# BEP33_6panel_90Grad.net
KiCad netlist of a schematic drawn in EAGLE
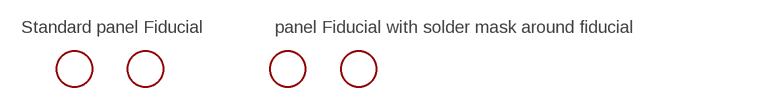
[diagram p0: schematic, sheet 1]
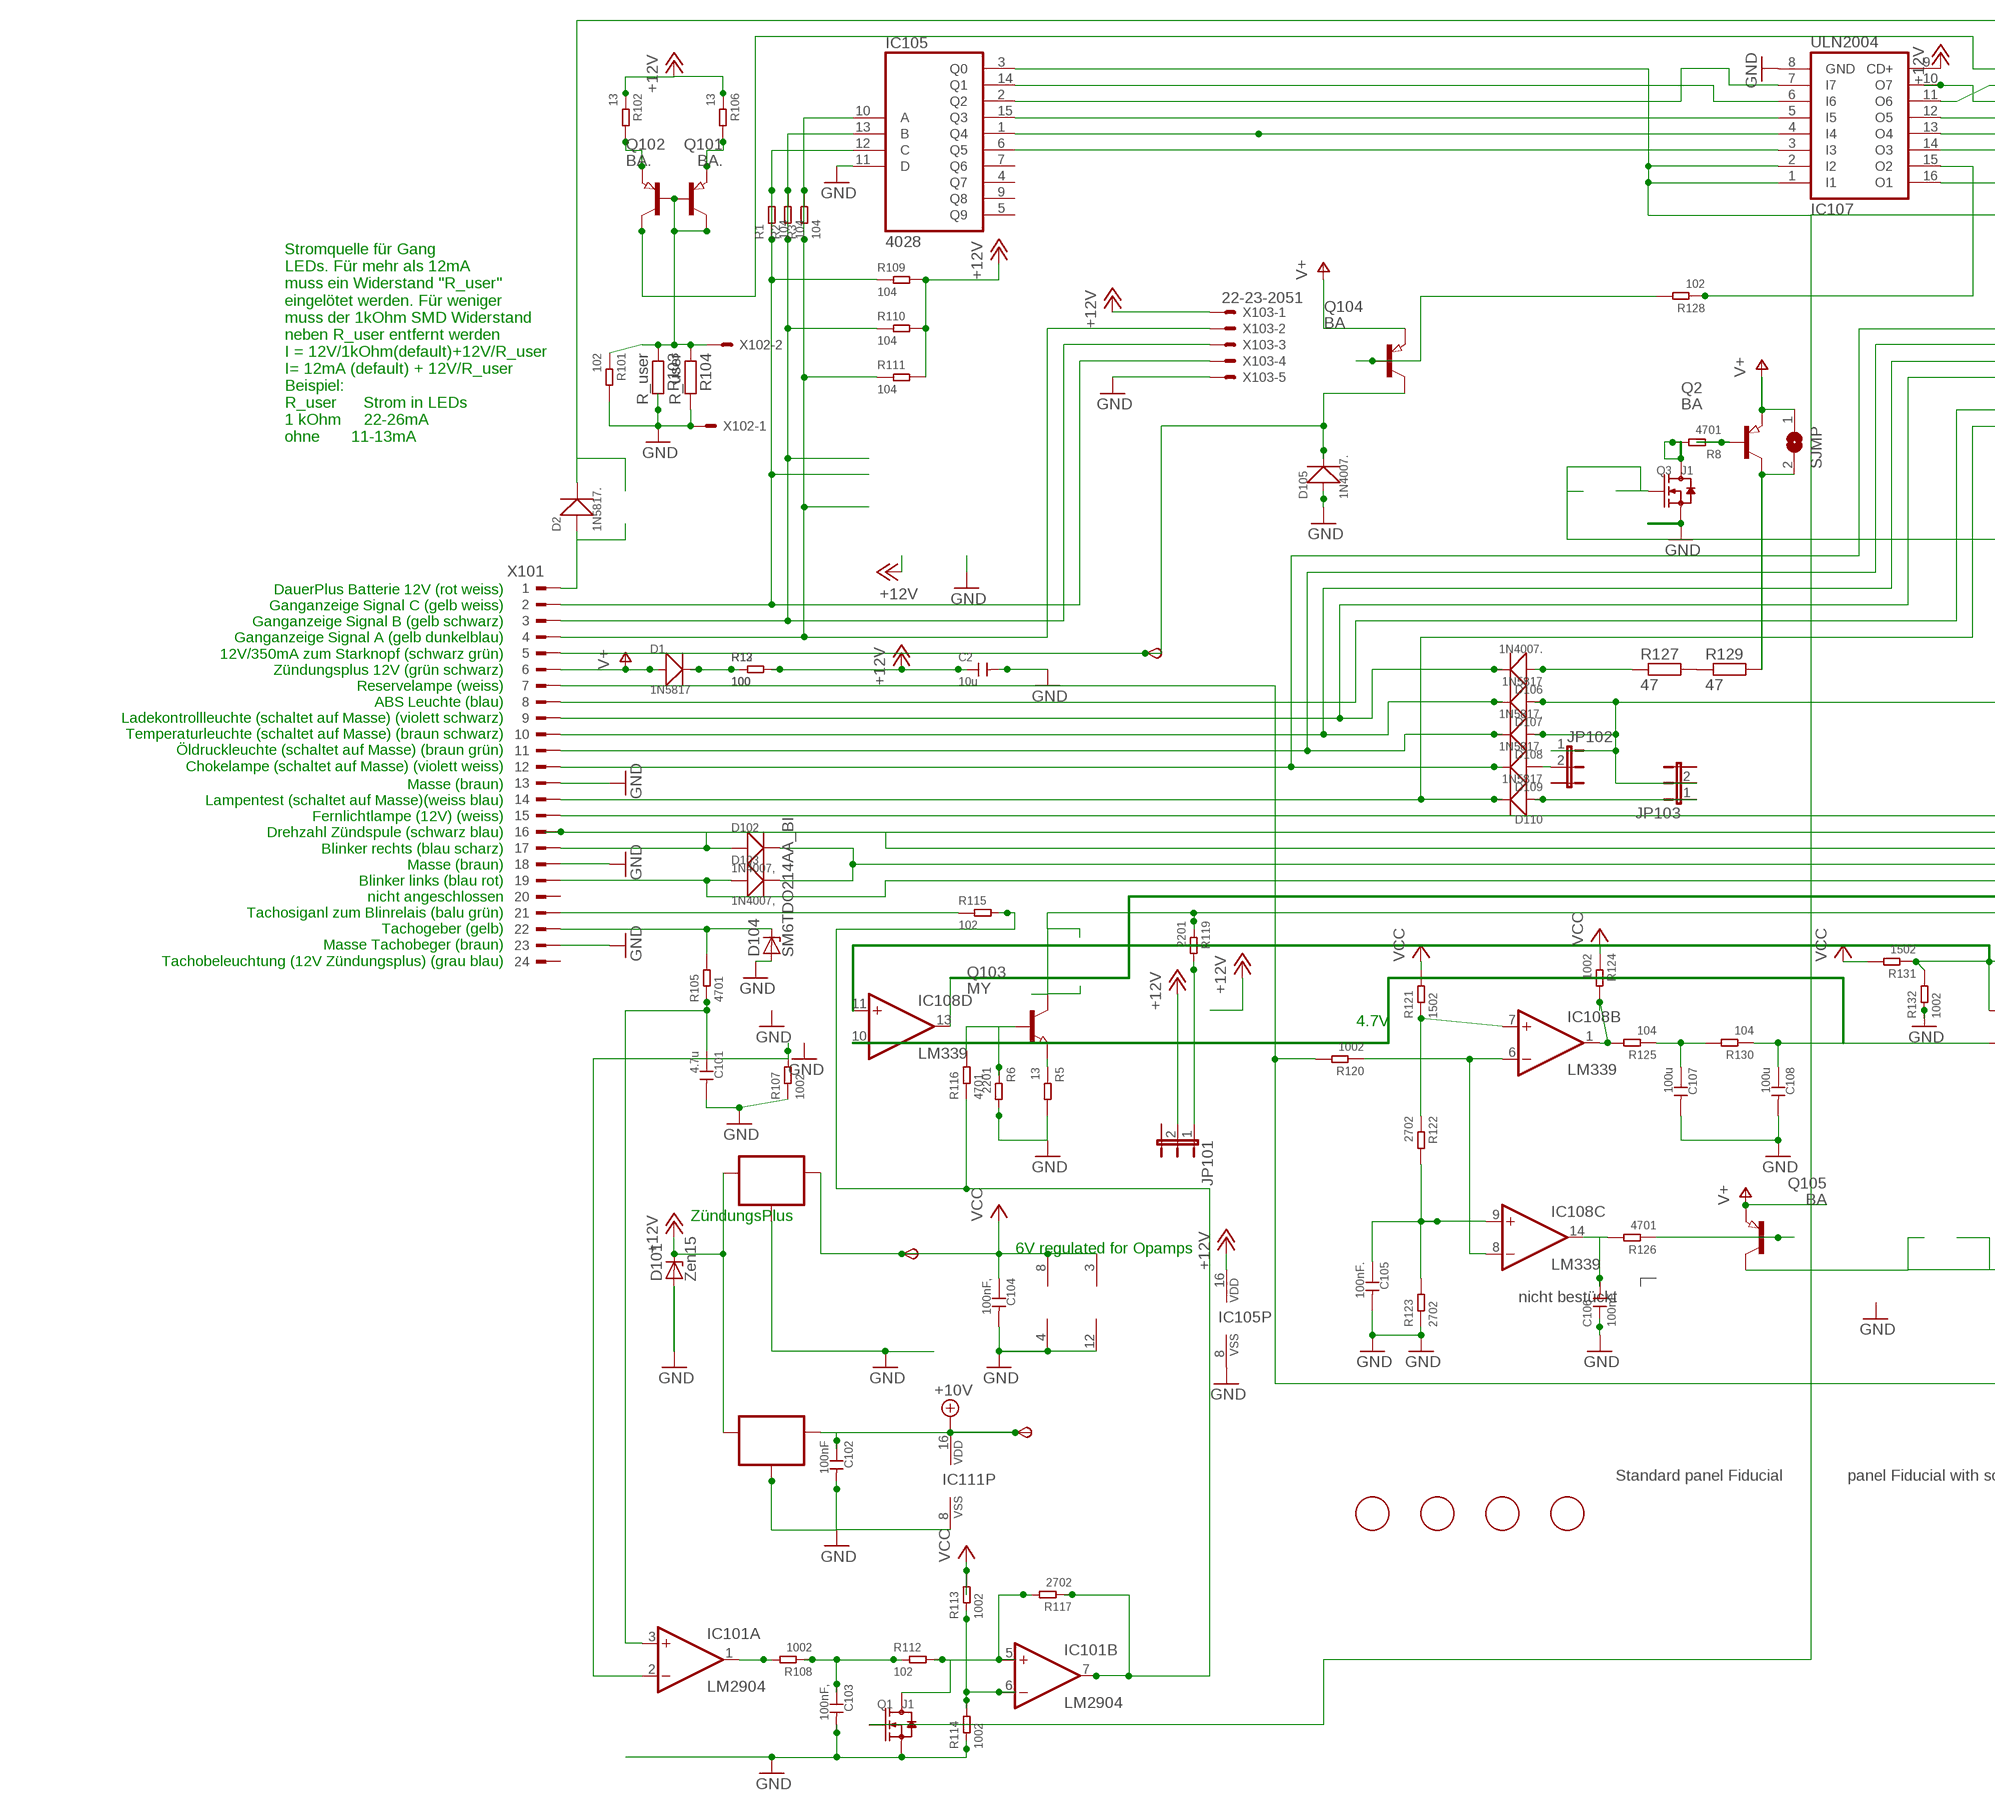
[diagram p1: schematic, sheet 2, part 1 of 2]
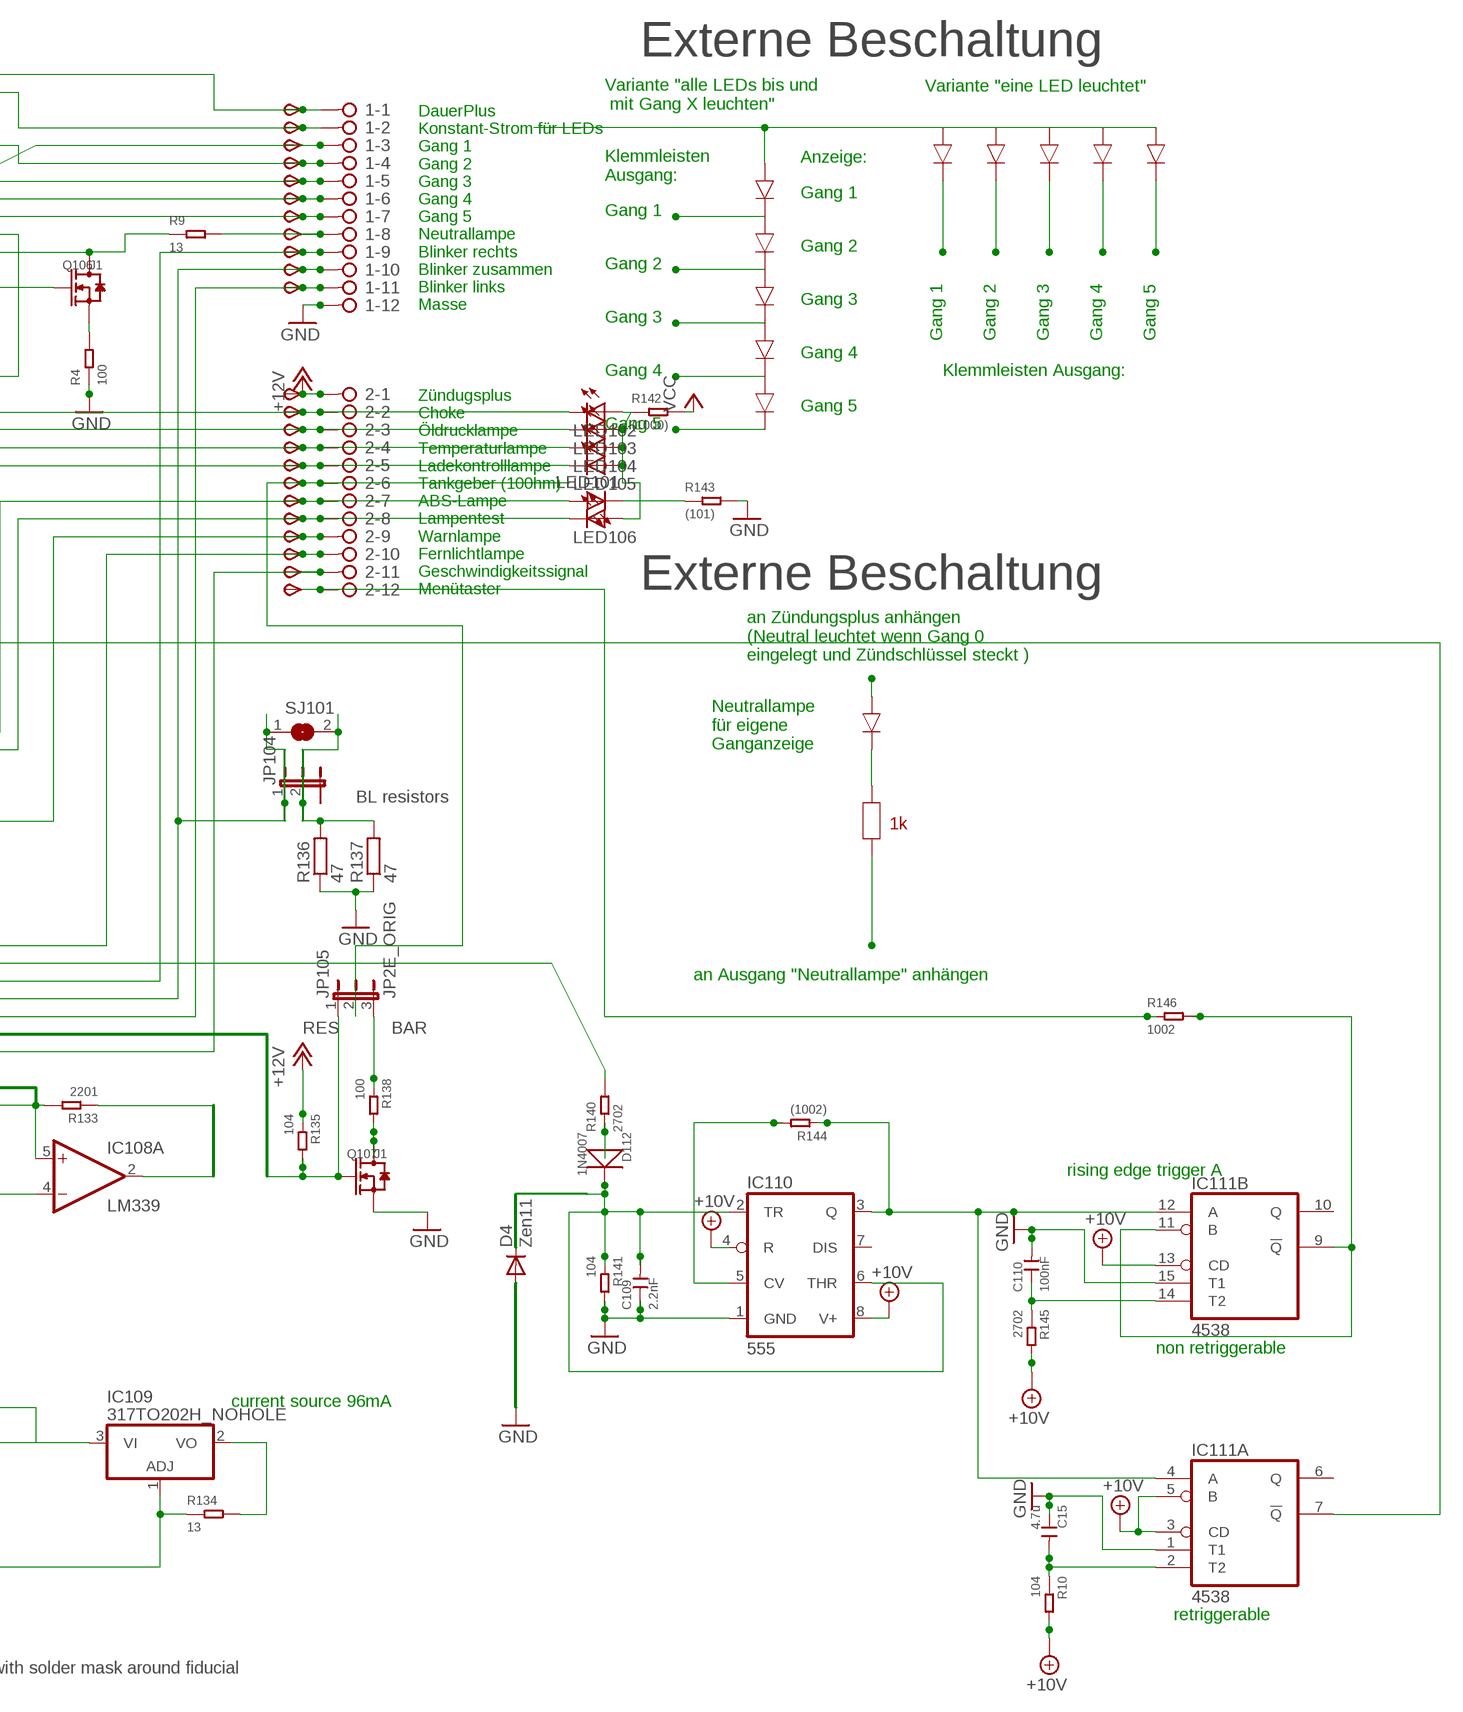
[diagram p2: schematic, sheet 2, part 2 of 2]
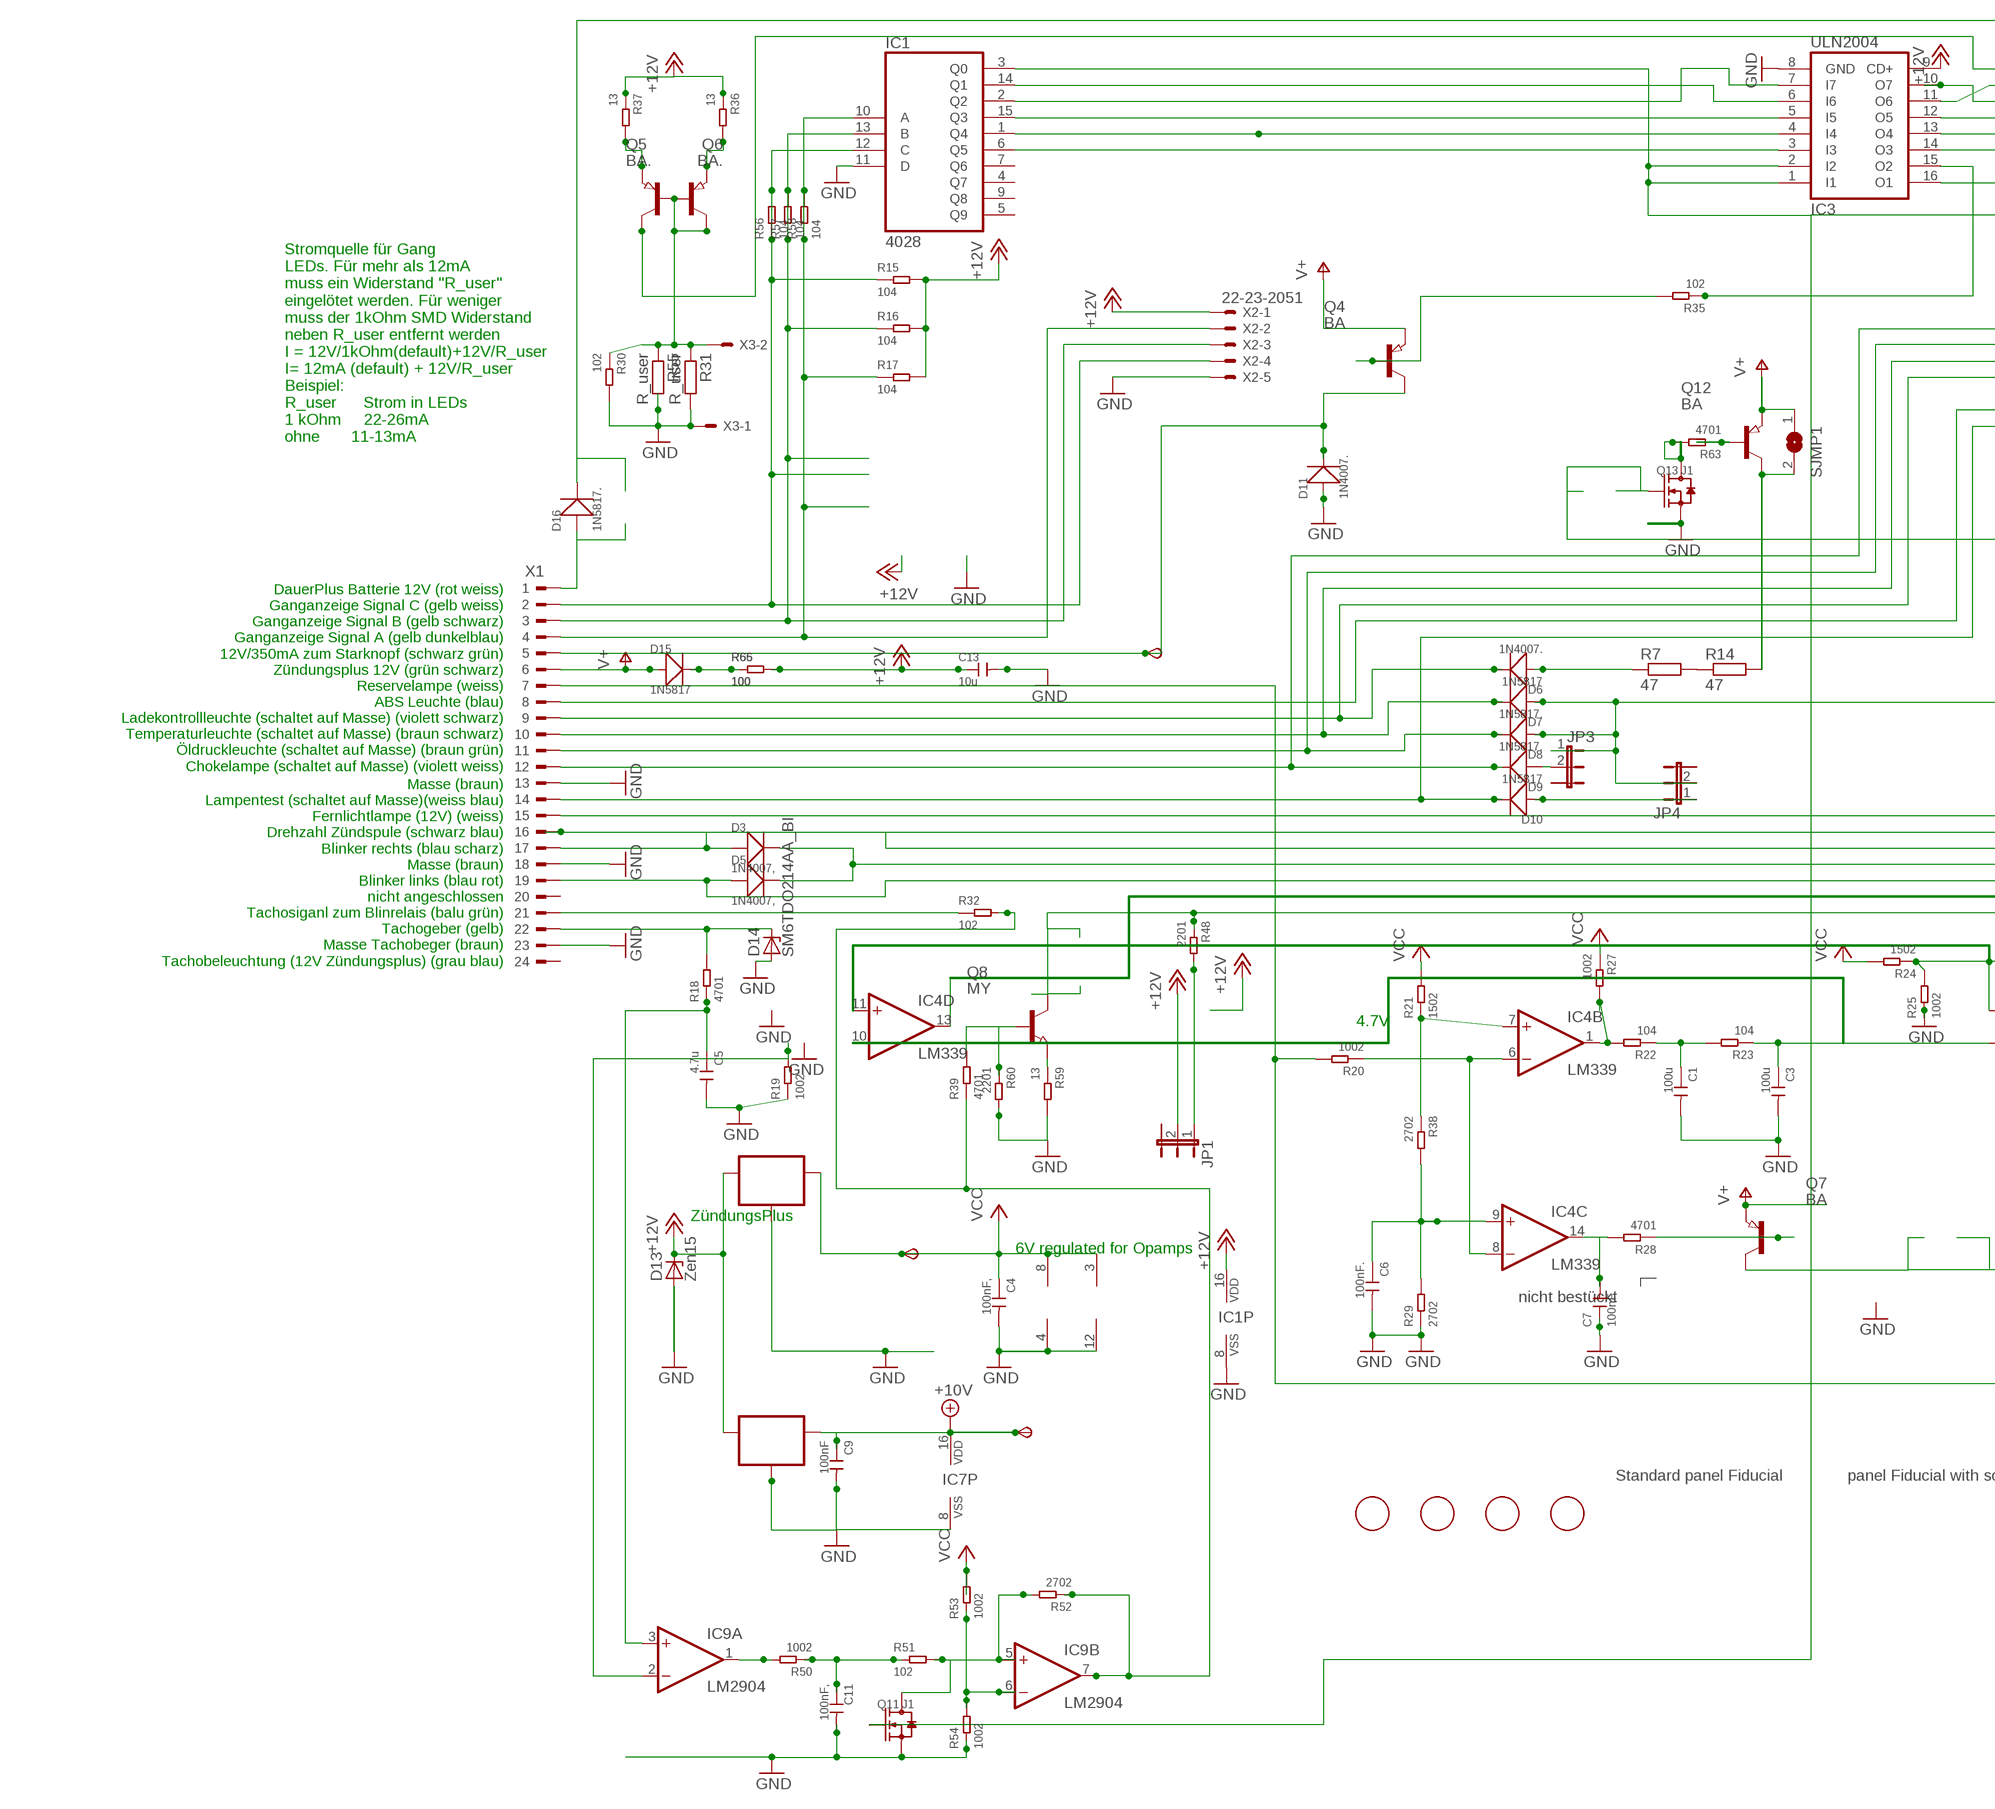
[diagram p3: schematic, sheet 3, part 1 of 2]
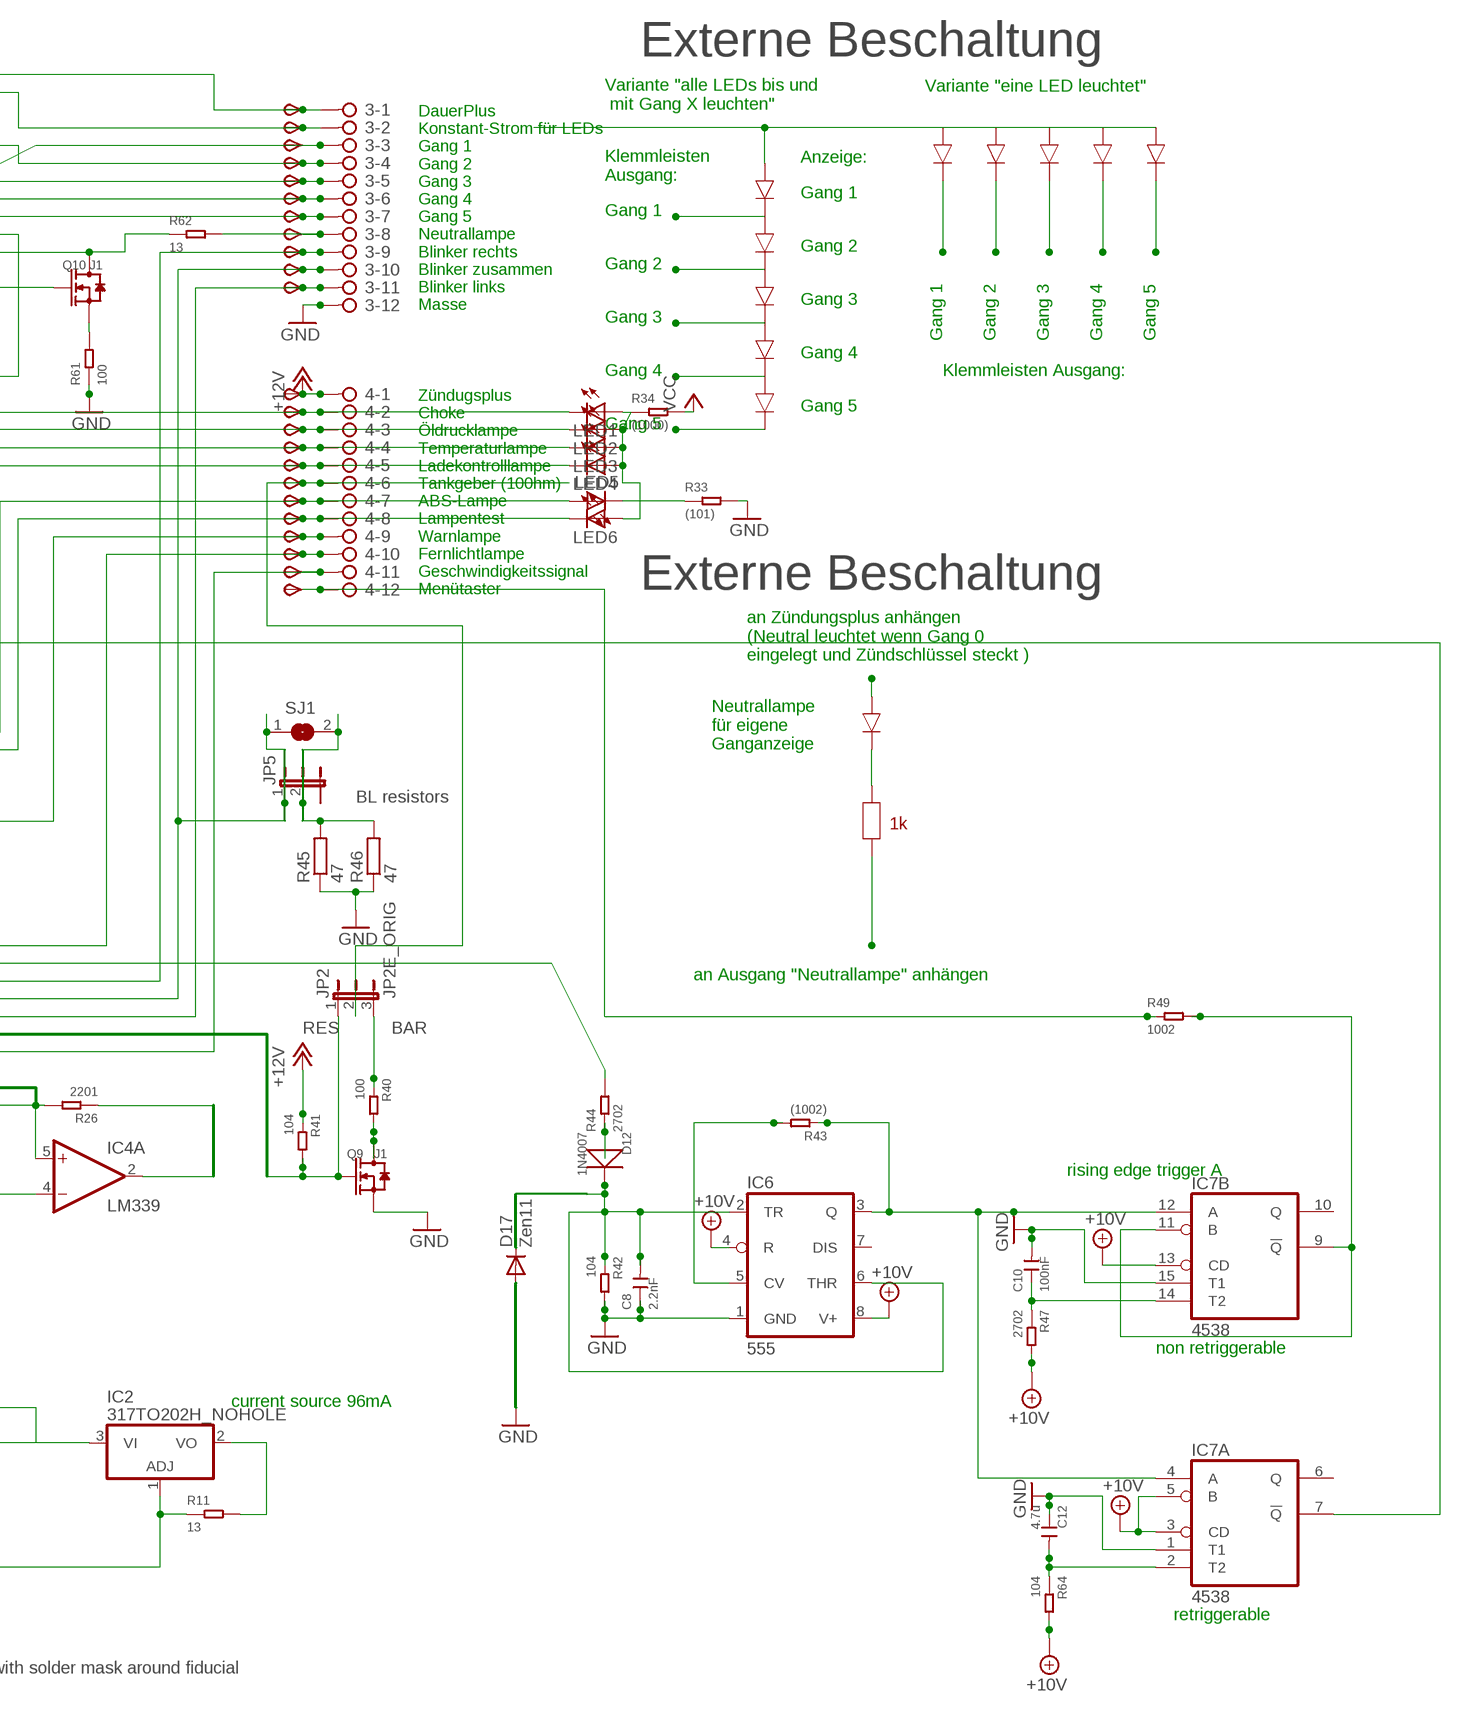
[diagram p4: schematic, sheet 3, part 2 of 2]
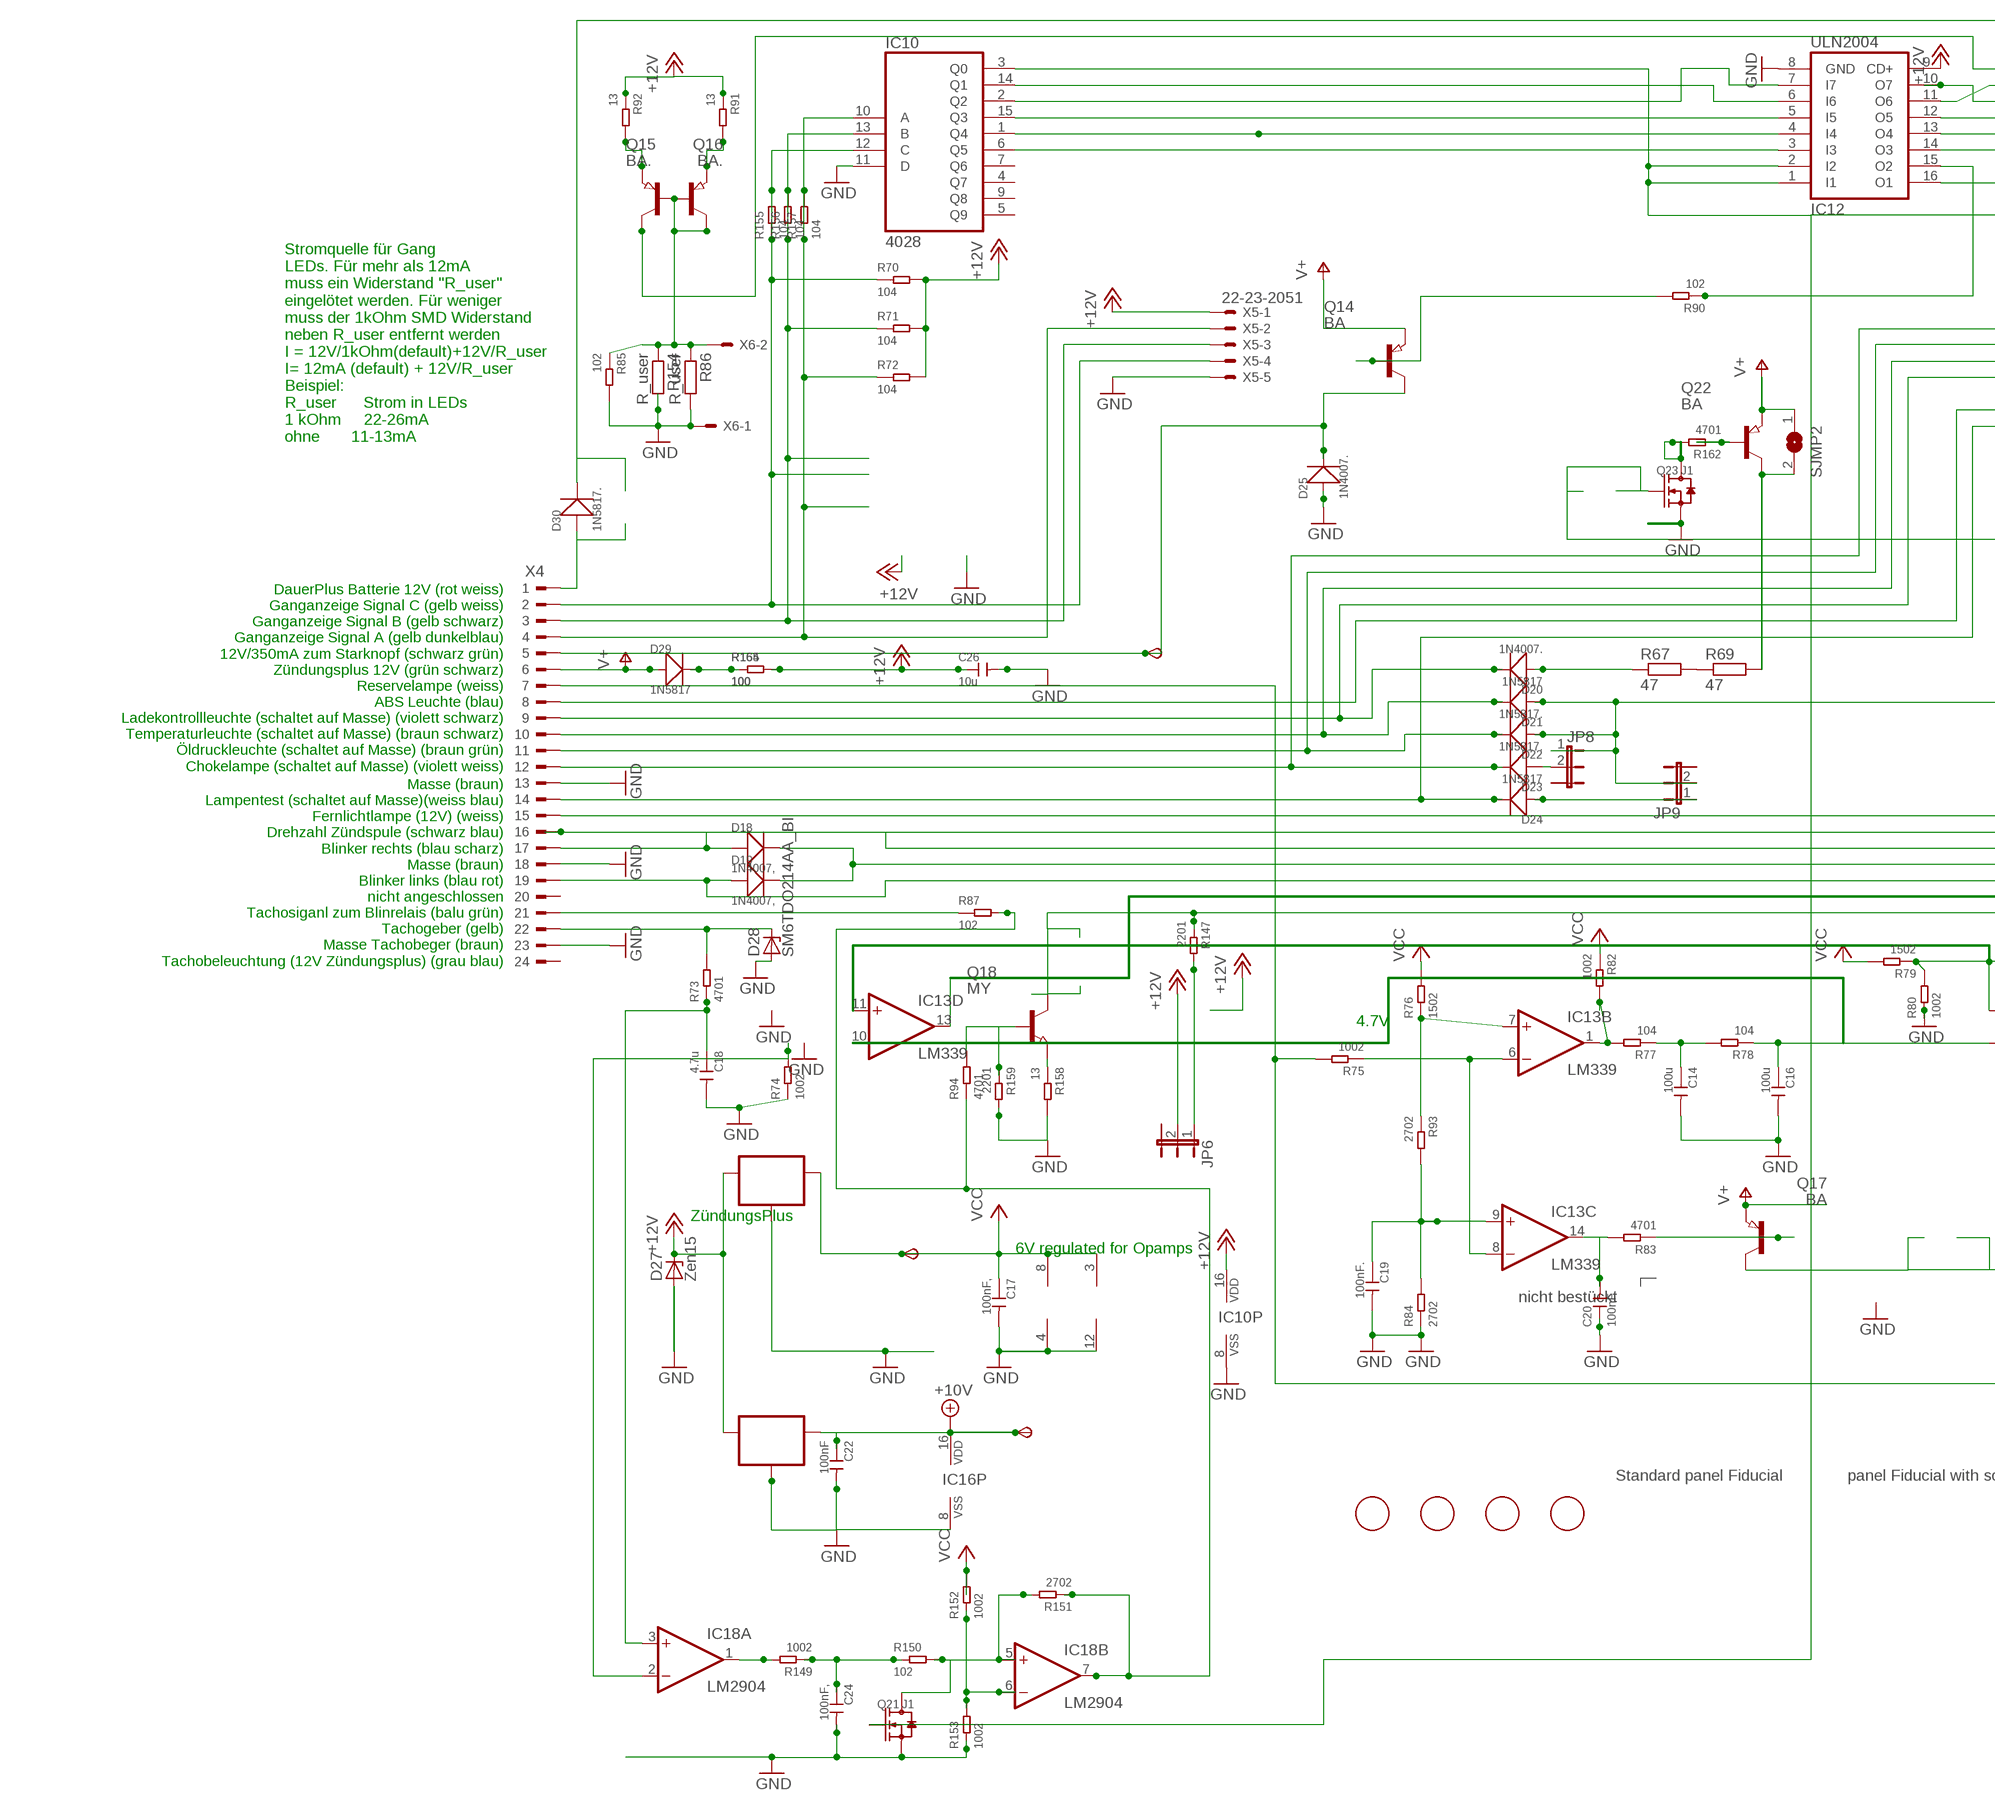
[diagram p5: schematic, sheet 4, part 1 of 2]
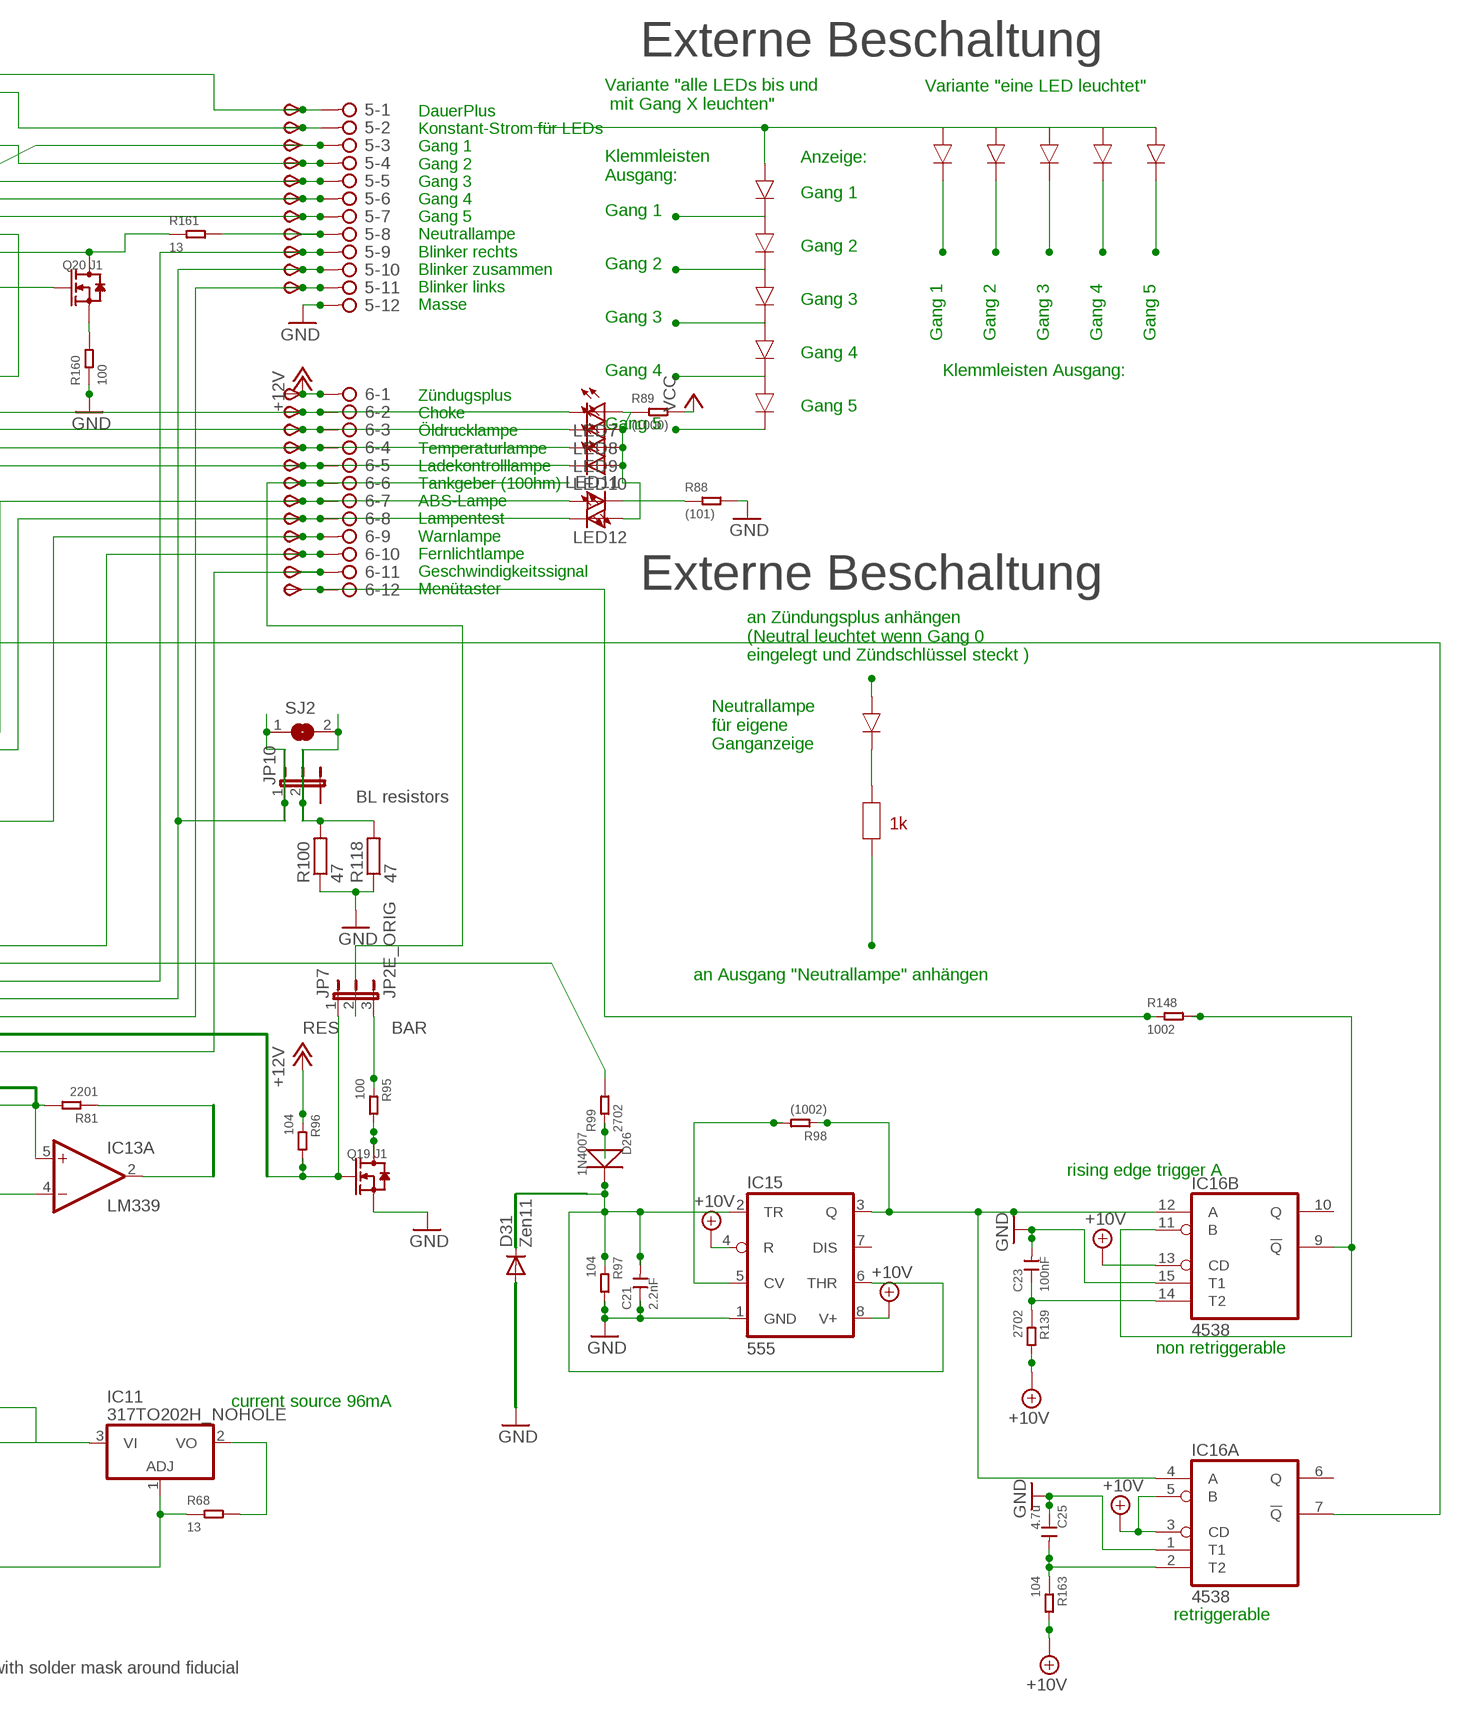
[diagram p6: schematic, sheet 4, part 2 of 2]
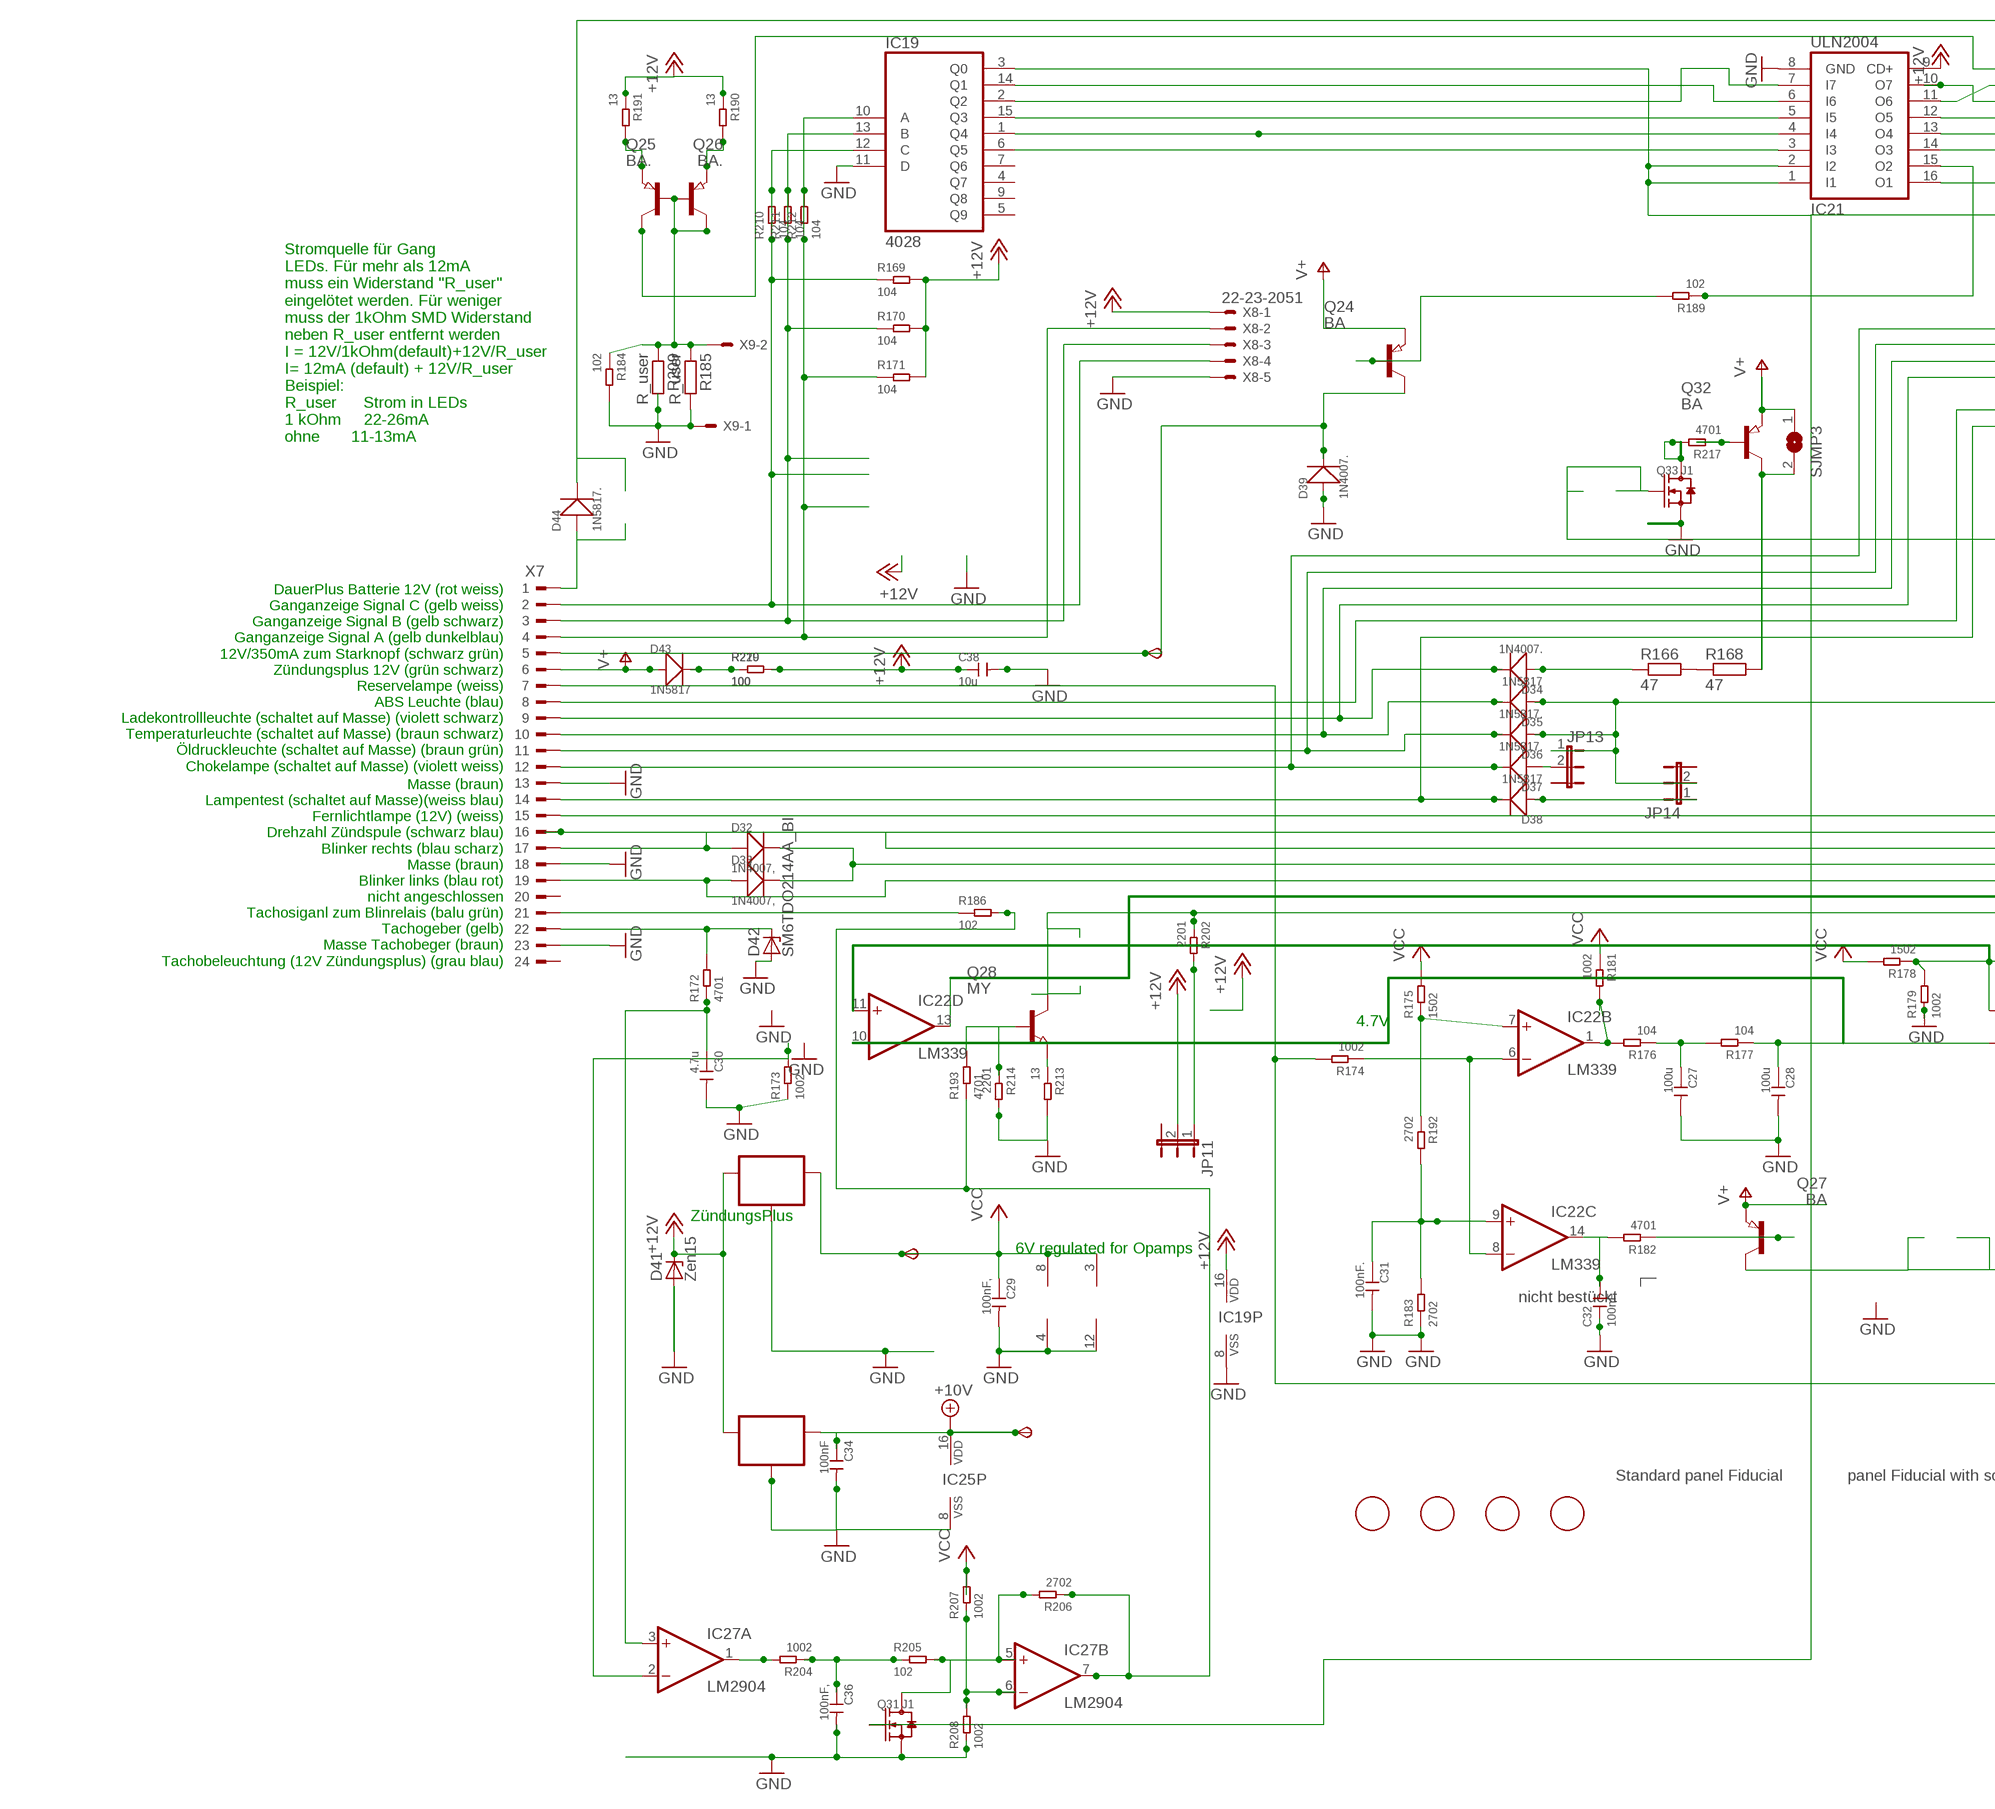
[diagram p7: schematic, sheet 5, part 1 of 2]
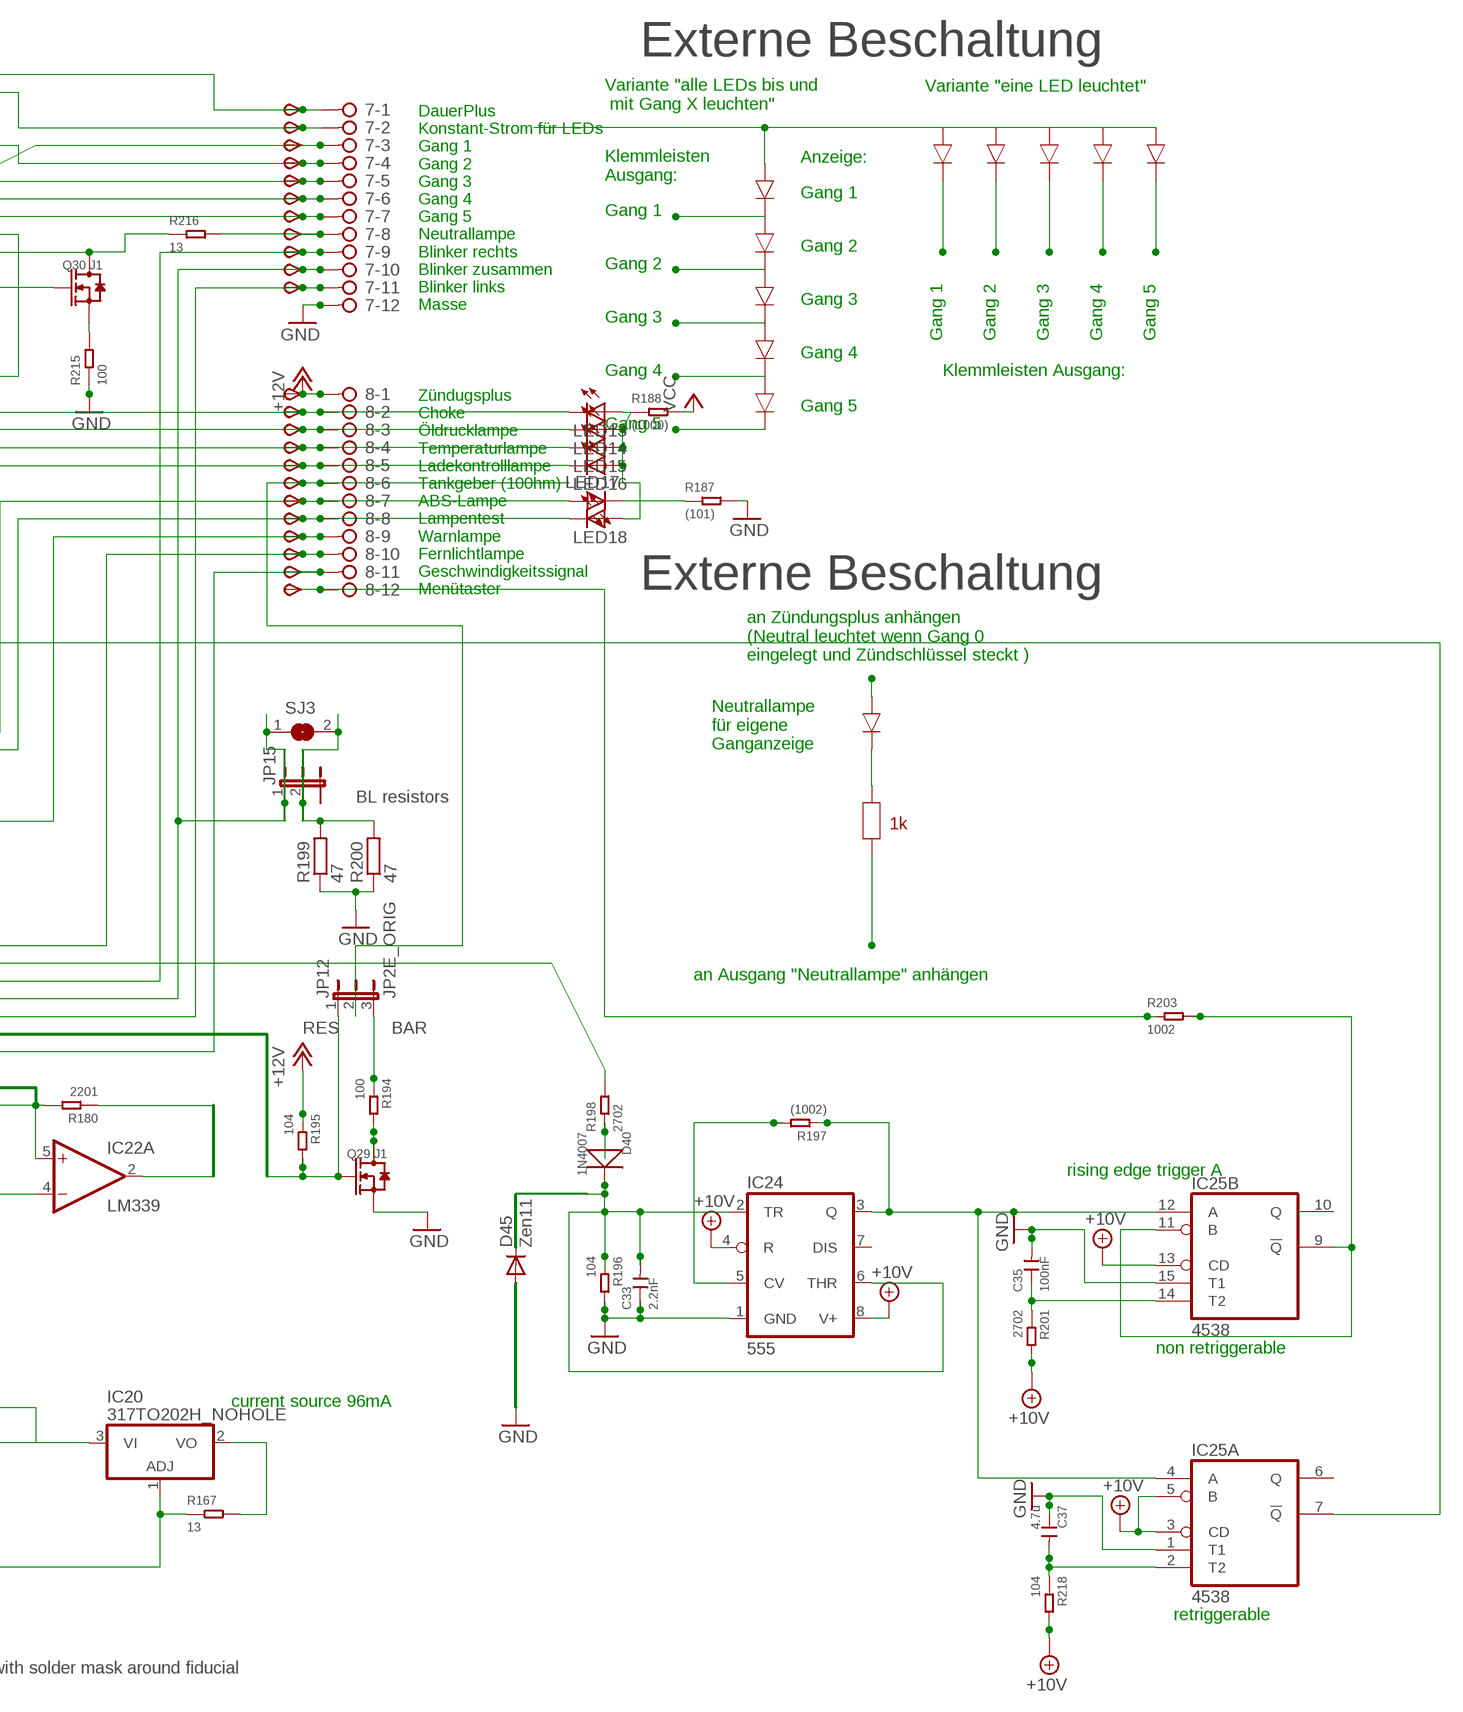
[diagram p8: schematic, sheet 5, part 2 of 2]
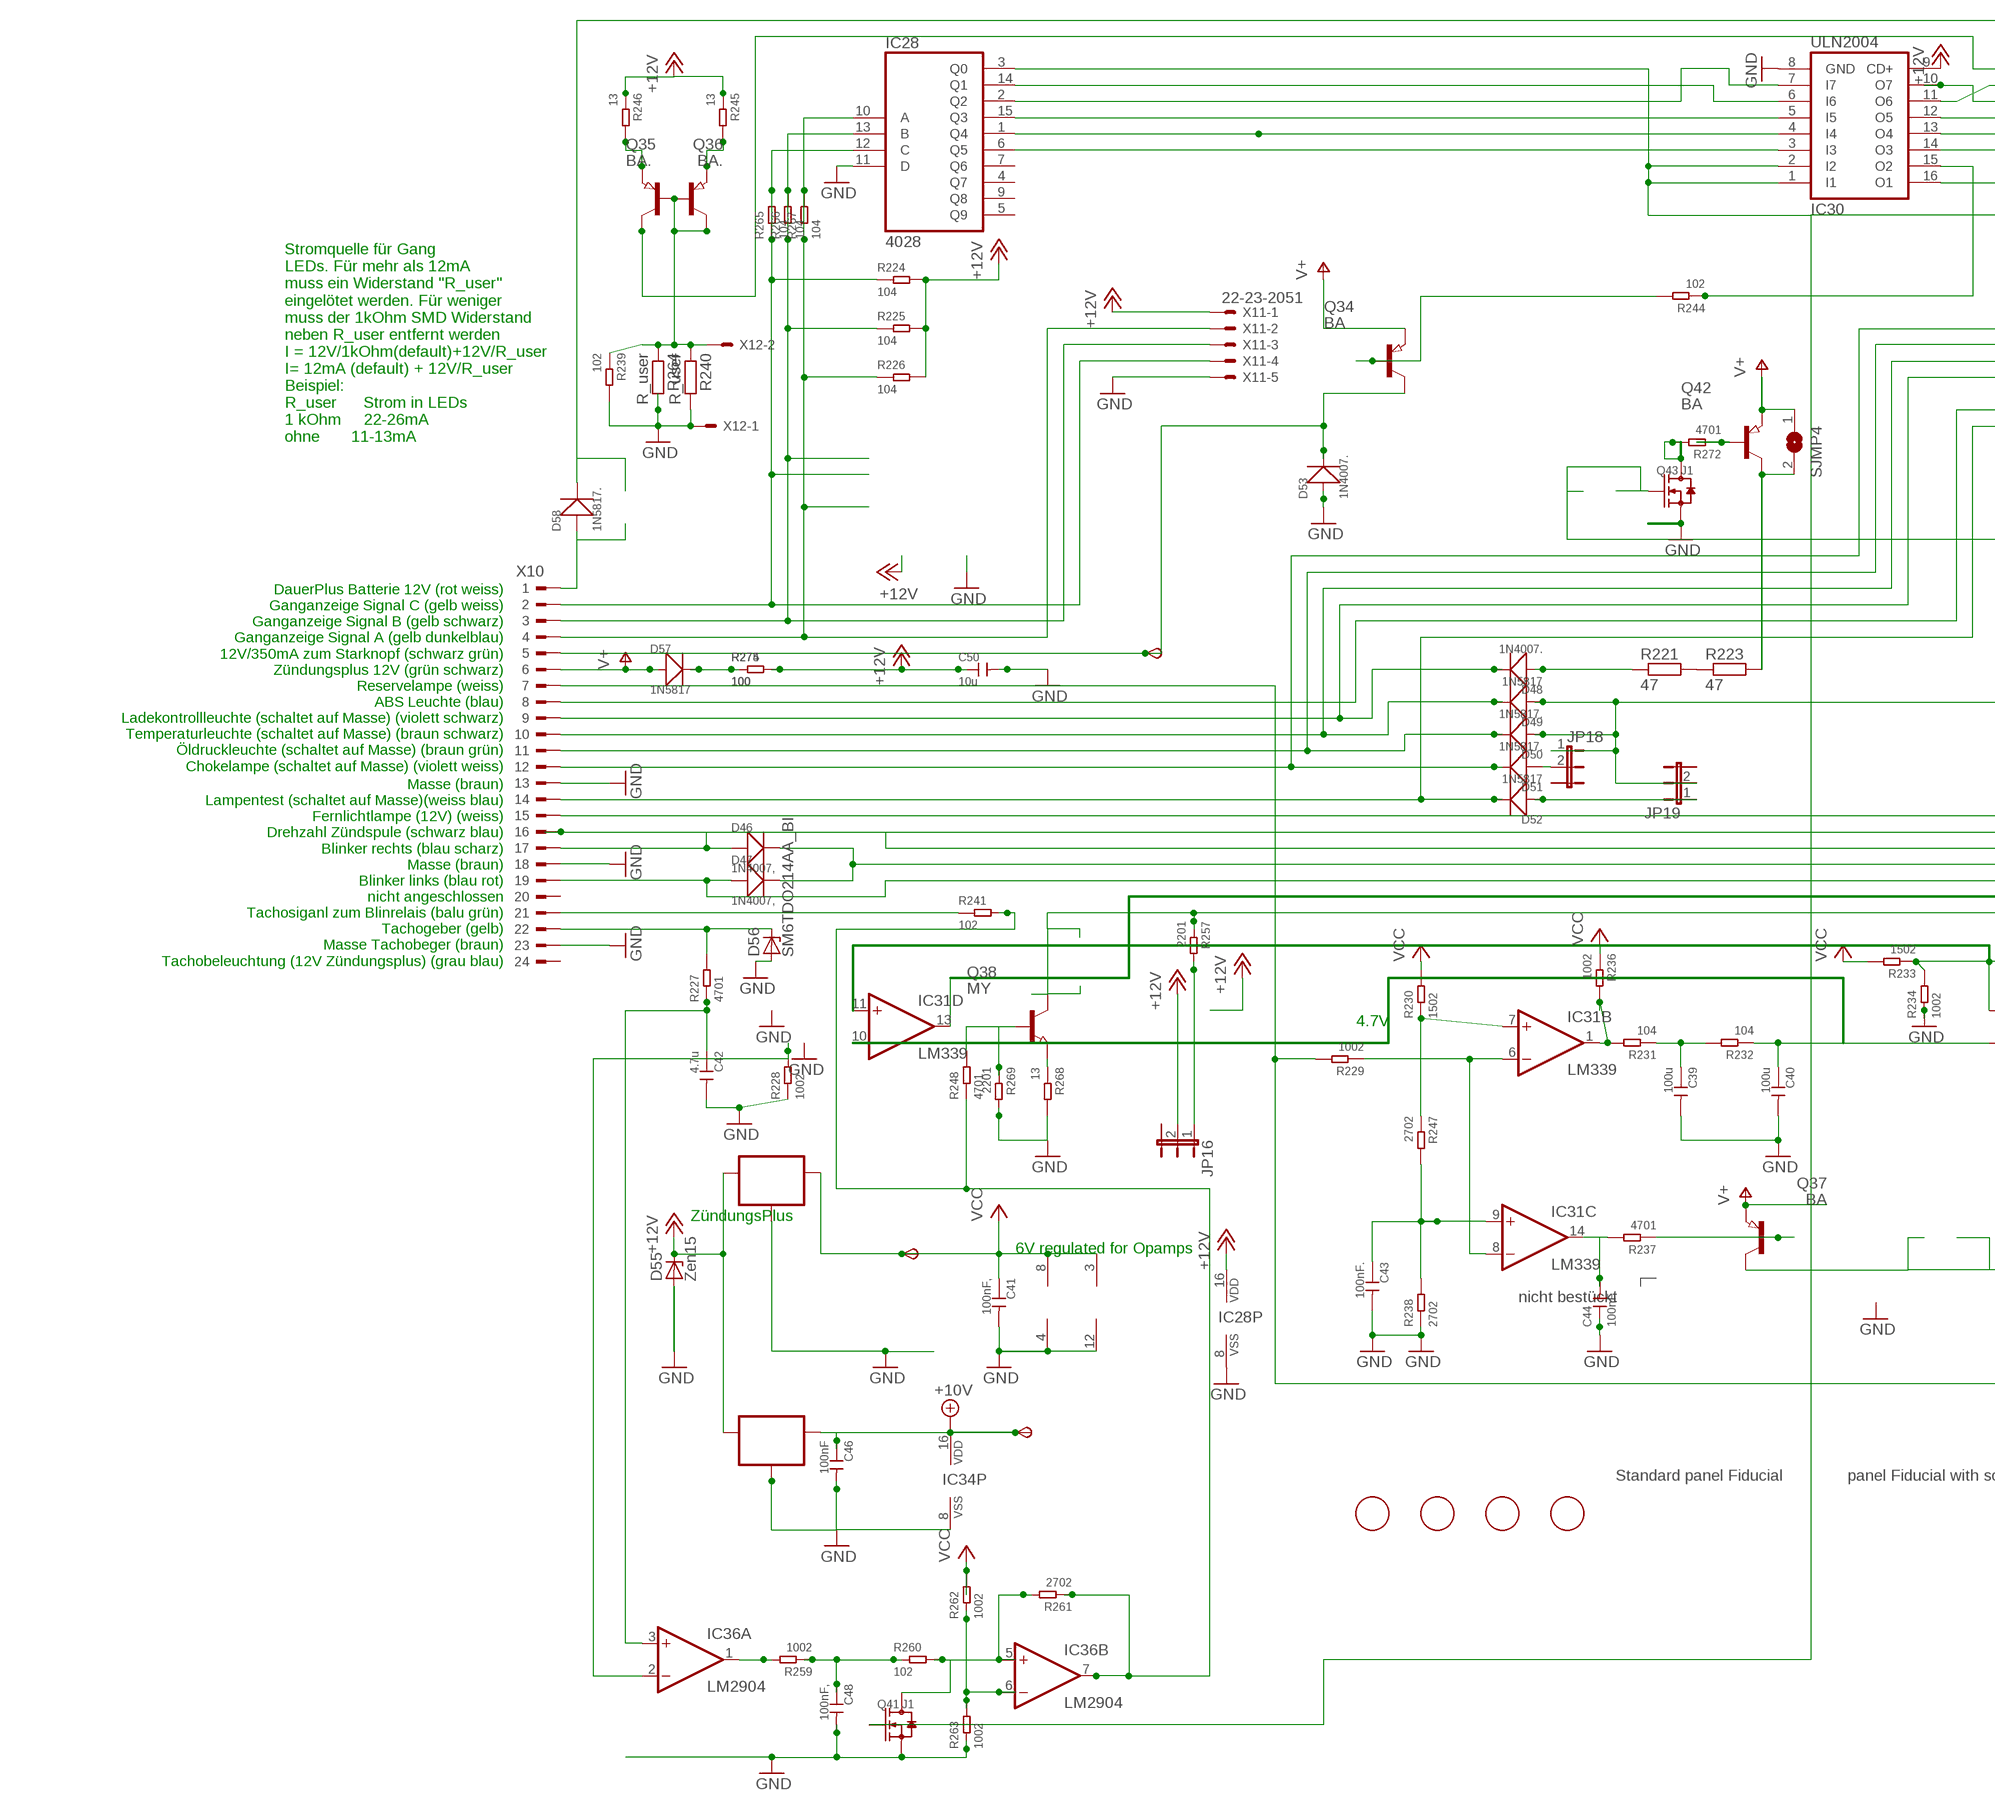
[diagram p9: schematic, sheet 6, part 1 of 2]
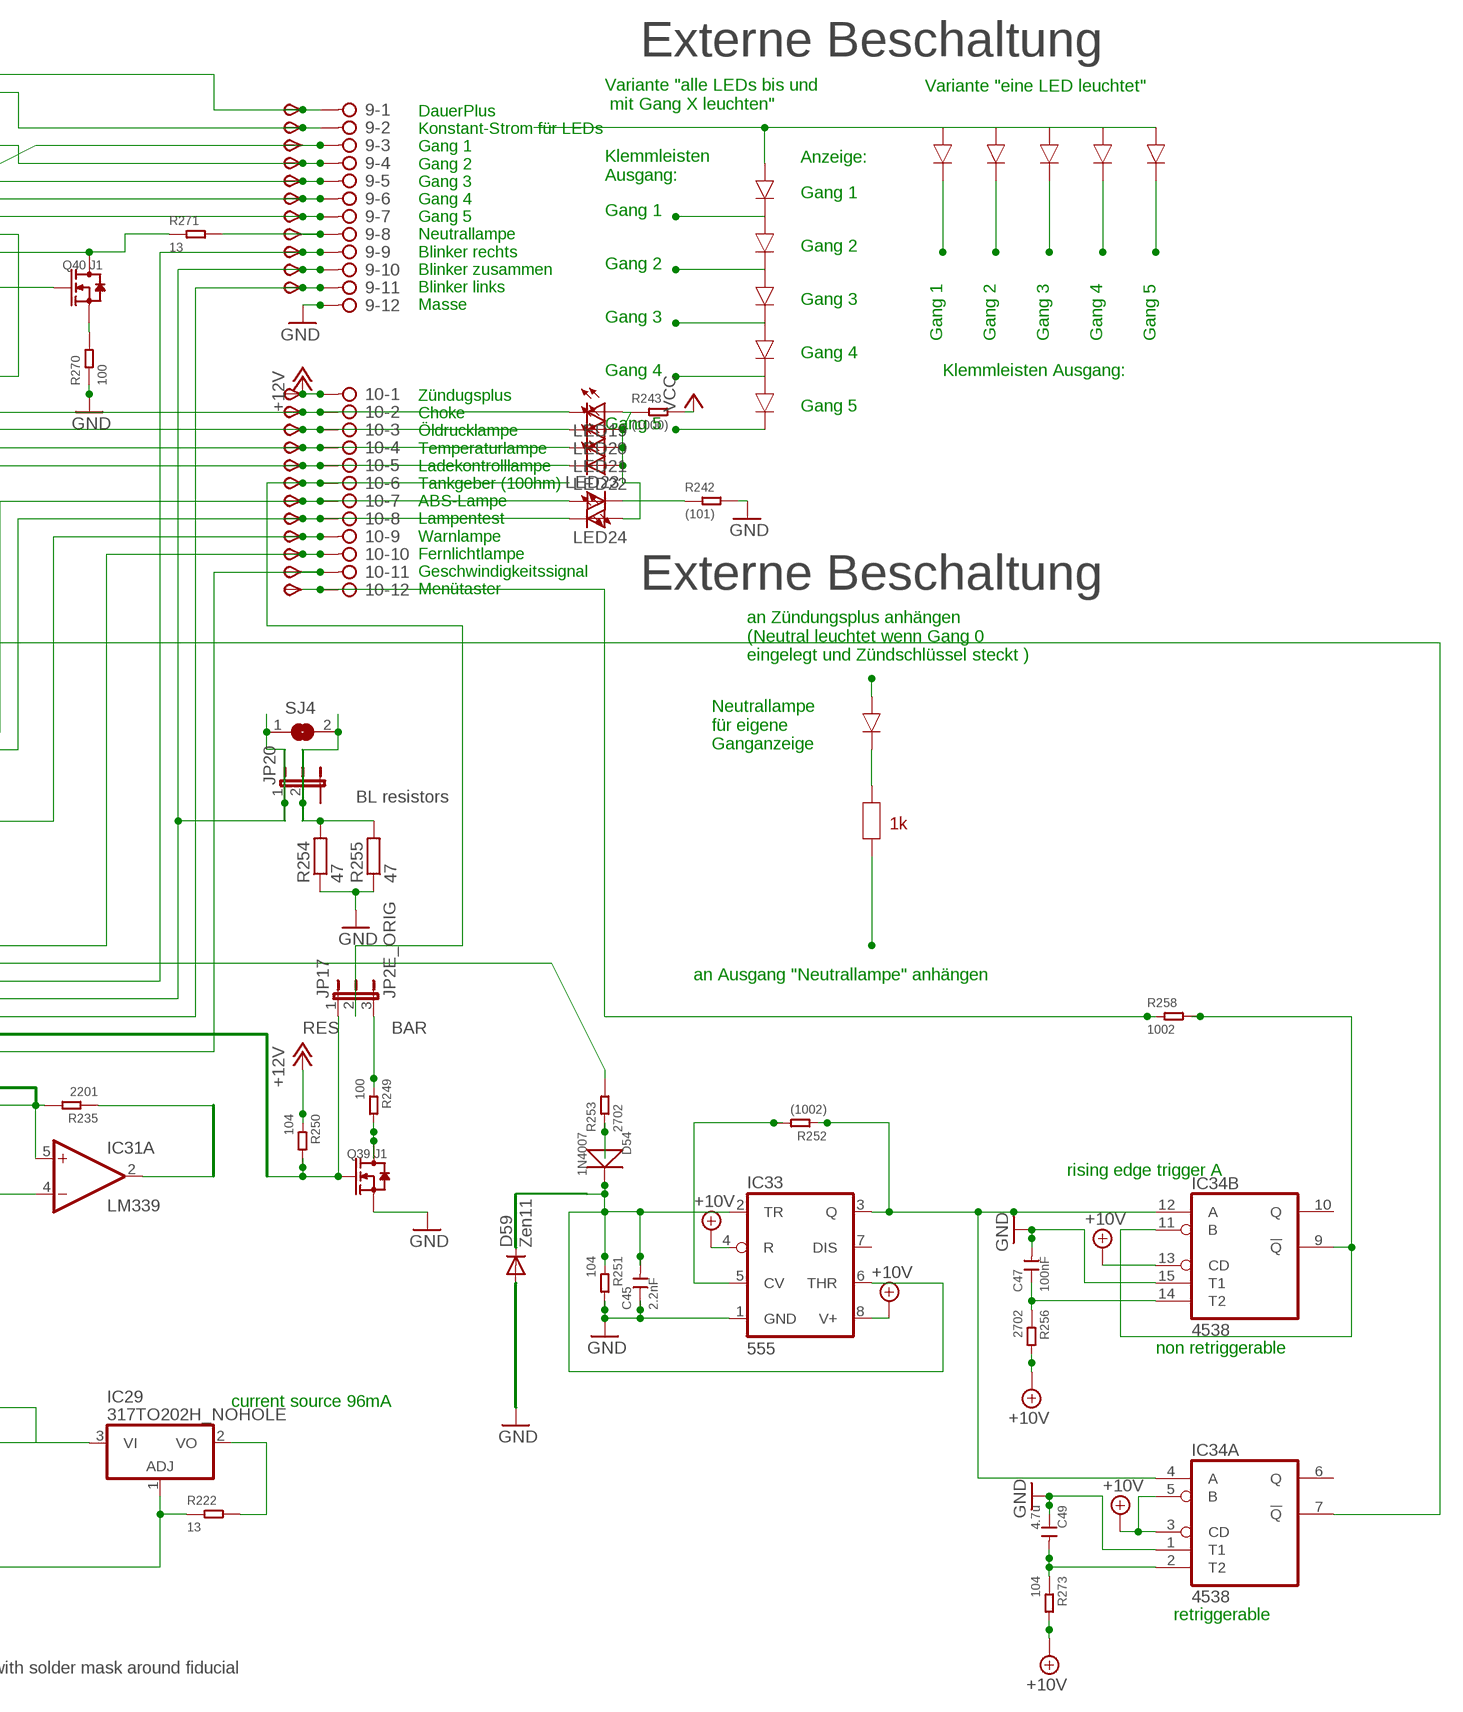
[diagram p10: schematic, sheet 6, part 2 of 2]
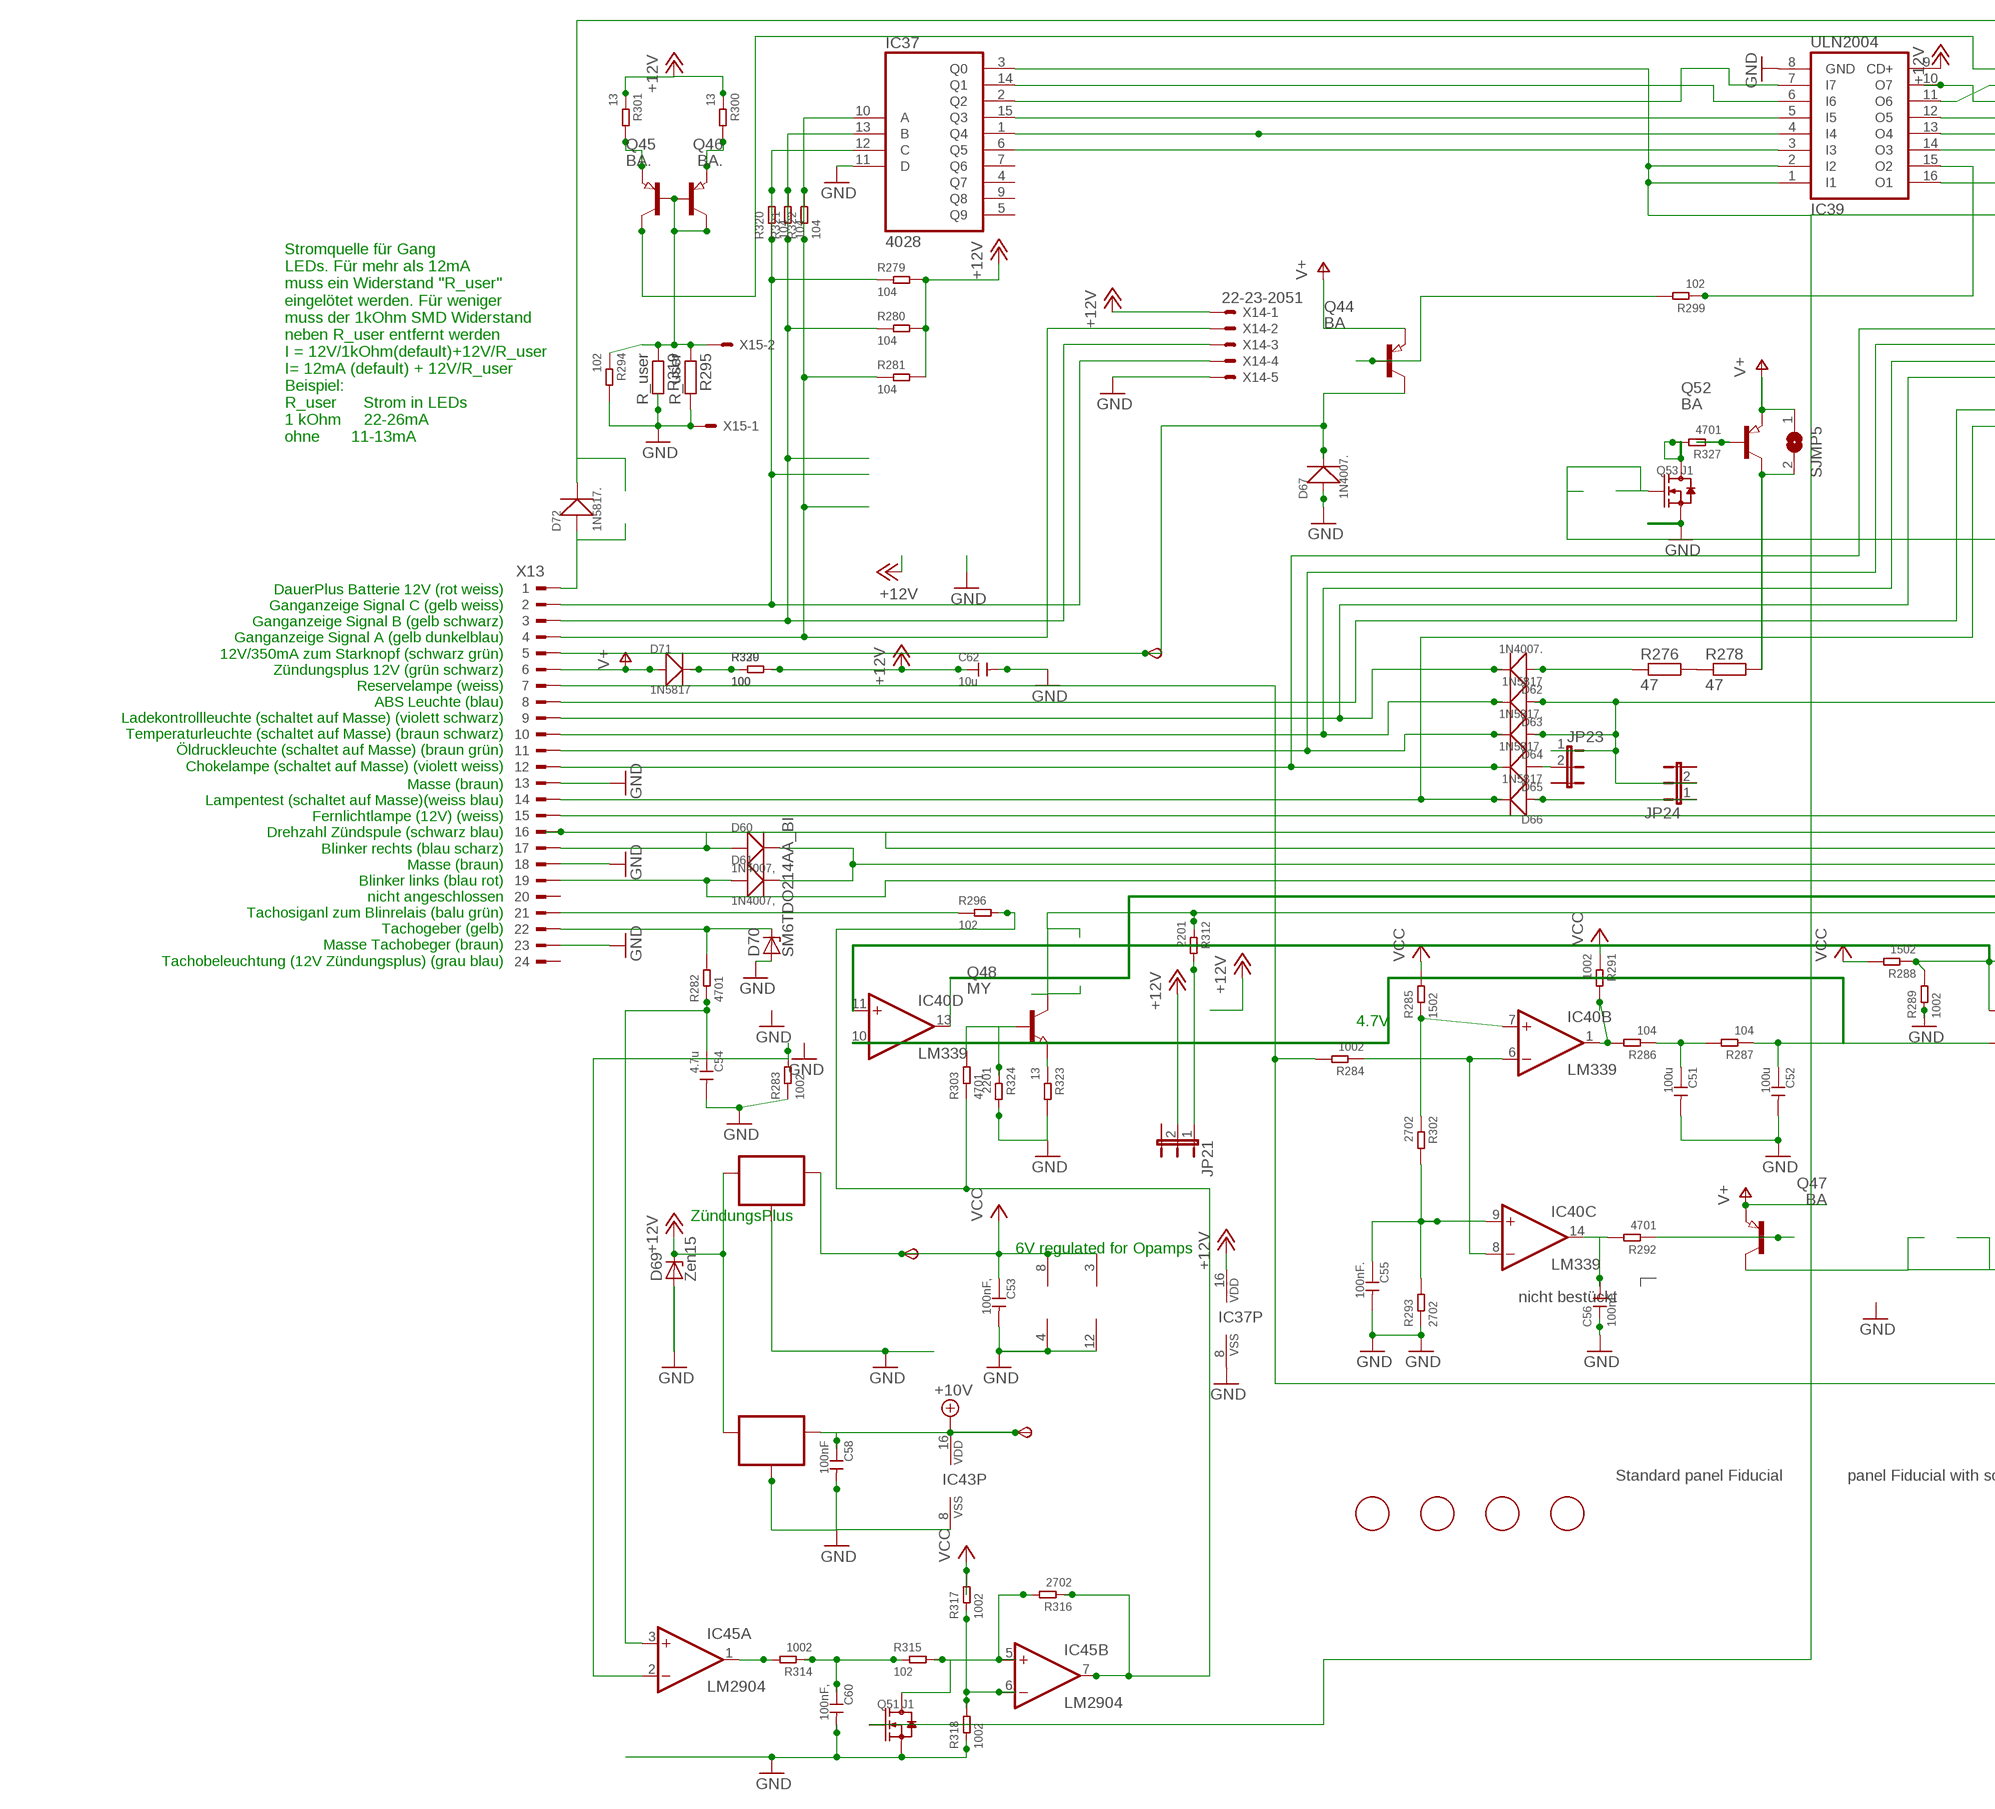
[diagram p11: schematic, sheet 7, part 1 of 2]
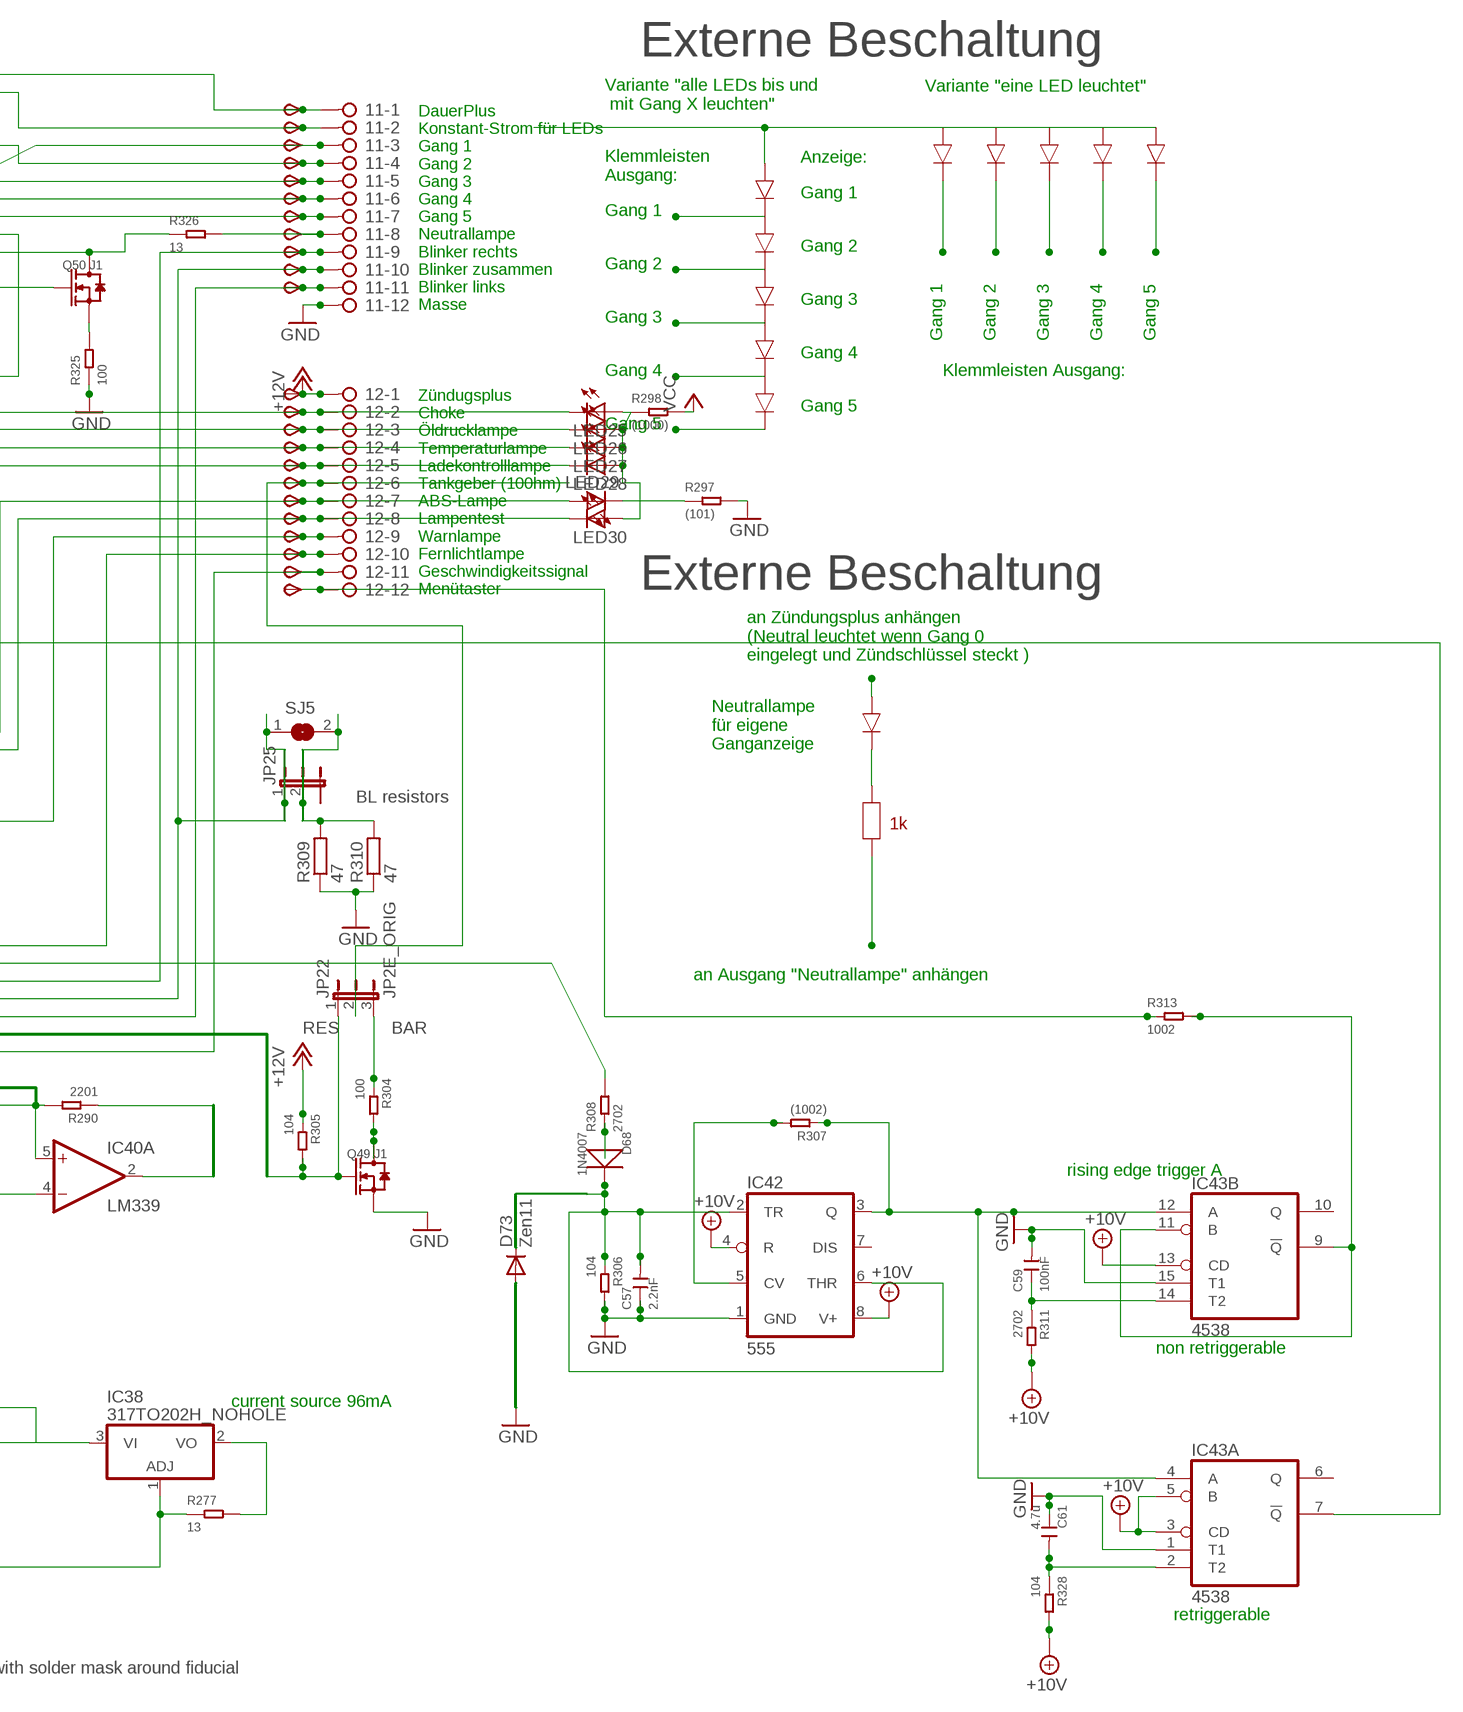
[diagram p12: schematic, sheet 7, part 2 of 2]

(export (version "E")
  (design (tool "Eeschema 10.0.6"))
  (components
    (comp (ref "1")
      (value "2081-1132")
      (footprint "eagle-import:12-PIN")
      (libsource (lib "eagle-import") (part "2081-1132"))
    )
    (comp (ref "2")
      (value "2081-1132")
      (footprint "eagle-import:12-PIN")
      (libsource (lib "eagle-import") (part "2081-1132"))
    )
    (comp (ref "6V")
      (value "TPSB2.0")
      (footprint "eagle-import:B2.0")
      (libsource (lib "eagle-import") (part "TPSB2.0"))
    )
    (comp (ref "10V")
      (value "TPSB2.0")
      (footprint "eagle-import:B2.0")
      (libsource (lib "eagle-import") (part "TPSB2.0"))
    )
    (comp (ref "C2")
      (value "10u")
      (footprint "eagle-import:C1206")
      (fields (field (name "MPN") "GRM31CR60J107ME39L"))
      (libsource (lib "eagle-import") (part "CERAMIC-100UF-6.3V-20%-X5R(1206)"))
    )
    (comp (ref "C15")
      (value "4.7u")
      (footprint "eagle-import:C0805")
      (fields (field (name "MPN") "CC0805KKX5R8BB475"))
      (libsource (lib "eagle-import") (part "CERAMIC-4.7UF-25V-10%-X5R(0805)"))
    )
    (comp (ref "C101")
      (value "4.7u")
      (footprint "eagle-import:C0805")
      (fields (field (name "MPN") "CC0805KKX5R8BB475"))
      (libsource (lib "eagle-import") (part "CERAMIC-4.7UF-25V-10%-X5R(0805)"))
    )
    (comp (ref "C102")
      (value "100nF")
      (footprint "eagle-import:C0805")
      (fields (field (name "MPN") "CC0805KRX7R9BB104"))
      (libsource (lib "eagle-import") (part "CERAMIC-100NF-50V-10%-X7R(0805)"))
    )
    (comp (ref "C103")
      (value "100nF,")
      (footprint "eagle-import:C0805")
      (fields (field (name "MPN") "CC0805KRX7R9BB104"))
      (libsource (lib "eagle-import") (part "CERAMIC-100NF-50V-10%-X7R(0805)"))
    )
    (comp (ref "C104")
      (value "100nF,")
      (footprint "eagle-import:C0805")
      (fields (field (name "MPN") "CC0805KRX7R9BB104"))
      (libsource (lib "eagle-import") (part "CERAMIC-100NF-50V-10%-X7R(0805)"))
    )
    (comp (ref "C105")
      (value "100nF.")
      (footprint "eagle-import:C0805")
      (fields (field (name "MPN") "CC0805KRX7R9BB104"))
      (libsource (lib "eagle-import") (part "CERAMIC-100NF-50V-10%-X7R(0805)"))
    )
    (comp (ref "C106")
      (value "100nF.")
      (footprint "eagle-import:C0805")
      (fields (field (name "MPN") "CC0805KRX7R9BB104"))
      (libsource (lib "eagle-import") (part "CERAMIC-100NF-50V-10%-X7R(0805)"))
    )
    (comp (ref "C107")
      (value "100u")
      (footprint "eagle-import:C1206")
      (fields (field (name "MPN") "GRM31CR60J107ME39L"))
      (libsource (lib "eagle-import") (part "CERAMIC-100UF-6.3V-20%-X5R(1206)"))
    )
    (comp (ref "C108")
      (value "100u")
      (footprint "eagle-import:C1206")
      (fields (field (name "MPN") "GRM31CR60J107ME39L"))
      (libsource (lib "eagle-import") (part "CERAMIC-100UF-6.3V-20%-X5R(1206)"))
    )
    (comp (ref "C109")
      (value "2.2nF")
      (footprint "eagle-import:C0805")
      (fields (field (name "MPN") "CC0805KRX7R9BB104"))
      (libsource (lib "eagle-import") (part "CERAMIC-100NF-50V-10%-X7R(0805)"))
    )
    (comp (ref "C110")
      (value "100nF")
      (footprint "eagle-import:C0805")
      (fields (field (name "MPN") "CC0805KRX7R9BB104"))
      (libsource (lib "eagle-import") (part "CERAMIC-100NF-50V-10%-X7R(0805)"))
    )
    (comp (ref "D1")
      (value "1N5817")
      (footprint "eagle-import:DO-214AC_SLIM")
      (libsource (lib "eagle-import") (part "DIODE-GEN-PURPOSE-1KV-1A(DO-214AC)DO-214AC/1206"))
    )
    (comp (ref "D2")
      (value "1N5817.")
      (footprint "eagle-import:DO-214AC_SLIM")
      (libsource (lib "eagle-import") (part "DIODE-GEN-PURPOSE-1KV-1A(DO-214AC)DO-214AC/1206"))
    )
    (comp (ref "D4")
      (value "Zen11")
      (footprint "eagle-import:SOD-123_MINI-SMA")
      (libsource (lib "eagle-import") (part "CGRM400-G1"))
    )
    (comp (ref "D101")
      (value "Zen15")
      (footprint "eagle-import:DO214AA")
      (libsource (lib "eagle-import") (part "SM6T"))
    )
    (comp (ref "D102")
      (value "1N4007,")
      (footprint "eagle-import:DO-214AC")
      (fields (field (name "MPN") "1N4007"))
      (libsource (lib "eagle-import") (part "DIODE-GEN-PURPOSE-1KV-1A(DO-214AC)"))
    )
    (comp (ref "D103")
      (value "1N4007,")
      (footprint "eagle-import:DO-214AC")
      (fields (field (name "MPN") "1N4007"))
      (libsource (lib "eagle-import") (part "DIODE-GEN-PURPOSE-1KV-1A(DO-214AC)"))
    )
    (comp (ref "D104")
      (value "SM6TDO214AA_BI")
      (footprint "eagle-import:DO214AA_BI")
      (libsource (lib "eagle-import") (part "SM6TDO214AA_BI"))
    )
    (comp (ref "D105")
      (value "1N4007.")
      (footprint "eagle-import:DO-214AC")
      (fields (field (name "MPN") "1N4007"))
      (libsource (lib "eagle-import") (part "DIODE-GEN-PURPOSE-1KV-1A(DO-214AC)"))
    )
    (comp (ref "D106")
      (value "1N4007.")
      (footprint "eagle-import:DO-214AC")
      (fields (field (name "MPN") "1N4007"))
      (libsource (lib "eagle-import") (part "DIODE-GEN-PURPOSE-1KV-1A(DO-214AC)"))
    )
    (comp (ref "D107")
      (value "1N5817")
      (footprint "eagle-import:DO-214AC_SLIM")
      (libsource (lib "eagle-import") (part "DIODE-GEN-PURPOSE-1KV-1A(DO-214AC)DO-214AC/1206"))
    )
    (comp (ref "D108")
      (value "1N5817.")
      (footprint "eagle-import:DO-214AC_SLIM")
      (libsource (lib "eagle-import") (part "DIODE-GEN-PURPOSE-1KV-1A(DO-214AC)DO-214AC/1206"))
    )
    (comp (ref "D109")
      (value "1N5817.")
      (footprint "eagle-import:DO-214AC_SLIM")
      (libsource (lib "eagle-import") (part "DIODE-GEN-PURPOSE-1KV-1A(DO-214AC)DO-214AC/1206"))
    )
    (comp (ref "D110")
      (value "1N5817")
      (footprint "eagle-import:DO-214AC_SLIM")
      (libsource (lib "eagle-import") (part "DIODE-GEN-PURPOSE-1KV-1A(DO-214AC)DO-214AC/1206"))
    )
    (comp (ref "D112")
      (value "1N4007")
      (footprint "eagle-import:DO-214AC")
      (libsource (lib "eagle-import") (part "DIODE-GEN-PURPOSE-1KV-1A(DO-214AC)"))
    )
    (comp (ref "FID101")
      (value "FIDUCIAL")
      (footprint "eagle-import:FIDUCIAL_1MM")
      (libsource (lib "eagle-import") (part "FIDUCIAL"))
    )
    (comp (ref "FID102")
      (value "FIDUCIAL")
      (footprint "eagle-import:FIDUCIAL_1MM")
      (libsource (lib "eagle-import") (part "FIDUCIAL"))
    )
    (comp (ref "FID103")
      (value "FIDUCIAL")
      (footprint "eagle-import:FIDUCIAL_1MM")
      (libsource (lib "eagle-import") (part "FIDUCIAL"))
    )
    (comp (ref "FID104")
      (value "FIDUCIAL")
      (footprint "eagle-import:FIDUCIAL_1MM")
      (libsource (lib "eagle-import") (part "FIDUCIAL"))
    )
    (comp (ref "IC101")
      (value "LM2904")
      (footprint "eagle-import:SO08")
      (libsource (lib "eagle-import") (part "LM358D"))
    )
    (comp (ref "IC102")
      (value "78L06")
      (footprint "eagle-import:SOT89_ROUND")
      (libsource (lib "eagle-import") (part "78LXXSOT89_ROUND"))
    )
    (comp (ref "IC104")
      (value "78L10")
      (footprint "eagle-import:SOT89_ROUND")
      (libsource (lib "eagle-import") (part "78LXXSOT89_ROUND"))
    )
    (comp (ref "IC105")
      (value "4028")
      (footprint "eagle-import:SO16")
      (libsource (lib "eagle-import") (part "4028D"))
    )
    (comp (ref "IC107")
      (value "ULN2004")
      (footprint "eagle-import:SO16")
      (libsource (lib "eagle-import") (part "ULN2004AD"))
    )
    (comp (ref "IC108")
      (value "LM339")
      (footprint "eagle-import:SO14")
      (libsource (lib "eagle-import") (part "LM339D"))
    )
    (comp (ref "IC109")
      (value "317TO202H_NOHOLE")
      (footprint "eagle-import:TO220H_NOHOLE")
      (libsource (lib "eagle-import") (part "317TO202H_NOHOLE"))
    )
    (comp (ref "IC110")
      (value "555")
      (footprint "eagle-import:SO08")
      (libsource (lib "eagle-import") (part "555DNE"))
    )
    (comp (ref "IC111")
      (value "4538")
      (footprint "eagle-import:SO16")
      (libsource (lib "eagle-import") (part "4538D"))
    )
    (comp (ref "JP101")
      (value "JP2EJP2_SMALLPADS")
      (footprint "eagle-import:JP2_SMALLPADS")
      (libsource (lib "eagle-import") (part "JP2EJP2_SMALLPADS"))
    )
    (comp (ref "JP102")
      (value "JP2EJP2_SMALLPADS")
      (footprint "eagle-import:JP2_SMALLPADS")
      (libsource (lib "eagle-import") (part "JP2EJP2_SMALLPADS"))
    )
    (comp (ref "JP103")
      (value "JP2EJP2_SMALLPADS")
      (footprint "eagle-import:JP2_SMALLPADS")
      (libsource (lib "eagle-import") (part "JP2EJP2_SMALLPADS"))
    )
    (comp (ref "JP104")
      (value "JP2EJP2_SMALLPADS")
      (footprint "eagle-import:JP2_SMALLPADS")
      (libsource (lib "eagle-import") (part "JP2EJP2_SMALLPADS"))
    )
    (comp (ref "JP105")
      (value "JP2E_ORIG")
      (footprint "eagle-import:JP2_ORIG_SMALLPADS")
      (libsource (lib "eagle-import") (part "JP2E_ORIG"))
    )
    (comp (ref "LED101")
      (value "LEDLD260")
      (footprint "eagle-import:LD260")
      (libsource (lib "eagle-import") (part "LEDLD260"))
    )
    (comp (ref "LED102")
      (value "LEDLD260")
      (footprint "eagle-import:LD260")
      (libsource (lib "eagle-import") (part "LEDLD260"))
    )
    (comp (ref "LED103")
      (value "LEDLD260")
      (footprint "eagle-import:LD260")
      (libsource (lib "eagle-import") (part "LEDLD260"))
    )
    (comp (ref "LED104")
      (value "LEDLD260")
      (footprint "eagle-import:LD260")
      (libsource (lib "eagle-import") (part "LEDLD260"))
    )
    (comp (ref "LED105")
      (value "LEDLD260")
      (footprint "eagle-import:LD260")
      (libsource (lib "eagle-import") (part "LEDLD260"))
    )
    (comp (ref "LED106")
      (value "LEDLD260")
      (footprint "eagle-import:LD260")
      (libsource (lib "eagle-import") (part "LEDLD260"))
    )
    (comp (ref "Q1")
      (value "J1")
      (footprint "eagle-import:SOT-23")
      (fields (field (name "MPN") "BSS138W-7-F"))
      (libsource (lib "eagle-import") (part "SMD-MOSFET-N-CH-50V-200MA-BSS138W-7-F(SOT-23)"))
    )
    (comp (ref "Q2")
      (value "BA")
      (footprint "eagle-import:SOT89")
      (libsource (lib "eagle-import") (part "PNP-TRANSISTOR_SOT89"))
    )
    (comp (ref "Q3")
      (value "J1")
      (footprint "eagle-import:SOT-23")
      (fields (field (name "MPN") "BSS138W-7-F"))
      (libsource (lib "eagle-import") (part "SMD-MOSFET-N-CH-50V-200MA-BSS138W-7-F(SOT-23)"))
    )
    (comp (ref "Q101")
      (value "BA.")
      (footprint "eagle-import:SOT89")
      (libsource (lib "eagle-import") (part "PNP-TRANSISTOR_SOT89"))
    )
    (comp (ref "Q102")
      (value "BA.")
      (footprint "eagle-import:SOT89")
      (libsource (lib "eagle-import") (part "PNP-TRANSISTOR_SOT89"))
    )
    (comp (ref "Q103")
      (value "MY")
      (footprint "eagle-import:SOT89")
      (libsource (lib "eagle-import") (part "NPN-TRANSISTOR_SOT89"))
    )
    (comp (ref "Q104")
      (value "BA")
      (footprint "eagle-import:SOT89")
      (libsource (lib "eagle-import") (part "PNP-TRANSISTOR_SOT89"))
    )
    (comp (ref "Q105")
      (value "BA")
      (footprint "eagle-import:SOT89")
      (libsource (lib "eagle-import") (part "PNP-TRANSISTOR_SOT89"))
    )
    (comp (ref "Q106")
      (value "J1")
      (footprint "eagle-import:SOT-23")
      (fields (field (name "MPN") "BSS138W-7-F"))
      (libsource (lib "eagle-import") (part "SMD-MOSFET-N-CH-50V-200MA-BSS138W-7-F(SOT-23)"))
    )
    (comp (ref "Q107")
      (value "J1")
      (footprint "eagle-import:SOT-23")
      (fields (field (name "MPN") "BSS138W-7-F"))
      (libsource (lib "eagle-import") (part "SMD-MOSFET-N-CH-50V-200MA-BSS138W-7-F(SOT-23)"))
    )
    (comp (ref "R1")
      (value "104")
      (footprint "eagle-import:R0805")
      (fields (field (name "MPN") "RC0805FR-0710KL"))
      (libsource (lib "eagle-import") (part "SMD-RES-10K-1%-1/8W(0805)"))
    )
    (comp (ref "R2")
      (value "104")
      (footprint "eagle-import:R0805")
      (fields (field (name "MPN") "RC0805FR-0710KL"))
      (libsource (lib "eagle-import") (part "SMD-RES-10K-1%-1/8W(0805)"))
    )
    (comp (ref "R3")
      (value "104")
      (footprint "eagle-import:R0805")
      (fields (field (name "MPN") "RC0805FR-0710KL"))
      (libsource (lib "eagle-import") (part "SMD-RES-10K-1%-1/8W(0805)"))
    )
    (comp (ref "R4")
      (value "100")
      (footprint "eagle-import:R0805")
      (fields (field (name "MPN") "RC0805JR-07220RL"))
      (libsource (lib "eagle-import") (part "SMD-RES-220R-5%-1/8W(0805)"))
    )
    (comp (ref "R5")
      (value "13")
      (footprint "eagle-import:R1206")
      (fields (field (name "MPN") "RC1206JR-0713RL"))
      (libsource (lib "eagle-import") (part "SMD-RES-13R-5%-1/4W(1206)"))
    )
    (comp (ref "R6")
      (value "2201")
      (footprint "eagle-import:R0805")
      (fields (field (name "MPN") "RC0805JR-071KL"))
      (libsource (lib "eagle-import") (part "SMD-RES-1K-5%-1/8W(0805)"))
    )
    (comp (ref "R8")
      (value "4701")
      (footprint "eagle-import:R0805")
      (fields (field (name "MPN") "RC0805JR-074K7L"))
      (libsource (lib "eagle-import") (part "SMD-RES-4.7K-5%-1/8W(0805)"))
    )
    (comp (ref "R9")
      (value "13")
      (footprint "eagle-import:R1206")
      (fields (field (name "MPN") "RC1206JR-0713RL"))
      (libsource (lib "eagle-import") (part "SMD-RES-13R-5%-1/4W(1206)"))
    )
    (comp (ref "R10")
      (value "104")
      (footprint "eagle-import:R0805")
      (fields (field (name "MPN") "RC0805JR-074K7L"))
      (libsource (lib "eagle-import") (part "SMD-RES-4.7K-5%-1/8W(0805)"))
    )
    (comp (ref "R12")
      (value "100")
      (footprint "eagle-import:R0805")
      (fields (field (name "MPN") "RC0805JR-072K2L"))
      (libsource (lib "eagle-import") (part "SMD-RES-2.2K-5%-1/8W(0805)"))
    )
    (comp (ref "R13")
      (value "100")
      (footprint "eagle-import:R0805")
      (fields (field (name "MPN") "RC0805JR-072K2L"))
      (libsource (lib "eagle-import") (part "SMD-RES-2.2K-5%-1/8W(0805)"))
    )
    (comp (ref "R101")
      (value "102")
      (footprint "eagle-import:R0805")
      (fields (field (name "MPN") "RC0805JR-071KL"))
      (libsource (lib "eagle-import") (part "SMD-RES-1K-5%-1/8W(0805)"))
    )
    (comp (ref "R102")
      (value "13")
      (footprint "eagle-import:R1206")
      (fields (field (name "MPN") "RC1206JR-0713RL"))
      (libsource (lib "eagle-import") (part "SMD-RES-13R-5%-1/4W(1206)"))
    )
    (comp (ref "R103")
      (value "R_user")
      (footprint "eagle-import:R0805")
      (libsource (lib "eagle-import") (part "R-EU_R0805"))
    )
    (comp (ref "R104")
      (value "R_user")
      (footprint "eagle-import:R0805")
      (libsource (lib "eagle-import") (part "R-EU_R0805"))
    )
    (comp (ref "R105")
      (value "4701")
      (footprint "eagle-import:R0805")
      (fields (field (name "MPN") "RC0805JR-074K7L"))
      (libsource (lib "eagle-import") (part "SMD-RES-4.7K-5%-1/8W(0805)"))
    )
    (comp (ref "R106")
      (value "13")
      (footprint "eagle-import:R1206")
      (fields (field (name "MPN") "RC1206JR-0713RL"))
      (libsource (lib "eagle-import") (part "SMD-RES-13R-5%-1/4W(1206)"))
    )
    (comp (ref "R107")
      (value "1002")
      (footprint "eagle-import:R0805")
      (fields (field (name "MPN") "RC0805FR-0710KL"))
      (libsource (lib "eagle-import") (part "SMD-RES-10K-1%-1/8W(0805)"))
    )
    (comp (ref "R108")
      (value "1002")
      (footprint "eagle-import:R0805")
      (fields (field (name "MPN") "RC0805FR-0710KL"))
      (libsource (lib "eagle-import") (part "SMD-RES-10K-1%-1/8W(0805)"))
    )
    (comp (ref "R109")
      (value "104")
      (footprint "eagle-import:R0805")
      (fields (field (name "MPN") "RC0805FR-0710KL"))
      (libsource (lib "eagle-import") (part "SMD-RES-10K-1%-1/8W(0805)"))
    )
    (comp (ref "R110")
      (value "104")
      (footprint "eagle-import:R0805")
      (fields (field (name "MPN") "RC0805FR-0710KL"))
      (libsource (lib "eagle-import") (part "SMD-RES-10K-1%-1/8W(0805)"))
    )
    (comp (ref "R111")
      (value "104")
      (footprint "eagle-import:R0805")
      (fields (field (name "MPN") "RC0805FR-0710KL"))
      (libsource (lib "eagle-import") (part "SMD-RES-10K-1%-1/8W(0805)"))
    )
    (comp (ref "R112")
      (value "102")
      (footprint "eagle-import:R0805")
      (fields (field (name "MPN") "RC0805JR-071KL"))
      (libsource (lib "eagle-import") (part "SMD-RES-1K-5%-1/8W(0805)"))
    )
    (comp (ref "R113")
      (value "1002")
      (footprint "eagle-import:R0805")
      (fields (field (name "MPN") "RC0805JR-071KL"))
      (libsource (lib "eagle-import") (part "SMD-RES-1K-5%-1/8W(0805)"))
    )
    (comp (ref "R114")
      (value "1002")
      (footprint "eagle-import:R0805")
      (fields (field (name "MPN") "RC0805JR-071KL"))
      (libsource (lib "eagle-import") (part "SMD-RES-1K-5%-1/8W(0805)"))
    )
    (comp (ref "R115")
      (value "102")
      (footprint "eagle-import:R0805")
      (fields (field (name "MPN") "RC0805JR-07220RL"))
      (libsource (lib "eagle-import") (part "SMD-RES-220R-5%-1/8W(0805)"))
    )
    (comp (ref "R116")
      (value "4701")
      (footprint "eagle-import:R0805")
      (fields (field (name "MPN") "RC0805JR-074K7L"))
      (libsource (lib "eagle-import") (part "SMD-RES-4.7K-5%-1/8W(0805)"))
    )
    (comp (ref "R117")
      (value "2702")
      (footprint "eagle-import:R0805")
      (fields (field (name "MPN") "RC0805JR-074K7L"))
      (libsource (lib "eagle-import") (part "SMD-RES-4.7K-5%-1/8W(0805)"))
    )
    (comp (ref "R119")
      (value "2201")
      (footprint "eagle-import:R0805")
      (fields (field (name "MPN") "RC0805JR-072K2L"))
      (libsource (lib "eagle-import") (part "SMD-RES-2.2K-5%-1/8W(0805)"))
    )
    (comp (ref "R120")
      (value "1002")
      (footprint "eagle-import:R0805")
      (fields (field (name "MPN") "RC0805FR-0710KL"))
      (libsource (lib "eagle-import") (part "SMD-RES-10K-1%-1/8W(0805)"))
    )
    (comp (ref "R121")
      (value "1502")
      (footprint "eagle-import:R0805")
      (fields (field (name "MPN") "RC0805FR-0710KL"))
      (libsource (lib "eagle-import") (part "SMD-RES-10K-1%-1/8W(0805)"))
    )
    (comp (ref "R122")
      (value "2702")
      (footprint "eagle-import:R0805")
      (fields (field (name "MPN") "RC0805JR-074K7L"))
      (libsource (lib "eagle-import") (part "SMD-RES-4.7K-5%-1/8W(0805)"))
    )
    (comp (ref "R123")
      (value "2702")
      (footprint "eagle-import:R0805")
      (fields (field (name "MPN") "RC0805JR-074K7L"))
      (libsource (lib "eagle-import") (part "SMD-RES-4.7K-5%-1/8W(0805)"))
    )
    (comp (ref "R124")
      (value "1002")
      (footprint "eagle-import:R0805")
      (fields (field (name "MPN") "RC0805FR-0710KL"))
      (libsource (lib "eagle-import") (part "SMD-RES-10K-1%-1/8W(0805)"))
    )
    (comp (ref "R125")
      (value "104")
      (footprint "eagle-import:R0805")
      (fields (field (name "MPN") "RC0805FR-0710KL"))
      (libsource (lib "eagle-import") (part "SMD-RES-10K-1%-1/8W(0805)"))
    )
    (comp (ref "R126")
      (value "4701")
      (footprint "eagle-import:R0805")
      (fields (field (name "MPN") "RC0805JR-074K7L"))
      (libsource (lib "eagle-import") (part "SMD-RES-4.7K-5%-1/8W(0805)"))
    )
    (comp (ref "R127")
      (value "47")
      (footprint "eagle-import:V235_17_1MM")
      (libsource (lib "eagle-import") (part "R-EU_V235/17_1MM"))
    )
    (comp (ref "R128")
      (value "102")
      (footprint "eagle-import:R0805")
      (fields (field (name "MPN") "RC0805JR-071KL"))
      (libsource (lib "eagle-import") (part "SMD-RES-1K-5%-1/8W(0805)"))
    )
    (comp (ref "R129")
      (value "47")
      (footprint "eagle-import:V235_17_1MM")
      (libsource (lib "eagle-import") (part "R-EU_V235/17_1MM"))
    )
    (comp (ref "R130")
      (value "104")
      (footprint "eagle-import:R0805")
      (fields (field (name "MPN") "RC0805FR-0710KL"))
      (libsource (lib "eagle-import") (part "SMD-RES-10K-1%-1/8W(0805)"))
    )
    (comp (ref "R131")
      (value "1502")
      (footprint "eagle-import:R0805")
      (fields (field (name "MPN") "RC0805FR-0710KL"))
      (libsource (lib "eagle-import") (part "SMD-RES-10K-1%-1/8W(0805)"))
    )
    (comp (ref "R132")
      (value "1002")
      (footprint "eagle-import:R0805")
      (fields (field (name "MPN") "RC0805FR-0710KL"))
      (libsource (lib "eagle-import") (part "SMD-RES-10K-1%-1/8W(0805)"))
    )
    (comp (ref "R133")
      (value "2201")
      (footprint "eagle-import:R0805")
      (fields (field (name "MPN") "RC0805JR-072K2L"))
      (libsource (lib "eagle-import") (part "SMD-RES-2.2K-5%-1/8W(0805)"))
    )
    (comp (ref "R134")
      (value "13")
      (footprint "eagle-import:R1206")
      (fields (field (name "MPN") "RC1206JR-0713RL"))
      (libsource (lib "eagle-import") (part "SMD-RES-13R-5%-1/4W(1206)"))
    )
    (comp (ref "R135")
      (value "104")
      (footprint "eagle-import:R0805")
      (fields (field (name "MPN") "RC0805FR-0710KL"))
      (libsource (lib "eagle-import") (part "SMD-RES-10K-1%-1/8W(0805)"))
    )
    (comp (ref "R136")
      (value "47")
      (footprint "eagle-import:V235_17_1MM")
      (libsource (lib "eagle-import") (part "R-EU_V235/17_1MM"))
    )
    (comp (ref "R137")
      (value "47")
      (footprint "eagle-import:V235_17_1MM")
      (libsource (lib "eagle-import") (part "R-EU_V235/17_1MM"))
    )
    (comp (ref "R138")
      (value "100")
      (footprint "eagle-import:R0805")
      (fields (field (name "MPN") "RC0805JR-072K2L"))
      (libsource (lib "eagle-import") (part "SMD-RES-2.2K-5%-1/8W(0805)"))
    )
    (comp (ref "R140")
      (value "2702")
      (footprint "eagle-import:R0805")
      (fields (field (name "MPN") "RC0805FR-0710KL"))
      (libsource (lib "eagle-import") (part "SMD-RES-10K-1%-1/8W(0805)"))
    )
    (comp (ref "R141")
      (value "104")
      (footprint "eagle-import:R0805")
      (fields (field (name "MPN") "RC0805FR-0710KL"))
      (libsource (lib "eagle-import") (part "SMD-RES-10K-1%-1/8W(0805)"))
    )
    (comp (ref "R142")
      (value "(1000)")
      (footprint "eagle-import:R0805")
      (fields (field (name "MPN") "RC0805JR-07100RL"))
      (libsource (lib "eagle-import") (part "SMD-RES-100R-5%-1/8W(0805)"))
    )
    (comp (ref "R143")
      (value "(101)")
      (footprint "eagle-import:R0805")
      (fields (field (name "MPN") "RC0805JR-07100RL"))
      (libsource (lib "eagle-import") (part "SMD-RES-100R-5%-1/8W(0805)"))
    )
    (comp (ref "R144")
      (value "(1002)")
      (footprint "eagle-import:R0805")
      (fields (field (name "MPN") "RC0805FR-0710KL"))
      (libsource (lib "eagle-import") (part "SMD-RES-10K-1%-1/8W(0805)"))
    )
    (comp (ref "R145")
      (value "2702")
      (footprint "eagle-import:R0805")
      (fields (field (name "MPN") "RC0805JR-074K7L"))
      (libsource (lib "eagle-import") (part "SMD-RES-4.7K-5%-1/8W(0805)"))
    )
    (comp (ref "R146")
      (value "1002")
      (footprint "eagle-import:R0805")
      (fields (field (name "MPN") "RC0805JR-074K7L"))
      (libsource (lib "eagle-import") (part "SMD-RES-4.7K-5%-1/8W(0805)"))
    )
    (comp (ref "SJ101")
      (value "SJ")
      (footprint "eagle-import:SJ")
      (libsource (lib "eagle-import") (part "solder-jumper_SJ"))
    )
    (comp (ref "SJMP")
      (value "SJ")
      (footprint "eagle-import:SJ")
      (libsource (lib "eagle-import") (part "SJ"))
    )
    (comp (ref "START")
      (value "TPSB2.0")
      (footprint "eagle-import:B2.0")
      (libsource (lib "eagle-import") (part "TPSB2.0"))
    )
    (comp (ref "TP1")
      (value "TPSB2.0")
      (footprint "eagle-import:B2.0")
      (libsource (lib "eagle-import") (part "TPSB2.0"))
    )
    (comp (ref "TP2")
      (value "TPSB2.0")
      (footprint "eagle-import:B2.0")
      (libsource (lib "eagle-import") (part "TPSB2.0"))
    )
    (comp (ref "TP3")
      (value "TPSB2.0")
      (footprint "eagle-import:B2.0")
      (libsource (lib "eagle-import") (part "TPSB2.0"))
    )
    (comp (ref "TP4")
      (value "TPSB2.0")
      (footprint "eagle-import:B2.0")
      (libsource (lib "eagle-import") (part "TPSB2.0"))
    )
    (comp (ref "TP5")
      (value "TPSB2.0")
      (footprint "eagle-import:B2.0")
      (libsource (lib "eagle-import") (part "TPSB2.0"))
    )
    (comp (ref "TP6")
      (value "TPSB2.0")
      (footprint "eagle-import:B2.0")
      (libsource (lib "eagle-import") (part "TPSB2.0"))
    )
    (comp (ref "TP7")
      (value "TPSB2.0")
      (footprint "eagle-import:B2.0")
      (libsource (lib "eagle-import") (part "TPSB2.0"))
    )
    (comp (ref "TP8")
      (value "TPSB2.0")
      (footprint "eagle-import:B2.0")
      (libsource (lib "eagle-import") (part "TPSB2.0"))
    )
    (comp (ref "TP9")
      (value "TPSB2.0")
      (footprint "eagle-import:B2.0")
      (libsource (lib "eagle-import") (part "TPSB2.0"))
    )
    (comp (ref "TP10")
      (value "TPSB2.0")
      (footprint "eagle-import:B2.0")
      (libsource (lib "eagle-import") (part "TPSB2.0"))
    )
    (comp (ref "TP11")
      (value "TPSB2.0")
      (footprint "eagle-import:B2.0")
      (libsource (lib "eagle-import") (part "TPSB2.0"))
    )
    (comp (ref "TP12")
      (value "TPSB2.0")
      (footprint "eagle-import:B2.0")
      (libsource (lib "eagle-import") (part "TPSB2.0"))
    )
    (comp (ref "TP13")
      (value "TPSB2.0")
      (footprint "eagle-import:B2.0")
      (libsource (lib "eagle-import") (part "TPSB2.0"))
    )
    (comp (ref "TP16")
      (value "TPSB2.0")
      (footprint "eagle-import:B2.0")
      (libsource (lib "eagle-import") (part "TPSB2.0"))
    )
    (comp (ref "TP17")
      (value "TPSB2.0")
      (footprint "eagle-import:B2.0")
      (libsource (lib "eagle-import") (part "TPSB2.0"))
    )
    (comp (ref "TP18")
      (value "TPSB2.0")
      (footprint "eagle-import:B2.0")
      (libsource (lib "eagle-import") (part "TPSB2.0"))
    )
    (comp (ref "TP19")
      (value "TPSB2.0")
      (footprint "eagle-import:B2.0")
      (libsource (lib "eagle-import") (part "TPSB2.0"))
    )
    (comp (ref "TP21")
      (value "TPSB2.0")
      (footprint "eagle-import:B2.0")
      (libsource (lib "eagle-import") (part "TPSB2.0"))
    )
    (comp (ref "TP22")
      (value "TPSB2.0")
      (footprint "eagle-import:B2.0")
      (libsource (lib "eagle-import") (part "TPSB2.0"))
    )
    (comp (ref "TP23")
      (value "TPSB2.0")
      (footprint "eagle-import:B2.0")
      (libsource (lib "eagle-import") (part "TPSB2.0"))
    )
    (comp (ref "TP24")
      (value "TPSB1,27")
      (footprint "eagle-import:B1,27")
      (libsource (lib "eagle-import") (part "TPSB1,27"))
    )
    (comp (ref "TP25")
      (value "TPSB2.0")
      (footprint "eagle-import:B2.0")
      (libsource (lib "eagle-import") (part "TPSB2.0"))
    )
    (comp (ref "TP26")
      (value "TPSB2.0")
      (footprint "eagle-import:B2.0")
      (libsource (lib "eagle-import") (part "TPSB2.0"))
    )
    (comp (ref "X101")
      (value "CON_BMWV2")
      (footprint "eagle-import:24-PIN_V2")
      (libsource (lib "eagle-import") (part "CON_BMWV2"))
    )
    (comp (ref "X102")
      (value "22-23-2021")
      (footprint "eagle-import:22-23-2021")
      (fields (field (name "MF") "MOLEX"))
      (libsource (lib "eagle-import") (part "22-23-2021"))
    )
    (comp (ref "X103")
      (value "22-23-2051")
      (footprint "eagle-import:22-23-2051")
      (fields (field (name "MF") "MOLEX"))
      (libsource (lib "eagle-import") (part "22-23-2051"))
    )
    (comp (ref "FID1")
      (value "FIDUCIAL")
      (footprint "eagle-import:FIDUCIAL_1MM")
      (libsource (lib "eagle-import") (part "FIDUCIAL"))
    )
    (comp (ref "FID1B")
      (value "FIDUCIALFIDUCIAL_1MM_WITH_SOLDERMASK")
      (footprint "eagle-import:FIDUCIAL_1MM_WITH_SOLDERMASK")
      (libsource (lib "eagle-import") (part "FIDUCIALFIDUCIAL_1MM_WITH_SOLDERMASK"))
    )
    (comp (ref "FID2")
      (value "FIDUCIAL")
      (footprint "eagle-import:FIDUCIAL_1MM")
      (libsource (lib "eagle-import") (part "FIDUCIAL"))
    )
    (comp (ref "FID2B")
      (value "FIDUCIALFIDUCIAL_1MM_WITH_SOLDERMASK")
      (footprint "eagle-import:FIDUCIAL_1MM_WITH_SOLDERMASK")
      (libsource (lib "eagle-import") (part "FIDUCIALFIDUCIAL_1MM_WITH_SOLDERMASK"))
    )
    (comp (ref "3")
      (value "2081-1132")
      (footprint "eagle-import:12-PIN")
      (libsource (lib "eagle-import") (part "2081-1132"))
    )
    (comp (ref "4")
      (value "2081-1132")
      (footprint "eagle-import:12-PIN")
      (libsource (lib "eagle-import") (part "2081-1132"))
    )
    (comp (ref "6V1")
      (value "TPSB2.0")
      (footprint "eagle-import:B2.0")
      (libsource (lib "eagle-import") (part "TPSB2.0"))
    )
    (comp (ref "10V1")
      (value "TPSB2.0")
      (footprint "eagle-import:B2.0")
      (libsource (lib "eagle-import") (part "TPSB2.0"))
    )
    (comp (ref "C1")
      (value "100u")
      (footprint "eagle-import:C1206")
      (fields (field (name "MPN") "GRM31CR60J107ME39L"))
      (libsource (lib "eagle-import") (part "CERAMIC-100UF-6.3V-20%-X5R(1206)"))
    )
    (comp (ref "C3")
      (value "100u")
      (footprint "eagle-import:C1206")
      (fields (field (name "MPN") "GRM31CR60J107ME39L"))
      (libsource (lib "eagle-import") (part "CERAMIC-100UF-6.3V-20%-X5R(1206)"))
    )
    (comp (ref "C4")
      (value "100nF,")
      (footprint "eagle-import:C0805")
      (fields (field (name "MPN") "CC0805KRX7R9BB104"))
      (libsource (lib "eagle-import") (part "CERAMIC-100NF-50V-10%-X7R(0805)"))
    )
    (comp (ref "C5")
      (value "4.7u")
      (footprint "eagle-import:C0805")
      (fields (field (name "MPN") "CC0805KKX5R8BB475"))
      (libsource (lib "eagle-import") (part "CERAMIC-4.7UF-25V-10%-X5R(0805)"))
    )
    (comp (ref "C6")
      (value "100nF.")
      (footprint "eagle-import:C0805")
      (fields (field (name "MPN") "CC0805KRX7R9BB104"))
      (libsource (lib "eagle-import") (part "CERAMIC-100NF-50V-10%-X7R(0805)"))
    )
    (comp (ref "C7")
      (value "100nF.")
      (footprint "eagle-import:C0805")
      (fields (field (name "MPN") "CC0805KRX7R9BB104"))
      (libsource (lib "eagle-import") (part "CERAMIC-100NF-50V-10%-X7R(0805)"))
    )
    (comp (ref "C8")
      (value "2.2nF")
      (footprint "eagle-import:C0805")
      (fields (field (name "MPN") "CC0805KRX7R9BB104"))
      (libsource (lib "eagle-import") (part "CERAMIC-100NF-50V-10%-X7R(0805)"))
    )
    (comp (ref "C9")
      (value "100nF")
      (footprint "eagle-import:C0805")
      (fields (field (name "MPN") "CC0805KRX7R9BB104"))
      (libsource (lib "eagle-import") (part "CERAMIC-100NF-50V-10%-X7R(0805)"))
    )
    (comp (ref "C10")
      (value "100nF")
      (footprint "eagle-import:C0805")
      (fields (field (name "MPN") "CC0805KRX7R9BB104"))
      (libsource (lib "eagle-import") (part "CERAMIC-100NF-50V-10%-X7R(0805)"))
    )
    (comp (ref "C11")
      (value "100nF,")
      (footprint "eagle-import:C0805")
      (fields (field (name "MPN") "CC0805KRX7R9BB104"))
      (libsource (lib "eagle-import") (part "CERAMIC-100NF-50V-10%-X7R(0805)"))
    )
    (comp (ref "C12")
      (value "4.7u")
      (footprint "eagle-import:C0805")
      (fields (field (name "MPN") "CC0805KKX5R8BB475"))
      (libsource (lib "eagle-import") (part "CERAMIC-4.7UF-25V-10%-X5R(0805)"))
    )
    (comp (ref "C13")
      (value "10u")
      (footprint "eagle-import:C1206")
      (fields (field (name "MPN") "GRM31CR60J107ME39L"))
      (libsource (lib "eagle-import") (part "CERAMIC-100UF-6.3V-20%-X5R(1206)"))
    )
    (comp (ref "D3")
      (value "1N4007,")
      (footprint "eagle-import:DO-214AC")
      (fields (field (name "MPN") "1N4007"))
      (libsource (lib "eagle-import") (part "DIODE-GEN-PURPOSE-1KV-1A(DO-214AC)"))
    )
    (comp (ref "D5")
      (value "1N4007,")
      (footprint "eagle-import:DO-214AC")
      (fields (field (name "MPN") "1N4007"))
      (libsource (lib "eagle-import") (part "DIODE-GEN-PURPOSE-1KV-1A(DO-214AC)"))
    )
    (comp (ref "D6")
      (value "1N4007.")
      (footprint "eagle-import:DO-214AC")
      (fields (field (name "MPN") "1N4007"))
      (libsource (lib "eagle-import") (part "DIODE-GEN-PURPOSE-1KV-1A(DO-214AC)"))
    )
    (comp (ref "D7")
      (value "1N5817")
      (footprint "eagle-import:DO-214AC_SLIM")
      (libsource (lib "eagle-import") (part "DIODE-GEN-PURPOSE-1KV-1A(DO-214AC)DO-214AC/1206"))
    )
    (comp (ref "D8")
      (value "1N5817.")
      (footprint "eagle-import:DO-214AC_SLIM")
      (libsource (lib "eagle-import") (part "DIODE-GEN-PURPOSE-1KV-1A(DO-214AC)DO-214AC/1206"))
    )
    (comp (ref "D9")
      (value "1N5817.")
      (footprint "eagle-import:DO-214AC_SLIM")
      (libsource (lib "eagle-import") (part "DIODE-GEN-PURPOSE-1KV-1A(DO-214AC)DO-214AC/1206"))
    )
    (comp (ref "D10")
      (value "1N5817")
      (footprint "eagle-import:DO-214AC_SLIM")
      (libsource (lib "eagle-import") (part "DIODE-GEN-PURPOSE-1KV-1A(DO-214AC)DO-214AC/1206"))
    )
    (comp (ref "D11")
      (value "1N4007.")
      (footprint "eagle-import:DO-214AC")
      (fields (field (name "MPN") "1N4007"))
      (libsource (lib "eagle-import") (part "DIODE-GEN-PURPOSE-1KV-1A(DO-214AC)"))
    )
    (comp (ref "D12")
      (value "1N4007")
      (footprint "eagle-import:DO-214AC")
      (libsource (lib "eagle-import") (part "DIODE-GEN-PURPOSE-1KV-1A(DO-214AC)"))
    )
    (comp (ref "D13")
      (value "Zen15")
      (footprint "eagle-import:DO214AA")
      (libsource (lib "eagle-import") (part "SM6T"))
    )
    (comp (ref "D14")
      (value "SM6TDO214AA_BI")
      (footprint "eagle-import:DO214AA_BI")
      (libsource (lib "eagle-import") (part "SM6TDO214AA_BI"))
    )
    (comp (ref "D15")
      (value "1N5817")
      (footprint "eagle-import:DO-214AC_SLIM")
      (libsource (lib "eagle-import") (part "DIODE-GEN-PURPOSE-1KV-1A(DO-214AC)DO-214AC/1206"))
    )
    (comp (ref "D16")
      (value "1N5817.")
      (footprint "eagle-import:DO-214AC_SLIM")
      (libsource (lib "eagle-import") (part "DIODE-GEN-PURPOSE-1KV-1A(DO-214AC)DO-214AC/1206"))
    )
    (comp (ref "D17")
      (value "Zen11")
      (footprint "eagle-import:SOD-123_MINI-SMA")
      (libsource (lib "eagle-import") (part "CGRM400-G1"))
    )
    (comp (ref "FID3")
      (value "FIDUCIAL")
      (footprint "eagle-import:FIDUCIAL_1MM")
      (libsource (lib "eagle-import") (part "FIDUCIAL"))
    )
    (comp (ref "FID4")
      (value "FIDUCIAL")
      (footprint "eagle-import:FIDUCIAL_1MM")
      (libsource (lib "eagle-import") (part "FIDUCIAL"))
    )
    (comp (ref "FID5")
      (value "FIDUCIAL")
      (footprint "eagle-import:FIDUCIAL_1MM")
      (libsource (lib "eagle-import") (part "FIDUCIAL"))
    )
    (comp (ref "FID6")
      (value "FIDUCIAL")
      (footprint "eagle-import:FIDUCIAL_1MM")
      (libsource (lib "eagle-import") (part "FIDUCIAL"))
    )
    (comp (ref "IC1")
      (value "4028")
      (footprint "eagle-import:SO16")
      (libsource (lib "eagle-import") (part "4028D"))
    )
    (comp (ref "IC2")
      (value "317TO202H_NOHOLE")
      (footprint "eagle-import:TO220H_NOHOLE")
      (libsource (lib "eagle-import") (part "317TO202H_NOHOLE"))
    )
    (comp (ref "IC3")
      (value "ULN2004")
      (footprint "eagle-import:SO16")
      (libsource (lib "eagle-import") (part "ULN2004AD"))
    )
    (comp (ref "IC4")
      (value "LM339")
      (footprint "eagle-import:SO14")
      (libsource (lib "eagle-import") (part "LM339D"))
    )
    (comp (ref "IC5")
      (value "78L06")
      (footprint "eagle-import:SOT89_ROUND")
      (libsource (lib "eagle-import") (part "78LXXSOT89_ROUND"))
    )
    (comp (ref "IC6")
      (value "555")
      (footprint "eagle-import:SO08")
      (libsource (lib "eagle-import") (part "555DNE"))
    )
    (comp (ref "IC7")
      (value "4538")
      (footprint "eagle-import:SO16")
      (libsource (lib "eagle-import") (part "4538D"))
    )
    (comp (ref "IC8")
      (value "78L10")
      (footprint "eagle-import:SOT89_ROUND")
      (libsource (lib "eagle-import") (part "78LXXSOT89_ROUND"))
    )
    (comp (ref "IC9")
      (value "LM2904")
      (footprint "eagle-import:SO08")
      (libsource (lib "eagle-import") (part "LM358D"))
    )
    (comp (ref "JP1")
      (value "JP2EJP2_SMALLPADS")
      (footprint "eagle-import:JP2_SMALLPADS")
      (libsource (lib "eagle-import") (part "JP2EJP2_SMALLPADS"))
    )
    (comp (ref "JP2")
      (value "JP2E_ORIG")
      (footprint "eagle-import:JP2_ORIG_SMALLPADS")
      (libsource (lib "eagle-import") (part "JP2E_ORIG"))
    )
    (comp (ref "JP3")
      (value "JP2EJP2_SMALLPADS")
      (footprint "eagle-import:JP2_SMALLPADS")
      (libsource (lib "eagle-import") (part "JP2EJP2_SMALLPADS"))
    )
    (comp (ref "JP4")
      (value "JP2EJP2_SMALLPADS")
      (footprint "eagle-import:JP2_SMALLPADS")
      (libsource (lib "eagle-import") (part "JP2EJP2_SMALLPADS"))
    )
    (comp (ref "JP5")
      (value "JP2EJP2_SMALLPADS")
      (footprint "eagle-import:JP2_SMALLPADS")
      (libsource (lib "eagle-import") (part "JP2EJP2_SMALLPADS"))
    )
    (comp (ref "LED1")
      (value "LEDLD260")
      (footprint "eagle-import:LD260")
      (libsource (lib "eagle-import") (part "LEDLD260"))
    )
    (comp (ref "LED2")
      (value "LEDLD260")
      (footprint "eagle-import:LD260")
      (libsource (lib "eagle-import") (part "LEDLD260"))
    )
    (comp (ref "LED3")
      (value "LEDLD260")
      (footprint "eagle-import:LD260")
      (libsource (lib "eagle-import") (part "LEDLD260"))
    )
    (comp (ref "LED4")
      (value "LEDLD260")
      (footprint "eagle-import:LD260")
      (libsource (lib "eagle-import") (part "LEDLD260"))
    )
    (comp (ref "LED5")
      (value "LEDLD260")
      (footprint "eagle-import:LD260")
      (libsource (lib "eagle-import") (part "LEDLD260"))
    )
    (comp (ref "LED6")
      (value "LEDLD260")
      (footprint "eagle-import:LD260")
      (libsource (lib "eagle-import") (part "LEDLD260"))
    )
    (comp (ref "Q4")
      (value "BA")
      (footprint "eagle-import:SOT89")
      (libsource (lib "eagle-import") (part "PNP-TRANSISTOR_SOT89"))
    )
    (comp (ref "Q5")
      (value "BA.")
      (footprint "eagle-import:SOT89")
      (libsource (lib "eagle-import") (part "PNP-TRANSISTOR_SOT89"))
    )
    (comp (ref "Q6")
      (value "BA.")
      (footprint "eagle-import:SOT89")
      (libsource (lib "eagle-import") (part "PNP-TRANSISTOR_SOT89"))
    )
    (comp (ref "Q7")
      (value "BA")
      (footprint "eagle-import:SOT89")
      (libsource (lib "eagle-import") (part "PNP-TRANSISTOR_SOT89"))
    )
    (comp (ref "Q8")
      (value "MY")
      (footprint "eagle-import:SOT89")
      (libsource (lib "eagle-import") (part "NPN-TRANSISTOR_SOT89"))
    )
    (comp (ref "Q9")
      (value "J1")
      (footprint "eagle-import:SOT-23")
      (fields (field (name "MPN") "BSS138W-7-F"))
      (libsource (lib "eagle-import") (part "SMD-MOSFET-N-CH-50V-200MA-BSS138W-7-F(SOT-23)"))
    )
    (comp (ref "Q10")
      (value "J1")
      (footprint "eagle-import:SOT-23")
      (fields (field (name "MPN") "BSS138W-7-F"))
      (libsource (lib "eagle-import") (part "SMD-MOSFET-N-CH-50V-200MA-BSS138W-7-F(SOT-23)"))
    )
    (comp (ref "Q11")
      (value "J1")
      (footprint "eagle-import:SOT-23")
      (fields (field (name "MPN") "BSS138W-7-F"))
      (libsource (lib "eagle-import") (part "SMD-MOSFET-N-CH-50V-200MA-BSS138W-7-F(SOT-23)"))
    )
    (comp (ref "Q12")
      (value "BA")
      (footprint "eagle-import:SOT89")
      (libsource (lib "eagle-import") (part "PNP-TRANSISTOR_SOT89"))
    )
    (comp (ref "Q13")
      (value "J1")
      (footprint "eagle-import:SOT-23")
      (fields (field (name "MPN") "BSS138W-7-F"))
      (libsource (lib "eagle-import") (part "SMD-MOSFET-N-CH-50V-200MA-BSS138W-7-F(SOT-23)"))
    )
    (comp (ref "R7")
      (value "47")
      (footprint "eagle-import:V235_17_1MM")
      (libsource (lib "eagle-import") (part "R-EU_V235/17_1MM"))
    )
    (comp (ref "R11")
      (value "13")
      (footprint "eagle-import:R1206")
      (fields (field (name "MPN") "RC1206JR-0713RL"))
      (libsource (lib "eagle-import") (part "SMD-RES-13R-5%-1/4W(1206)"))
    )
    (comp (ref "R14")
      (value "47")
      (footprint "eagle-import:V235_17_1MM")
      (libsource (lib "eagle-import") (part "R-EU_V235/17_1MM"))
    )
    (comp (ref "R15")
      (value "104")
      (footprint "eagle-import:R0805")
      (fields (field (name "MPN") "RC0805FR-0710KL"))
      (libsource (lib "eagle-import") (part "SMD-RES-10K-1%-1/8W(0805)"))
    )
    (comp (ref "R16")
      (value "104")
      (footprint "eagle-import:R0805")
      (fields (field (name "MPN") "RC0805FR-0710KL"))
      (libsource (lib "eagle-import") (part "SMD-RES-10K-1%-1/8W(0805)"))
    )
    (comp (ref "R17")
      (value "104")
      (footprint "eagle-import:R0805")
      (fields (field (name "MPN") "RC0805FR-0710KL"))
      (libsource (lib "eagle-import") (part "SMD-RES-10K-1%-1/8W(0805)"))
    )
    (comp (ref "R18")
      (value "4701")
      (footprint "eagle-import:R0805")
      (fields (field (name "MPN") "RC0805JR-074K7L"))
      (libsource (lib "eagle-import") (part "SMD-RES-4.7K-5%-1/8W(0805)"))
    )
    (comp (ref "R19")
      (value "1002")
      (footprint "eagle-import:R0805")
      (fields (field (name "MPN") "RC0805FR-0710KL"))
      (libsource (lib "eagle-import") (part "SMD-RES-10K-1%-1/8W(0805)"))
    )
    (comp (ref "R20")
      (value "1002")
      (footprint "eagle-import:R0805")
      (fields (field (name "MPN") "RC0805FR-0710KL"))
      (libsource (lib "eagle-import") (part "SMD-RES-10K-1%-1/8W(0805)"))
    )
    (comp (ref "R21")
      (value "1502")
      (footprint "eagle-import:R0805")
      (fields (field (name "MPN") "RC0805FR-0710KL"))
      (libsource (lib "eagle-import") (part "SMD-RES-10K-1%-1/8W(0805)"))
    )
    (comp (ref "R22")
      (value "104")
      (footprint "eagle-import:R0805")
      (fields (field (name "MPN") "RC0805FR-0710KL"))
      (libsource (lib "eagle-import") (part "SMD-RES-10K-1%-1/8W(0805)"))
    )
    (comp (ref "R23")
      (value "104")
      (footprint "eagle-import:R0805")
      (fields (field (name "MPN") "RC0805FR-0710KL"))
      (libsource (lib "eagle-import") (part "SMD-RES-10K-1%-1/8W(0805)"))
    )
    (comp (ref "R24")
      (value "1502")
      (footprint "eagle-import:R0805")
      (fields (field (name "MPN") "RC0805FR-0710KL"))
      (libsource (lib "eagle-import") (part "SMD-RES-10K-1%-1/8W(0805)"))
    )
    (comp (ref "R25")
      (value "1002")
      (footprint "eagle-import:R0805")
      (fields (field (name "MPN") "RC0805FR-0710KL"))
      (libsource (lib "eagle-import") (part "SMD-RES-10K-1%-1/8W(0805)"))
    )
    (comp (ref "R26")
      (value "2201")
      (footprint "eagle-import:R0805")
      (fields (field (name "MPN") "RC0805JR-072K2L"))
      (libsource (lib "eagle-import") (part "SMD-RES-2.2K-5%-1/8W(0805)"))
    )
    (comp (ref "R27")
      (value "1002")
      (footprint "eagle-import:R0805")
      (fields (field (name "MPN") "RC0805FR-0710KL"))
      (libsource (lib "eagle-import") (part "SMD-RES-10K-1%-1/8W(0805)"))
    )
    (comp (ref "R28")
      (value "4701")
      (footprint "eagle-import:R0805")
      (fields (field (name "MPN") "RC0805JR-074K7L"))
      (libsource (lib "eagle-import") (part "SMD-RES-4.7K-5%-1/8W(0805)"))
    )
    (comp (ref "R29")
      (value "2702")
      (footprint "eagle-import:R0805")
      (fields (field (name "MPN") "RC0805JR-074K7L"))
      (libsource (lib "eagle-import") (part "SMD-RES-4.7K-5%-1/8W(0805)"))
    )
    (comp (ref "R30")
      (value "102")
      (footprint "eagle-import:R0805")
      (fields (field (name "MPN") "RC0805JR-071KL"))
      (libsource (lib "eagle-import") (part "SMD-RES-1K-5%-1/8W(0805)"))
    )
    (comp (ref "R31")
      (value "R_user")
      (footprint "eagle-import:R0805")
      (libsource (lib "eagle-import") (part "R-EU_R0805"))
    )
    (comp (ref "R32")
      (value "102")
      (footprint "eagle-import:R0805")
      (fields (field (name "MPN") "RC0805JR-07220RL"))
      (libsource (lib "eagle-import") (part "SMD-RES-220R-5%-1/8W(0805)"))
    )
    (comp (ref "R33")
      (value "(101)")
      (footprint "eagle-import:R0805")
      (fields (field (name "MPN") "RC0805JR-07100RL"))
      (libsource (lib "eagle-import") (part "SMD-RES-100R-5%-1/8W(0805)"))
    )
    (comp (ref "R34")
      (value "(1000)")
      (footprint "eagle-import:R0805")
      (fields (field (name "MPN") "RC0805JR-07100RL"))
      (libsource (lib "eagle-import") (part "SMD-RES-100R-5%-1/8W(0805)"))
    )
    (comp (ref "R35")
      (value "102")
      (footprint "eagle-import:R0805")
      (fields (field (name "MPN") "RC0805JR-071KL"))
      (libsource (lib "eagle-import") (part "SMD-RES-1K-5%-1/8W(0805)"))
    )
    (comp (ref "R36")
      (value "13")
      (footprint "eagle-import:R1206")
      (fields (field (name "MPN") "RC1206JR-0713RL"))
      (libsource (lib "eagle-import") (part "SMD-RES-13R-5%-1/4W(1206)"))
    )
    (comp (ref "R37")
      (value "13")
      (footprint "eagle-import:R1206")
      (fields (field (name "MPN") "RC1206JR-0713RL"))
      (libsource (lib "eagle-import") (part "SMD-RES-13R-5%-1/4W(1206)"))
    )
    (comp (ref "R38")
      (value "2702")
      (footprint "eagle-import:R0805")
      (fields (field (name "MPN") "RC0805JR-074K7L"))
      (libsource (lib "eagle-import") (part "SMD-RES-4.7K-5%-1/8W(0805)"))
    )
    (comp (ref "R39")
      (value "4701")
      (footprint "eagle-import:R0805")
      (fields (field (name "MPN") "RC0805JR-074K7L"))
      (libsource (lib "eagle-import") (part "SMD-RES-4.7K-5%-1/8W(0805)"))
    )
    (comp (ref "R40")
      (value "100")
      (footprint "eagle-import:R0805")
      (fields (field (name "MPN") "RC0805JR-072K2L"))
      (libsource (lib "eagle-import") (part "SMD-RES-2.2K-5%-1/8W(0805)"))
    )
    (comp (ref "R41")
      (value "104")
      (footprint "eagle-import:R0805")
      (fields (field (name "MPN") "RC0805FR-0710KL"))
      (libsource (lib "eagle-import") (part "SMD-RES-10K-1%-1/8W(0805)"))
    )
    (comp (ref "R42")
      (value "104")
      (footprint "eagle-import:R0805")
      (fields (field (name "MPN") "RC0805FR-0710KL"))
      (libsource (lib "eagle-import") (part "SMD-RES-10K-1%-1/8W(0805)"))
    )
    (comp (ref "R43")
      (value "(1002)")
      (footprint "eagle-import:R0805")
      (fields (field (name "MPN") "RC0805FR-0710KL"))
      (libsource (lib "eagle-import") (part "SMD-RES-10K-1%-1/8W(0805)"))
    )
    (comp (ref "R44")
      (value "2702")
      (footprint "eagle-import:R0805")
      (fields (field (name "MPN") "RC0805FR-0710KL"))
      (libsource (lib "eagle-import") (part "SMD-RES-10K-1%-1/8W(0805)"))
    )
    (comp (ref "R45")
      (value "47")
      (footprint "eagle-import:V235_17_1MM")
      (libsource (lib "eagle-import") (part "R-EU_V235/17_1MM"))
    )
    (comp (ref "R46")
      (value "47")
      (footprint "eagle-import:V235_17_1MM")
      (libsource (lib "eagle-import") (part "R-EU_V235/17_1MM"))
    )
    (comp (ref "R47")
      (value "2702")
      (footprint "eagle-import:R0805")
      (fields (field (name "MPN") "RC0805JR-074K7L"))
      (libsource (lib "eagle-import") (part "SMD-RES-4.7K-5%-1/8W(0805)"))
    )
    (comp (ref "R48")
      (value "2201")
      (footprint "eagle-import:R0805")
      (fields (field (name "MPN") "RC0805JR-072K2L"))
      (libsource (lib "eagle-import") (part "SMD-RES-2.2K-5%-1/8W(0805)"))
    )
    (comp (ref "R49")
      (value "1002")
      (footprint "eagle-import:R0805")
      (fields (field (name "MPN") "RC0805JR-074K7L"))
      (libsource (lib "eagle-import") (part "SMD-RES-4.7K-5%-1/8W(0805)"))
    )
    (comp (ref "R50")
      (value "1002")
      (footprint "eagle-import:R0805")
      (fields (field (name "MPN") "RC0805FR-0710KL"))
      (libsource (lib "eagle-import") (part "SMD-RES-10K-1%-1/8W(0805)"))
    )
    (comp (ref "R51")
      (value "102")
      (footprint "eagle-import:R0805")
      (fields (field (name "MPN") "RC0805JR-071KL"))
      (libsource (lib "eagle-import") (part "SMD-RES-1K-5%-1/8W(0805)"))
    )
    (comp (ref "R52")
      (value "2702")
      (footprint "eagle-import:R0805")
      (fields (field (name "MPN") "RC0805JR-074K7L"))
      (libsource (lib "eagle-import") (part "SMD-RES-4.7K-5%-1/8W(0805)"))
    )
    (comp (ref "R53")
      (value "1002")
      (footprint "eagle-import:R0805")
      (fields (field (name "MPN") "RC0805JR-071KL"))
      (libsource (lib "eagle-import") (part "SMD-RES-1K-5%-1/8W(0805)"))
    )
    (comp (ref "R54")
      (value "1002")
      (footprint "eagle-import:R0805")
      (fields (field (name "MPN") "RC0805JR-071KL"))
      (libsource (lib "eagle-import") (part "SMD-RES-1K-5%-1/8W(0805)"))
    )
    (comp (ref "R55")
      (value "R_user")
      (footprint "eagle-import:R0805")
      (libsource (lib "eagle-import") (part "R-EU_R0805"))
    )
    (comp (ref "R56")
      (value "104")
      (footprint "eagle-import:R0805")
      (fields (field (name "MPN") "RC0805FR-0710KL"))
      (libsource (lib "eagle-import") (part "SMD-RES-10K-1%-1/8W(0805)"))
    )
    (comp (ref "R57")
      (value "104")
      (footprint "eagle-import:R0805")
      (fields (field (name "MPN") "RC0805FR-0710KL"))
      (libsource (lib "eagle-import") (part "SMD-RES-10K-1%-1/8W(0805)"))
    )
    (comp (ref "R58")
      (value "104")
      (footprint "eagle-import:R0805")
      (fields (field (name "MPN") "RC0805FR-0710KL"))
      (libsource (lib "eagle-import") (part "SMD-RES-10K-1%-1/8W(0805)"))
    )
    (comp (ref "R59")
      (value "13")
      (footprint "eagle-import:R1206")
      (fields (field (name "MPN") "RC1206JR-0713RL"))
      (libsource (lib "eagle-import") (part "SMD-RES-13R-5%-1/4W(1206)"))
    )
    (comp (ref "R60")
      (value "2201")
      (footprint "eagle-import:R0805")
      (fields (field (name "MPN") "RC0805JR-071KL"))
      (libsource (lib "eagle-import") (part "SMD-RES-1K-5%-1/8W(0805)"))
    )
    (comp (ref "R61")
      (value "100")
      (footprint "eagle-import:R0805")
      (fields (field (name "MPN") "RC0805JR-07220RL"))
      (libsource (lib "eagle-import") (part "SMD-RES-220R-5%-1/8W(0805)"))
    )
    (comp (ref "R62")
      (value "13")
      (footprint "eagle-import:R1206")
      (fields (field (name "MPN") "RC1206JR-0713RL"))
      (libsource (lib "eagle-import") (part "SMD-RES-13R-5%-1/4W(1206)"))
    )
    (comp (ref "R63")
      (value "4701")
      (footprint "eagle-import:R0805")
      (fields (field (name "MPN") "RC0805JR-074K7L"))
      (libsource (lib "eagle-import") (part "SMD-RES-4.7K-5%-1/8W(0805)"))
    )
    (comp (ref "R64")
      (value "104")
      (footprint "eagle-import:R0805")
      (fields (field (name "MPN") "RC0805JR-074K7L"))
      (libsource (lib "eagle-import") (part "SMD-RES-4.7K-5%-1/8W(0805)"))
    )
    (comp (ref "R65")
      (value "100")
      (footprint "eagle-import:R0805")
      (fields (field (name "MPN") "RC0805JR-072K2L"))
      (libsource (lib "eagle-import") (part "SMD-RES-2.2K-5%-1/8W(0805)"))
    )
    (comp (ref "R66")
      (value "100")
      (footprint "eagle-import:R0805")
      (fields (field (name "MPN") "RC0805JR-072K2L"))
      (libsource (lib "eagle-import") (part "SMD-RES-2.2K-5%-1/8W(0805)"))
    )
    (comp (ref "SJ1")
      (value "SJ")
      (footprint "eagle-import:SJ")
      (libsource (lib "eagle-import") (part "solder-jumper_SJ"))
    )
    (comp (ref "SJMP1")
      (value "SJ")
      (footprint "eagle-import:SJ")
      (libsource (lib "eagle-import") (part "SJ"))
    )
    (comp (ref "START1")
      (value "TPSB2.0")
      (footprint "eagle-import:B2.0")
      (libsource (lib "eagle-import") (part "TPSB2.0"))
    )
    (comp (ref "TP14")
      (value "TPSB2.0")
      (footprint "eagle-import:B2.0")
      (libsource (lib "eagle-import") (part "TPSB2.0"))
    )
    (comp (ref "TP15")
      (value "TPSB2.0")
      (footprint "eagle-import:B2.0")
      (libsource (lib "eagle-import") (part "TPSB2.0"))
    )
    (comp (ref "TP20")
      (value "TPSB2.0")
      (footprint "eagle-import:B2.0")
      (libsource (lib "eagle-import") (part "TPSB2.0"))
    )
    (comp (ref "TP27")
      (value "TPSB2.0")
      (footprint "eagle-import:B2.0")
      (libsource (lib "eagle-import") (part "TPSB2.0"))
    )
    (comp (ref "TP28")
      (value "TPSB2.0")
      (footprint "eagle-import:B2.0")
      (libsource (lib "eagle-import") (part "TPSB2.0"))
    )
    (comp (ref "TP29")
      (value "TPSB2.0")
      (footprint "eagle-import:B2.0")
      (libsource (lib "eagle-import") (part "TPSB2.0"))
    )
    (comp (ref "TP30")
      (value "TPSB2.0")
      (footprint "eagle-import:B2.0")
      (libsource (lib "eagle-import") (part "TPSB2.0"))
    )
    (comp (ref "TP31")
      (value "TPSB2.0")
      (footprint "eagle-import:B2.0")
      (libsource (lib "eagle-import") (part "TPSB2.0"))
    )
    (comp (ref "TP32")
      (value "TPSB2.0")
      (footprint "eagle-import:B2.0")
      (libsource (lib "eagle-import") (part "TPSB2.0"))
    )
    (comp (ref "TP33")
      (value "TPSB2.0")
      (footprint "eagle-import:B2.0")
      (libsource (lib "eagle-import") (part "TPSB2.0"))
    )
    (comp (ref "TP34")
      (value "TPSB2.0")
      (footprint "eagle-import:B2.0")
      (libsource (lib "eagle-import") (part "TPSB2.0"))
    )
    (comp (ref "TP35")
      (value "TPSB2.0")
      (footprint "eagle-import:B2.0")
      (libsource (lib "eagle-import") (part "TPSB2.0"))
    )
    (comp (ref "TP36")
      (value "TPSB2.0")
      (footprint "eagle-import:B2.0")
      (libsource (lib "eagle-import") (part "TPSB2.0"))
    )
    (comp (ref "TP37")
      (value "TPSB2.0")
      (footprint "eagle-import:B2.0")
      (libsource (lib "eagle-import") (part "TPSB2.0"))
    )
    (comp (ref "TP38")
      (value "TPSB2.0")
      (footprint "eagle-import:B2.0")
      (libsource (lib "eagle-import") (part "TPSB2.0"))
    )
    (comp (ref "TP39")
      (value "TPSB2.0")
      (footprint "eagle-import:B2.0")
      (libsource (lib "eagle-import") (part "TPSB2.0"))
    )
    (comp (ref "TP40")
      (value "TPSB2.0")
      (footprint "eagle-import:B2.0")
      (libsource (lib "eagle-import") (part "TPSB2.0"))
    )
    (comp (ref "TP41")
      (value "TPSB2.0")
      (footprint "eagle-import:B2.0")
      (libsource (lib "eagle-import") (part "TPSB2.0"))
    )
    (comp (ref "TP42")
      (value "TPSB1,27")
      (footprint "eagle-import:B1,27")
      (libsource (lib "eagle-import") (part "TPSB1,27"))
    )
    (comp (ref "TP43")
      (value "TPSB2.0")
      (footprint "eagle-import:B2.0")
      (libsource (lib "eagle-import") (part "TPSB2.0"))
    )
    (comp (ref "TP44")
      (value "TPSB2.0")
      (footprint "eagle-import:B2.0")
      (libsource (lib "eagle-import") (part "TPSB2.0"))
    )
    (comp (ref "TP45")
      (value "TPSB2.0")
      (footprint "eagle-import:B2.0")
      (libsource (lib "eagle-import") (part "TPSB2.0"))
    )
    (comp (ref "TP46")
      (value "TPSB2.0")
      (footprint "eagle-import:B2.0")
      (libsource (lib "eagle-import") (part "TPSB2.0"))
    )
    (comp (ref "X1")
      (value "CON_BMWV2")
      (footprint "eagle-import:24-PIN_V2")
      (libsource (lib "eagle-import") (part "CON_BMWV2"))
    )
    (comp (ref "X2")
      (value "22-23-2051")
      (footprint "eagle-import:22-23-2051")
      (fields (field (name "MF") "MOLEX"))
      (libsource (lib "eagle-import") (part "22-23-2051"))
    )
    (comp (ref "X3")
      (value "22-23-2021")
      (footprint "eagle-import:22-23-2021")
      (fields (field (name "MF") "MOLEX"))
      (libsource (lib "eagle-import") (part "22-23-2021"))
    )
    (comp (ref "5")
      (value "2081-1132")
      (footprint "eagle-import:12-PIN")
      (libsource (lib "eagle-import") (part "2081-1132"))
    )
    (comp (ref "6")
      (value "2081-1132")
      (footprint "eagle-import:12-PIN")
      (libsource (lib "eagle-import") (part "2081-1132"))
    )
    (comp (ref "6V2")
      (value "TPSB2.0")
      (footprint "eagle-import:B2.0")
      (libsource (lib "eagle-import") (part "TPSB2.0"))
    )
    (comp (ref "10V2")
      (value "TPSB2.0")
      (footprint "eagle-import:B2.0")
      (libsource (lib "eagle-import") (part "TPSB2.0"))
    )
    (comp (ref "C14")
      (value "100u")
      (footprint "eagle-import:C1206")
      (fields (field (name "MPN") "GRM31CR60J107ME39L"))
      (libsource (lib "eagle-import") (part "CERAMIC-100UF-6.3V-20%-X5R(1206)"))
    )
    (comp (ref "C16")
      (value "100u")
      (footprint "eagle-import:C1206")
      (fields (field (name "MPN") "GRM31CR60J107ME39L"))
      (libsource (lib "eagle-import") (part "CERAMIC-100UF-6.3V-20%-X5R(1206)"))
    )
    (comp (ref "C17")
      (value "100nF,")
      (footprint "eagle-import:C0805")
      (fields (field (name "MPN") "CC0805KRX7R9BB104"))
      (libsource (lib "eagle-import") (part "CERAMIC-100NF-50V-10%-X7R(0805)"))
    )
    (comp (ref "C18")
      (value "4.7u")
      (footprint "eagle-import:C0805")
      (fields (field (name "MPN") "CC0805KKX5R8BB475"))
      (libsource (lib "eagle-import") (part "CERAMIC-4.7UF-25V-10%-X5R(0805)"))
    )
    (comp (ref "C19")
      (value "100nF.")
      (footprint "eagle-import:C0805")
      (fields (field (name "MPN") "CC0805KRX7R9BB104"))
      (libsource (lib "eagle-import") (part "CERAMIC-100NF-50V-10%-X7R(0805)"))
    )
    (comp (ref "C20")
      (value "100nF.")
      (footprint "eagle-import:C0805")
      (fields (field (name "MPN") "CC0805KRX7R9BB104"))
      (libsource (lib "eagle-import") (part "CERAMIC-100NF-50V-10%-X7R(0805)"))
    )
    (comp (ref "C21")
      (value "2.2nF")
      (footprint "eagle-import:C0805")
      (fields (field (name "MPN") "CC0805KRX7R9BB104"))
      (libsource (lib "eagle-import") (part "CERAMIC-100NF-50V-10%-X7R(0805)"))
    )
    (comp (ref "C22")
      (value "100nF")
      (footprint "eagle-import:C0805")
      (fields (field (name "MPN") "CC0805KRX7R9BB104"))
      (libsource (lib "eagle-import") (part "CERAMIC-100NF-50V-10%-X7R(0805)"))
    )
    (comp (ref "C23")
      (value "100nF")
      (footprint "eagle-import:C0805")
      (fields (field (name "MPN") "CC0805KRX7R9BB104"))
      (libsource (lib "eagle-import") (part "CERAMIC-100NF-50V-10%-X7R(0805)"))
    )
    (comp (ref "C24")
      (value "100nF,")
      (footprint "eagle-import:C0805")
      (fields (field (name "MPN") "CC0805KRX7R9BB104"))
      (libsource (lib "eagle-import") (part "CERAMIC-100NF-50V-10%-X7R(0805)"))
    )
    (comp (ref "C25")
      (value "4.7u")
      (footprint "eagle-import:C0805")
      (fields (field (name "MPN") "CC0805KKX5R8BB475"))
      (libsource (lib "eagle-import") (part "CERAMIC-4.7UF-25V-10%-X5R(0805)"))
    )
    (comp (ref "C26")
      (value "10u")
      (footprint "eagle-import:C1206")
      (fields (field (name "MPN") "GRM31CR60J107ME39L"))
      (libsource (lib "eagle-import") (part "CERAMIC-100UF-6.3V-20%-X5R(1206)"))
    )
    (comp (ref "D18")
      (value "1N4007,")
      (footprint "eagle-import:DO-214AC")
      (fields (field (name "MPN") "1N4007"))
      (libsource (lib "eagle-import") (part "DIODE-GEN-PURPOSE-1KV-1A(DO-214AC)"))
    )
    (comp (ref "D19")
      (value "1N4007,")
      (footprint "eagle-import:DO-214AC")
      (fields (field (name "MPN") "1N4007"))
      (libsource (lib "eagle-import") (part "DIODE-GEN-PURPOSE-1KV-1A(DO-214AC)"))
    )
    (comp (ref "D20")
      (value "1N4007.")
      (footprint "eagle-import:DO-214AC")
      (fields (field (name "MPN") "1N4007"))
      (libsource (lib "eagle-import") (part "DIODE-GEN-PURPOSE-1KV-1A(DO-214AC)"))
    )
    (comp (ref "D21")
      (value "1N5817")
      (footprint "eagle-import:DO-214AC_SLIM")
      (libsource (lib "eagle-import") (part "DIODE-GEN-PURPOSE-1KV-1A(DO-214AC)DO-214AC/1206"))
    )
    (comp (ref "D22")
      (value "1N5817.")
      (footprint "eagle-import:DO-214AC_SLIM")
      (libsource (lib "eagle-import") (part "DIODE-GEN-PURPOSE-1KV-1A(DO-214AC)DO-214AC/1206"))
    )
    (comp (ref "D23")
      (value "1N5817.")
      (footprint "eagle-import:DO-214AC_SLIM")
      (libsource (lib "eagle-import") (part "DIODE-GEN-PURPOSE-1KV-1A(DO-214AC)DO-214AC/1206"))
    )
    (comp (ref "D24")
      (value "1N5817")
      (footprint "eagle-import:DO-214AC_SLIM")
      (libsource (lib "eagle-import") (part "DIODE-GEN-PURPOSE-1KV-1A(DO-214AC)DO-214AC/1206"))
    )
    (comp (ref "D25")
      (value "1N4007.")
      (footprint "eagle-import:DO-214AC")
      (fields (field (name "MPN") "1N4007"))
      (libsource (lib "eagle-import") (part "DIODE-GEN-PURPOSE-1KV-1A(DO-214AC)"))
    )
    (comp (ref "D26")
      (value "1N4007")
      (footprint "eagle-import:DO-214AC")
      (libsource (lib "eagle-import") (part "DIODE-GEN-PURPOSE-1KV-1A(DO-214AC)"))
    )
    (comp (ref "D27")
      (value "Zen15")
      (footprint "eagle-import:DO214AA")
      (libsource (lib "eagle-import") (part "SM6T"))
    )
    (comp (ref "D28")
      (value "SM6TDO214AA_BI")
      (footprint "eagle-import:DO214AA_BI")
      (libsource (lib "eagle-import") (part "SM6TDO214AA_BI"))
    )
    (comp (ref "D29")
      (value "1N5817")
      (footprint "eagle-import:DO-214AC_SLIM")
      (libsource (lib "eagle-import") (part "DIODE-GEN-PURPOSE-1KV-1A(DO-214AC)DO-214AC/1206"))
    )
    (comp (ref "D30")
      (value "1N5817.")
      (footprint "eagle-import:DO-214AC_SLIM")
      (libsource (lib "eagle-import") (part "DIODE-GEN-PURPOSE-1KV-1A(DO-214AC)DO-214AC/1206"))
    )
    (comp (ref "D31")
      (value "Zen11")
      (footprint "eagle-import:SOD-123_MINI-SMA")
      (libsource (lib "eagle-import") (part "CGRM400-G1"))
    )
    (comp (ref "FID7")
      (value "FIDUCIAL")
      (footprint "eagle-import:FIDUCIAL_1MM")
      (libsource (lib "eagle-import") (part "FIDUCIAL"))
    )
    (comp (ref "FID8")
      (value "FIDUCIAL")
      (footprint "eagle-import:FIDUCIAL_1MM")
      (libsource (lib "eagle-import") (part "FIDUCIAL"))
    )
    (comp (ref "FID9")
      (value "FIDUCIAL")
      (footprint "eagle-import:FIDUCIAL_1MM")
      (libsource (lib "eagle-import") (part "FIDUCIAL"))
    )
    (comp (ref "FID10")
      (value "FIDUCIAL")
      (footprint "eagle-import:FIDUCIAL_1MM")
      (libsource (lib "eagle-import") (part "FIDUCIAL"))
    )
    (comp (ref "IC10")
      (value "4028")
      (footprint "eagle-import:SO16")
      (libsource (lib "eagle-import") (part "4028D"))
    )
    (comp (ref "IC11")
      (value "317TO202H_NOHOLE")
      (footprint "eagle-import:TO220H_NOHOLE")
      (libsource (lib "eagle-import") (part "317TO202H_NOHOLE"))
    )
    (comp (ref "IC12")
      (value "ULN2004")
      (footprint "eagle-import:SO16")
      (libsource (lib "eagle-import") (part "ULN2004AD"))
    )
    (comp (ref "IC13")
      (value "LM339")
      (footprint "eagle-import:SO14")
      (libsource (lib "eagle-import") (part "LM339D"))
    )
    (comp (ref "IC14")
      (value "78L06")
      (footprint "eagle-import:SOT89_ROUND")
      (libsource (lib "eagle-import") (part "78LXXSOT89_ROUND"))
    )
    (comp (ref "IC15")
      (value "555")
      (footprint "eagle-import:SO08")
      (libsource (lib "eagle-import") (part "555DNE"))
    )
    (comp (ref "IC16")
      (value "4538")
      (footprint "eagle-import:SO16")
      (libsource (lib "eagle-import") (part "4538D"))
    )
    (comp (ref "IC17")
      (value "78L10")
      (footprint "eagle-import:SOT89_ROUND")
      (libsource (lib "eagle-import") (part "78LXXSOT89_ROUND"))
    )
    (comp (ref "IC18")
      (value "LM2904")
      (footprint "eagle-import:SO08")
      (libsource (lib "eagle-import") (part "LM358D"))
    )
    (comp (ref "JP6")
      (value "JP2EJP2_SMALLPADS")
      (footprint "eagle-import:JP2_SMALLPADS")
      (libsource (lib "eagle-import") (part "JP2EJP2_SMALLPADS"))
    )
    (comp (ref "JP7")
      (value "JP2E_ORIG")
      (footprint "eagle-import:JP2_ORIG_SMALLPADS")
      (libsource (lib "eagle-import") (part "JP2E_ORIG"))
    )
    (comp (ref "JP8")
      (value "JP2EJP2_SMALLPADS")
      (footprint "eagle-import:JP2_SMALLPADS")
      (libsource (lib "eagle-import") (part "JP2EJP2_SMALLPADS"))
    )
    (comp (ref "JP9")
      (value "JP2EJP2_SMALLPADS")
      (footprint "eagle-import:JP2_SMALLPADS")
      (libsource (lib "eagle-import") (part "JP2EJP2_SMALLPADS"))
    )
    (comp (ref "JP10")
      (value "JP2EJP2_SMALLPADS")
      (footprint "eagle-import:JP2_SMALLPADS")
      (libsource (lib "eagle-import") (part "JP2EJP2_SMALLPADS"))
    )
    (comp (ref "LED7")
      (value "LEDLD260")
      (footprint "eagle-import:LD260")
      (libsource (lib "eagle-import") (part "LEDLD260"))
    )
    (comp (ref "LED8")
      (value "LEDLD260")
      (footprint "eagle-import:LD260")
      (libsource (lib "eagle-import") (part "LEDLD260"))
    )
    (comp (ref "LED9")
      (value "LEDLD260")
      (footprint "eagle-import:LD260")
      (libsource (lib "eagle-import") (part "LEDLD260"))
    )
    (comp (ref "LED10")
      (value "LEDLD260")
      (footprint "eagle-import:LD260")
      (libsource (lib "eagle-import") (part "LEDLD260"))
    )
    (comp (ref "LED11")
      (value "LEDLD260")
      (footprint "eagle-import:LD260")
      (libsource (lib "eagle-import") (part "LEDLD260"))
    )
    (comp (ref "LED12")
      (value "LEDLD260")
      (footprint "eagle-import:LD260")
      (libsource (lib "eagle-import") (part "LEDLD260"))
    )
    (comp (ref "Q14")
      (value "BA")
      (footprint "eagle-import:SOT89")
      (libsource (lib "eagle-import") (part "PNP-TRANSISTOR_SOT89"))
    )
    (comp (ref "Q15")
      (value "BA.")
      (footprint "eagle-import:SOT89")
      (libsource (lib "eagle-import") (part "PNP-TRANSISTOR_SOT89"))
    )
    (comp (ref "Q16")
      (value "BA.")
      (footprint "eagle-import:SOT89")
      (libsource (lib "eagle-import") (part "PNP-TRANSISTOR_SOT89"))
    )
    (comp (ref "Q17")
      (value "BA")
      (footprint "eagle-import:SOT89")
      (libsource (lib "eagle-import") (part "PNP-TRANSISTOR_SOT89"))
    )
    (comp (ref "Q18")
      (value "MY")
      (footprint "eagle-import:SOT89")
      (libsource (lib "eagle-import") (part "NPN-TRANSISTOR_SOT89"))
    )
    (comp (ref "Q19")
      (value "J1")
      (footprint "eagle-import:SOT-23")
      (fields (field (name "MPN") "BSS138W-7-F"))
      (libsource (lib "eagle-import") (part "SMD-MOSFET-N-CH-50V-200MA-BSS138W-7-F(SOT-23)"))
    )
    (comp (ref "Q20")
      (value "J1")
      (footprint "eagle-import:SOT-23")
      (fields (field (name "MPN") "BSS138W-7-F"))
      (libsource (lib "eagle-import") (part "SMD-MOSFET-N-CH-50V-200MA-BSS138W-7-F(SOT-23)"))
    )
    (comp (ref "Q21")
      (value "J1")
      (footprint "eagle-import:SOT-23")
      (fields (field (name "MPN") "BSS138W-7-F"))
      (libsource (lib "eagle-import") (part "SMD-MOSFET-N-CH-50V-200MA-BSS138W-7-F(SOT-23)"))
    )
    (comp (ref "Q22")
      (value "BA")
      (footprint "eagle-import:SOT89")
      (libsource (lib "eagle-import") (part "PNP-TRANSISTOR_SOT89"))
    )
    (comp (ref "Q23")
      (value "J1")
      (footprint "eagle-import:SOT-23")
      (fields (field (name "MPN") "BSS138W-7-F"))
      (libsource (lib "eagle-import") (part "SMD-MOSFET-N-CH-50V-200MA-BSS138W-7-F(SOT-23)"))
    )
    (comp (ref "R67")
      (value "47")
      (footprint "eagle-import:V235_17_1MM")
      (libsource (lib "eagle-import") (part "R-EU_V235/17_1MM"))
    )
    (comp (ref "R68")
      (value "13")
      (footprint "eagle-import:R1206")
      (fields (field (name "MPN") "RC1206JR-0713RL"))
      (libsource (lib "eagle-import") (part "SMD-RES-13R-5%-1/4W(1206)"))
    )
    (comp (ref "R69")
      (value "47")
      (footprint "eagle-import:V235_17_1MM")
      (libsource (lib "eagle-import") (part "R-EU_V235/17_1MM"))
    )
    (comp (ref "R70")
      (value "104")
      (footprint "eagle-import:R0805")
      (fields (field (name "MPN") "RC0805FR-0710KL"))
      (libsource (lib "eagle-import") (part "SMD-RES-10K-1%-1/8W(0805)"))
    )
    (comp (ref "R71")
      (value "104")
      (footprint "eagle-import:R0805")
      (fields (field (name "MPN") "RC0805FR-0710KL"))
      (libsource (lib "eagle-import") (part "SMD-RES-10K-1%-1/8W(0805)"))
    )
    (comp (ref "R72")
      (value "104")
      (footprint "eagle-import:R0805")
      (fields (field (name "MPN") "RC0805FR-0710KL"))
      (libsource (lib "eagle-import") (part "SMD-RES-10K-1%-1/8W(0805)"))
    )
    (comp (ref "R73")
      (value "4701")
      (footprint "eagle-import:R0805")
      (fields (field (name "MPN") "RC0805JR-074K7L"))
      (libsource (lib "eagle-import") (part "SMD-RES-4.7K-5%-1/8W(0805)"))
    )
    (comp (ref "R74")
      (value "1002")
      (footprint "eagle-import:R0805")
      (fields (field (name "MPN") "RC0805FR-0710KL"))
      (libsource (lib "eagle-import") (part "SMD-RES-10K-1%-1/8W(0805)"))
    )
    (comp (ref "R75")
      (value "1002")
      (footprint "eagle-import:R0805")
      (fields (field (name "MPN") "RC0805FR-0710KL"))
      (libsource (lib "eagle-import") (part "SMD-RES-10K-1%-1/8W(0805)"))
    )
    (comp (ref "R76")
      (value "1502")
      (footprint "eagle-import:R0805")
      (fields (field (name "MPN") "RC0805FR-0710KL"))
      (libsource (lib "eagle-import") (part "SMD-RES-10K-1%-1/8W(0805)"))
    )
    (comp (ref "R77")
      (value "104")
      (footprint "eagle-import:R0805")
      (fields (field (name "MPN") "RC0805FR-0710KL"))
      (libsource (lib "eagle-import") (part "SMD-RES-10K-1%-1/8W(0805)"))
    )
    (comp (ref "R78")
      (value "104")
      (footprint "eagle-import:R0805")
      (fields (field (name "MPN") "RC0805FR-0710KL"))
      (libsource (lib "eagle-import") (part "SMD-RES-10K-1%-1/8W(0805)"))
    )
    (comp (ref "R79")
      (value "1502")
      (footprint "eagle-import:R0805")
      (fields (field (name "MPN") "RC0805FR-0710KL"))
      (libsource (lib "eagle-import") (part "SMD-RES-10K-1%-1/8W(0805)"))
    )
    (comp (ref "R80")
      (value "1002")
      (footprint "eagle-import:R0805")
      (fields (field (name "MPN") "RC0805FR-0710KL"))
      (libsource (lib "eagle-import") (part "SMD-RES-10K-1%-1/8W(0805)"))
    )
    (comp (ref "R81")
      (value "2201")
      (footprint "eagle-import:R0805")
      (fields (field (name "MPN") "RC0805JR-072K2L"))
      (libsource (lib "eagle-import") (part "SMD-RES-2.2K-5%-1/8W(0805)"))
    )
    (comp (ref "R82")
      (value "1002")
      (footprint "eagle-import:R0805")
      (fields (field (name "MPN") "RC0805FR-0710KL"))
      (libsource (lib "eagle-import") (part "SMD-RES-10K-1%-1/8W(0805)"))
    )
    (comp (ref "R83")
      (value "4701")
      (footprint "eagle-import:R0805")
      (fields (field (name "MPN") "RC0805JR-074K7L"))
      (libsource (lib "eagle-import") (part "SMD-RES-4.7K-5%-1/8W(0805)"))
    )
    (comp (ref "R84")
      (value "2702")
      (footprint "eagle-import:R0805")
      (fields (field (name "MPN") "RC0805JR-074K7L"))
      (libsource (lib "eagle-import") (part "SMD-RES-4.7K-5%-1/8W(0805)"))
    )
    (comp (ref "R85")
      (value "102")
      (footprint "eagle-import:R0805")
      (fields (field (name "MPN") "RC0805JR-071KL"))
      (libsource (lib "eagle-import") (part "SMD-RES-1K-5%-1/8W(0805)"))
    )
    (comp (ref "R86")
      (value "R_user")
      (footprint "eagle-import:R0805")
      (libsource (lib "eagle-import") (part "R-EU_R0805"))
    )
    (comp (ref "R87")
      (value "102")
      (footprint "eagle-import:R0805")
      (fields (field (name "MPN") "RC0805JR-07220RL"))
      (libsource (lib "eagle-import") (part "SMD-RES-220R-5%-1/8W(0805)"))
    )
    (comp (ref "R88")
      (value "(101)")
      (footprint "eagle-import:R0805")
      (fields (field (name "MPN") "RC0805JR-07100RL"))
      (libsource (lib "eagle-import") (part "SMD-RES-100R-5%-1/8W(0805)"))
    )
    (comp (ref "R89")
      (value "(1000)")
      (footprint "eagle-import:R0805")
      (fields (field (name "MPN") "RC0805JR-07100RL"))
      (libsource (lib "eagle-import") (part "SMD-RES-100R-5%-1/8W(0805)"))
    )
    (comp (ref "R90")
      (value "102")
      (footprint "eagle-import:R0805")
      (fields (field (name "MPN") "RC0805JR-071KL"))
      (libsource (lib "eagle-import") (part "SMD-RES-1K-5%-1/8W(0805)"))
    )
    (comp (ref "R91")
      (value "13")
      (footprint "eagle-import:R1206")
      (fields (field (name "MPN") "RC1206JR-0713RL"))
      (libsource (lib "eagle-import") (part "SMD-RES-13R-5%-1/4W(1206)"))
    )
    (comp (ref "R92")
      (value "13")
      (footprint "eagle-import:R1206")
      (fields (field (name "MPN") "RC1206JR-0713RL"))
      (libsource (lib "eagle-import") (part "SMD-RES-13R-5%-1/4W(1206)"))
    )
    (comp (ref "R93")
      (value "2702")
      (footprint "eagle-import:R0805")
      (fields (field (name "MPN") "RC0805JR-074K7L"))
      (libsource (lib "eagle-import") (part "SMD-RES-4.7K-5%-1/8W(0805)"))
    )
    (comp (ref "R94")
      (value "4701")
      (footprint "eagle-import:R0805")
      (fields (field (name "MPN") "RC0805JR-074K7L"))
      (libsource (lib "eagle-import") (part "SMD-RES-4.7K-5%-1/8W(0805)"))
    )
    (comp (ref "R95")
      (value "100")
      (footprint "eagle-import:R0805")
      (fields (field (name "MPN") "RC0805JR-072K2L"))
      (libsource (lib "eagle-import") (part "SMD-RES-2.2K-5%-1/8W(0805)"))
    )
    (comp (ref "R96")
      (value "104")
      (footprint "eagle-import:R0805")
      (fields (field (name "MPN") "RC0805FR-0710KL"))
      (libsource (lib "eagle-import") (part "SMD-RES-10K-1%-1/8W(0805)"))
    )
    (comp (ref "R97")
      (value "104")
      (footprint "eagle-import:R0805")
      (fields (field (name "MPN") "RC0805FR-0710KL"))
      (libsource (lib "eagle-import") (part "SMD-RES-10K-1%-1/8W(0805)"))
    )
    (comp (ref "R98")
      (value "(1002)")
      (footprint "eagle-import:R0805")
      (fields (field (name "MPN") "RC0805FR-0710KL"))
      (libsource (lib "eagle-import") (part "SMD-RES-10K-1%-1/8W(0805)"))
    )
    (comp (ref "R99")
      (value "2702")
      (footprint "eagle-import:R0805")
      (fields (field (name "MPN") "RC0805FR-0710KL"))
      (libsource (lib "eagle-import") (part "SMD-RES-10K-1%-1/8W(0805)"))
    )
    (comp (ref "R100")
      (value "47")
      (footprint "eagle-import:V235_17_1MM")
      (libsource (lib "eagle-import") (part "R-EU_V235/17_1MM"))
    )
    (comp (ref "R118")
      (value "47")
      (footprint "eagle-import:V235_17_1MM")
      (libsource (lib "eagle-import") (part "R-EU_V235/17_1MM"))
    )
    (comp (ref "R139")
      (value "2702")
      (footprint "eagle-import:R0805")
      (fields (field (name "MPN") "RC0805JR-074K7L"))
      (libsource (lib "eagle-import") (part "SMD-RES-4.7K-5%-1/8W(0805)"))
    )
    (comp (ref "R147")
      (value "2201")
      (footprint "eagle-import:R0805")
      (fields (field (name "MPN") "RC0805JR-072K2L"))
      (libsource (lib "eagle-import") (part "SMD-RES-2.2K-5%-1/8W(0805)"))
    )
    (comp (ref "R148")
      (value "1002")
      (footprint "eagle-import:R0805")
      (fields (field (name "MPN") "RC0805JR-074K7L"))
      (libsource (lib "eagle-import") (part "SMD-RES-4.7K-5%-1/8W(0805)"))
    )
    (comp (ref "R149")
      (value "1002")
      (footprint "eagle-import:R0805")
      (fields (field (name "MPN") "RC0805FR-0710KL"))
      (libsource (lib "eagle-import") (part "SMD-RES-10K-1%-1/8W(0805)"))
    )
    (comp (ref "R150")
      (value "102")
      (footprint "eagle-import:R0805")
      (fields (field (name "MPN") "RC0805JR-071KL"))
      (libsource (lib "eagle-import") (part "SMD-RES-1K-5%-1/8W(0805)"))
    )
    (comp (ref "R151")
      (value "2702")
      (footprint "eagle-import:R0805")
      (fields (field (name "MPN") "RC0805JR-074K7L"))
      (libsource (lib "eagle-import") (part "SMD-RES-4.7K-5%-1/8W(0805)"))
    )
    (comp (ref "R152")
      (value "1002")
      (footprint "eagle-import:R0805")
      (fields (field (name "MPN") "RC0805JR-071KL"))
      (libsource (lib "eagle-import") (part "SMD-RES-1K-5%-1/8W(0805)"))
    )
    (comp (ref "R153")
      (value "1002")
      (footprint "eagle-import:R0805")
      (fields (field (name "MPN") "RC0805JR-071KL"))
      (libsource (lib "eagle-import") (part "SMD-RES-1K-5%-1/8W(0805)"))
    )
    (comp (ref "R154")
      (value "R_user")
      (footprint "eagle-import:R0805")
      (libsource (lib "eagle-import") (part "R-EU_R0805"))
    )
    (comp (ref "R155")
      (value "104")
      (footprint "eagle-import:R0805")
      (fields (field (name "MPN") "RC0805FR-0710KL"))
      (libsource (lib "eagle-import") (part "SMD-RES-10K-1%-1/8W(0805)"))
    )
    (comp (ref "R156")
      (value "104")
      (footprint "eagle-import:R0805")
      (fields (field (name "MPN") "RC0805FR-0710KL"))
      (libsource (lib "eagle-import") (part "SMD-RES-10K-1%-1/8W(0805)"))
    )
    (comp (ref "R157")
      (value "104")
      (footprint "eagle-import:R0805")
      (fields (field (name "MPN") "RC0805FR-0710KL"))
      (libsource (lib "eagle-import") (part "SMD-RES-10K-1%-1/8W(0805)"))
    )
    (comp (ref "R158")
      (value "13")
      (footprint "eagle-import:R1206")
      (fields (field (name "MPN") "RC1206JR-0713RL"))
      (libsource (lib "eagle-import") (part "SMD-RES-13R-5%-1/4W(1206)"))
    )
    (comp (ref "R159")
      (value "2201")
      (footprint "eagle-import:R0805")
      (fields (field (name "MPN") "RC0805JR-071KL"))
      (libsource (lib "eagle-import") (part "SMD-RES-1K-5%-1/8W(0805)"))
    )
    (comp (ref "R160")
      (value "100")
      (footprint "eagle-import:R0805")
      (fields (field (name "MPN") "RC0805JR-07220RL"))
      (libsource (lib "eagle-import") (part "SMD-RES-220R-5%-1/8W(0805)"))
    )
    (comp (ref "R161")
      (value "13")
      (footprint "eagle-import:R1206")
      (fields (field (name "MPN") "RC1206JR-0713RL"))
      (libsource (lib "eagle-import") (part "SMD-RES-13R-5%-1/4W(1206)"))
    )
    (comp (ref "R162")
      (value "4701")
      (footprint "eagle-import:R0805")
      (fields (field (name "MPN") "RC0805JR-074K7L"))
      (libsource (lib "eagle-import") (part "SMD-RES-4.7K-5%-1/8W(0805)"))
    )
    (comp (ref "R163")
      (value "104")
      (footprint "eagle-import:R0805")
      (fields (field (name "MPN") "RC0805JR-074K7L"))
      (libsource (lib "eagle-import") (part "SMD-RES-4.7K-5%-1/8W(0805)"))
    )
    (comp (ref "R164")
      (value "100")
      (footprint "eagle-import:R0805")
      (fields (field (name "MPN") "RC0805JR-072K2L"))
      (libsource (lib "eagle-import") (part "SMD-RES-2.2K-5%-1/8W(0805)"))
    )
    (comp (ref "R165")
      (value "100")
      (footprint "eagle-import:R0805")
      (fields (field (name "MPN") "RC0805JR-072K2L"))
      (libsource (lib "eagle-import") (part "SMD-RES-2.2K-5%-1/8W(0805)"))
    )
    (comp (ref "SJ2")
      (value "SJ")
      (footprint "eagle-import:SJ")
      (libsource (lib "eagle-import") (part "solder-jumper_SJ"))
    )
    (comp (ref "SJMP2")
      (value "SJ")
      (footprint "eagle-import:SJ")
      (libsource (lib "eagle-import") (part "SJ"))
    )
    (comp (ref "START2")
      (value "TPSB2.0")
      (footprint "eagle-import:B2.0")
      (libsource (lib "eagle-import") (part "TPSB2.0"))
    )
    (comp (ref "TP47")
      (value "TPSB2.0")
      (footprint "eagle-import:B2.0")
      (libsource (lib "eagle-import") (part "TPSB2.0"))
    )
    (comp (ref "TP48")
      (value "TPSB2.0")
      (footprint "eagle-import:B2.0")
      (libsource (lib "eagle-import") (part "TPSB2.0"))
    )
    (comp (ref "TP49")
      (value "TPSB2.0")
      (footprint "eagle-import:B2.0")
      (libsource (lib "eagle-import") (part "TPSB2.0"))
    )
    (comp (ref "TP50")
      (value "TPSB2.0")
      (footprint "eagle-import:B2.0")
      (libsource (lib "eagle-import") (part "TPSB2.0"))
    )
    (comp (ref "TP51")
      (value "TPSB2.0")
      (footprint "eagle-import:B2.0")
      (libsource (lib "eagle-import") (part "TPSB2.0"))
    )
    (comp (ref "TP52")
      (value "TPSB2.0")
      (footprint "eagle-import:B2.0")
      (libsource (lib "eagle-import") (part "TPSB2.0"))
    )
    (comp (ref "TP53")
      (value "TPSB2.0")
      (footprint "eagle-import:B2.0")
      (libsource (lib "eagle-import") (part "TPSB2.0"))
    )
    (comp (ref "TP54")
      (value "TPSB2.0")
      (footprint "eagle-import:B2.0")
      (libsource (lib "eagle-import") (part "TPSB2.0"))
    )
    (comp (ref "TP55")
      (value "TPSB2.0")
      (footprint "eagle-import:B2.0")
      (libsource (lib "eagle-import") (part "TPSB2.0"))
    )
    (comp (ref "TP56")
      (value "TPSB2.0")
      (footprint "eagle-import:B2.0")
      (libsource (lib "eagle-import") (part "TPSB2.0"))
    )
    (comp (ref "TP57")
      (value "TPSB2.0")
      (footprint "eagle-import:B2.0")
      (libsource (lib "eagle-import") (part "TPSB2.0"))
    )
    (comp (ref "TP58")
      (value "TPSB2.0")
      (footprint "eagle-import:B2.0")
      (libsource (lib "eagle-import") (part "TPSB2.0"))
    )
    (comp (ref "TP59")
      (value "TPSB2.0")
      (footprint "eagle-import:B2.0")
      (libsource (lib "eagle-import") (part "TPSB2.0"))
    )
    (comp (ref "TP60")
      (value "TPSB2.0")
      (footprint "eagle-import:B2.0")
      (libsource (lib "eagle-import") (part "TPSB2.0"))
    )
    (comp (ref "TP61")
      (value "TPSB2.0")
      (footprint "eagle-import:B2.0")
      (libsource (lib "eagle-import") (part "TPSB2.0"))
    )
    (comp (ref "TP62")
      (value "TPSB2.0")
      (footprint "eagle-import:B2.0")
      (libsource (lib "eagle-import") (part "TPSB2.0"))
    )
    (comp (ref "TP63")
      (value "TPSB2.0")
      (footprint "eagle-import:B2.0")
      (libsource (lib "eagle-import") (part "TPSB2.0"))
    )
    (comp (ref "TP64")
      (value "TPSB2.0")
      (footprint "eagle-import:B2.0")
      (libsource (lib "eagle-import") (part "TPSB2.0"))
    )
    (comp (ref "TP65")
      (value "TPSB1,27")
      (footprint "eagle-import:B1,27")
      (libsource (lib "eagle-import") (part "TPSB1,27"))
    )
    (comp (ref "TP66")
      (value "TPSB2.0")
      (footprint "eagle-import:B2.0")
      (libsource (lib "eagle-import") (part "TPSB2.0"))
    )
    (comp (ref "TP67")
      (value "TPSB2.0")
      (footprint "eagle-import:B2.0")
      (libsource (lib "eagle-import") (part "TPSB2.0"))
    )
    (comp (ref "TP68")
      (value "TPSB2.0")
      (footprint "eagle-import:B2.0")
      (libsource (lib "eagle-import") (part "TPSB2.0"))
    )
    (comp (ref "TP69")
      (value "TPSB2.0")
      (footprint "eagle-import:B2.0")
      (libsource (lib "eagle-import") (part "TPSB2.0"))
    )
    (comp (ref "X4")
      (value "CON_BMWV2")
      (footprint "eagle-import:24-PIN_V2")
      (libsource (lib "eagle-import") (part "CON_BMWV2"))
    )
    (comp (ref "X5")
      (value "22-23-2051")
      (footprint "eagle-import:22-23-2051")
      (fields (field (name "MF") "MOLEX"))
      (libsource (lib "eagle-import") (part "22-23-2051"))
    )
    (comp (ref "X6")
      (value "22-23-2021")
      (footprint "eagle-import:22-23-2021")
      (fields (field (name "MF") "MOLEX"))
      (libsource (lib "eagle-import") (part "22-23-2021"))
    )
    (comp (ref "6V5")
      (value "TPSB2.0")
      (footprint "eagle-import:B2.0")
      (libsource (lib "eagle-import") (part "TPSB2.0"))
    )
    (comp (ref "10V5")
      (value "TPSB2.0")
      (footprint "eagle-import:B2.0")
      (libsource (lib "eagle-import") (part "TPSB2.0"))
    )
    (comp (ref "11")
      (value "2081-1132")
      (footprint "eagle-import:12-PIN")
      (libsource (lib "eagle-import") (part "2081-1132"))
    )
    (comp (ref "12")
      (value "2081-1132")
      (footprint "eagle-import:12-PIN")
      (libsource (lib "eagle-import") (part "2081-1132"))
    )
    (comp (ref "C51")
      (value "100u")
      (footprint "eagle-import:C1206")
      (fields (field (name "MPN") "GRM31CR60J107ME39L"))
      (libsource (lib "eagle-import") (part "CERAMIC-100UF-6.3V-20%-X5R(1206)"))
    )
    (comp (ref "C52")
      (value "100u")
      (footprint "eagle-import:C1206")
      (fields (field (name "MPN") "GRM31CR60J107ME39L"))
      (libsource (lib "eagle-import") (part "CERAMIC-100UF-6.3V-20%-X5R(1206)"))
    )
    (comp (ref "C53")
      (value "100nF,")
      (footprint "eagle-import:C0805")
      (fields (field (name "MPN") "CC0805KRX7R9BB104"))
      (libsource (lib "eagle-import") (part "CERAMIC-100NF-50V-10%-X7R(0805)"))
    )
    (comp (ref "C54")
      (value "4.7u")
      (footprint "eagle-import:C0805")
      (fields (field (name "MPN") "CC0805KKX5R8BB475"))
      (libsource (lib "eagle-import") (part "CERAMIC-4.7UF-25V-10%-X5R(0805)"))
    )
    (comp (ref "C55")
      (value "100nF.")
      (footprint "eagle-import:C0805")
      (fields (field (name "MPN") "CC0805KRX7R9BB104"))
      (libsource (lib "eagle-import") (part "CERAMIC-100NF-50V-10%-X7R(0805)"))
    )
    (comp (ref "C56")
      (value "100nF.")
      (footprint "eagle-import:C0805")
      (fields (field (name "MPN") "CC0805KRX7R9BB104"))
      (libsource (lib "eagle-import") (part "CERAMIC-100NF-50V-10%-X7R(0805)"))
    )
    (comp (ref "C57")
      (value "2.2nF")
      (footprint "eagle-import:C0805")
      (fields (field (name "MPN") "CC0805KRX7R9BB104"))
      (libsource (lib "eagle-import") (part "CERAMIC-100NF-50V-10%-X7R(0805)"))
    )
    (comp (ref "C58")
      (value "100nF")
      (footprint "eagle-import:C0805")
      (fields (field (name "MPN") "CC0805KRX7R9BB104"))
      (libsource (lib "eagle-import") (part "CERAMIC-100NF-50V-10%-X7R(0805)"))
    )
    (comp (ref "C59")
      (value "100nF")
      (footprint "eagle-import:C0805")
      (fields (field (name "MPN") "CC0805KRX7R9BB104"))
      (libsource (lib "eagle-import") (part "CERAMIC-100NF-50V-10%-X7R(0805)"))
    )
    (comp (ref "C60")
      (value "100nF,")
      (footprint "eagle-import:C0805")
      (fields (field (name "MPN") "CC0805KRX7R9BB104"))
      (libsource (lib "eagle-import") (part "CERAMIC-100NF-50V-10%-X7R(0805)"))
    )
    (comp (ref "C61")
      (value "4.7u")
      (footprint "eagle-import:C0805")
      (fields (field (name "MPN") "CC0805KKX5R8BB475"))
      (libsource (lib "eagle-import") (part "CERAMIC-4.7UF-25V-10%-X5R(0805)"))
    )
    (comp (ref "C62")
      (value "10u")
      (footprint "eagle-import:C1206")
      (fields (field (name "MPN") "GRM31CR60J107ME39L"))
      (libsource (lib "eagle-import") (part "CERAMIC-100UF-6.3V-20%-X5R(1206)"))
    )
    (comp (ref "D60")
      (value "1N4007,")
      (footprint "eagle-import:DO-214AC")
      (fields (field (name "MPN") "1N4007"))
      (libsource (lib "eagle-import") (part "DIODE-GEN-PURPOSE-1KV-1A(DO-214AC)"))
    )
    (comp (ref "D61")
      (value "1N4007,")
      (footprint "eagle-import:DO-214AC")
      (fields (field (name "MPN") "1N4007"))
      (libsource (lib "eagle-import") (part "DIODE-GEN-PURPOSE-1KV-1A(DO-214AC)"))
    )
    (comp (ref "D62")
      (value "1N4007.")
      (footprint "eagle-import:DO-214AC")
      (fields (field (name "MPN") "1N4007"))
      (libsource (lib "eagle-import") (part "DIODE-GEN-PURPOSE-1KV-1A(DO-214AC)"))
    )
    (comp (ref "D63")
      (value "1N5817")
      (footprint "eagle-import:DO-214AC_SLIM")
      (libsource (lib "eagle-import") (part "DIODE-GEN-PURPOSE-1KV-1A(DO-214AC)DO-214AC/1206"))
    )
    (comp (ref "D64")
      (value "1N5817.")
      (footprint "eagle-import:DO-214AC_SLIM")
      (libsource (lib "eagle-import") (part "DIODE-GEN-PURPOSE-1KV-1A(DO-214AC)DO-214AC/1206"))
    )
    (comp (ref "D65")
      (value "1N5817.")
      (footprint "eagle-import:DO-214AC_SLIM")
      (libsource (lib "eagle-import") (part "DIODE-GEN-PURPOSE-1KV-1A(DO-214AC)DO-214AC/1206"))
    )
    (comp (ref "D66")
      (value "1N5817")
      (footprint "eagle-import:DO-214AC_SLIM")
      (libsource (lib "eagle-import") (part "DIODE-GEN-PURPOSE-1KV-1A(DO-214AC)DO-214AC/1206"))
    )
    (comp (ref "D67")
      (value "1N4007.")
      (footprint "eagle-import:DO-214AC")
      (fields (field (name "MPN") "1N4007"))
      (libsource (lib "eagle-import") (part "DIODE-GEN-PURPOSE-1KV-1A(DO-214AC)"))
    )
    (comp (ref "D68")
      (value "1N4007")
      (footprint "eagle-import:DO-214AC")
      (libsource (lib "eagle-import") (part "DIODE-GEN-PURPOSE-1KV-1A(DO-214AC)"))
    )
    (comp (ref "D69")
      (value "Zen15")
      (footprint "eagle-import:DO214AA")
      (libsource (lib "eagle-import") (part "SM6T"))
    )
    (comp (ref "D70")
      (value "SM6TDO214AA_BI")
      (footprint "eagle-import:DO214AA_BI")
      (libsource (lib "eagle-import") (part "SM6TDO214AA_BI"))
    )
    (comp (ref "D71")
      (value "1N5817")
      (footprint "eagle-import:DO-214AC_SLIM")
      (libsource (lib "eagle-import") (part "DIODE-GEN-PURPOSE-1KV-1A(DO-214AC)DO-214AC/1206"))
    )
    (comp (ref "D72")
      (value "1N5817.")
      (footprint "eagle-import:DO-214AC_SLIM")
      (libsource (lib "eagle-import") (part "DIODE-GEN-PURPOSE-1KV-1A(DO-214AC)DO-214AC/1206"))
    )
    (comp (ref "D73")
      (value "Zen11")
      (footprint "eagle-import:SOD-123_MINI-SMA")
      (libsource (lib "eagle-import") (part "CGRM400-G1"))
    )
    (comp (ref "FID19")
      (value "FIDUCIAL")
      (footprint "eagle-import:FIDUCIAL_1MM")
      (libsource (lib "eagle-import") (part "FIDUCIAL"))
    )
    (comp (ref "FID20")
      (value "FIDUCIAL")
      (footprint "eagle-import:FIDUCIAL_1MM")
      (libsource (lib "eagle-import") (part "FIDUCIAL"))
    )
    (comp (ref "FID21")
      (value "FIDUCIAL")
      (footprint "eagle-import:FIDUCIAL_1MM")
      (libsource (lib "eagle-import") (part "FIDUCIAL"))
    )
    (comp (ref "FID22")
      (value "FIDUCIAL")
      (footprint "eagle-import:FIDUCIAL_1MM")
      (libsource (lib "eagle-import") (part "FIDUCIAL"))
    )
    (comp (ref "IC37")
      (value "4028")
      (footprint "eagle-import:SO16")
      (libsource (lib "eagle-import") (part "4028D"))
    )
    (comp (ref "IC38")
      (value "317TO202H_NOHOLE")
      (footprint "eagle-import:TO220H_NOHOLE")
      (libsource (lib "eagle-import") (part "317TO202H_NOHOLE"))
    )
    (comp (ref "IC39")
      (value "ULN2004")
      (footprint "eagle-import:SO16")
      (libsource (lib "eagle-import") (part "ULN2004AD"))
    )
    (comp (ref "IC40")
      (value "LM339")
      (footprint "eagle-import:SO14")
      (libsource (lib "eagle-import") (part "LM339D"))
    )
    (comp (ref "IC41")
      (value "78L06")
      (footprint "eagle-import:SOT89_ROUND")
      (libsource (lib "eagle-import") (part "78LXXSOT89_ROUND"))
    )
    (comp (ref "IC42")
      (value "555")
      (footprint "eagle-import:SO08")
      (libsource (lib "eagle-import") (part "555DNE"))
    )
    (comp (ref "IC43")
      (value "4538")
      (footprint "eagle-import:SO16")
      (libsource (lib "eagle-import") (part "4538D"))
    )
    (comp (ref "IC44")
      (value "78L10")
      (footprint "eagle-import:SOT89_ROUND")
      (libsource (lib "eagle-import") (part "78LXXSOT89_ROUND"))
    )
    (comp (ref "IC45")
      (value "LM2904")
      (footprint "eagle-import:SO08")
      (libsource (lib "eagle-import") (part "LM358D"))
    )
    (comp (ref "JP21")
      (value "JP2EJP2_SMALLPADS")
      (footprint "eagle-import:JP2_SMALLPADS")
      (libsource (lib "eagle-import") (part "JP2EJP2_SMALLPADS"))
    )
    (comp (ref "JP22")
      (value "JP2E_ORIG")
      (footprint "eagle-import:JP2_ORIG_SMALLPADS")
      (libsource (lib "eagle-import") (part "JP2E_ORIG"))
    )
    (comp (ref "JP23")
      (value "JP2EJP2_SMALLPADS")
      (footprint "eagle-import:JP2_SMALLPADS")
      (libsource (lib "eagle-import") (part "JP2EJP2_SMALLPADS"))
    )
    (comp (ref "JP24")
      (value "JP2EJP2_SMALLPADS")
      (footprint "eagle-import:JP2_SMALLPADS")
      (libsource (lib "eagle-import") (part "JP2EJP2_SMALLPADS"))
    )
    (comp (ref "JP25")
      (value "JP2EJP2_SMALLPADS")
      (footprint "eagle-import:JP2_SMALLPADS")
      (libsource (lib "eagle-import") (part "JP2EJP2_SMALLPADS"))
    )
    (comp (ref "LED25")
      (value "LEDLD260")
      (footprint "eagle-import:LD260")
      (libsource (lib "eagle-import") (part "LEDLD260"))
    )
    (comp (ref "LED26")
      (value "LEDLD260")
      (footprint "eagle-import:LD260")
      (libsource (lib "eagle-import") (part "LEDLD260"))
    )
    (comp (ref "LED27")
      (value "LEDLD260")
      (footprint "eagle-import:LD260")
      (libsource (lib "eagle-import") (part "LEDLD260"))
    )
    (comp (ref "LED28")
      (value "LEDLD260")
      (footprint "eagle-import:LD260")
      (libsource (lib "eagle-import") (part "LEDLD260"))
    )
    (comp (ref "LED29")
      (value "LEDLD260")
      (footprint "eagle-import:LD260")
      (libsource (lib "eagle-import") (part "LEDLD260"))
    )
    (comp (ref "LED30")
      (value "LEDLD260")
      (footprint "eagle-import:LD260")
      (libsource (lib "eagle-import") (part "LEDLD260"))
    )
    (comp (ref "Q44")
      (value "BA")
      (footprint "eagle-import:SOT89")
      (libsource (lib "eagle-import") (part "PNP-TRANSISTOR_SOT89"))
    )
    (comp (ref "Q45")
      (value "BA.")
      (footprint "eagle-import:SOT89")
      (libsource (lib "eagle-import") (part "PNP-TRANSISTOR_SOT89"))
    )
    (comp (ref "Q46")
      (value "BA.")
      (footprint "eagle-import:SOT89")
      (libsource (lib "eagle-import") (part "PNP-TRANSISTOR_SOT89"))
    )
    (comp (ref "Q47")
      (value "BA")
      (footprint "eagle-import:SOT89")
      (libsource (lib "eagle-import") (part "PNP-TRANSISTOR_SOT89"))
    )
    (comp (ref "Q48")
      (value "MY")
      (footprint "eagle-import:SOT89")
      (libsource (lib "eagle-import") (part "NPN-TRANSISTOR_SOT89"))
    )
    (comp (ref "Q49")
      (value "J1")
      (footprint "eagle-import:SOT-23")
      (fields (field (name "MPN") "BSS138W-7-F"))
      (libsource (lib "eagle-import") (part "SMD-MOSFET-N-CH-50V-200MA-BSS138W-7-F(SOT-23)"))
    )
    (comp (ref "Q50")
      (value "J1")
      (footprint "eagle-import:SOT-23")
      (fields (field (name "MPN") "BSS138W-7-F"))
      (libsource (lib "eagle-import") (part "SMD-MOSFET-N-CH-50V-200MA-BSS138W-7-F(SOT-23)"))
    )
    (comp (ref "Q51")
      (value "J1")
      (footprint "eagle-import:SOT-23")
      (fields (field (name "MPN") "BSS138W-7-F"))
      (libsource (lib "eagle-import") (part "SMD-MOSFET-N-CH-50V-200MA-BSS138W-7-F(SOT-23)"))
    )
    (comp (ref "Q52")
      (value "BA")
      (footprint "eagle-import:SOT89")
      (libsource (lib "eagle-import") (part "PNP-TRANSISTOR_SOT89"))
    )
    (comp (ref "Q53")
      (value "J1")
      (footprint "eagle-import:SOT-23")
      (fields (field (name "MPN") "BSS138W-7-F"))
      (libsource (lib "eagle-import") (part "SMD-MOSFET-N-CH-50V-200MA-BSS138W-7-F(SOT-23)"))
    )
    (comp (ref "R276")
      (value "47")
      (footprint "eagle-import:V235_17_1MM")
      (libsource (lib "eagle-import") (part "R-EU_V235/17_1MM"))
    )
    (comp (ref "R277")
      (value "13")
      (footprint "eagle-import:R1206")
      (fields (field (name "MPN") "RC1206JR-0713RL"))
      (libsource (lib "eagle-import") (part "SMD-RES-13R-5%-1/4W(1206)"))
    )
    (comp (ref "R278")
      (value "47")
      (footprint "eagle-import:V235_17_1MM")
      (libsource (lib "eagle-import") (part "R-EU_V235/17_1MM"))
    )
    (comp (ref "R279")
      (value "104")
      (footprint "eagle-import:R0805")
      (fields (field (name "MPN") "RC0805FR-0710KL"))
      (libsource (lib "eagle-import") (part "SMD-RES-10K-1%-1/8W(0805)"))
    )
    (comp (ref "R280")
      (value "104")
      (footprint "eagle-import:R0805")
      (fields (field (name "MPN") "RC0805FR-0710KL"))
      (libsource (lib "eagle-import") (part "SMD-RES-10K-1%-1/8W(0805)"))
    )
    (comp (ref "R281")
      (value "104")
      (footprint "eagle-import:R0805")
      (fields (field (name "MPN") "RC0805FR-0710KL"))
      (libsource (lib "eagle-import") (part "SMD-RES-10K-1%-1/8W(0805)"))
    )
    (comp (ref "R282")
      (value "4701")
      (footprint "eagle-import:R0805")
      (fields (field (name "MPN") "RC0805JR-074K7L"))
      (libsource (lib "eagle-import") (part "SMD-RES-4.7K-5%-1/8W(0805)"))
    )
    (comp (ref "R283")
      (value "1002")
      (footprint "eagle-import:R0805")
      (fields (field (name "MPN") "RC0805FR-0710KL"))
      (libsource (lib "eagle-import") (part "SMD-RES-10K-1%-1/8W(0805)"))
    )
    (comp (ref "R284")
      (value "1002")
      (footprint "eagle-import:R0805")
      (fields (field (name "MPN") "RC0805FR-0710KL"))
      (libsource (lib "eagle-import") (part "SMD-RES-10K-1%-1/8W(0805)"))
    )
    (comp (ref "R285")
      (value "1502")
      (footprint "eagle-import:R0805")
      (fields (field (name "MPN") "RC0805FR-0710KL"))
      (libsource (lib "eagle-import") (part "SMD-RES-10K-1%-1/8W(0805)"))
    )
    (comp (ref "R286")
      (value "104")
      (footprint "eagle-import:R0805")
      (fields (field (name "MPN") "RC0805FR-0710KL"))
      (libsource (lib "eagle-import") (part "SMD-RES-10K-1%-1/8W(0805)"))
    )
    (comp (ref "R287")
      (value "104")
      (footprint "eagle-import:R0805")
      (fields (field (name "MPN") "RC0805FR-0710KL"))
      (libsource (lib "eagle-import") (part "SMD-RES-10K-1%-1/8W(0805)"))
    )
    (comp (ref "R288")
      (value "1502")
      (footprint "eagle-import:R0805")
      (fields (field (name "MPN") "RC0805FR-0710KL"))
      (libsource (lib "eagle-import") (part "SMD-RES-10K-1%-1/8W(0805)"))
    )
    (comp (ref "R289")
      (value "1002")
      (footprint "eagle-import:R0805")
      (fields (field (name "MPN") "RC0805FR-0710KL"))
      (libsource (lib "eagle-import") (part "SMD-RES-10K-1%-1/8W(0805)"))
    )
    (comp (ref "R290")
      (value "2201")
      (footprint "eagle-import:R0805")
      (fields (field (name "MPN") "RC0805JR-072K2L"))
      (libsource (lib "eagle-import") (part "SMD-RES-2.2K-5%-1/8W(0805)"))
    )
    (comp (ref "R291")
      (value "1002")
      (footprint "eagle-import:R0805")
      (fields (field (name "MPN") "RC0805FR-0710KL"))
      (libsource (lib "eagle-import") (part "SMD-RES-10K-1%-1/8W(0805)"))
    )
    (comp (ref "R292")
      (value "4701")
      (footprint "eagle-import:R0805")
      (fields (field (name "MPN") "RC0805JR-074K7L"))
      (libsource (lib "eagle-import") (part "SMD-RES-4.7K-5%-1/8W(0805)"))
    )
    (comp (ref "R293")
      (value "2702")
      (footprint "eagle-import:R0805")
      (fields (field (name "MPN") "RC0805JR-074K7L"))
      (libsource (lib "eagle-import") (part "SMD-RES-4.7K-5%-1/8W(0805)"))
    )
    (comp (ref "R294")
      (value "102")
      (footprint "eagle-import:R0805")
      (fields (field (name "MPN") "RC0805JR-071KL"))
      (libsource (lib "eagle-import") (part "SMD-RES-1K-5%-1/8W(0805)"))
    )
    (comp (ref "R295")
      (value "R_user")
      (footprint "eagle-import:R0805")
      (libsource (lib "eagle-import") (part "R-EU_R0805"))
    )
    (comp (ref "R296")
      (value "102")
      (footprint "eagle-import:R0805")
      (fields (field (name "MPN") "RC0805JR-07220RL"))
      (libsource (lib "eagle-import") (part "SMD-RES-220R-5%-1/8W(0805)"))
    )
    (comp (ref "R297")
      (value "(101)")
      (footprint "eagle-import:R0805")
      (fields (field (name "MPN") "RC0805JR-07100RL"))
      (libsource (lib "eagle-import") (part "SMD-RES-100R-5%-1/8W(0805)"))
    )
    (comp (ref "R298")
      (value "(1000)")
      (footprint "eagle-import:R0805")
      (fields (field (name "MPN") "RC0805JR-07100RL"))
      (libsource (lib "eagle-import") (part "SMD-RES-100R-5%-1/8W(0805)"))
    )
    (comp (ref "R299")
      (value "102")
      (footprint "eagle-import:R0805")
      (fields (field (name "MPN") "RC0805JR-071KL"))
      (libsource (lib "eagle-import") (part "SMD-RES-1K-5%-1/8W(0805)"))
    )
    (comp (ref "R300")
      (value "13")
      (footprint "eagle-import:R1206")
      (fields (field (name "MPN") "RC1206JR-0713RL"))
      (libsource (lib "eagle-import") (part "SMD-RES-13R-5%-1/4W(1206)"))
    )
    (comp (ref "R301")
      (value "13")
      (footprint "eagle-import:R1206")
      (fields (field (name "MPN") "RC1206JR-0713RL"))
      (libsource (lib "eagle-import") (part "SMD-RES-13R-5%-1/4W(1206)"))
    )
    (comp (ref "R302")
      (value "2702")
      (footprint "eagle-import:R0805")
      (fields (field (name "MPN") "RC0805JR-074K7L"))
      (libsource (lib "eagle-import") (part "SMD-RES-4.7K-5%-1/8W(0805)"))
    )
    (comp (ref "R303")
      (value "4701")
      (footprint "eagle-import:R0805")
      (fields (field (name "MPN") "RC0805JR-074K7L"))
      (libsource (lib "eagle-import") (part "SMD-RES-4.7K-5%-1/8W(0805)"))
    )
    (comp (ref "R304")
      (value "100")
      (footprint "eagle-import:R0805")
      (fields (field (name "MPN") "RC0805JR-072K2L"))
      (libsource (lib "eagle-import") (part "SMD-RES-2.2K-5%-1/8W(0805)"))
    )
    (comp (ref "R305")
      (value "104")
      (footprint "eagle-import:R0805")
      (fields (field (name "MPN") "RC0805FR-0710KL"))
      (libsource (lib "eagle-import") (part "SMD-RES-10K-1%-1/8W(0805)"))
    )
    (comp (ref "R306")
      (value "104")
      (footprint "eagle-import:R0805")
      (fields (field (name "MPN") "RC0805FR-0710KL"))
      (libsource (lib "eagle-import") (part "SMD-RES-10K-1%-1/8W(0805)"))
    )
    (comp (ref "R307")
      (value "(1002)")
      (footprint "eagle-import:R0805")
      (fields (field (name "MPN") "RC0805FR-0710KL"))
      (libsource (lib "eagle-import") (part "SMD-RES-10K-1%-1/8W(0805)"))
    )
    (comp (ref "R308")
      (value "2702")
      (footprint "eagle-import:R0805")
      (fields (field (name "MPN") "RC0805FR-0710KL"))
      (libsource (lib "eagle-import") (part "SMD-RES-10K-1%-1/8W(0805)"))
    )
    (comp (ref "R309")
      (value "47")
      (footprint "eagle-import:V235_17_1MM")
      (libsource (lib "eagle-import") (part "R-EU_V235/17_1MM"))
    )
    (comp (ref "R310")
      (value "47")
      (footprint "eagle-import:V235_17_1MM")
      (libsource (lib "eagle-import") (part "R-EU_V235/17_1MM"))
    )
    (comp (ref "R311")
      (value "2702")
      (footprint "eagle-import:R0805")
      (fields (field (name "MPN") "RC0805JR-074K7L"))
      (libsource (lib "eagle-import") (part "SMD-RES-4.7K-5%-1/8W(0805)"))
    )
    (comp (ref "R312")
      (value "2201")
      (footprint "eagle-import:R0805")
      (fields (field (name "MPN") "RC0805JR-072K2L"))
      (libsource (lib "eagle-import") (part "SMD-RES-2.2K-5%-1/8W(0805)"))
    )
    (comp (ref "R313")
      (value "1002")
      (footprint "eagle-import:R0805")
      (fields (field (name "MPN") "RC0805JR-074K7L"))
      (libsource (lib "eagle-import") (part "SMD-RES-4.7K-5%-1/8W(0805)"))
    )
    (comp (ref "R314")
      (value "1002")
      (footprint "eagle-import:R0805")
      (fields (field (name "MPN") "RC0805FR-0710KL"))
      (libsource (lib "eagle-import") (part "SMD-RES-10K-1%-1/8W(0805)"))
    )
    (comp (ref "R315")
      (value "102")
      (footprint "eagle-import:R0805")
      (fields (field (name "MPN") "RC0805JR-071KL"))
      (libsource (lib "eagle-import") (part "SMD-RES-1K-5%-1/8W(0805)"))
    )
    (comp (ref "R316")
      (value "2702")
      (footprint "eagle-import:R0805")
      (fields (field (name "MPN") "RC0805JR-074K7L"))
      (libsource (lib "eagle-import") (part "SMD-RES-4.7K-5%-1/8W(0805)"))
    )
    (comp (ref "R317")
      (value "1002")
      (footprint "eagle-import:R0805")
      (fields (field (name "MPN") "RC0805JR-071KL"))
      (libsource (lib "eagle-import") (part "SMD-RES-1K-5%-1/8W(0805)"))
    )
    (comp (ref "R318")
      (value "1002")
      (footprint "eagle-import:R0805")
      (fields (field (name "MPN") "RC0805JR-071KL"))
      (libsource (lib "eagle-import") (part "SMD-RES-1K-5%-1/8W(0805)"))
    )
    (comp (ref "R319")
      (value "R_user")
      (footprint "eagle-import:R0805")
      (libsource (lib "eagle-import") (part "R-EU_R0805"))
    )
    (comp (ref "R320")
      (value "104")
      (footprint "eagle-import:R0805")
      (fields (field (name "MPN") "RC0805FR-0710KL"))
      (libsource (lib "eagle-import") (part "SMD-RES-10K-1%-1/8W(0805)"))
    )
    (comp (ref "R321")
      (value "104")
      (footprint "eagle-import:R0805")
      (fields (field (name "MPN") "RC0805FR-0710KL"))
      (libsource (lib "eagle-import") (part "SMD-RES-10K-1%-1/8W(0805)"))
    )
    (comp (ref "R322")
      (value "104")
      (footprint "eagle-import:R0805")
      (fields (field (name "MPN") "RC0805FR-0710KL"))
      (libsource (lib "eagle-import") (part "SMD-RES-10K-1%-1/8W(0805)"))
    )
    (comp (ref "R323")
      (value "13")
      (footprint "eagle-import:R1206")
      (fields (field (name "MPN") "RC1206JR-0713RL"))
      (libsource (lib "eagle-import") (part "SMD-RES-13R-5%-1/4W(1206)"))
    )
    (comp (ref "R324")
      (value "2201")
      (footprint "eagle-import:R0805")
      (fields (field (name "MPN") "RC0805JR-071KL"))
      (libsource (lib "eagle-import") (part "SMD-RES-1K-5%-1/8W(0805)"))
    )
    (comp (ref "R325")
      (value "100")
      (footprint "eagle-import:R0805")
      (fields (field (name "MPN") "RC0805JR-07220RL"))
      (libsource (lib "eagle-import") (part "SMD-RES-220R-5%-1/8W(0805)"))
    )
    (comp (ref "R326")
      (value "13")
      (footprint "eagle-import:R1206")
      (fields (field (name "MPN") "RC1206JR-0713RL"))
      (libsource (lib "eagle-import") (part "SMD-RES-13R-5%-1/4W(1206)"))
    )
    (comp (ref "R327")
      (value "4701")
      (footprint "eagle-import:R0805")
      (fields (field (name "MPN") "RC0805JR-074K7L"))
      (libsource (lib "eagle-import") (part "SMD-RES-4.7K-5%-1/8W(0805)"))
    )
    (comp (ref "R328")
      (value "104")
      (footprint "eagle-import:R0805")
      (fields (field (name "MPN") "RC0805JR-074K7L"))
      (libsource (lib "eagle-import") (part "SMD-RES-4.7K-5%-1/8W(0805)"))
    )
    (comp (ref "R329")
      (value "100")
      (footprint "eagle-import:R0805")
      (fields (field (name "MPN") "RC0805JR-072K2L"))
      (libsource (lib "eagle-import") (part "SMD-RES-2.2K-5%-1/8W(0805)"))
    )
    (comp (ref "R330")
      (value "100")
      (footprint "eagle-import:R0805")
      (fields (field (name "MPN") "RC0805JR-072K2L"))
      (libsource (lib "eagle-import") (part "SMD-RES-2.2K-5%-1/8W(0805)"))
    )
    (comp (ref "SJ5")
      (value "SJ")
      (footprint "eagle-import:SJ")
      (libsource (lib "eagle-import") (part "solder-jumper_SJ"))
    )
    (comp (ref "SJMP5")
      (value "SJ")
      (footprint "eagle-import:SJ")
      (libsource (lib "eagle-import") (part "SJ"))
    )
    (comp (ref "START5")
      (value "TPSB2.0")
      (footprint "eagle-import:B2.0")
      (libsource (lib "eagle-import") (part "TPSB2.0"))
    )
    (comp (ref "TP116")
      (value "TPSB2.0")
      (footprint "eagle-import:B2.0")
      (libsource (lib "eagle-import") (part "TPSB2.0"))
    )
    (comp (ref "TP117")
      (value "TPSB2.0")
      (footprint "eagle-import:B2.0")
      (libsource (lib "eagle-import") (part "TPSB2.0"))
    )
    (comp (ref "TP118")
      (value "TPSB2.0")
      (footprint "eagle-import:B2.0")
      (libsource (lib "eagle-import") (part "TPSB2.0"))
    )
    (comp (ref "TP119")
      (value "TPSB2.0")
      (footprint "eagle-import:B2.0")
      (libsource (lib "eagle-import") (part "TPSB2.0"))
    )
    (comp (ref "TP120")
      (value "TPSB2.0")
      (footprint "eagle-import:B2.0")
      (libsource (lib "eagle-import") (part "TPSB2.0"))
    )
    (comp (ref "TP121")
      (value "TPSB2.0")
      (footprint "eagle-import:B2.0")
      (libsource (lib "eagle-import") (part "TPSB2.0"))
    )
    (comp (ref "TP122")
      (value "TPSB2.0")
      (footprint "eagle-import:B2.0")
      (libsource (lib "eagle-import") (part "TPSB2.0"))
    )
    (comp (ref "TP123")
      (value "TPSB2.0")
      (footprint "eagle-import:B2.0")
      (libsource (lib "eagle-import") (part "TPSB2.0"))
    )
    (comp (ref "TP124")
      (value "TPSB2.0")
      (footprint "eagle-import:B2.0")
      (libsource (lib "eagle-import") (part "TPSB2.0"))
    )
    (comp (ref "TP125")
      (value "TPSB2.0")
      (footprint "eagle-import:B2.0")
      (libsource (lib "eagle-import") (part "TPSB2.0"))
    )
    (comp (ref "TP126")
      (value "TPSB2.0")
      (footprint "eagle-import:B2.0")
      (libsource (lib "eagle-import") (part "TPSB2.0"))
    )
    (comp (ref "TP127")
      (value "TPSB2.0")
      (footprint "eagle-import:B2.0")
      (libsource (lib "eagle-import") (part "TPSB2.0"))
    )
    (comp (ref "TP128")
      (value "TPSB2.0")
      (footprint "eagle-import:B2.0")
      (libsource (lib "eagle-import") (part "TPSB2.0"))
    )
    (comp (ref "TP129")
      (value "TPSB2.0")
      (footprint "eagle-import:B2.0")
      (libsource (lib "eagle-import") (part "TPSB2.0"))
    )
    (comp (ref "TP130")
      (value "TPSB2.0")
      (footprint "eagle-import:B2.0")
      (libsource (lib "eagle-import") (part "TPSB2.0"))
    )
    (comp (ref "TP131")
      (value "TPSB2.0")
      (footprint "eagle-import:B2.0")
      (libsource (lib "eagle-import") (part "TPSB2.0"))
    )
    (comp (ref "TP132")
      (value "TPSB2.0")
      (footprint "eagle-import:B2.0")
      (libsource (lib "eagle-import") (part "TPSB2.0"))
    )
    (comp (ref "TP133")
      (value "TPSB2.0")
      (footprint "eagle-import:B2.0")
      (libsource (lib "eagle-import") (part "TPSB2.0"))
    )
    (comp (ref "TP134")
      (value "TPSB1,27")
      (footprint "eagle-import:B1,27")
      (libsource (lib "eagle-import") (part "TPSB1,27"))
    )
    (comp (ref "TP135")
      (value "TPSB2.0")
      (footprint "eagle-import:B2.0")
      (libsource (lib "eagle-import") (part "TPSB2.0"))
    )
    (comp (ref "TP136")
      (value "TPSB2.0")
      (footprint "eagle-import:B2.0")
      (libsource (lib "eagle-import") (part "TPSB2.0"))
    )
    (comp (ref "TP137")
      (value "TPSB2.0")
      (footprint "eagle-import:B2.0")
      (libsource (lib "eagle-import") (part "TPSB2.0"))
    )
    (comp (ref "TP138")
      (value "TPSB2.0")
      (footprint "eagle-import:B2.0")
      (libsource (lib "eagle-import") (part "TPSB2.0"))
    )
    (comp (ref "X13")
      (value "CON_BMWV2")
      (footprint "eagle-import:24-PIN_V2")
      (libsource (lib "eagle-import") (part "CON_BMWV2"))
    )
    (comp (ref "X14")
      (value "22-23-2051")
      (footprint "eagle-import:22-23-2051")
      (fields (field (name "MF") "MOLEX"))
      (libsource (lib "eagle-import") (part "22-23-2051"))
    )
    (comp (ref "X15")
      (value "22-23-2021")
      (footprint "eagle-import:22-23-2021")
      (fields (field (name "MF") "MOLEX"))
      (libsource (lib "eagle-import") (part "22-23-2021"))
    )
    (comp (ref "6V3")
      (value "TPSB2.0")
      (footprint "eagle-import:B2.0")
      (libsource (lib "eagle-import") (part "TPSB2.0"))
    )
    (comp (ref "7")
      (value "2081-1132")
      (footprint "eagle-import:12-PIN")
      (libsource (lib "eagle-import") (part "2081-1132"))
    )
    (comp (ref "8")
      (value "2081-1132")
      (footprint "eagle-import:12-PIN")
      (libsource (lib "eagle-import") (part "2081-1132"))
    )
    (comp (ref "10V3")
      (value "TPSB2.0")
      (footprint "eagle-import:B2.0")
      (libsource (lib "eagle-import") (part "TPSB2.0"))
    )
    (comp (ref "C27")
      (value "100u")
      (footprint "eagle-import:C1206")
      (fields (field (name "MPN") "GRM31CR60J107ME39L"))
      (libsource (lib "eagle-import") (part "CERAMIC-100UF-6.3V-20%-X5R(1206)"))
    )
    (comp (ref "C28")
      (value "100u")
      (footprint "eagle-import:C1206")
      (fields (field (name "MPN") "GRM31CR60J107ME39L"))
      (libsource (lib "eagle-import") (part "CERAMIC-100UF-6.3V-20%-X5R(1206)"))
    )
    (comp (ref "C29")
      (value "100nF,")
      (footprint "eagle-import:C0805")
      (fields (field (name "MPN") "CC0805KRX7R9BB104"))
      (libsource (lib "eagle-import") (part "CERAMIC-100NF-50V-10%-X7R(0805)"))
    )
    (comp (ref "C30")
      (value "4.7u")
      (footprint "eagle-import:C0805")
      (fields (field (name "MPN") "CC0805KKX5R8BB475"))
      (libsource (lib "eagle-import") (part "CERAMIC-4.7UF-25V-10%-X5R(0805)"))
    )
    (comp (ref "C31")
      (value "100nF.")
      (footprint "eagle-import:C0805")
      (fields (field (name "MPN") "CC0805KRX7R9BB104"))
      (libsource (lib "eagle-import") (part "CERAMIC-100NF-50V-10%-X7R(0805)"))
    )
    (comp (ref "C32")
      (value "100nF.")
      (footprint "eagle-import:C0805")
      (fields (field (name "MPN") "CC0805KRX7R9BB104"))
      (libsource (lib "eagle-import") (part "CERAMIC-100NF-50V-10%-X7R(0805)"))
    )
    (comp (ref "C33")
      (value "2.2nF")
      (footprint "eagle-import:C0805")
      (fields (field (name "MPN") "CC0805KRX7R9BB104"))
      (libsource (lib "eagle-import") (part "CERAMIC-100NF-50V-10%-X7R(0805)"))
    )
    (comp (ref "C34")
      (value "100nF")
      (footprint "eagle-import:C0805")
      (fields (field (name "MPN") "CC0805KRX7R9BB104"))
      (libsource (lib "eagle-import") (part "CERAMIC-100NF-50V-10%-X7R(0805)"))
    )
    (comp (ref "C35")
      (value "100nF")
      (footprint "eagle-import:C0805")
      (fields (field (name "MPN") "CC0805KRX7R9BB104"))
      (libsource (lib "eagle-import") (part "CERAMIC-100NF-50V-10%-X7R(0805)"))
    )
    (comp (ref "C36")
      (value "100nF,")
      (footprint "eagle-import:C0805")
      (fields (field (name "MPN") "CC0805KRX7R9BB104"))
      (libsource (lib "eagle-import") (part "CERAMIC-100NF-50V-10%-X7R(0805)"))
    )
    (comp (ref "C37")
      (value "4.7u")
      (footprint "eagle-import:C0805")
      (fields (field (name "MPN") "CC0805KKX5R8BB475"))
      (libsource (lib "eagle-import") (part "CERAMIC-4.7UF-25V-10%-X5R(0805)"))
    )
    (comp (ref "C38")
      (value "10u")
      (footprint "eagle-import:C1206")
      (fields (field (name "MPN") "GRM31CR60J107ME39L"))
      (libsource (lib "eagle-import") (part "CERAMIC-100UF-6.3V-20%-X5R(1206)"))
    )
    (comp (ref "D32")
      (value "1N4007,")
      (footprint "eagle-import:DO-214AC")
      (fields (field (name "MPN") "1N4007"))
      (libsource (lib "eagle-import") (part "DIODE-GEN-PURPOSE-1KV-1A(DO-214AC)"))
    )
    (comp (ref "D33")
      (value "1N4007,")
      (footprint "eagle-import:DO-214AC")
      (fields (field (name "MPN") "1N4007"))
      (libsource (lib "eagle-import") (part "DIODE-GEN-PURPOSE-1KV-1A(DO-214AC)"))
    )
    (comp (ref "D34")
      (value "1N4007.")
      (footprint "eagle-import:DO-214AC")
      (fields (field (name "MPN") "1N4007"))
      (libsource (lib "eagle-import") (part "DIODE-GEN-PURPOSE-1KV-1A(DO-214AC)"))
    )
    (comp (ref "D35")
      (value "1N5817")
      (footprint "eagle-import:DO-214AC_SLIM")
      (libsource (lib "eagle-import") (part "DIODE-GEN-PURPOSE-1KV-1A(DO-214AC)DO-214AC/1206"))
    )
    (comp (ref "D36")
      (value "1N5817.")
      (footprint "eagle-import:DO-214AC_SLIM")
      (libsource (lib "eagle-import") (part "DIODE-GEN-PURPOSE-1KV-1A(DO-214AC)DO-214AC/1206"))
    )
    (comp (ref "D37")
      (value "1N5817.")
      (footprint "eagle-import:DO-214AC_SLIM")
      (libsource (lib "eagle-import") (part "DIODE-GEN-PURPOSE-1KV-1A(DO-214AC)DO-214AC/1206"))
    )
    (comp (ref "D38")
      (value "1N5817")
      (footprint "eagle-import:DO-214AC_SLIM")
      (libsource (lib "eagle-import") (part "DIODE-GEN-PURPOSE-1KV-1A(DO-214AC)DO-214AC/1206"))
    )
    (comp (ref "D39")
      (value "1N4007.")
      (footprint "eagle-import:DO-214AC")
      (fields (field (name "MPN") "1N4007"))
      (libsource (lib "eagle-import") (part "DIODE-GEN-PURPOSE-1KV-1A(DO-214AC)"))
    )
    (comp (ref "D40")
      (value "1N4007")
      (footprint "eagle-import:DO-214AC")
      (libsource (lib "eagle-import") (part "DIODE-GEN-PURPOSE-1KV-1A(DO-214AC)"))
    )
    (comp (ref "D41")
      (value "Zen15")
      (footprint "eagle-import:DO214AA")
      (libsource (lib "eagle-import") (part "SM6T"))
    )
    (comp (ref "D42")
      (value "SM6TDO214AA_BI")
      (footprint "eagle-import:DO214AA_BI")
      (libsource (lib "eagle-import") (part "SM6TDO214AA_BI"))
    )
    (comp (ref "D43")
      (value "1N5817")
      (footprint "eagle-import:DO-214AC_SLIM")
      (libsource (lib "eagle-import") (part "DIODE-GEN-PURPOSE-1KV-1A(DO-214AC)DO-214AC/1206"))
    )
    (comp (ref "D44")
      (value "1N5817.")
      (footprint "eagle-import:DO-214AC_SLIM")
      (libsource (lib "eagle-import") (part "DIODE-GEN-PURPOSE-1KV-1A(DO-214AC)DO-214AC/1206"))
    )
    (comp (ref "D45")
      (value "Zen11")
      (footprint "eagle-import:SOD-123_MINI-SMA")
      (libsource (lib "eagle-import") (part "CGRM400-G1"))
    )
    (comp (ref "FID11")
      (value "FIDUCIAL")
      (footprint "eagle-import:FIDUCIAL_1MM")
      (libsource (lib "eagle-import") (part "FIDUCIAL"))
    )
    (comp (ref "FID12")
      (value "FIDUCIAL")
      (footprint "eagle-import:FIDUCIAL_1MM")
      (libsource (lib "eagle-import") (part "FIDUCIAL"))
    )
    (comp (ref "FID13")
      (value "FIDUCIAL")
      (footprint "eagle-import:FIDUCIAL_1MM")
      (libsource (lib "eagle-import") (part "FIDUCIAL"))
    )
    (comp (ref "FID14")
      (value "FIDUCIAL")
      (footprint "eagle-import:FIDUCIAL_1MM")
      (libsource (lib "eagle-import") (part "FIDUCIAL"))
    )
    (comp (ref "IC19")
      (value "4028")
      (footprint "eagle-import:SO16")
      (libsource (lib "eagle-import") (part "4028D"))
    )
    (comp (ref "IC20")
      (value "317TO202H_NOHOLE")
      (footprint "eagle-import:TO220H_NOHOLE")
      (libsource (lib "eagle-import") (part "317TO202H_NOHOLE"))
    )
    (comp (ref "IC21")
      (value "ULN2004")
      (footprint "eagle-import:SO16")
      (libsource (lib "eagle-import") (part "ULN2004AD"))
    )
    (comp (ref "IC22")
      (value "LM339")
      (footprint "eagle-import:SO14")
      (libsource (lib "eagle-import") (part "LM339D"))
    )
    (comp (ref "IC23")
      (value "78L06")
      (footprint "eagle-import:SOT89_ROUND")
      (libsource (lib "eagle-import") (part "78LXXSOT89_ROUND"))
    )
    (comp (ref "IC24")
      (value "555")
      (footprint "eagle-import:SO08")
      (libsource (lib "eagle-import") (part "555DNE"))
    )
    (comp (ref "IC25")
      (value "4538")
      (footprint "eagle-import:SO16")
      (libsource (lib "eagle-import") (part "4538D"))
    )
    (comp (ref "IC26")
      (value "78L10")
      (footprint "eagle-import:SOT89_ROUND")
      (libsource (lib "eagle-import") (part "78LXXSOT89_ROUND"))
    )
    (comp (ref "IC27")
      (value "LM2904")
      (footprint "eagle-import:SO08")
      (libsource (lib "eagle-import") (part "LM358D"))
    )
    (comp (ref "JP11")
      (value "JP2EJP2_SMALLPADS")
      (footprint "eagle-import:JP2_SMALLPADS")
      (libsource (lib "eagle-import") (part "JP2EJP2_SMALLPADS"))
    )
    (comp (ref "JP12")
      (value "JP2E_ORIG")
      (footprint "eagle-import:JP2_ORIG_SMALLPADS")
      (libsource (lib "eagle-import") (part "JP2E_ORIG"))
    )
    (comp (ref "JP13")
      (value "JP2EJP2_SMALLPADS")
      (footprint "eagle-import:JP2_SMALLPADS")
      (libsource (lib "eagle-import") (part "JP2EJP2_SMALLPADS"))
    )
    (comp (ref "JP14")
      (value "JP2EJP2_SMALLPADS")
      (footprint "eagle-import:JP2_SMALLPADS")
      (libsource (lib "eagle-import") (part "JP2EJP2_SMALLPADS"))
    )
    (comp (ref "JP15")
      (value "JP2EJP2_SMALLPADS")
      (footprint "eagle-import:JP2_SMALLPADS")
      (libsource (lib "eagle-import") (part "JP2EJP2_SMALLPADS"))
    )
    (comp (ref "LED13")
      (value "LEDLD260")
      (footprint "eagle-import:LD260")
      (libsource (lib "eagle-import") (part "LEDLD260"))
    )
    (comp (ref "LED14")
      (value "LEDLD260")
      (footprint "eagle-import:LD260")
      (libsource (lib "eagle-import") (part "LEDLD260"))
    )
    (comp (ref "LED15")
      (value "LEDLD260")
      (footprint "eagle-import:LD260")
      (libsource (lib "eagle-import") (part "LEDLD260"))
    )
    (comp (ref "LED16")
      (value "LEDLD260")
      (footprint "eagle-import:LD260")
      (libsource (lib "eagle-import") (part "LEDLD260"))
    )
    (comp (ref "LED17")
      (value "LEDLD260")
      (footprint "eagle-import:LD260")
      (libsource (lib "eagle-import") (part "LEDLD260"))
    )
    (comp (ref "LED18")
      (value "LEDLD260")
      (footprint "eagle-import:LD260")
      (libsource (lib "eagle-import") (part "LEDLD260"))
    )
    (comp (ref "Q24")
      (value "BA")
      (footprint "eagle-import:SOT89")
      (libsource (lib "eagle-import") (part "PNP-TRANSISTOR_SOT89"))
    )
    (comp (ref "Q25")
      (value "BA.")
      (footprint "eagle-import:SOT89")
      (libsource (lib "eagle-import") (part "PNP-TRANSISTOR_SOT89"))
    )
    (comp (ref "Q26")
      (value "BA.")
      (footprint "eagle-import:SOT89")
      (libsource (lib "eagle-import") (part "PNP-TRANSISTOR_SOT89"))
    )
    (comp (ref "Q27")
      (value "BA")
      (footprint "eagle-import:SOT89")
      (libsource (lib "eagle-import") (part "PNP-TRANSISTOR_SOT89"))
    )
    (comp (ref "Q28")
      (value "MY")
      (footprint "eagle-import:SOT89")
      (libsource (lib "eagle-import") (part "NPN-TRANSISTOR_SOT89"))
    )
    (comp (ref "Q29")
      (value "J1")
      (footprint "eagle-import:SOT-23")
      (fields (field (name "MPN") "BSS138W-7-F"))
      (libsource (lib "eagle-import") (part "SMD-MOSFET-N-CH-50V-200MA-BSS138W-7-F(SOT-23)"))
    )
    (comp (ref "Q30")
      (value "J1")
      (footprint "eagle-import:SOT-23")
      (fields (field (name "MPN") "BSS138W-7-F"))
      (libsource (lib "eagle-import") (part "SMD-MOSFET-N-CH-50V-200MA-BSS138W-7-F(SOT-23)"))
    )
    (comp (ref "Q31")
      (value "J1")
      (footprint "eagle-import:SOT-23")
      (fields (field (name "MPN") "BSS138W-7-F"))
      (libsource (lib "eagle-import") (part "SMD-MOSFET-N-CH-50V-200MA-BSS138W-7-F(SOT-23)"))
    )
    (comp (ref "Q32")
      (value "BA")
      (footprint "eagle-import:SOT89")
      (libsource (lib "eagle-import") (part "PNP-TRANSISTOR_SOT89"))
    )
    (comp (ref "Q33")
      (value "J1")
      (footprint "eagle-import:SOT-23")
      (fields (field (name "MPN") "BSS138W-7-F"))
      (libsource (lib "eagle-import") (part "SMD-MOSFET-N-CH-50V-200MA-BSS138W-7-F(SOT-23)"))
    )
    (comp (ref "R166")
      (value "47")
      (footprint "eagle-import:V235_17_1MM")
      (libsource (lib "eagle-import") (part "R-EU_V235/17_1MM"))
    )
    (comp (ref "R167")
      (value "13")
      (footprint "eagle-import:R1206")
      (fields (field (name "MPN") "RC1206JR-0713RL"))
      (libsource (lib "eagle-import") (part "SMD-RES-13R-5%-1/4W(1206)"))
    )
    (comp (ref "R168")
      (value "47")
      (footprint "eagle-import:V235_17_1MM")
      (libsource (lib "eagle-import") (part "R-EU_V235/17_1MM"))
    )
    (comp (ref "R169")
      (value "104")
      (footprint "eagle-import:R0805")
      (fields (field (name "MPN") "RC0805FR-0710KL"))
      (libsource (lib "eagle-import") (part "SMD-RES-10K-1%-1/8W(0805)"))
    )
    (comp (ref "R170")
      (value "104")
      (footprint "eagle-import:R0805")
      (fields (field (name "MPN") "RC0805FR-0710KL"))
      (libsource (lib "eagle-import") (part "SMD-RES-10K-1%-1/8W(0805)"))
    )
    (comp (ref "R171")
      (value "104")
      (footprint "eagle-import:R0805")
      (fields (field (name "MPN") "RC0805FR-0710KL"))
      (libsource (lib "eagle-import") (part "SMD-RES-10K-1%-1/8W(0805)"))
    )
    (comp (ref "R172")
      (value "4701")
      (footprint "eagle-import:R0805")
      (fields (field (name "MPN") "RC0805JR-074K7L"))
      (libsource (lib "eagle-import") (part "SMD-RES-4.7K-5%-1/8W(0805)"))
    )
    (comp (ref "R173")
      (value "1002")
      (footprint "eagle-import:R0805")
      (fields (field (name "MPN") "RC0805FR-0710KL"))
      (libsource (lib "eagle-import") (part "SMD-RES-10K-1%-1/8W(0805)"))
    )
    (comp (ref "R174")
      (value "1002")
      (footprint "eagle-import:R0805")
      (fields (field (name "MPN") "RC0805FR-0710KL"))
      (libsource (lib "eagle-import") (part "SMD-RES-10K-1%-1/8W(0805)"))
    )
    (comp (ref "R175")
      (value "1502")
      (footprint "eagle-import:R0805")
      (fields (field (name "MPN") "RC0805FR-0710KL"))
      (libsource (lib "eagle-import") (part "SMD-RES-10K-1%-1/8W(0805)"))
    )
    (comp (ref "R176")
      (value "104")
      (footprint "eagle-import:R0805")
      (fields (field (name "MPN") "RC0805FR-0710KL"))
      (libsource (lib "eagle-import") (part "SMD-RES-10K-1%-1/8W(0805)"))
    )
    (comp (ref "R177")
      (value "104")
      (footprint "eagle-import:R0805")
      (fields (field (name "MPN") "RC0805FR-0710KL"))
      (libsource (lib "eagle-import") (part "SMD-RES-10K-1%-1/8W(0805)"))
    )
    (comp (ref "R178")
      (value "1502")
      (footprint "eagle-import:R0805")
      (fields (field (name "MPN") "RC0805FR-0710KL"))
      (libsource (lib "eagle-import") (part "SMD-RES-10K-1%-1/8W(0805)"))
    )
    (comp (ref "R179")
      (value "1002")
      (footprint "eagle-import:R0805")
      (fields (field (name "MPN") "RC0805FR-0710KL"))
      (libsource (lib "eagle-import") (part "SMD-RES-10K-1%-1/8W(0805)"))
    )
    (comp (ref "R180")
      (value "2201")
      (footprint "eagle-import:R0805")
      (fields (field (name "MPN") "RC0805JR-072K2L"))
      (libsource (lib "eagle-import") (part "SMD-RES-2.2K-5%-1/8W(0805)"))
    )
    (comp (ref "R181")
      (value "1002")
      (footprint "eagle-import:R0805")
      (fields (field (name "MPN") "RC0805FR-0710KL"))
      (libsource (lib "eagle-import") (part "SMD-RES-10K-1%-1/8W(0805)"))
    )
    (comp (ref "R182")
      (value "4701")
      (footprint "eagle-import:R0805")
      (fields (field (name "MPN") "RC0805JR-074K7L"))
      (libsource (lib "eagle-import") (part "SMD-RES-4.7K-5%-1/8W(0805)"))
    )
    (comp (ref "R183")
      (value "2702")
      (footprint "eagle-import:R0805")
      (fields (field (name "MPN") "RC0805JR-074K7L"))
      (libsource (lib "eagle-import") (part "SMD-RES-4.7K-5%-1/8W(0805)"))
    )
    (comp (ref "R184")
      (value "102")
      (footprint "eagle-import:R0805")
      (fields (field (name "MPN") "RC0805JR-071KL"))
      (libsource (lib "eagle-import") (part "SMD-RES-1K-5%-1/8W(0805)"))
    )
    (comp (ref "R185")
      (value "R_user")
      (footprint "eagle-import:R0805")
      (libsource (lib "eagle-import") (part "R-EU_R0805"))
    )
    (comp (ref "R186")
      (value "102")
      (footprint "eagle-import:R0805")
      (fields (field (name "MPN") "RC0805JR-07220RL"))
      (libsource (lib "eagle-import") (part "SMD-RES-220R-5%-1/8W(0805)"))
    )
    (comp (ref "R187")
      (value "(101)")
      (footprint "eagle-import:R0805")
      (fields (field (name "MPN") "RC0805JR-07100RL"))
      (libsource (lib "eagle-import") (part "SMD-RES-100R-5%-1/8W(0805)"))
    )
    (comp (ref "R188")
      (value "(1000)")
      (footprint "eagle-import:R0805")
      (fields (field (name "MPN") "RC0805JR-07100RL"))
      (libsource (lib "eagle-import") (part "SMD-RES-100R-5%-1/8W(0805)"))
    )
    (comp (ref "R189")
      (value "102")
      (footprint "eagle-import:R0805")
      (fields (field (name "MPN") "RC0805JR-071KL"))
      (libsource (lib "eagle-import") (part "SMD-RES-1K-5%-1/8W(0805)"))
    )
    (comp (ref "R190")
      (value "13")
      (footprint "eagle-import:R1206")
      (fields (field (name "MPN") "RC1206JR-0713RL"))
      (libsource (lib "eagle-import") (part "SMD-RES-13R-5%-1/4W(1206)"))
    )
    (comp (ref "R191")
      (value "13")
      (footprint "eagle-import:R1206")
      (fields (field (name "MPN") "RC1206JR-0713RL"))
      (libsource (lib "eagle-import") (part "SMD-RES-13R-5%-1/4W(1206)"))
    )
    (comp (ref "R192")
      (value "2702")
      (footprint "eagle-import:R0805")
      (fields (field (name "MPN") "RC0805JR-074K7L"))
      (libsource (lib "eagle-import") (part "SMD-RES-4.7K-5%-1/8W(0805)"))
    )
    (comp (ref "R193")
      (value "4701")
      (footprint "eagle-import:R0805")
      (fields (field (name "MPN") "RC0805JR-074K7L"))
      (libsource (lib "eagle-import") (part "SMD-RES-4.7K-5%-1/8W(0805)"))
    )
    (comp (ref "R194")
      (value "100")
      (footprint "eagle-import:R0805")
      (fields (field (name "MPN") "RC0805JR-072K2L"))
      (libsource (lib "eagle-import") (part "SMD-RES-2.2K-5%-1/8W(0805)"))
    )
    (comp (ref "R195")
      (value "104")
      (footprint "eagle-import:R0805")
      (fields (field (name "MPN") "RC0805FR-0710KL"))
      (libsource (lib "eagle-import") (part "SMD-RES-10K-1%-1/8W(0805)"))
    )
    (comp (ref "R196")
      (value "104")
      (footprint "eagle-import:R0805")
      (fields (field (name "MPN") "RC0805FR-0710KL"))
      (libsource (lib "eagle-import") (part "SMD-RES-10K-1%-1/8W(0805)"))
    )
    (comp (ref "R197")
      (value "(1002)")
      (footprint "eagle-import:R0805")
      (fields (field (name "MPN") "RC0805FR-0710KL"))
      (libsource (lib "eagle-import") (part "SMD-RES-10K-1%-1/8W(0805)"))
    )
    (comp (ref "R198")
      (value "2702")
      (footprint "eagle-import:R0805")
      (fields (field (name "MPN") "RC0805FR-0710KL"))
      (libsource (lib "eagle-import") (part "SMD-RES-10K-1%-1/8W(0805)"))
    )
    (comp (ref "R199")
      (value "47")
      (footprint "eagle-import:V235_17_1MM")
      (libsource (lib "eagle-import") (part "R-EU_V235/17_1MM"))
    )
    (comp (ref "R200")
      (value "47")
      (footprint "eagle-import:V235_17_1MM")
      (libsource (lib "eagle-import") (part "R-EU_V235/17_1MM"))
    )
    (comp (ref "R201")
      (value "2702")
      (footprint "eagle-import:R0805")
      (fields (field (name "MPN") "RC0805JR-074K7L"))
      (libsource (lib "eagle-import") (part "SMD-RES-4.7K-5%-1/8W(0805)"))
    )
    (comp (ref "R202")
      (value "2201")
      (footprint "eagle-import:R0805")
      (fields (field (name "MPN") "RC0805JR-072K2L"))
      (libsource (lib "eagle-import") (part "SMD-RES-2.2K-5%-1/8W(0805)"))
    )
    (comp (ref "R203")
      (value "1002")
      (footprint "eagle-import:R0805")
      (fields (field (name "MPN") "RC0805JR-074K7L"))
      (libsource (lib "eagle-import") (part "SMD-RES-4.7K-5%-1/8W(0805)"))
    )
    (comp (ref "R204")
      (value "1002")
      (footprint "eagle-import:R0805")
      (fields (field (name "MPN") "RC0805FR-0710KL"))
      (libsource (lib "eagle-import") (part "SMD-RES-10K-1%-1/8W(0805)"))
    )
    (comp (ref "R205")
      (value "102")
      (footprint "eagle-import:R0805")
      (fields (field (name "MPN") "RC0805JR-071KL"))
      (libsource (lib "eagle-import") (part "SMD-RES-1K-5%-1/8W(0805)"))
    )
    (comp (ref "R206")
      (value "2702")
      (footprint "eagle-import:R0805")
      (fields (field (name "MPN") "RC0805JR-074K7L"))
      (libsource (lib "eagle-import") (part "SMD-RES-4.7K-5%-1/8W(0805)"))
    )
    (comp (ref "R207")
      (value "1002")
      (footprint "eagle-import:R0805")
      (fields (field (name "MPN") "RC0805JR-071KL"))
      (libsource (lib "eagle-import") (part "SMD-RES-1K-5%-1/8W(0805)"))
    )
    (comp (ref "R208")
      (value "1002")
      (footprint "eagle-import:R0805")
      (fields (field (name "MPN") "RC0805JR-071KL"))
      (libsource (lib "eagle-import") (part "SMD-RES-1K-5%-1/8W(0805)"))
    )
    (comp (ref "R209")
      (value "R_user")
      (footprint "eagle-import:R0805")
      (libsource (lib "eagle-import") (part "R-EU_R0805"))
    )
    (comp (ref "R210")
      (value "104")
      (footprint "eagle-import:R0805")
      (fields (field (name "MPN") "RC0805FR-0710KL"))
      (libsource (lib "eagle-import") (part "SMD-RES-10K-1%-1/8W(0805)"))
    )
    (comp (ref "R211")
      (value "104")
      (footprint "eagle-import:R0805")
      (fields (field (name "MPN") "RC0805FR-0710KL"))
      (libsource (lib "eagle-import") (part "SMD-RES-10K-1%-1/8W(0805)"))
    )
    (comp (ref "R212")
      (value "104")
      (footprint "eagle-import:R0805")
      (fields (field (name "MPN") "RC0805FR-0710KL"))
      (libsource (lib "eagle-import") (part "SMD-RES-10K-1%-1/8W(0805)"))
    )
    (comp (ref "R213")
      (value "13")
      (footprint "eagle-import:R1206")
      (fields (field (name "MPN") "RC1206JR-0713RL"))
      (libsource (lib "eagle-import") (part "SMD-RES-13R-5%-1/4W(1206)"))
    )
    (comp (ref "R214")
      (value "2201")
      (footprint "eagle-import:R0805")
      (fields (field (name "MPN") "RC0805JR-071KL"))
      (libsource (lib "eagle-import") (part "SMD-RES-1K-5%-1/8W(0805)"))
    )
    (comp (ref "R215")
      (value "100")
      (footprint "eagle-import:R0805")
      (fields (field (name "MPN") "RC0805JR-07220RL"))
      (libsource (lib "eagle-import") (part "SMD-RES-220R-5%-1/8W(0805)"))
    )
    (comp (ref "R216")
      (value "13")
      (footprint "eagle-import:R1206")
      (fields (field (name "MPN") "RC1206JR-0713RL"))
      (libsource (lib "eagle-import") (part "SMD-RES-13R-5%-1/4W(1206)"))
    )
    (comp (ref "R217")
      (value "4701")
      (footprint "eagle-import:R0805")
      (fields (field (name "MPN") "RC0805JR-074K7L"))
      (libsource (lib "eagle-import") (part "SMD-RES-4.7K-5%-1/8W(0805)"))
    )
    (comp (ref "R218")
      (value "104")
      (footprint "eagle-import:R0805")
      (fields (field (name "MPN") "RC0805JR-074K7L"))
      (libsource (lib "eagle-import") (part "SMD-RES-4.7K-5%-1/8W(0805)"))
    )
    (comp (ref "R219")
      (value "100")
      (footprint "eagle-import:R0805")
      (fields (field (name "MPN") "RC0805JR-072K2L"))
      (libsource (lib "eagle-import") (part "SMD-RES-2.2K-5%-1/8W(0805)"))
    )
    (comp (ref "R220")
      (value "100")
      (footprint "eagle-import:R0805")
      (fields (field (name "MPN") "RC0805JR-072K2L"))
      (libsource (lib "eagle-import") (part "SMD-RES-2.2K-5%-1/8W(0805)"))
    )
    (comp (ref "SJ3")
      (value "SJ")
      (footprint "eagle-import:SJ")
      (libsource (lib "eagle-import") (part "solder-jumper_SJ"))
    )
    (comp (ref "SJMP3")
      (value "SJ")
      (footprint "eagle-import:SJ")
      (libsource (lib "eagle-import") (part "SJ"))
    )
    (comp (ref "START3")
      (value "TPSB2.0")
      (footprint "eagle-import:B2.0")
      (libsource (lib "eagle-import") (part "TPSB2.0"))
    )
    (comp (ref "TP70")
      (value "TPSB2.0")
      (footprint "eagle-import:B2.0")
      (libsource (lib "eagle-import") (part "TPSB2.0"))
    )
    (comp (ref "TP71")
      (value "TPSB2.0")
      (footprint "eagle-import:B2.0")
      (libsource (lib "eagle-import") (part "TPSB2.0"))
    )
    (comp (ref "TP72")
      (value "TPSB2.0")
      (footprint "eagle-import:B2.0")
      (libsource (lib "eagle-import") (part "TPSB2.0"))
    )
    (comp (ref "TP73")
      (value "TPSB2.0")
      (footprint "eagle-import:B2.0")
      (libsource (lib "eagle-import") (part "TPSB2.0"))
    )
    (comp (ref "TP74")
      (value "TPSB2.0")
      (footprint "eagle-import:B2.0")
      (libsource (lib "eagle-import") (part "TPSB2.0"))
    )
    (comp (ref "TP75")
      (value "TPSB2.0")
      (footprint "eagle-import:B2.0")
      (libsource (lib "eagle-import") (part "TPSB2.0"))
    )
    (comp (ref "TP76")
      (value "TPSB2.0")
      (footprint "eagle-import:B2.0")
      (libsource (lib "eagle-import") (part "TPSB2.0"))
    )
    (comp (ref "TP77")
      (value "TPSB2.0")
      (footprint "eagle-import:B2.0")
      (libsource (lib "eagle-import") (part "TPSB2.0"))
    )
    (comp (ref "TP78")
      (value "TPSB2.0")
      (footprint "eagle-import:B2.0")
      (libsource (lib "eagle-import") (part "TPSB2.0"))
    )
    (comp (ref "TP79")
      (value "TPSB2.0")
      (footprint "eagle-import:B2.0")
      (libsource (lib "eagle-import") (part "TPSB2.0"))
    )
    (comp (ref "TP80")
      (value "TPSB2.0")
      (footprint "eagle-import:B2.0")
      (libsource (lib "eagle-import") (part "TPSB2.0"))
    )
    (comp (ref "TP81")
      (value "TPSB2.0")
      (footprint "eagle-import:B2.0")
      (libsource (lib "eagle-import") (part "TPSB2.0"))
    )
    (comp (ref "TP82")
      (value "TPSB2.0")
      (footprint "eagle-import:B2.0")
      (libsource (lib "eagle-import") (part "TPSB2.0"))
    )
    (comp (ref "TP83")
      (value "TPSB2.0")
      (footprint "eagle-import:B2.0")
      (libsource (lib "eagle-import") (part "TPSB2.0"))
    )
    (comp (ref "TP84")
      (value "TPSB2.0")
      (footprint "eagle-import:B2.0")
      (libsource (lib "eagle-import") (part "TPSB2.0"))
    )
    (comp (ref "TP85")
      (value "TPSB2.0")
      (footprint "eagle-import:B2.0")
      (libsource (lib "eagle-import") (part "TPSB2.0"))
    )
    (comp (ref "TP86")
      (value "TPSB2.0")
      (footprint "eagle-import:B2.0")
      (libsource (lib "eagle-import") (part "TPSB2.0"))
    )
    (comp (ref "TP87")
      (value "TPSB2.0")
      (footprint "eagle-import:B2.0")
      (libsource (lib "eagle-import") (part "TPSB2.0"))
    )
    (comp (ref "TP88")
      (value "TPSB1,27")
      (footprint "eagle-import:B1,27")
      (libsource (lib "eagle-import") (part "TPSB1,27"))
    )
    (comp (ref "TP89")
      (value "TPSB2.0")
      (footprint "eagle-import:B2.0")
      (libsource (lib "eagle-import") (part "TPSB2.0"))
    )
    (comp (ref "TP90")
      (value "TPSB2.0")
      (footprint "eagle-import:B2.0")
      (libsource (lib "eagle-import") (part "TPSB2.0"))
    )
    (comp (ref "TP91")
      (value "TPSB2.0")
      (footprint "eagle-import:B2.0")
      (libsource (lib "eagle-import") (part "TPSB2.0"))
    )
    (comp (ref "TP92")
      (value "TPSB2.0")
      (footprint "eagle-import:B2.0")
      (libsource (lib "eagle-import") (part "TPSB2.0"))
    )
    (comp (ref "X7")
      (value "CON_BMWV2")
      (footprint "eagle-import:24-PIN_V2")
      (libsource (lib "eagle-import") (part "CON_BMWV2"))
    )
    (comp (ref "X8")
      (value "22-23-2051")
      (footprint "eagle-import:22-23-2051")
      (fields (field (name "MF") "MOLEX"))
      (libsource (lib "eagle-import") (part "22-23-2051"))
    )
    (comp (ref "X9")
      (value "22-23-2021")
      (footprint "eagle-import:22-23-2021")
      (fields (field (name "MF") "MOLEX"))
      (libsource (lib "eagle-import") (part "22-23-2021"))
    )
    (comp (ref "6V4")
      (value "TPSB2.0")
      (footprint "eagle-import:B2.0")
      (libsource (lib "eagle-import") (part "TPSB2.0"))
    )
    (comp (ref "9")
      (value "2081-1132")
      (footprint "eagle-import:12-PIN")
      (libsource (lib "eagle-import") (part "2081-1132"))
    )
    (comp (ref "10")
      (value "2081-1132")
      (footprint "eagle-import:12-PIN")
      (libsource (lib "eagle-import") (part "2081-1132"))
    )
    (comp (ref "10V4")
      (value "TPSB2.0")
      (footprint "eagle-import:B2.0")
      (libsource (lib "eagle-import") (part "TPSB2.0"))
    )
    (comp (ref "C39")
      (value "100u")
      (footprint "eagle-import:C1206")
      (fields (field (name "MPN") "GRM31CR60J107ME39L"))
      (libsource (lib "eagle-import") (part "CERAMIC-100UF-6.3V-20%-X5R(1206)"))
    )
    (comp (ref "C40")
      (value "100u")
      (footprint "eagle-import:C1206")
      (fields (field (name "MPN") "GRM31CR60J107ME39L"))
      (libsource (lib "eagle-import") (part "CERAMIC-100UF-6.3V-20%-X5R(1206)"))
    )
    (comp (ref "C41")
      (value "100nF,")
      (footprint "eagle-import:C0805")
      (fields (field (name "MPN") "CC0805KRX7R9BB104"))
      (libsource (lib "eagle-import") (part "CERAMIC-100NF-50V-10%-X7R(0805)"))
    )
    (comp (ref "C42")
      (value "4.7u")
      (footprint "eagle-import:C0805")
      (fields (field (name "MPN") "CC0805KKX5R8BB475"))
      (libsource (lib "eagle-import") (part "CERAMIC-4.7UF-25V-10%-X5R(0805)"))
    )
    (comp (ref "C43")
      (value "100nF.")
      (footprint "eagle-import:C0805")
      (fields (field (name "MPN") "CC0805KRX7R9BB104"))
      (libsource (lib "eagle-import") (part "CERAMIC-100NF-50V-10%-X7R(0805)"))
    )
    (comp (ref "C44")
      (value "100nF.")
      (footprint "eagle-import:C0805")
      (fields (field (name "MPN") "CC0805KRX7R9BB104"))
      (libsource (lib "eagle-import") (part "CERAMIC-100NF-50V-10%-X7R(0805)"))
    )
    (comp (ref "C45")
      (value "2.2nF")
      (footprint "eagle-import:C0805")
      (fields (field (name "MPN") "CC0805KRX7R9BB104"))
      (libsource (lib "eagle-import") (part "CERAMIC-100NF-50V-10%-X7R(0805)"))
    )
    (comp (ref "C46")
      (value "100nF")
      (footprint "eagle-import:C0805")
      (fields (field (name "MPN") "CC0805KRX7R9BB104"))
      (libsource (lib "eagle-import") (part "CERAMIC-100NF-50V-10%-X7R(0805)"))
    )
    (comp (ref "C47")
      (value "100nF")
      (footprint "eagle-import:C0805")
      (fields (field (name "MPN") "CC0805KRX7R9BB104"))
      (libsource (lib "eagle-import") (part "CERAMIC-100NF-50V-10%-X7R(0805)"))
    )
    (comp (ref "C48")
      (value "100nF,")
      (footprint "eagle-import:C0805")
      (fields (field (name "MPN") "CC0805KRX7R9BB104"))
      (libsource (lib "eagle-import") (part "CERAMIC-100NF-50V-10%-X7R(0805)"))
    )
    (comp (ref "C49")
      (value "4.7u")
      (footprint "eagle-import:C0805")
      (fields (field (name "MPN") "CC0805KKX5R8BB475"))
      (libsource (lib "eagle-import") (part "CERAMIC-4.7UF-25V-10%-X5R(0805)"))
    )
    (comp (ref "C50")
      (value "10u")
      (footprint "eagle-import:C1206")
      (fields (field (name "MPN") "GRM31CR60J107ME39L"))
      (libsource (lib "eagle-import") (part "CERAMIC-100UF-6.3V-20%-X5R(1206)"))
    )
    (comp (ref "D46")
      (value "1N4007,")
      (footprint "eagle-import:DO-214AC")
      (fields (field (name "MPN") "1N4007"))
      (libsource (lib "eagle-import") (part "DIODE-GEN-PURPOSE-1KV-1A(DO-214AC)"))
    )
    (comp (ref "D47")
      (value "1N4007,")
      (footprint "eagle-import:DO-214AC")
      (fields (field (name "MPN") "1N4007"))
      (libsource (lib "eagle-import") (part "DIODE-GEN-PURPOSE-1KV-1A(DO-214AC)"))
    )
    (comp (ref "D48")
      (value "1N4007.")
      (footprint "eagle-import:DO-214AC")
      (fields (field (name "MPN") "1N4007"))
      (libsource (lib "eagle-import") (part "DIODE-GEN-PURPOSE-1KV-1A(DO-214AC)"))
    )
    (comp (ref "D49")
      (value "1N5817")
      (footprint "eagle-import:DO-214AC_SLIM")
      (libsource (lib "eagle-import") (part "DIODE-GEN-PURPOSE-1KV-1A(DO-214AC)DO-214AC/1206"))
    )
    (comp (ref "D50")
      (value "1N5817.")
      (footprint "eagle-import:DO-214AC_SLIM")
      (libsource (lib "eagle-import") (part "DIODE-GEN-PURPOSE-1KV-1A(DO-214AC)DO-214AC/1206"))
    )
    (comp (ref "D51")
      (value "1N5817.")
      (footprint "eagle-import:DO-214AC_SLIM")
      (libsource (lib "eagle-import") (part "DIODE-GEN-PURPOSE-1KV-1A(DO-214AC)DO-214AC/1206"))
    )
    (comp (ref "D52")
      (value "1N5817")
      (footprint "eagle-import:DO-214AC_SLIM")
      (libsource (lib "eagle-import") (part "DIODE-GEN-PURPOSE-1KV-1A(DO-214AC)DO-214AC/1206"))
    )
    (comp (ref "D53")
      (value "1N4007.")
      (footprint "eagle-import:DO-214AC")
      (fields (field (name "MPN") "1N4007"))
      (libsource (lib "eagle-import") (part "DIODE-GEN-PURPOSE-1KV-1A(DO-214AC)"))
    )
    (comp (ref "D54")
      (value "1N4007")
      (footprint "eagle-import:DO-214AC")
      (libsource (lib "eagle-import") (part "DIODE-GEN-PURPOSE-1KV-1A(DO-214AC)"))
    )
    (comp (ref "D55")
      (value "Zen15")
      (footprint "eagle-import:DO214AA")
      (libsource (lib "eagle-import") (part "SM6T"))
    )
    (comp (ref "D56")
      (value "SM6TDO214AA_BI")
      (footprint "eagle-import:DO214AA_BI")
      (libsource (lib "eagle-import") (part "SM6TDO214AA_BI"))
    )
    (comp (ref "D57")
      (value "1N5817")
      (footprint "eagle-import:DO-214AC_SLIM")
      (libsource (lib "eagle-import") (part "DIODE-GEN-PURPOSE-1KV-1A(DO-214AC)DO-214AC/1206"))
    )
    (comp (ref "D58")
      (value "1N5817.")
      (footprint "eagle-import:DO-214AC_SLIM")
      (libsource (lib "eagle-import") (part "DIODE-GEN-PURPOSE-1KV-1A(DO-214AC)DO-214AC/1206"))
    )
    (comp (ref "D59")
      (value "Zen11")
      (footprint "eagle-import:SOD-123_MINI-SMA")
      (libsource (lib "eagle-import") (part "CGRM400-G1"))
    )
    (comp (ref "FID15")
      (value "FIDUCIAL")
      (footprint "eagle-import:FIDUCIAL_1MM")
      (libsource (lib "eagle-import") (part "FIDUCIAL"))
    )
    (comp (ref "FID16")
      (value "FIDUCIAL")
      (footprint "eagle-import:FIDUCIAL_1MM")
      (libsource (lib "eagle-import") (part "FIDUCIAL"))
    )
    (comp (ref "FID17")
      (value "FIDUCIAL")
      (footprint "eagle-import:FIDUCIAL_1MM")
      (libsource (lib "eagle-import") (part "FIDUCIAL"))
    )
    (comp (ref "FID18")
      (value "FIDUCIAL")
      (footprint "eagle-import:FIDUCIAL_1MM")
      (libsource (lib "eagle-import") (part "FIDUCIAL"))
    )
    (comp (ref "IC28")
      (value "4028")
      (footprint "eagle-import:SO16")
      (libsource (lib "eagle-import") (part "4028D"))
    )
    (comp (ref "IC29")
      (value "317TO202H_NOHOLE")
      (footprint "eagle-import:TO220H_NOHOLE")
      (libsource (lib "eagle-import") (part "317TO202H_NOHOLE"))
    )
    (comp (ref "IC30")
      (value "ULN2004")
      (footprint "eagle-import:SO16")
      (libsource (lib "eagle-import") (part "ULN2004AD"))
    )
    (comp (ref "IC31")
      (value "LM339")
      (footprint "eagle-import:SO14")
      (libsource (lib "eagle-import") (part "LM339D"))
    )
    (comp (ref "IC32")
      (value "78L06")
      (footprint "eagle-import:SOT89_ROUND")
      (libsource (lib "eagle-import") (part "78LXXSOT89_ROUND"))
    )
    (comp (ref "IC33")
      (value "555")
      (footprint "eagle-import:SO08")
      (libsource (lib "eagle-import") (part "555DNE"))
    )
    (comp (ref "IC34")
      (value "4538")
      (footprint "eagle-import:SO16")
      (libsource (lib "eagle-import") (part "4538D"))
    )
    (comp (ref "IC35")
      (value "78L10")
      (footprint "eagle-import:SOT89_ROUND")
      (libsource (lib "eagle-import") (part "78LXXSOT89_ROUND"))
    )
    (comp (ref "IC36")
      (value "LM2904")
      (footprint "eagle-import:SO08")
      (libsource (lib "eagle-import") (part "LM358D"))
    )
    (comp (ref "JP16")
      (value "JP2EJP2_SMALLPADS")
      (footprint "eagle-import:JP2_SMALLPADS")
      (libsource (lib "eagle-import") (part "JP2EJP2_SMALLPADS"))
    )
    (comp (ref "JP17")
      (value "JP2E_ORIG")
      (footprint "eagle-import:JP2_ORIG_SMALLPADS")
      (libsource (lib "eagle-import") (part "JP2E_ORIG"))
    )
    (comp (ref "JP18")
      (value "JP2EJP2_SMALLPADS")
      (footprint "eagle-import:JP2_SMALLPADS")
      (libsource (lib "eagle-import") (part "JP2EJP2_SMALLPADS"))
    )
    (comp (ref "JP19")
      (value "JP2EJP2_SMALLPADS")
      (footprint "eagle-import:JP2_SMALLPADS")
      (libsource (lib "eagle-import") (part "JP2EJP2_SMALLPADS"))
    )
    (comp (ref "JP20")
      (value "JP2EJP2_SMALLPADS")
      (footprint "eagle-import:JP2_SMALLPADS")
      (libsource (lib "eagle-import") (part "JP2EJP2_SMALLPADS"))
    )
    (comp (ref "LED19")
      (value "LEDLD260")
      (footprint "eagle-import:LD260")
      (libsource (lib "eagle-import") (part "LEDLD260"))
    )
    (comp (ref "LED20")
      (value "LEDLD260")
      (footprint "eagle-import:LD260")
      (libsource (lib "eagle-import") (part "LEDLD260"))
    )
    (comp (ref "LED21")
      (value "LEDLD260")
      (footprint "eagle-import:LD260")
      (libsource (lib "eagle-import") (part "LEDLD260"))
    )
    (comp (ref "LED22")
      (value "LEDLD260")
      (footprint "eagle-import:LD260")
      (libsource (lib "eagle-import") (part "LEDLD260"))
    )
    (comp (ref "LED23")
      (value "LEDLD260")
      (footprint "eagle-import:LD260")
      (libsource (lib "eagle-import") (part "LEDLD260"))
    )
    (comp (ref "LED24")
      (value "LEDLD260")
      (footprint "eagle-import:LD260")
      (libsource (lib "eagle-import") (part "LEDLD260"))
    )
    (comp (ref "Q34")
      (value "BA")
      (footprint "eagle-import:SOT89")
      (libsource (lib "eagle-import") (part "PNP-TRANSISTOR_SOT89"))
    )
    (comp (ref "Q35")
      (value "BA.")
      (footprint "eagle-import:SOT89")
      (libsource (lib "eagle-import") (part "PNP-TRANSISTOR_SOT89"))
    )
    (comp (ref "Q36")
      (value "BA.")
      (footprint "eagle-import:SOT89")
      (libsource (lib "eagle-import") (part "PNP-TRANSISTOR_SOT89"))
    )
    (comp (ref "Q37")
      (value "BA")
      (footprint "eagle-import:SOT89")
      (libsource (lib "eagle-import") (part "PNP-TRANSISTOR_SOT89"))
    )
    (comp (ref "Q38")
      (value "MY")
      (footprint "eagle-import:SOT89")
      (libsource (lib "eagle-import") (part "NPN-TRANSISTOR_SOT89"))
    )
    (comp (ref "Q39")
      (value "J1")
      (footprint "eagle-import:SOT-23")
      (fields (field (name "MPN") "BSS138W-7-F"))
      (libsource (lib "eagle-import") (part "SMD-MOSFET-N-CH-50V-200MA-BSS138W-7-F(SOT-23)"))
    )
    (comp (ref "Q40")
      (value "J1")
      (footprint "eagle-import:SOT-23")
      (fields (field (name "MPN") "BSS138W-7-F"))
      (libsource (lib "eagle-import") (part "SMD-MOSFET-N-CH-50V-200MA-BSS138W-7-F(SOT-23)"))
    )
    (comp (ref "Q41")
      (value "J1")
      (footprint "eagle-import:SOT-23")
      (fields (field (name "MPN") "BSS138W-7-F"))
      (libsource (lib "eagle-import") (part "SMD-MOSFET-N-CH-50V-200MA-BSS138W-7-F(SOT-23)"))
    )
    (comp (ref "Q42")
      (value "BA")
      (footprint "eagle-import:SOT89")
      (libsource (lib "eagle-import") (part "PNP-TRANSISTOR_SOT89"))
    )
    (comp (ref "Q43")
      (value "J1")
      (footprint "eagle-import:SOT-23")
      (fields (field (name "MPN") "BSS138W-7-F"))
      (libsource (lib "eagle-import") (part "SMD-MOSFET-N-CH-50V-200MA-BSS138W-7-F(SOT-23)"))
    )
    (comp (ref "R221")
      (value "47")
      (footprint "eagle-import:V235_17_1MM")
      (libsource (lib "eagle-import") (part "R-EU_V235/17_1MM"))
    )
    (comp (ref "R222")
      (value "13")
      (footprint "eagle-import:R1206")
      (fields (field (name "MPN") "RC1206JR-0713RL"))
      (libsource (lib "eagle-import") (part "SMD-RES-13R-5%-1/4W(1206)"))
    )
    (comp (ref "R223")
      (value "47")
      (footprint "eagle-import:V235_17_1MM")
      (libsource (lib "eagle-import") (part "R-EU_V235/17_1MM"))
    )
    (comp (ref "R224")
      (value "104")
      (footprint "eagle-import:R0805")
      (fields (field (name "MPN") "RC0805FR-0710KL"))
      (libsource (lib "eagle-import") (part "SMD-RES-10K-1%-1/8W(0805)"))
    )
    (comp (ref "R225")
      (value "104")
      (footprint "eagle-import:R0805")
      (fields (field (name "MPN") "RC0805FR-0710KL"))
      (libsource (lib "eagle-import") (part "SMD-RES-10K-1%-1/8W(0805)"))
    )
    (comp (ref "R226")
      (value "104")
      (footprint "eagle-import:R0805")
      (fields (field (name "MPN") "RC0805FR-0710KL"))
      (libsource (lib "eagle-import") (part "SMD-RES-10K-1%-1/8W(0805)"))
    )
    (comp (ref "R227")
      (value "4701")
      (footprint "eagle-import:R0805")
      (fields (field (name "MPN") "RC0805JR-074K7L"))
      (libsource (lib "eagle-import") (part "SMD-RES-4.7K-5%-1/8W(0805)"))
    )
    (comp (ref "R228")
      (value "1002")
      (footprint "eagle-import:R0805")
      (fields (field (name "MPN") "RC0805FR-0710KL"))
      (libsource (lib "eagle-import") (part "SMD-RES-10K-1%-1/8W(0805)"))
    )
    (comp (ref "R229")
      (value "1002")
      (footprint "eagle-import:R0805")
      (fields (field (name "MPN") "RC0805FR-0710KL"))
      (libsource (lib "eagle-import") (part "SMD-RES-10K-1%-1/8W(0805)"))
    )
    (comp (ref "R230")
      (value "1502")
      (footprint "eagle-import:R0805")
      (fields (field (name "MPN") "RC0805FR-0710KL"))
      (libsource (lib "eagle-import") (part "SMD-RES-10K-1%-1/8W(0805)"))
    )
    (comp (ref "R231")
      (value "104")
      (footprint "eagle-import:R0805")
      (fields (field (name "MPN") "RC0805FR-0710KL"))
      (libsource (lib "eagle-import") (part "SMD-RES-10K-1%-1/8W(0805)"))
    )
    (comp (ref "R232")
      (value "104")
      (footprint "eagle-import:R0805")
      (fields (field (name "MPN") "RC0805FR-0710KL"))
      (libsource (lib "eagle-import") (part "SMD-RES-10K-1%-1/8W(0805)"))
    )
    (comp (ref "R233")
      (value "1502")
      (footprint "eagle-import:R0805")
      (fields (field (name "MPN") "RC0805FR-0710KL"))
      (libsource (lib "eagle-import") (part "SMD-RES-10K-1%-1/8W(0805)"))
    )
    (comp (ref "R234")
      (value "1002")
      (footprint "eagle-import:R0805")
      (fields (field (name "MPN") "RC0805FR-0710KL"))
      (libsource (lib "eagle-import") (part "SMD-RES-10K-1%-1/8W(0805)"))
    )
    (comp (ref "R235")
      (value "2201")
      (footprint "eagle-import:R0805")
      (fields (field (name "MPN") "RC0805JR-072K2L"))
      (libsource (lib "eagle-import") (part "SMD-RES-2.2K-5%-1/8W(0805)"))
    )
    (comp (ref "R236")
      (value "1002")
      (footprint "eagle-import:R0805")
      (fields (field (name "MPN") "RC0805FR-0710KL"))
      (libsource (lib "eagle-import") (part "SMD-RES-10K-1%-1/8W(0805)"))
    )
    (comp (ref "R237")
      (value "4701")
      (footprint "eagle-import:R0805")
      (fields (field (name "MPN") "RC0805JR-074K7L"))
      (libsource (lib "eagle-import") (part "SMD-RES-4.7K-5%-1/8W(0805)"))
    )
    (comp (ref "R238")
      (value "2702")
      (footprint "eagle-import:R0805")
      (fields (field (name "MPN") "RC0805JR-074K7L"))
      (libsource (lib "eagle-import") (part "SMD-RES-4.7K-5%-1/8W(0805)"))
    )
    (comp (ref "R239")
      (value "102")
      (footprint "eagle-import:R0805")
      (fields (field (name "MPN") "RC0805JR-071KL"))
      (libsource (lib "eagle-import") (part "SMD-RES-1K-5%-1/8W(0805)"))
    )
    (comp (ref "R240")
      (value "R_user")
      (footprint "eagle-import:R0805")
      (libsource (lib "eagle-import") (part "R-EU_R0805"))
    )
    (comp (ref "R241")
      (value "102")
      (footprint "eagle-import:R0805")
      (fields (field (name "MPN") "RC0805JR-07220RL"))
      (libsource (lib "eagle-import") (part "SMD-RES-220R-5%-1/8W(0805)"))
    )
    (comp (ref "R242")
      (value "(101)")
      (footprint "eagle-import:R0805")
      (fields (field (name "MPN") "RC0805JR-07100RL"))
      (libsource (lib "eagle-import") (part "SMD-RES-100R-5%-1/8W(0805)"))
    )
    (comp (ref "R243")
      (value "(1000)")
      (footprint "eagle-import:R0805")
      (fields (field (name "MPN") "RC0805JR-07100RL"))
      (libsource (lib "eagle-import") (part "SMD-RES-100R-5%-1/8W(0805)"))
    )
    (comp (ref "R244")
      (value "102")
      (footprint "eagle-import:R0805")
      (fields (field (name "MPN") "RC0805JR-071KL"))
      (libsource (lib "eagle-import") (part "SMD-RES-1K-5%-1/8W(0805)"))
    )
    (comp (ref "R245")
      (value "13")
      (footprint "eagle-import:R1206")
      (fields (field (name "MPN") "RC1206JR-0713RL"))
      (libsource (lib "eagle-import") (part "SMD-RES-13R-5%-1/4W(1206)"))
    )
    (comp (ref "R246")
      (value "13")
      (footprint "eagle-import:R1206")
      (fields (field (name "MPN") "RC1206JR-0713RL"))
      (libsource (lib "eagle-import") (part "SMD-RES-13R-5%-1/4W(1206)"))
    )
    (comp (ref "R247")
      (value "2702")
      (footprint "eagle-import:R0805")
      (fields (field (name "MPN") "RC0805JR-074K7L"))
      (libsource (lib "eagle-import") (part "SMD-RES-4.7K-5%-1/8W(0805)"))
    )
    (comp (ref "R248")
      (value "4701")
      (footprint "eagle-import:R0805")
      (fields (field (name "MPN") "RC0805JR-074K7L"))
      (libsource (lib "eagle-import") (part "SMD-RES-4.7K-5%-1/8W(0805)"))
    )
    (comp (ref "R249")
      (value "100")
      (footprint "eagle-import:R0805")
      (fields (field (name "MPN") "RC0805JR-072K2L"))
      (libsource (lib "eagle-import") (part "SMD-RES-2.2K-5%-1/8W(0805)"))
    )
    (comp (ref "R250")
      (value "104")
      (footprint "eagle-import:R0805")
      (fields (field (name "MPN") "RC0805FR-0710KL"))
      (libsource (lib "eagle-import") (part "SMD-RES-10K-1%-1/8W(0805)"))
    )
    (comp (ref "R251")
      (value "104")
      (footprint "eagle-import:R0805")
      (fields (field (name "MPN") "RC0805FR-0710KL"))
      (libsource (lib "eagle-import") (part "SMD-RES-10K-1%-1/8W(0805)"))
    )
    (comp (ref "R252")
      (value "(1002)")
      (footprint "eagle-import:R0805")
      (fields (field (name "MPN") "RC0805FR-0710KL"))
      (libsource (lib "eagle-import") (part "SMD-RES-10K-1%-1/8W(0805)"))
    )
    (comp (ref "R253")
      (value "2702")
      (footprint "eagle-import:R0805")
      (fields (field (name "MPN") "RC0805FR-0710KL"))
      (libsource (lib "eagle-import") (part "SMD-RES-10K-1%-1/8W(0805)"))
    )
    (comp (ref "R254")
      (value "47")
      (footprint "eagle-import:V235_17_1MM")
      (libsource (lib "eagle-import") (part "R-EU_V235/17_1MM"))
    )
    (comp (ref "R255")
      (value "47")
      (footprint "eagle-import:V235_17_1MM")
      (libsource (lib "eagle-import") (part "R-EU_V235/17_1MM"))
    )
    (comp (ref "R256")
      (value "2702")
      (footprint "eagle-import:R0805")
      (fields (field (name "MPN") "RC0805JR-074K7L"))
      (libsource (lib "eagle-import") (part "SMD-RES-4.7K-5%-1/8W(0805)"))
    )
    (comp (ref "R257")
      (value "2201")
      (footprint "eagle-import:R0805")
      (fields (field (name "MPN") "RC0805JR-072K2L"))
      (libsource (lib "eagle-import") (part "SMD-RES-2.2K-5%-1/8W(0805)"))
    )
    (comp (ref "R258")
      (value "1002")
      (footprint "eagle-import:R0805")
      (fields (field (name "MPN") "RC0805JR-074K7L"))
      (libsource (lib "eagle-import") (part "SMD-RES-4.7K-5%-1/8W(0805)"))
    )
    (comp (ref "R259")
      (value "1002")
      (footprint "eagle-import:R0805")
      (fields (field (name "MPN") "RC0805FR-0710KL"))
      (libsource (lib "eagle-import") (part "SMD-RES-10K-1%-1/8W(0805)"))
    )
    (comp (ref "R260")
      (value "102")
      (footprint "eagle-import:R0805")
      (fields (field (name "MPN") "RC0805JR-071KL"))
      (libsource (lib "eagle-import") (part "SMD-RES-1K-5%-1/8W(0805)"))
    )
    (comp (ref "R261")
      (value "2702")
      (footprint "eagle-import:R0805")
      (fields (field (name "MPN") "RC0805JR-074K7L"))
      (libsource (lib "eagle-import") (part "SMD-RES-4.7K-5%-1/8W(0805)"))
    )
    (comp (ref "R262")
      (value "1002")
      (footprint "eagle-import:R0805")
      (fields (field (name "MPN") "RC0805JR-071KL"))
      (libsource (lib "eagle-import") (part "SMD-RES-1K-5%-1/8W(0805)"))
    )
    (comp (ref "R263")
      (value "1002")
      (footprint "eagle-import:R0805")
      (fields (field (name "MPN") "RC0805JR-071KL"))
      (libsource (lib "eagle-import") (part "SMD-RES-1K-5%-1/8W(0805)"))
    )
    (comp (ref "R264")
      (value "R_user")
      (footprint "eagle-import:R0805")
      (libsource (lib "eagle-import") (part "R-EU_R0805"))
    )
    (comp (ref "R265")
      (value "104")
      (footprint "eagle-import:R0805")
      (fields (field (name "MPN") "RC0805FR-0710KL"))
      (libsource (lib "eagle-import") (part "SMD-RES-10K-1%-1/8W(0805)"))
    )
    (comp (ref "R266")
      (value "104")
      (footprint "eagle-import:R0805")
      (fields (field (name "MPN") "RC0805FR-0710KL"))
      (libsource (lib "eagle-import") (part "SMD-RES-10K-1%-1/8W(0805)"))
    )
    (comp (ref "R267")
      (value "104")
      (footprint "eagle-import:R0805")
      (fields (field (name "MPN") "RC0805FR-0710KL"))
      (libsource (lib "eagle-import") (part "SMD-RES-10K-1%-1/8W(0805)"))
    )
    (comp (ref "R268")
      (value "13")
      (footprint "eagle-import:R1206")
      (fields (field (name "MPN") "RC1206JR-0713RL"))
      (libsource (lib "eagle-import") (part "SMD-RES-13R-5%-1/4W(1206)"))
    )
    (comp (ref "R269")
      (value "2201")
      (footprint "eagle-import:R0805")
      (fields (field (name "MPN") "RC0805JR-071KL"))
      (libsource (lib "eagle-import") (part "SMD-RES-1K-5%-1/8W(0805)"))
    )
    (comp (ref "R270")
      (value "100")
      (footprint "eagle-import:R0805")
      (fields (field (name "MPN") "RC0805JR-07220RL"))
      (libsource (lib "eagle-import") (part "SMD-RES-220R-5%-1/8W(0805)"))
    )
    (comp (ref "R271")
      (value "13")
      (footprint "eagle-import:R1206")
      (fields (field (name "MPN") "RC1206JR-0713RL"))
      (libsource (lib "eagle-import") (part "SMD-RES-13R-5%-1/4W(1206)"))
    )
    (comp (ref "R272")
      (value "4701")
      (footprint "eagle-import:R0805")
      (fields (field (name "MPN") "RC0805JR-074K7L"))
      (libsource (lib "eagle-import") (part "SMD-RES-4.7K-5%-1/8W(0805)"))
    )
    (comp (ref "R273")
      (value "104")
      (footprint "eagle-import:R0805")
      (fields (field (name "MPN") "RC0805JR-074K7L"))
      (libsource (lib "eagle-import") (part "SMD-RES-4.7K-5%-1/8W(0805)"))
    )
    (comp (ref "R274")
      (value "100")
      (footprint "eagle-import:R0805")
      (fields (field (name "MPN") "RC0805JR-072K2L"))
      (libsource (lib "eagle-import") (part "SMD-RES-2.2K-5%-1/8W(0805)"))
    )
    (comp (ref "R275")
      (value "100")
      (footprint "eagle-import:R0805")
      (fields (field (name "MPN") "RC0805JR-072K2L"))
      (libsource (lib "eagle-import") (part "SMD-RES-2.2K-5%-1/8W(0805)"))
    )
    (comp (ref "SJ4")
      (value "SJ")
      (footprint "eagle-import:SJ")
      (libsource (lib "eagle-import") (part "solder-jumper_SJ"))
    )
    (comp (ref "SJMP4")
      (value "SJ")
      (footprint "eagle-import:SJ")
      (libsource (lib "eagle-import") (part "SJ"))
    )
    (comp (ref "START4")
      (value "TPSB2.0")
      (footprint "eagle-import:B2.0")
      (libsource (lib "eagle-import") (part "TPSB2.0"))
    )
    (comp (ref "TP93")
      (value "TPSB2.0")
      (footprint "eagle-import:B2.0")
      (libsource (lib "eagle-import") (part "TPSB2.0"))
    )
    (comp (ref "TP94")
      (value "TPSB2.0")
      (footprint "eagle-import:B2.0")
      (libsource (lib "eagle-import") (part "TPSB2.0"))
    )
    (comp (ref "TP95")
      (value "TPSB2.0")
      (footprint "eagle-import:B2.0")
      (libsource (lib "eagle-import") (part "TPSB2.0"))
    )
    (comp (ref "TP96")
      (value "TPSB2.0")
      (footprint "eagle-import:B2.0")
      (libsource (lib "eagle-import") (part "TPSB2.0"))
    )
    (comp (ref "TP97")
      (value "TPSB2.0")
      (footprint "eagle-import:B2.0")
      (libsource (lib "eagle-import") (part "TPSB2.0"))
    )
    (comp (ref "TP98")
      (value "TPSB2.0")
      (footprint "eagle-import:B2.0")
      (libsource (lib "eagle-import") (part "TPSB2.0"))
    )
    (comp (ref "TP99")
      (value "TPSB2.0")
      (footprint "eagle-import:B2.0")
      (libsource (lib "eagle-import") (part "TPSB2.0"))
    )
    (comp (ref "TP100")
      (value "TPSB2.0")
      (footprint "eagle-import:B2.0")
      (libsource (lib "eagle-import") (part "TPSB2.0"))
    )
    (comp (ref "TP101")
      (value "TPSB2.0")
      (footprint "eagle-import:B2.0")
      (libsource (lib "eagle-import") (part "TPSB2.0"))
    )
    (comp (ref "TP102")
      (value "TPSB2.0")
      (footprint "eagle-import:B2.0")
      (libsource (lib "eagle-import") (part "TPSB2.0"))
    )
    (comp (ref "TP103")
      (value "TPSB2.0")
      (footprint "eagle-import:B2.0")
      (libsource (lib "eagle-import") (part "TPSB2.0"))
    )
    (comp (ref "TP104")
      (value "TPSB2.0")
      (footprint "eagle-import:B2.0")
      (libsource (lib "eagle-import") (part "TPSB2.0"))
    )
    (comp (ref "TP105")
      (value "TPSB2.0")
      (footprint "eagle-import:B2.0")
      (libsource (lib "eagle-import") (part "TPSB2.0"))
    )
    (comp (ref "TP106")
      (value "TPSB2.0")
      (footprint "eagle-import:B2.0")
      (libsource (lib "eagle-import") (part "TPSB2.0"))
    )
    (comp (ref "TP107")
      (value "TPSB2.0")
      (footprint "eagle-import:B2.0")
      (libsource (lib "eagle-import") (part "TPSB2.0"))
    )
    (comp (ref "TP108")
      (value "TPSB2.0")
      (footprint "eagle-import:B2.0")
      (libsource (lib "eagle-import") (part "TPSB2.0"))
    )
    (comp (ref "TP109")
      (value "TPSB2.0")
      (footprint "eagle-import:B2.0")
      (libsource (lib "eagle-import") (part "TPSB2.0"))
    )
    (comp (ref "TP110")
      (value "TPSB2.0")
      (footprint "eagle-import:B2.0")
      (libsource (lib "eagle-import") (part "TPSB2.0"))
    )
    (comp (ref "TP111")
      (value "TPSB1,27")
      (footprint "eagle-import:B1,27")
      (libsource (lib "eagle-import") (part "TPSB1,27"))
    )
    (comp (ref "TP112")
      (value "TPSB2.0")
      (footprint "eagle-import:B2.0")
      (libsource (lib "eagle-import") (part "TPSB2.0"))
    )
    (comp (ref "TP113")
      (value "TPSB2.0")
      (footprint "eagle-import:B2.0")
      (libsource (lib "eagle-import") (part "TPSB2.0"))
    )
    (comp (ref "TP114")
      (value "TPSB2.0")
      (footprint "eagle-import:B2.0")
      (libsource (lib "eagle-import") (part "TPSB2.0"))
    )
    (comp (ref "TP115")
      (value "TPSB2.0")
      (footprint "eagle-import:B2.0")
      (libsource (lib "eagle-import") (part "TPSB2.0"))
    )
    (comp (ref "X10")
      (value "CON_BMWV2")
      (footprint "eagle-import:24-PIN_V2")
      (libsource (lib "eagle-import") (part "CON_BMWV2"))
    )
    (comp (ref "X11")
      (value "22-23-2051")
      (footprint "eagle-import:22-23-2051")
      (fields (field (name "MF") "MOLEX"))
      (libsource (lib "eagle-import") (part "22-23-2051"))
    )
    (comp (ref "X12")
      (value "22-23-2021")
      (footprint "eagle-import:22-23-2021")
      (fields (field (name "MF") "MOLEX"))
      (libsource (lib "eagle-import") (part "22-23-2021"))
    )
  )
  (nets
    (net (code "1") (name "+10V") (class "Default")
      (node (ref "10V") (pin "TP") (pinfunction "PP_TP") (pintype "input"))
      (node (ref "10V1") (pin "TP") (pinfunction "PP_TP") (pintype "input"))
      (node (ref "10V2") (pin "TP") (pinfunction "PP_TP") (pintype "input"))
      (node (ref "10V3") (pin "TP") (pinfunction "PP_TP") (pintype "input"))
      (node (ref "10V4") (pin "TP") (pinfunction "PP_TP") (pintype "input"))
      (node (ref "10V5") (pin "TP") (pinfunction "PP_TP") (pintype "input"))
      (node (ref "C102") (pin "1") (pinfunction "1_1") (pintype "passive"))
      (node (ref "C22") (pin "1") (pinfunction "1_1") (pintype "passive"))
      (node (ref "C34") (pin "1") (pinfunction "1_1") (pintype "passive"))
      (node (ref "C46") (pin "1") (pinfunction "1_1") (pintype "passive"))
      (node (ref "C58") (pin "1") (pinfunction "1_1") (pintype "passive"))
      (node (ref "C9") (pin "1") (pinfunction "1_1") (pintype "passive"))
      (node (ref "IC104") (pin "1") (pinfunction "OUT_1") (pintype "passive"))
      (node (ref "IC110") (pin "4") (pinfunction "R_4") (pintype "input"))
      (node (ref "IC110") (pin "8") (pinfunction "V+_8") (pintype "power_in"))
      (node (ref "IC111") (pin "13") (pinfunction "CD_13") (pintype "input"))
      (node (ref "IC111") (pin "16") (pinfunction "VDD_16") (pintype "power_in"))
      (node (ref "IC111") (pin "3") (pinfunction "CD_3") (pintype "input"))
      (node (ref "IC111") (pin "5") (pinfunction "B_5") (pintype "input"))
      (node (ref "IC15") (pin "4") (pinfunction "R_4") (pintype "input"))
      (node (ref "IC15") (pin "8") (pinfunction "V+_8") (pintype "power_in"))
      (node (ref "IC16") (pin "13") (pinfunction "CD_13") (pintype "input"))
      (node (ref "IC16") (pin "16") (pinfunction "VDD_16") (pintype "power_in"))
      (node (ref "IC16") (pin "3") (pinfunction "CD_3") (pintype "input"))
      (node (ref "IC16") (pin "5") (pinfunction "B_5") (pintype "input"))
      (node (ref "IC17") (pin "1") (pinfunction "OUT_1") (pintype "passive"))
      (node (ref "IC24") (pin "4") (pinfunction "R_4") (pintype "input"))
      (node (ref "IC24") (pin "8") (pinfunction "V+_8") (pintype "power_in"))
      (node (ref "IC25") (pin "13") (pinfunction "CD_13") (pintype "input"))
      (node (ref "IC25") (pin "16") (pinfunction "VDD_16") (pintype "power_in"))
      (node (ref "IC25") (pin "3") (pinfunction "CD_3") (pintype "input"))
      (node (ref "IC25") (pin "5") (pinfunction "B_5") (pintype "input"))
      (node (ref "IC26") (pin "1") (pinfunction "OUT_1") (pintype "passive"))
      (node (ref "IC33") (pin "4") (pinfunction "R_4") (pintype "input"))
      (node (ref "IC33") (pin "8") (pinfunction "V+_8") (pintype "power_in"))
      (node (ref "IC34") (pin "13") (pinfunction "CD_13") (pintype "input"))
      (node (ref "IC34") (pin "16") (pinfunction "VDD_16") (pintype "power_in"))
      (node (ref "IC34") (pin "3") (pinfunction "CD_3") (pintype "input"))
      (node (ref "IC34") (pin "5") (pinfunction "B_5") (pintype "input"))
      (node (ref "IC35") (pin "1") (pinfunction "OUT_1") (pintype "passive"))
      (node (ref "IC42") (pin "4") (pinfunction "R_4") (pintype "input"))
      (node (ref "IC42") (pin "8") (pinfunction "V+_8") (pintype "power_in"))
      (node (ref "IC43") (pin "13") (pinfunction "CD_13") (pintype "input"))
      (node (ref "IC43") (pin "16") (pinfunction "VDD_16") (pintype "power_in"))
      (node (ref "IC43") (pin "3") (pinfunction "CD_3") (pintype "input"))
      (node (ref "IC43") (pin "5") (pinfunction "B_5") (pintype "input"))
      (node (ref "IC44") (pin "1") (pinfunction "OUT_1") (pintype "passive"))
      (node (ref "IC6") (pin "4") (pinfunction "R_4") (pintype "input"))
      (node (ref "IC6") (pin "8") (pinfunction "V+_8") (pintype "power_in"))
      (node (ref "IC7") (pin "13") (pinfunction "CD_13") (pintype "input"))
      (node (ref "IC7") (pin "16") (pinfunction "VDD_16") (pintype "power_in"))
      (node (ref "IC7") (pin "3") (pinfunction "CD_3") (pintype "input"))
      (node (ref "IC7") (pin "5") (pinfunction "B_5") (pintype "input"))
      (node (ref "IC8") (pin "1") (pinfunction "OUT_1") (pintype "passive"))
      (node (ref "R10") (pin "2") (pinfunction "2_2") (pintype "passive"))
      (node (ref "R139") (pin "2") (pinfunction "2_2") (pintype "passive"))
      (node (ref "R145") (pin "2") (pinfunction "2_2") (pintype "passive"))
      (node (ref "R163") (pin "2") (pinfunction "2_2") (pintype "passive"))
      (node (ref "R201") (pin "2") (pinfunction "2_2") (pintype "passive"))
      (node (ref "R218") (pin "2") (pinfunction "2_2") (pintype "passive"))
      (node (ref "R256") (pin "2") (pinfunction "2_2") (pintype "passive"))
      (node (ref "R273") (pin "2") (pinfunction "2_2") (pintype "passive"))
      (node (ref "R311") (pin "2") (pinfunction "2_2") (pintype "passive"))
      (node (ref "R328") (pin "2") (pinfunction "2_2") (pintype "passive"))
      (node (ref "R47") (pin "2") (pinfunction "2_2") (pintype "passive"))
      (node (ref "R64") (pin "2") (pinfunction "2_2") (pintype "passive"))
    )
    (net (code "2") (name "+12V") (class "Default")
      (node (ref "10") (pin "1") (pinfunction "KL_1") (pintype "passive"))
      (node (ref "12") (pin "1") (pinfunction "KL_1") (pintype "passive"))
      (node (ref "2") (pin "1") (pinfunction "KL_1") (pintype "passive"))
      (node (ref "4") (pin "1") (pinfunction "KL_1") (pintype "passive"))
      (node (ref "6") (pin "1") (pinfunction "KL_1") (pintype "passive"))
      (node (ref "8") (pin "1") (pinfunction "KL_1") (pintype "passive"))
      (node (ref "C13") (pin "1") (pinfunction "1_1") (pintype "passive"))
      (node (ref "C2") (pin "1") (pinfunction "1_1") (pintype "passive"))
      (node (ref "C26") (pin "1") (pinfunction "1_1") (pintype "passive"))
      (node (ref "C38") (pin "1") (pinfunction "1_1") (pintype "passive"))
      (node (ref "C50") (pin "1") (pinfunction "1_1") (pintype "passive"))
      (node (ref "C62") (pin "1") (pinfunction "1_1") (pintype "passive"))
      (node (ref "D101") (pin "C") (pinfunction "C_C") (pintype "passive"))
      (node (ref "D13") (pin "C") (pinfunction "C_C") (pintype "passive"))
      (node (ref "D27") (pin "C") (pinfunction "C_C") (pintype "passive"))
      (node (ref "D41") (pin "C") (pinfunction "C_C") (pintype "passive"))
      (node (ref "D55") (pin "C") (pinfunction "C_C") (pintype "passive"))
      (node (ref "D69") (pin "C") (pinfunction "C_C") (pintype "passive"))
      (node (ref "IC1") (pin "16") (pinfunction "VDD_16") (pintype "power_in"))
      (node (ref "IC10") (pin "16") (pinfunction "VDD_16") (pintype "power_in"))
      (node (ref "IC102") (pin "3") (pinfunction "IN_3") (pintype "input"))
      (node (ref "IC104") (pin "3") (pinfunction "IN_3") (pintype "input"))
      (node (ref "IC105") (pin "16") (pinfunction "VDD_16") (pintype "power_in"))
      (node (ref "IC107") (pin "9") (pinfunction "CD+_9") (pintype "passive"))
      (node (ref "IC12") (pin "9") (pinfunction "CD+_9") (pintype "passive"))
      (node (ref "IC14") (pin "3") (pinfunction "IN_3") (pintype "input"))
      (node (ref "IC17") (pin "3") (pinfunction "IN_3") (pintype "input"))
      (node (ref "IC19") (pin "16") (pinfunction "VDD_16") (pintype "power_in"))
      (node (ref "IC21") (pin "9") (pinfunction "CD+_9") (pintype "passive"))
      (node (ref "IC23") (pin "3") (pinfunction "IN_3") (pintype "input"))
      (node (ref "IC26") (pin "3") (pinfunction "IN_3") (pintype "input"))
      (node (ref "IC28") (pin "16") (pinfunction "VDD_16") (pintype "power_in"))
      (node (ref "IC3") (pin "9") (pinfunction "CD+_9") (pintype "passive"))
      (node (ref "IC30") (pin "9") (pinfunction "CD+_9") (pintype "passive"))
      (node (ref "IC32") (pin "3") (pinfunction "IN_3") (pintype "input"))
      (node (ref "IC35") (pin "3") (pinfunction "IN_3") (pintype "input"))
      (node (ref "IC37") (pin "16") (pinfunction "VDD_16") (pintype "power_in"))
      (node (ref "IC39") (pin "9") (pinfunction "CD+_9") (pintype "passive"))
      (node (ref "IC41") (pin "3") (pinfunction "IN_3") (pintype "input"))
      (node (ref "IC44") (pin "3") (pinfunction "IN_3") (pintype "input"))
      (node (ref "IC5") (pin "3") (pinfunction "IN_3") (pintype "input"))
      (node (ref "IC8") (pin "3") (pinfunction "IN_3") (pintype "input"))
      (node (ref "JP1") (pin "2") (pinfunction "2_2") (pintype "passive"))
      (node (ref "JP101") (pin "2") (pinfunction "2_2") (pintype "passive"))
      (node (ref "JP11") (pin "2") (pinfunction "2_2") (pintype "passive"))
      (node (ref "JP16") (pin "2") (pinfunction "2_2") (pintype "passive"))
      (node (ref "JP21") (pin "2") (pinfunction "2_2") (pintype "passive"))
      (node (ref "JP6") (pin "2") (pinfunction "2_2") (pintype "passive"))
      (node (ref "R102") (pin "1") (pinfunction "1_1") (pintype "passive"))
      (node (ref "R106") (pin "1") (pinfunction "1_1") (pintype "passive"))
      (node (ref "R109") (pin "2") (pinfunction "2_2") (pintype "passive"))
      (node (ref "R110") (pin "2") (pinfunction "2_2") (pintype "passive"))
      (node (ref "R111") (pin "2") (pinfunction "2_2") (pintype "passive"))
      (node (ref "R12") (pin "2") (pinfunction "2_2") (pintype "passive"))
      (node (ref "R13") (pin "2") (pinfunction "2_2") (pintype "passive"))
      (node (ref "R135") (pin "1") (pinfunction "1_1") (pintype "passive"))
      (node (ref "R15") (pin "2") (pinfunction "2_2") (pintype "passive"))
      (node (ref "R16") (pin "2") (pinfunction "2_2") (pintype "passive"))
      (node (ref "R164") (pin "2") (pinfunction "2_2") (pintype "passive"))
      (node (ref "R165") (pin "2") (pinfunction "2_2") (pintype "passive"))
      (node (ref "R169") (pin "2") (pinfunction "2_2") (pintype "passive"))
      (node (ref "R17") (pin "2") (pinfunction "2_2") (pintype "passive"))
      (node (ref "R170") (pin "2") (pinfunction "2_2") (pintype "passive"))
      (node (ref "R171") (pin "2") (pinfunction "2_2") (pintype "passive"))
      (node (ref "R190") (pin "1") (pinfunction "1_1") (pintype "passive"))
      (node (ref "R191") (pin "1") (pinfunction "1_1") (pintype "passive"))
      (node (ref "R195") (pin "1") (pinfunction "1_1") (pintype "passive"))
      (node (ref "R219") (pin "2") (pinfunction "2_2") (pintype "passive"))
      (node (ref "R220") (pin "2") (pinfunction "2_2") (pintype "passive"))
      (node (ref "R224") (pin "2") (pinfunction "2_2") (pintype "passive"))
      (node (ref "R225") (pin "2") (pinfunction "2_2") (pintype "passive"))
      (node (ref "R226") (pin "2") (pinfunction "2_2") (pintype "passive"))
      (node (ref "R245") (pin "1") (pinfunction "1_1") (pintype "passive"))
      (node (ref "R246") (pin "1") (pinfunction "1_1") (pintype "passive"))
      (node (ref "R250") (pin "1") (pinfunction "1_1") (pintype "passive"))
      (node (ref "R274") (pin "2") (pinfunction "2_2") (pintype "passive"))
      (node (ref "R275") (pin "2") (pinfunction "2_2") (pintype "passive"))
      (node (ref "R279") (pin "2") (pinfunction "2_2") (pintype "passive"))
      (node (ref "R280") (pin "2") (pinfunction "2_2") (pintype "passive"))
      (node (ref "R281") (pin "2") (pinfunction "2_2") (pintype "passive"))
      (node (ref "R300") (pin "1") (pinfunction "1_1") (pintype "passive"))
      (node (ref "R301") (pin "1") (pinfunction "1_1") (pintype "passive"))
      (node (ref "R305") (pin "1") (pinfunction "1_1") (pintype "passive"))
      (node (ref "R329") (pin "2") (pinfunction "2_2") (pintype "passive"))
      (node (ref "R330") (pin "2") (pinfunction "2_2") (pintype "passive"))
      (node (ref "R36") (pin "1") (pinfunction "1_1") (pintype "passive"))
      (node (ref "R37") (pin "1") (pinfunction "1_1") (pintype "passive"))
      (node (ref "R41") (pin "1") (pinfunction "1_1") (pintype "passive"))
      (node (ref "R65") (pin "2") (pinfunction "2_2") (pintype "passive"))
      (node (ref "R66") (pin "2") (pinfunction "2_2") (pintype "passive"))
      (node (ref "R70") (pin "2") (pinfunction "2_2") (pintype "passive"))
      (node (ref "R71") (pin "2") (pinfunction "2_2") (pintype "passive"))
      (node (ref "R72") (pin "2") (pinfunction "2_2") (pintype "passive"))
      (node (ref "R91") (pin "1") (pinfunction "1_1") (pintype "passive"))
      (node (ref "R92") (pin "1") (pinfunction "1_1") (pintype "passive"))
      (node (ref "R96") (pin "1") (pinfunction "1_1") (pintype "passive"))
      (node (ref "TP114") (pin "TP") (pinfunction "PP_TP") (pintype "input"))
      (node (ref "TP12") (pin "TP") (pinfunction "PP_TP") (pintype "input"))
      (node (ref "TP137") (pin "TP") (pinfunction "PP_TP") (pintype "input"))
      (node (ref "TP45") (pin "TP") (pinfunction "PP_TP") (pintype "input"))
      (node (ref "TP68") (pin "TP") (pinfunction "PP_TP") (pintype "input"))
      (node (ref "TP91") (pin "TP") (pinfunction "PP_TP") (pintype "input"))
      (node (ref "X103") (pin "1") (pinfunction "S_1") (pintype "passive"))
      (node (ref "X11") (pin "1") (pinfunction "S_1") (pintype "passive"))
      (node (ref "X14") (pin "1") (pinfunction "S_1") (pintype "passive"))
      (node (ref "X2") (pin "1") (pinfunction "S_1") (pintype "passive"))
      (node (ref "X5") (pin "1") (pinfunction "S_1") (pintype "passive"))
      (node (ref "X8") (pin "1") (pinfunction "S_1") (pintype "passive"))
    )
    (net (code "3") (name "GND") (class "Default")
      (node (ref "1") (pin "12") (pinfunction "KL_12") (pintype "passive"))
      (node (ref "11") (pin "12") (pinfunction "KL_12") (pintype "passive"))
      (node (ref "3") (pin "12") (pinfunction "KL_12") (pintype "passive"))
      (node (ref "5") (pin "12") (pinfunction "KL_12") (pintype "passive"))
      (node (ref "7") (pin "12") (pinfunction "KL_12") (pintype "passive"))
      (node (ref "9") (pin "12") (pinfunction "KL_12") (pintype "passive"))
      (node (ref "C1") (pin "2") (pinfunction "2_2") (pintype "passive"))
      (node (ref "C10") (pin "2") (pinfunction "2_2") (pintype "passive"))
      (node (ref "C101") (pin "2") (pinfunction "2_2") (pintype "passive"))
      (node (ref "C102") (pin "2") (pinfunction "2_2") (pintype "passive"))
      (node (ref "C103") (pin "2") (pinfunction "2_2") (pintype "passive"))
      (node (ref "C104") (pin "2") (pinfunction "2_2") (pintype "passive"))
      (node (ref "C105") (pin "2") (pinfunction "2_2") (pintype "passive"))
      (node (ref "C106") (pin "1") (pinfunction "1_1") (pintype "passive"))
      (node (ref "C107") (pin "2") (pinfunction "2_2") (pintype "passive"))
      (node (ref "C108") (pin "2") (pinfunction "2_2") (pintype "passive"))
      (node (ref "C109") (pin "1") (pinfunction "1_1") (pintype "passive"))
      (node (ref "C11") (pin "2") (pinfunction "2_2") (pintype "passive"))
      (node (ref "C110") (pin "2") (pinfunction "2_2") (pintype "passive"))
      (node (ref "C12") (pin "1") (pinfunction "1_1") (pintype "passive"))
      (node (ref "C13") (pin "2") (pinfunction "2_2") (pintype "passive"))
      (node (ref "C14") (pin "2") (pinfunction "2_2") (pintype "passive"))
      (node (ref "C15") (pin "1") (pinfunction "1_1") (pintype "passive"))
      (node (ref "C16") (pin "2") (pinfunction "2_2") (pintype "passive"))
      (node (ref "C17") (pin "2") (pinfunction "2_2") (pintype "passive"))
      (node (ref "C18") (pin "2") (pinfunction "2_2") (pintype "passive"))
      (node (ref "C19") (pin "2") (pinfunction "2_2") (pintype "passive"))
      (node (ref "C2") (pin "2") (pinfunction "2_2") (pintype "passive"))
      (node (ref "C20") (pin "1") (pinfunction "1_1") (pintype "passive"))
      (node (ref "C21") (pin "1") (pinfunction "1_1") (pintype "passive"))
      (node (ref "C22") (pin "2") (pinfunction "2_2") (pintype "passive"))
      (node (ref "C23") (pin "2") (pinfunction "2_2") (pintype "passive"))
      (node (ref "C24") (pin "2") (pinfunction "2_2") (pintype "passive"))
      (node (ref "C25") (pin "1") (pinfunction "1_1") (pintype "passive"))
      (node (ref "C26") (pin "2") (pinfunction "2_2") (pintype "passive"))
      (node (ref "C27") (pin "2") (pinfunction "2_2") (pintype "passive"))
      (node (ref "C28") (pin "2") (pinfunction "2_2") (pintype "passive"))
      (node (ref "C29") (pin "2") (pinfunction "2_2") (pintype "passive"))
      (node (ref "C3") (pin "2") (pinfunction "2_2") (pintype "passive"))
      (node (ref "C30") (pin "2") (pinfunction "2_2") (pintype "passive"))
      (node (ref "C31") (pin "2") (pinfunction "2_2") (pintype "passive"))
      (node (ref "C32") (pin "1") (pinfunction "1_1") (pintype "passive"))
      (node (ref "C33") (pin "1") (pinfunction "1_1") (pintype "passive"))
      (node (ref "C34") (pin "2") (pinfunction "2_2") (pintype "passive"))
      (node (ref "C35") (pin "2") (pinfunction "2_2") (pintype "passive"))
      (node (ref "C36") (pin "2") (pinfunction "2_2") (pintype "passive"))
      (node (ref "C37") (pin "1") (pinfunction "1_1") (pintype "passive"))
      (node (ref "C38") (pin "2") (pinfunction "2_2") (pintype "passive"))
      (node (ref "C39") (pin "2") (pinfunction "2_2") (pintype "passive"))
      (node (ref "C4") (pin "2") (pinfunction "2_2") (pintype "passive"))
      (node (ref "C40") (pin "2") (pinfunction "2_2") (pintype "passive"))
      (node (ref "C41") (pin "2") (pinfunction "2_2") (pintype "passive"))
      (node (ref "C42") (pin "2") (pinfunction "2_2") (pintype "passive"))
      (node (ref "C43") (pin "2") (pinfunction "2_2") (pintype "passive"))
      (node (ref "C44") (pin "1") (pinfunction "1_1") (pintype "passive"))
      (node (ref "C45") (pin "1") (pinfunction "1_1") (pintype "passive"))
      (node (ref "C46") (pin "2") (pinfunction "2_2") (pintype "passive"))
      (node (ref "C47") (pin "2") (pinfunction "2_2") (pintype "passive"))
      (node (ref "C48") (pin "2") (pinfunction "2_2") (pintype "passive"))
      (node (ref "C49") (pin "1") (pinfunction "1_1") (pintype "passive"))
      (node (ref "C5") (pin "2") (pinfunction "2_2") (pintype "passive"))
      (node (ref "C50") (pin "2") (pinfunction "2_2") (pintype "passive"))
      (node (ref "C51") (pin "2") (pinfunction "2_2") (pintype "passive"))
      (node (ref "C52") (pin "2") (pinfunction "2_2") (pintype "passive"))
      (node (ref "C53") (pin "2") (pinfunction "2_2") (pintype "passive"))
      (node (ref "C54") (pin "2") (pinfunction "2_2") (pintype "passive"))
      (node (ref "C55") (pin "2") (pinfunction "2_2") (pintype "passive"))
      (node (ref "C56") (pin "1") (pinfunction "1_1") (pintype "passive"))
      (node (ref "C57") (pin "1") (pinfunction "1_1") (pintype "passive"))
      (node (ref "C58") (pin "2") (pinfunction "2_2") (pintype "passive"))
      (node (ref "C59") (pin "2") (pinfunction "2_2") (pintype "passive"))
      (node (ref "C6") (pin "2") (pinfunction "2_2") (pintype "passive"))
      (node (ref "C60") (pin "2") (pinfunction "2_2") (pintype "passive"))
      (node (ref "C61") (pin "1") (pinfunction "1_1") (pintype "passive"))
      (node (ref "C62") (pin "2") (pinfunction "2_2") (pintype "passive"))
      (node (ref "C7") (pin "1") (pinfunction "1_1") (pintype "passive"))
      (node (ref "C8") (pin "1") (pinfunction "1_1") (pintype "passive"))
      (node (ref "C9") (pin "2") (pinfunction "2_2") (pintype "passive"))
      (node (ref "D101") (pin "A") (pinfunction "A_A") (pintype "passive"))
      (node (ref "D104") (pin "A") (pinfunction "A_A") (pintype "passive"))
      (node (ref "D105") (pin "1") (pinfunction "+_1") (pintype "passive"))
      (node (ref "D11") (pin "1") (pinfunction "+_1") (pintype "passive"))
      (node (ref "D13") (pin "A") (pinfunction "A_A") (pintype "passive"))
      (node (ref "D14") (pin "A") (pinfunction "A_A") (pintype "passive"))
      (node (ref "D17") (pin "A") (pinfunction "A_A") (pintype "passive"))
      (node (ref "D25") (pin "1") (pinfunction "+_1") (pintype "passive"))
      (node (ref "D27") (pin "A") (pinfunction "A_A") (pintype "passive"))
      (node (ref "D28") (pin "A") (pinfunction "A_A") (pintype "passive"))
      (node (ref "D31") (pin "A") (pinfunction "A_A") (pintype "passive"))
      (node (ref "D39") (pin "1") (pinfunction "+_1") (pintype "passive"))
      (node (ref "D4") (pin "A") (pinfunction "A_A") (pintype "passive"))
      (node (ref "D41") (pin "A") (pinfunction "A_A") (pintype "passive"))
      (node (ref "D42") (pin "A") (pinfunction "A_A") (pintype "passive"))
      (node (ref "D45") (pin "A") (pinfunction "A_A") (pintype "passive"))
      (node (ref "D53") (pin "1") (pinfunction "+_1") (pintype "passive"))
      (node (ref "D55") (pin "A") (pinfunction "A_A") (pintype "passive"))
      (node (ref "D56") (pin "A") (pinfunction "A_A") (pintype "passive"))
      (node (ref "D59") (pin "A") (pinfunction "A_A") (pintype "passive"))
      (node (ref "D67") (pin "1") (pinfunction "+_1") (pintype "passive"))
      (node (ref "D69") (pin "A") (pinfunction "A_A") (pintype "passive"))
      (node (ref "D70") (pin "A") (pinfunction "A_A") (pintype "passive"))
      (node (ref "D73") (pin "A") (pinfunction "A_A") (pintype "passive"))
      (node (ref "IC1") (pin "11") (pinfunction "D_11") (pintype "input"))
      (node (ref "IC1") (pin "8") (pinfunction "VSS_8") (pintype "power_in"))
      (node (ref "IC10") (pin "11") (pinfunction "D_11") (pintype "input"))
      (node (ref "IC10") (pin "8") (pinfunction "VSS_8") (pintype "power_in"))
      (node (ref "IC101") (pin "4") (pinfunction "V-_4") (pintype "power_in"))
      (node (ref "IC102") (pin "2") (pinfunction "GND_2") (pintype "input"))
      (node (ref "IC102") (pin "2@1") (pinfunction "GND_2@1") (pintype "input"))
      (node (ref "IC104") (pin "2") (pinfunction "GND_2") (pintype "input"))
      (node (ref "IC104") (pin "2@1") (pinfunction "GND_2@1") (pintype "input"))
      (node (ref "IC105") (pin "11") (pinfunction "D_11") (pintype "input"))
      (node (ref "IC105") (pin "8") (pinfunction "VSS_8") (pintype "power_in"))
      (node (ref "IC107") (pin "8") (pinfunction "GND_8") (pintype "power_in"))
      (node (ref "IC108") (pin "12") (pinfunction "GND_12") (pintype "power_in"))
      (node (ref "IC110") (pin "1") (pinfunction "GND_1") (pintype "power_in"))
      (node (ref "IC111") (pin "1") (pinfunction "T1_1") (pintype "input"))
      (node (ref "IC111") (pin "15") (pinfunction "T1_15") (pintype "input"))
      (node (ref "IC111") (pin "8") (pinfunction "VSS_8") (pintype "power_in"))
      (node (ref "IC12") (pin "8") (pinfunction "GND_8") (pintype "power_in"))
      (node (ref "IC13") (pin "12") (pinfunction "GND_12") (pintype "power_in"))
      (node (ref "IC14") (pin "2") (pinfunction "GND_2") (pintype "input"))
      (node (ref "IC14") (pin "2@1") (pinfunction "GND_2@1") (pintype "input"))
      (node (ref "IC15") (pin "1") (pinfunction "GND_1") (pintype "power_in"))
      (node (ref "IC16") (pin "1") (pinfunction "T1_1") (pintype "input"))
      (node (ref "IC16") (pin "15") (pinfunction "T1_15") (pintype "input"))
      (node (ref "IC16") (pin "8") (pinfunction "VSS_8") (pintype "power_in"))
      (node (ref "IC17") (pin "2") (pinfunction "GND_2") (pintype "input"))
      (node (ref "IC17") (pin "2@1") (pinfunction "GND_2@1") (pintype "input"))
      (node (ref "IC18") (pin "4") (pinfunction "V-_4") (pintype "power_in"))
      (node (ref "IC19") (pin "11") (pinfunction "D_11") (pintype "input"))
      (node (ref "IC19") (pin "8") (pinfunction "VSS_8") (pintype "power_in"))
      (node (ref "IC21") (pin "8") (pinfunction "GND_8") (pintype "power_in"))
      (node (ref "IC22") (pin "12") (pinfunction "GND_12") (pintype "power_in"))
      (node (ref "IC23") (pin "2") (pinfunction "GND_2") (pintype "input"))
      (node (ref "IC23") (pin "2@1") (pinfunction "GND_2@1") (pintype "input"))
      (node (ref "IC24") (pin "1") (pinfunction "GND_1") (pintype "power_in"))
      (node (ref "IC25") (pin "1") (pinfunction "T1_1") (pintype "input"))
      (node (ref "IC25") (pin "15") (pinfunction "T1_15") (pintype "input"))
      (node (ref "IC25") (pin "8") (pinfunction "VSS_8") (pintype "power_in"))
      (node (ref "IC26") (pin "2") (pinfunction "GND_2") (pintype "input"))
      (node (ref "IC26") (pin "2@1") (pinfunction "GND_2@1") (pintype "input"))
      (node (ref "IC27") (pin "4") (pinfunction "V-_4") (pintype "power_in"))
      (node (ref "IC28") (pin "11") (pinfunction "D_11") (pintype "input"))
      (node (ref "IC28") (pin "8") (pinfunction "VSS_8") (pintype "power_in"))
      (node (ref "IC3") (pin "8") (pinfunction "GND_8") (pintype "power_in"))
      (node (ref "IC30") (pin "8") (pinfunction "GND_8") (pintype "power_in"))
      (node (ref "IC31") (pin "12") (pinfunction "GND_12") (pintype "power_in"))
      (node (ref "IC32") (pin "2") (pinfunction "GND_2") (pintype "input"))
      (node (ref "IC32") (pin "2@1") (pinfunction "GND_2@1") (pintype "input"))
      (node (ref "IC33") (pin "1") (pinfunction "GND_1") (pintype "power_in"))
      (node (ref "IC34") (pin "1") (pinfunction "T1_1") (pintype "input"))
      (node (ref "IC34") (pin "15") (pinfunction "T1_15") (pintype "input"))
      (node (ref "IC34") (pin "8") (pinfunction "VSS_8") (pintype "power_in"))
      (node (ref "IC35") (pin "2") (pinfunction "GND_2") (pintype "input"))
      (node (ref "IC35") (pin "2@1") (pinfunction "GND_2@1") (pintype "input"))
      (node (ref "IC36") (pin "4") (pinfunction "V-_4") (pintype "power_in"))
      (node (ref "IC37") (pin "11") (pinfunction "D_11") (pintype "input"))
      (node (ref "IC37") (pin "8") (pinfunction "VSS_8") (pintype "power_in"))
      (node (ref "IC39") (pin "8") (pinfunction "GND_8") (pintype "power_in"))
      (node (ref "IC4") (pin "12") (pinfunction "GND_12") (pintype "power_in"))
      (node (ref "IC40") (pin "12") (pinfunction "GND_12") (pintype "power_in"))
      (node (ref "IC41") (pin "2") (pinfunction "GND_2") (pintype "input"))
      (node (ref "IC41") (pin "2@1") (pinfunction "GND_2@1") (pintype "input"))
      (node (ref "IC42") (pin "1") (pinfunction "GND_1") (pintype "power_in"))
      (node (ref "IC43") (pin "1") (pinfunction "T1_1") (pintype "input"))
      (node (ref "IC43") (pin "15") (pinfunction "T1_15") (pintype "input"))
      (node (ref "IC43") (pin "8") (pinfunction "VSS_8") (pintype "power_in"))
      (node (ref "IC44") (pin "2") (pinfunction "GND_2") (pintype "input"))
      (node (ref "IC44") (pin "2@1") (pinfunction "GND_2@1") (pintype "input"))
      (node (ref "IC45") (pin "4") (pinfunction "V-_4") (pintype "power_in"))
      (node (ref "IC5") (pin "2") (pinfunction "GND_2") (pintype "input"))
      (node (ref "IC5") (pin "2@1") (pinfunction "GND_2@1") (pintype "input"))
      (node (ref "IC6") (pin "1") (pinfunction "GND_1") (pintype "power_in"))
      (node (ref "IC7") (pin "1") (pinfunction "T1_1") (pintype "input"))
      (node (ref "IC7") (pin "15") (pinfunction "T1_15") (pintype "input"))
      (node (ref "IC7") (pin "8") (pinfunction "VSS_8") (pintype "power_in"))
      (node (ref "IC8") (pin "2") (pinfunction "GND_2") (pintype "input"))
      (node (ref "IC8") (pin "2@1") (pinfunction "GND_2@1") (pintype "input"))
      (node (ref "IC9") (pin "4") (pinfunction "V-_4") (pintype "power_in"))
      (node (ref "Q1") (pin "2") (pinfunction "S_2") (pintype "passive"))
      (node (ref "Q107") (pin "2") (pinfunction "S_2") (pintype "passive"))
      (node (ref "Q11") (pin "2") (pinfunction "S_2") (pintype "passive"))
      (node (ref "Q13") (pin "2") (pinfunction "S_2") (pintype "passive"))
      (node (ref "Q19") (pin "2") (pinfunction "S_2") (pintype "passive"))
      (node (ref "Q21") (pin "2") (pinfunction "S_2") (pintype "passive"))
      (node (ref "Q23") (pin "2") (pinfunction "S_2") (pintype "passive"))
      (node (ref "Q29") (pin "2") (pinfunction "S_2") (pintype "passive"))
      (node (ref "Q3") (pin "2") (pinfunction "S_2") (pintype "passive"))
      (node (ref "Q31") (pin "2") (pinfunction "S_2") (pintype "passive"))
      (node (ref "Q33") (pin "2") (pinfunction "S_2") (pintype "passive"))
      (node (ref "Q39") (pin "2") (pinfunction "S_2") (pintype "passive"))
      (node (ref "Q41") (pin "2") (pinfunction "S_2") (pintype "passive"))
      (node (ref "Q43") (pin "2") (pinfunction "S_2") (pintype "passive"))
      (node (ref "Q49") (pin "2") (pinfunction "S_2") (pintype "passive"))
      (node (ref "Q51") (pin "2") (pinfunction "S_2") (pintype "passive"))
      (node (ref "Q53") (pin "2") (pinfunction "S_2") (pintype "passive"))
      (node (ref "Q9") (pin "2") (pinfunction "S_2") (pintype "passive"))
      (node (ref "R100") (pin "1") (pinfunction "1_1") (pintype "passive"))
      (node (ref "R101") (pin "2") (pinfunction "2_2") (pintype "passive"))
      (node (ref "R103") (pin "2") (pinfunction "2_2") (pintype "passive"))
      (node (ref "R104") (pin "2") (pinfunction "2_2") (pintype "passive"))
      (node (ref "R107") (pin "1") (pinfunction "1_1") (pintype "passive"))
      (node (ref "R114") (pin "1") (pinfunction "1_1") (pintype "passive"))
      (node (ref "R118") (pin "1") (pinfunction "1_1") (pintype "passive"))
      (node (ref "R123") (pin "1") (pinfunction "1_1") (pintype "passive"))
      (node (ref "R132") (pin "1") (pinfunction "1_1") (pintype "passive"))
      (node (ref "R136") (pin "1") (pinfunction "1_1") (pintype "passive"))
      (node (ref "R137") (pin "1") (pinfunction "1_1") (pintype "passive"))
      (node (ref "R141") (pin "2") (pinfunction "2_2") (pintype "passive"))
      (node (ref "R143") (pin "2") (pinfunction "2_2") (pintype "passive"))
      (node (ref "R153") (pin "1") (pinfunction "1_1") (pintype "passive"))
      (node (ref "R154") (pin "2") (pinfunction "2_2") (pintype "passive"))
      (node (ref "R158") (pin "2") (pinfunction "2_2") (pintype "passive"))
      (node (ref "R159") (pin "2") (pinfunction "2_2") (pintype "passive"))
      (node (ref "R160") (pin "1") (pinfunction "1_1") (pintype "passive"))
      (node (ref "R173") (pin "1") (pinfunction "1_1") (pintype "passive"))
      (node (ref "R179") (pin "1") (pinfunction "1_1") (pintype "passive"))
      (node (ref "R183") (pin "1") (pinfunction "1_1") (pintype "passive"))
      (node (ref "R184") (pin "2") (pinfunction "2_2") (pintype "passive"))
      (node (ref "R185") (pin "2") (pinfunction "2_2") (pintype "passive"))
      (node (ref "R187") (pin "2") (pinfunction "2_2") (pintype "passive"))
      (node (ref "R19") (pin "1") (pinfunction "1_1") (pintype "passive"))
      (node (ref "R196") (pin "2") (pinfunction "2_2") (pintype "passive"))
      (node (ref "R199") (pin "1") (pinfunction "1_1") (pintype "passive"))
      (node (ref "R200") (pin "1") (pinfunction "1_1") (pintype "passive"))
      (node (ref "R208") (pin "1") (pinfunction "1_1") (pintype "passive"))
      (node (ref "R209") (pin "2") (pinfunction "2_2") (pintype "passive"))
      (node (ref "R213") (pin "2") (pinfunction "2_2") (pintype "passive"))
      (node (ref "R214") (pin "2") (pinfunction "2_2") (pintype "passive"))
      (node (ref "R215") (pin "1") (pinfunction "1_1") (pintype "passive"))
      (node (ref "R228") (pin "1") (pinfunction "1_1") (pintype "passive"))
      (node (ref "R234") (pin "1") (pinfunction "1_1") (pintype "passive"))
      (node (ref "R238") (pin "1") (pinfunction "1_1") (pintype "passive"))
      (node (ref "R239") (pin "2") (pinfunction "2_2") (pintype "passive"))
      (node (ref "R240") (pin "2") (pinfunction "2_2") (pintype "passive"))
      (node (ref "R242") (pin "2") (pinfunction "2_2") (pintype "passive"))
      (node (ref "R25") (pin "1") (pinfunction "1_1") (pintype "passive"))
      (node (ref "R251") (pin "2") (pinfunction "2_2") (pintype "passive"))
      (node (ref "R254") (pin "1") (pinfunction "1_1") (pintype "passive"))
      (node (ref "R255") (pin "1") (pinfunction "1_1") (pintype "passive"))
      (node (ref "R263") (pin "1") (pinfunction "1_1") (pintype "passive"))
      (node (ref "R264") (pin "2") (pinfunction "2_2") (pintype "passive"))
      (node (ref "R268") (pin "2") (pinfunction "2_2") (pintype "passive"))
      (node (ref "R269") (pin "2") (pinfunction "2_2") (pintype "passive"))
      (node (ref "R270") (pin "1") (pinfunction "1_1") (pintype "passive"))
      (node (ref "R283") (pin "1") (pinfunction "1_1") (pintype "passive"))
      (node (ref "R289") (pin "1") (pinfunction "1_1") (pintype "passive"))
      (node (ref "R29") (pin "1") (pinfunction "1_1") (pintype "passive"))
      (node (ref "R293") (pin "1") (pinfunction "1_1") (pintype "passive"))
      (node (ref "R294") (pin "2") (pinfunction "2_2") (pintype "passive"))
      (node (ref "R295") (pin "2") (pinfunction "2_2") (pintype "passive"))
      (node (ref "R297") (pin "2") (pinfunction "2_2") (pintype "passive"))
      (node (ref "R30") (pin "2") (pinfunction "2_2") (pintype "passive"))
      (node (ref "R306") (pin "2") (pinfunction "2_2") (pintype "passive"))
      (node (ref "R309") (pin "1") (pinfunction "1_1") (pintype "passive"))
      (node (ref "R31") (pin "2") (pinfunction "2_2") (pintype "passive"))
      (node (ref "R310") (pin "1") (pinfunction "1_1") (pintype "passive"))
      (node (ref "R318") (pin "1") (pinfunction "1_1") (pintype "passive"))
      (node (ref "R319") (pin "2") (pinfunction "2_2") (pintype "passive"))
      (node (ref "R323") (pin "2") (pinfunction "2_2") (pintype "passive"))
      (node (ref "R324") (pin "2") (pinfunction "2_2") (pintype "passive"))
      (node (ref "R325") (pin "1") (pinfunction "1_1") (pintype "passive"))
      (node (ref "R33") (pin "2") (pinfunction "2_2") (pintype "passive"))
      (node (ref "R4") (pin "1") (pinfunction "1_1") (pintype "passive"))
      (node (ref "R42") (pin "2") (pinfunction "2_2") (pintype "passive"))
      (node (ref "R45") (pin "1") (pinfunction "1_1") (pintype "passive"))
      (node (ref "R46") (pin "1") (pinfunction "1_1") (pintype "passive"))
      (node (ref "R5") (pin "2") (pinfunction "2_2") (pintype "passive"))
      (node (ref "R54") (pin "1") (pinfunction "1_1") (pintype "passive"))
      (node (ref "R55") (pin "2") (pinfunction "2_2") (pintype "passive"))
      (node (ref "R59") (pin "2") (pinfunction "2_2") (pintype "passive"))
      (node (ref "R6") (pin "2") (pinfunction "2_2") (pintype "passive"))
      (node (ref "R60") (pin "2") (pinfunction "2_2") (pintype "passive"))
      (node (ref "R61") (pin "1") (pinfunction "1_1") (pintype "passive"))
      (node (ref "R74") (pin "1") (pinfunction "1_1") (pintype "passive"))
      (node (ref "R80") (pin "1") (pinfunction "1_1") (pintype "passive"))
      (node (ref "R84") (pin "1") (pinfunction "1_1") (pintype "passive"))
      (node (ref "R85") (pin "2") (pinfunction "2_2") (pintype "passive"))
      (node (ref "R86") (pin "2") (pinfunction "2_2") (pintype "passive"))
      (node (ref "R88") (pin "2") (pinfunction "2_2") (pintype "passive"))
      (node (ref "R97") (pin "2") (pinfunction "2_2") (pintype "passive"))
      (node (ref "X1") (pin "13") (pinfunction "13_13") (pintype "passive"))
      (node (ref "X1") (pin "18") (pinfunction "18_18") (pintype "passive"))
      (node (ref "X1") (pin "23") (pinfunction "23_23") (pintype "passive"))
      (node (ref "X10") (pin "13") (pinfunction "13_13") (pintype "passive"))
      (node (ref "X10") (pin "18") (pinfunction "18_18") (pintype "passive"))
      (node (ref "X10") (pin "23") (pinfunction "23_23") (pintype "passive"))
      (node (ref "X101") (pin "13") (pinfunction "13_13") (pintype "passive"))
      (node (ref "X101") (pin "18") (pinfunction "18_18") (pintype "passive"))
      (node (ref "X101") (pin "23") (pinfunction "23_23") (pintype "passive"))
      (node (ref "X102") (pin "1") (pinfunction "S_1") (pintype "passive"))
      (node (ref "X103") (pin "5") (pinfunction "S_5") (pintype "passive"))
      (node (ref "X11") (pin "5") (pinfunction "S_5") (pintype "passive"))
      (node (ref "X12") (pin "1") (pinfunction "S_1") (pintype "passive"))
      (node (ref "X13") (pin "13") (pinfunction "13_13") (pintype "passive"))
      (node (ref "X13") (pin "18") (pinfunction "18_18") (pintype "passive"))
      (node (ref "X13") (pin "23") (pinfunction "23_23") (pintype "passive"))
      (node (ref "X14") (pin "5") (pinfunction "S_5") (pintype "passive"))
      (node (ref "X15") (pin "1") (pinfunction "S_1") (pintype "passive"))
      (node (ref "X2") (pin "5") (pinfunction "S_5") (pintype "passive"))
      (node (ref "X3") (pin "1") (pinfunction "S_1") (pintype "passive"))
      (node (ref "X4") (pin "13") (pinfunction "13_13") (pintype "passive"))
      (node (ref "X4") (pin "18") (pinfunction "18_18") (pintype "passive"))
      (node (ref "X4") (pin "23") (pinfunction "23_23") (pintype "passive"))
      (node (ref "X5") (pin "5") (pinfunction "S_5") (pintype "passive"))
      (node (ref "X6") (pin "1") (pinfunction "S_1") (pintype "passive"))
      (node (ref "X7") (pin "13") (pinfunction "13_13") (pintype "passive"))
      (node (ref "X7") (pin "18") (pinfunction "18_18") (pintype "passive"))
      (node (ref "X7") (pin "23") (pinfunction "23_23") (pintype "passive"))
      (node (ref "X8") (pin "5") (pinfunction "S_5") (pintype "passive"))
      (node (ref "X9") (pin "1") (pinfunction "S_1") (pintype "passive"))
    )
    (net (code "4") (name "Net-(1A-KL)") (class "Default")
      (node (ref "1") (pin "1") (pinfunction "KL_1") (pintype "passive"))
      (node (ref "D2") (pin "2") (pinfunction "-_2") (pintype "passive"))
      (node (ref "TP1") (pin "TP") (pinfunction "PP_TP") (pintype "input"))
    )
    (net (code "5") (name "Net-(1B-KL)") (class "Default")
      (node (ref "1") (pin "10") (pinfunction "KL_10") (pintype "passive"))
      (node (ref "D102") (pin "2") (pinfunction "-_2") (pintype "passive"))
      (node (ref "D103") (pin "2") (pinfunction "-_2") (pintype "passive"))
      (node (ref "JP104") (pin "1") (pinfunction "1_1") (pintype "passive"))
      (node (ref "SJ101") (pin "1") (pinfunction "1_1") (pintype "passive"))
      (node (ref "TP10") (pin "TP") (pinfunction "PP_TP") (pintype "input"))
    )
    (net (code "6") (name "Net-(1C-KL)") (class "Default")
      (node (ref "1") (pin "11") (pinfunction "KL_11") (pintype "passive"))
      (node (ref "D103") (pin "1") (pinfunction "+_1") (pintype "passive"))
      (node (ref "TP11") (pin "TP") (pinfunction "PP_TP") (pintype "input"))
      (node (ref "X101") (pin "19") (pinfunction "19_19") (pintype "passive"))
    )
    (net (code "7") (name "Net-(1E-KL)") (class "Default")
      (node (ref "1") (pin "2") (pinfunction "KL_2") (pintype "passive"))
      (node (ref "Q101") (pin "2") (pinfunction "C_2") (pintype "passive"))
      (node (ref "TP2") (pin "TP") (pinfunction "PP_TP") (pintype "input"))
    )
    (net (code "8") (name "Net-(1F-KL)") (class "Default")
      (node (ref "1") (pin "3") (pinfunction "KL_3") (pintype "passive"))
      (node (ref "IC107") (pin "11") (pinfunction "O6_11") (pintype "open_collector"))
      (node (ref "TP3") (pin "TP") (pinfunction "PP_TP") (pintype "input"))
    )
    (net (code "9") (name "Net-(1G-KL)") (class "Default")
      (node (ref "1") (pin "4") (pinfunction "KL_4") (pintype "passive"))
      (node (ref "IC107") (pin "10") (pinfunction "O7_10") (pintype "open_collector"))
      (node (ref "TP4") (pin "TP") (pinfunction "PP_TP") (pintype "input"))
    )
    (net (code "10") (name "Net-(1H-KL)") (class "Default")
      (node (ref "1") (pin "5") (pinfunction "KL_5") (pintype "passive"))
      (node (ref "IC107") (pin "12") (pinfunction "O5_12") (pintype "open_collector"))
      (node (ref "TP5") (pin "TP") (pinfunction "PP_TP") (pintype "input"))
    )
    (net (code "11") (name "Net-(1I-KL)") (class "Default")
      (node (ref "1") (pin "6") (pinfunction "KL_6") (pintype "passive"))
      (node (ref "IC107") (pin "13") (pinfunction "O4_13") (pintype "open_collector"))
      (node (ref "TP6") (pin "TP") (pinfunction "PP_TP") (pintype "input"))
    )
    (net (code "12") (name "Net-(1J-KL)") (class "Default")
      (node (ref "1") (pin "7") (pinfunction "KL_7") (pintype "passive"))
      (node (ref "IC107") (pin "14") (pinfunction "O3_14") (pintype "open_collector"))
      (node (ref "TP7") (pin "TP") (pinfunction "PP_TP") (pintype "input"))
    )
    (net (code "13") (name "Net-(1K-KL)") (class "Default")
      (node (ref "1") (pin "8") (pinfunction "KL_8") (pintype "passive"))
      (node (ref "R9") (pin "2") (pinfunction "2_2") (pintype "passive"))
      (node (ref "TP8") (pin "TP") (pinfunction "PP_TP") (pintype "input"))
    )
    (net (code "14") (name "Net-(1L-KL)") (class "Default")
      (node (ref "1") (pin "9") (pinfunction "KL_9") (pintype "passive"))
      (node (ref "D102") (pin "1") (pinfunction "+_1") (pintype "passive"))
      (node (ref "TP9") (pin "TP") (pinfunction "PP_TP") (pintype "input"))
      (node (ref "X101") (pin "17") (pinfunction "17_17") (pintype "passive"))
    )
    (net (code "15") (name "Net-(2B-KL)") (class "Default")
      (node (ref "2") (pin "10") (pinfunction "KL_10") (pintype "passive"))
      (node (ref "TP25") (pin "TP") (pinfunction "PP_TP") (pintype "input"))
      (node (ref "X101") (pin "15") (pinfunction "15_15") (pintype "passive"))
    )
    (net (code "16") (name "Net-(2C-KL)") (class "Default")
      (node (ref "2") (pin "11") (pinfunction "KL_11") (pintype "passive"))
      (node (ref "Q103") (pin "2") (pinfunction "C_2") (pintype "passive"))
      (node (ref "R119") (pin "1") (pinfunction "1_1") (pintype "passive"))
      (node (ref "TP26") (pin "TP") (pinfunction "PP_TP") (pintype "input"))
    )
    (net (code "17") (name "Net-(2D-KL)") (class "Default")
      (node (ref "2") (pin "12") (pinfunction "KL_12") (pintype "passive"))
      (node (ref "R146") (pin "1") (pinfunction "1_1") (pintype "passive"))
      (node (ref "TP13") (pin "TP") (pinfunction "PP_TP") (pintype "input"))
    )
    (net (code "18") (name "Net-(2E-KL)") (class "Default")
      (node (ref "2") (pin "2") (pinfunction "KL_2") (pintype "passive"))
      (node (ref "D109") (pin "2") (pinfunction "-_2") (pintype "passive"))
      (node (ref "LED102") (pin "K") (pinfunction "C_K") (pintype "passive"))
      (node (ref "TP16") (pin "TP") (pinfunction "PP_TP") (pintype "input"))
      (node (ref "X101") (pin "12") (pinfunction "12_12") (pintype "passive"))
    )
    (net (code "19") (name "Net-(2F-KL)") (class "Default")
      (node (ref "2") (pin "3") (pinfunction "KL_3") (pintype "passive"))
      (node (ref "D108") (pin "2") (pinfunction "-_2") (pintype "passive"))
      (node (ref "LED103") (pin "K") (pinfunction "C_K") (pintype "passive"))
      (node (ref "TP17") (pin "TP") (pinfunction "PP_TP") (pintype "input"))
      (node (ref "X101") (pin "11") (pinfunction "11_11") (pintype "passive"))
    )
    (net (code "20") (name "Net-(2G-KL)") (class "Default")
      (node (ref "2") (pin "4") (pinfunction "KL_4") (pintype "passive"))
      (node (ref "D107") (pin "2") (pinfunction "-_2") (pintype "passive"))
      (node (ref "LED104") (pin "K") (pinfunction "C_K") (pintype "passive"))
      (node (ref "TP18") (pin "TP") (pinfunction "PP_TP") (pintype "input"))
      (node (ref "X101") (pin "10") (pinfunction "10_10") (pintype "passive"))
    )
    (net (code "21") (name "Net-(2H-KL)") (class "Default")
      (node (ref "2") (pin "5") (pinfunction "KL_5") (pintype "passive"))
      (node (ref "D106") (pin "2") (pinfunction "-_2") (pintype "passive"))
      (node (ref "LED105") (pin "K") (pinfunction "C_K") (pintype "passive"))
      (node (ref "TP19") (pin "TP") (pinfunction "PP_TP") (pintype "input"))
      (node (ref "X101") (pin "9") (pinfunction "9_9") (pintype "passive"))
    )
    (net (code "22") (name "Net-(2I-KL)") (class "Default")
      (node (ref "2") (pin "6") (pinfunction "KL_6") (pintype "passive"))
      (node (ref "JP105") (pin "2") (pinfunction "2_2") (pintype "passive"))
      (node (ref "TP21") (pin "TP") (pinfunction "PP_TP") (pintype "input"))
    )
    (net (code "23") (name "Net-(2J-KL)") (class "Default")
      (node (ref "2") (pin "7") (pinfunction "KL_7") (pintype "passive"))
      (node (ref "LED101") (pin "A") (pinfunction "A_A") (pintype "passive"))
      (node (ref "TP22") (pin "TP") (pinfunction "PP_TP") (pintype "input"))
      (node (ref "X101") (pin "8") (pinfunction "8_8") (pintype "passive"))
    )
    (net (code "24") (name "Net-(2K-KL)") (class "Default")
      (node (ref "2") (pin "8") (pinfunction "KL_8") (pintype "passive"))
      (node (ref "D110") (pin "2") (pinfunction "-_2") (pintype "passive"))
      (node (ref "LED106") (pin "K") (pinfunction "C_K") (pintype "passive"))
      (node (ref "TP23") (pin "TP") (pinfunction "PP_TP") (pintype "input"))
      (node (ref "X101") (pin "14") (pinfunction "14_14") (pintype "passive"))
    )
    (net (code "25") (name "Net-(2L-KL)") (class "Default")
      (node (ref "2") (pin "9") (pinfunction "KL_9") (pintype "passive"))
      (node (ref "D107") (pin "1") (pinfunction "+_1") (pintype "passive"))
      (node (ref "D108") (pin "1") (pinfunction "+_1") (pintype "passive"))
      (node (ref "JP102") (pin "1") (pinfunction "1_1") (pintype "passive"))
      (node (ref "JP103") (pin "2") (pinfunction "2_2") (pintype "passive"))
      (node (ref "TP24") (pin "TP") (pinfunction "PP_TP") (pintype "input"))
    )
    (net (code "26") (name "Net-(3A-KL)") (class "Default")
      (node (ref "3") (pin "1") (pinfunction "KL_1") (pintype "passive"))
      (node (ref "D16") (pin "2") (pinfunction "-_2") (pintype "passive"))
      (node (ref "TP14") (pin "TP") (pinfunction "PP_TP") (pintype "input"))
    )
    (net (code "27") (name "Net-(3B-KL)") (class "Default")
      (node (ref "3") (pin "10") (pinfunction "KL_10") (pintype "passive"))
      (node (ref "D3") (pin "2") (pinfunction "-_2") (pintype "passive"))
      (node (ref "D5") (pin "2") (pinfunction "-_2") (pintype "passive"))
      (node (ref "JP5") (pin "1") (pinfunction "1_1") (pintype "passive"))
      (node (ref "SJ1") (pin "1") (pinfunction "1_1") (pintype "passive"))
      (node (ref "TP33") (pin "TP") (pinfunction "PP_TP") (pintype "input"))
    )
    (net (code "28") (name "Net-(3C-KL)") (class "Default")
      (node (ref "3") (pin "11") (pinfunction "KL_11") (pintype "passive"))
      (node (ref "D5") (pin "1") (pinfunction "+_1") (pintype "passive"))
      (node (ref "TP34") (pin "TP") (pinfunction "PP_TP") (pintype "input"))
      (node (ref "X1") (pin "19") (pinfunction "19_19") (pintype "passive"))
    )
    (net (code "29") (name "Net-(3E-KL)") (class "Default")
      (node (ref "3") (pin "2") (pinfunction "KL_2") (pintype "passive"))
      (node (ref "Q6") (pin "2") (pinfunction "C_2") (pintype "passive"))
      (node (ref "TP15") (pin "TP") (pinfunction "PP_TP") (pintype "input"))
    )
    (net (code "30") (name "Net-(3F-KL)") (class "Default")
      (node (ref "3") (pin "3") (pinfunction "KL_3") (pintype "passive"))
      (node (ref "IC3") (pin "11") (pinfunction "O6_11") (pintype "open_collector"))
      (node (ref "TP20") (pin "TP") (pinfunction "PP_TP") (pintype "input"))
    )
    (net (code "31") (name "Net-(3G-KL)") (class "Default")
      (node (ref "3") (pin "4") (pinfunction "KL_4") (pintype "passive"))
      (node (ref "IC3") (pin "10") (pinfunction "O7_10") (pintype "open_collector"))
      (node (ref "TP27") (pin "TP") (pinfunction "PP_TP") (pintype "input"))
    )
    (net (code "32") (name "Net-(3H-KL)") (class "Default")
      (node (ref "3") (pin "5") (pinfunction "KL_5") (pintype "passive"))
      (node (ref "IC3") (pin "12") (pinfunction "O5_12") (pintype "open_collector"))
      (node (ref "TP28") (pin "TP") (pinfunction "PP_TP") (pintype "input"))
    )
    (net (code "33") (name "Net-(3I-KL)") (class "Default")
      (node (ref "3") (pin "6") (pinfunction "KL_6") (pintype "passive"))
      (node (ref "IC3") (pin "13") (pinfunction "O4_13") (pintype "open_collector"))
      (node (ref "TP29") (pin "TP") (pinfunction "PP_TP") (pintype "input"))
    )
    (net (code "34") (name "Net-(3J-KL)") (class "Default")
      (node (ref "3") (pin "7") (pinfunction "KL_7") (pintype "passive"))
      (node (ref "IC3") (pin "14") (pinfunction "O3_14") (pintype "open_collector"))
      (node (ref "TP30") (pin "TP") (pinfunction "PP_TP") (pintype "input"))
    )
    (net (code "35") (name "Net-(3K-KL)") (class "Default")
      (node (ref "3") (pin "8") (pinfunction "KL_8") (pintype "passive"))
      (node (ref "R62") (pin "2") (pinfunction "2_2") (pintype "passive"))
      (node (ref "TP31") (pin "TP") (pinfunction "PP_TP") (pintype "input"))
    )
    (net (code "36") (name "Net-(3L-KL)") (class "Default")
      (node (ref "3") (pin "9") (pinfunction "KL_9") (pintype "passive"))
      (node (ref "D3") (pin "1") (pinfunction "+_1") (pintype "passive"))
      (node (ref "TP32") (pin "TP") (pinfunction "PP_TP") (pintype "input"))
      (node (ref "X1") (pin "17") (pinfunction "17_17") (pintype "passive"))
    )
    (net (code "37") (name "Net-(4B-KL)") (class "Default")
      (node (ref "4") (pin "10") (pinfunction "KL_10") (pintype "passive"))
      (node (ref "TP43") (pin "TP") (pinfunction "PP_TP") (pintype "input"))
      (node (ref "X1") (pin "15") (pinfunction "15_15") (pintype "passive"))
    )
    (net (code "38") (name "Net-(4C-KL)") (class "Default")
      (node (ref "4") (pin "11") (pinfunction "KL_11") (pintype "passive"))
      (node (ref "Q8") (pin "2") (pinfunction "C_2") (pintype "passive"))
      (node (ref "R48") (pin "1") (pinfunction "1_1") (pintype "passive"))
      (node (ref "TP44") (pin "TP") (pinfunction "PP_TP") (pintype "input"))
    )
    (net (code "39") (name "Net-(4D-KL)") (class "Default")
      (node (ref "4") (pin "12") (pinfunction "KL_12") (pintype "passive"))
      (node (ref "R49") (pin "1") (pinfunction "1_1") (pintype "passive"))
      (node (ref "TP46") (pin "TP") (pinfunction "PP_TP") (pintype "input"))
    )
    (net (code "40") (name "Net-(4E-KL)") (class "Default")
      (node (ref "4") (pin "2") (pinfunction "KL_2") (pintype "passive"))
      (node (ref "D9") (pin "2") (pinfunction "-_2") (pintype "passive"))
      (node (ref "LED1") (pin "K") (pinfunction "C_K") (pintype "passive"))
      (node (ref "TP35") (pin "TP") (pinfunction "PP_TP") (pintype "input"))
      (node (ref "X1") (pin "12") (pinfunction "12_12") (pintype "passive"))
    )
    (net (code "41") (name "Net-(4F-KL)") (class "Default")
      (node (ref "4") (pin "3") (pinfunction "KL_3") (pintype "passive"))
      (node (ref "D8") (pin "2") (pinfunction "-_2") (pintype "passive"))
      (node (ref "LED2") (pin "K") (pinfunction "C_K") (pintype "passive"))
      (node (ref "TP36") (pin "TP") (pinfunction "PP_TP") (pintype "input"))
      (node (ref "X1") (pin "11") (pinfunction "11_11") (pintype "passive"))
    )
    (net (code "42") (name "Net-(4G-KL)") (class "Default")
      (node (ref "4") (pin "4") (pinfunction "KL_4") (pintype "passive"))
      (node (ref "D7") (pin "2") (pinfunction "-_2") (pintype "passive"))
      (node (ref "LED3") (pin "K") (pinfunction "C_K") (pintype "passive"))
      (node (ref "TP37") (pin "TP") (pinfunction "PP_TP") (pintype "input"))
      (node (ref "X1") (pin "10") (pinfunction "10_10") (pintype "passive"))
    )
    (net (code "43") (name "Net-(4H-KL)") (class "Default")
      (node (ref "4") (pin "5") (pinfunction "KL_5") (pintype "passive"))
      (node (ref "D6") (pin "2") (pinfunction "-_2") (pintype "passive"))
      (node (ref "LED4") (pin "K") (pinfunction "C_K") (pintype "passive"))
      (node (ref "TP38") (pin "TP") (pinfunction "PP_TP") (pintype "input"))
      (node (ref "X1") (pin "9") (pinfunction "9_9") (pintype "passive"))
    )
    (net (code "44") (name "Net-(4I-KL)") (class "Default")
      (node (ref "4") (pin "6") (pinfunction "KL_6") (pintype "passive"))
      (node (ref "JP2") (pin "2") (pinfunction "2_2") (pintype "passive"))
      (node (ref "TP39") (pin "TP") (pinfunction "PP_TP") (pintype "input"))
    )
    (net (code "45") (name "Net-(4J-KL)") (class "Default")
      (node (ref "4") (pin "7") (pinfunction "KL_7") (pintype "passive"))
      (node (ref "LED5") (pin "A") (pinfunction "A_A") (pintype "passive"))
      (node (ref "TP40") (pin "TP") (pinfunction "PP_TP") (pintype "input"))
      (node (ref "X1") (pin "8") (pinfunction "8_8") (pintype "passive"))
    )
    (net (code "46") (name "Net-(4K-KL)") (class "Default")
      (node (ref "4") (pin "8") (pinfunction "KL_8") (pintype "passive"))
      (node (ref "D10") (pin "2") (pinfunction "-_2") (pintype "passive"))
      (node (ref "LED6") (pin "K") (pinfunction "C_K") (pintype "passive"))
      (node (ref "TP41") (pin "TP") (pinfunction "PP_TP") (pintype "input"))
      (node (ref "X1") (pin "14") (pinfunction "14_14") (pintype "passive"))
    )
    (net (code "47") (name "Net-(4L-KL)") (class "Default")
      (node (ref "4") (pin "9") (pinfunction "KL_9") (pintype "passive"))
      (node (ref "D7") (pin "1") (pinfunction "+_1") (pintype "passive"))
      (node (ref "D8") (pin "1") (pinfunction "+_1") (pintype "passive"))
      (node (ref "JP3") (pin "1") (pinfunction "1_1") (pintype "passive"))
      (node (ref "JP4") (pin "2") (pinfunction "2_2") (pintype "passive"))
      (node (ref "TP42") (pin "TP") (pinfunction "PP_TP") (pintype "input"))
    )
    (net (code "48") (name "Net-(5A-KL)") (class "Default")
      (node (ref "5") (pin "1") (pinfunction "KL_1") (pintype "passive"))
      (node (ref "D30") (pin "2") (pinfunction "-_2") (pintype "passive"))
      (node (ref "TP47") (pin "TP") (pinfunction "PP_TP") (pintype "input"))
    )
    (net (code "49") (name "Net-(5B-KL)") (class "Default")
      (node (ref "5") (pin "10") (pinfunction "KL_10") (pintype "passive"))
      (node (ref "D18") (pin "2") (pinfunction "-_2") (pintype "passive"))
      (node (ref "D19") (pin "2") (pinfunction "-_2") (pintype "passive"))
      (node (ref "JP10") (pin "1") (pinfunction "1_1") (pintype "passive"))
      (node (ref "SJ2") (pin "1") (pinfunction "1_1") (pintype "passive"))
      (node (ref "TP56") (pin "TP") (pinfunction "PP_TP") (pintype "input"))
    )
    (net (code "50") (name "Net-(5C-KL)") (class "Default")
      (node (ref "5") (pin "11") (pinfunction "KL_11") (pintype "passive"))
      (node (ref "D19") (pin "1") (pinfunction "+_1") (pintype "passive"))
      (node (ref "TP57") (pin "TP") (pinfunction "PP_TP") (pintype "input"))
      (node (ref "X4") (pin "19") (pinfunction "19_19") (pintype "passive"))
    )
    (net (code "51") (name "Net-(5E-KL)") (class "Default")
      (node (ref "5") (pin "2") (pinfunction "KL_2") (pintype "passive"))
      (node (ref "Q16") (pin "2") (pinfunction "C_2") (pintype "passive"))
      (node (ref "TP48") (pin "TP") (pinfunction "PP_TP") (pintype "input"))
    )
    (net (code "52") (name "Net-(5F-KL)") (class "Default")
      (node (ref "5") (pin "3") (pinfunction "KL_3") (pintype "passive"))
      (node (ref "IC12") (pin "11") (pinfunction "O6_11") (pintype "open_collector"))
      (node (ref "TP49") (pin "TP") (pinfunction "PP_TP") (pintype "input"))
    )
    (net (code "53") (name "Net-(5G-KL)") (class "Default")
      (node (ref "5") (pin "4") (pinfunction "KL_4") (pintype "passive"))
      (node (ref "IC12") (pin "10") (pinfunction "O7_10") (pintype "open_collector"))
      (node (ref "TP50") (pin "TP") (pinfunction "PP_TP") (pintype "input"))
    )
    (net (code "54") (name "Net-(5H-KL)") (class "Default")
      (node (ref "5") (pin "5") (pinfunction "KL_5") (pintype "passive"))
      (node (ref "IC12") (pin "12") (pinfunction "O5_12") (pintype "open_collector"))
      (node (ref "TP51") (pin "TP") (pinfunction "PP_TP") (pintype "input"))
    )
    (net (code "55") (name "Net-(5I-KL)") (class "Default")
      (node (ref "5") (pin "6") (pinfunction "KL_6") (pintype "passive"))
      (node (ref "IC12") (pin "13") (pinfunction "O4_13") (pintype "open_collector"))
      (node (ref "TP52") (pin "TP") (pinfunction "PP_TP") (pintype "input"))
    )
    (net (code "56") (name "Net-(5J-KL)") (class "Default")
      (node (ref "5") (pin "7") (pinfunction "KL_7") (pintype "passive"))
      (node (ref "IC12") (pin "14") (pinfunction "O3_14") (pintype "open_collector"))
      (node (ref "TP53") (pin "TP") (pinfunction "PP_TP") (pintype "input"))
    )
    (net (code "57") (name "Net-(5K-KL)") (class "Default")
      (node (ref "5") (pin "8") (pinfunction "KL_8") (pintype "passive"))
      (node (ref "R161") (pin "2") (pinfunction "2_2") (pintype "passive"))
      (node (ref "TP54") (pin "TP") (pinfunction "PP_TP") (pintype "input"))
    )
    (net (code "58") (name "Net-(5L-KL)") (class "Default")
      (node (ref "5") (pin "9") (pinfunction "KL_9") (pintype "passive"))
      (node (ref "D18") (pin "1") (pinfunction "+_1") (pintype "passive"))
      (node (ref "TP55") (pin "TP") (pinfunction "PP_TP") (pintype "input"))
      (node (ref "X4") (pin "17") (pinfunction "17_17") (pintype "passive"))
    )
    (net (code "59") (name "Net-(6B-KL)") (class "Default")
      (node (ref "6") (pin "10") (pinfunction "KL_10") (pintype "passive"))
      (node (ref "TP66") (pin "TP") (pinfunction "PP_TP") (pintype "input"))
      (node (ref "X4") (pin "15") (pinfunction "15_15") (pintype "passive"))
    )
    (net (code "60") (name "Net-(6C-KL)") (class "Default")
      (node (ref "6") (pin "11") (pinfunction "KL_11") (pintype "passive"))
      (node (ref "Q18") (pin "2") (pinfunction "C_2") (pintype "passive"))
      (node (ref "R147") (pin "1") (pinfunction "1_1") (pintype "passive"))
      (node (ref "TP67") (pin "TP") (pinfunction "PP_TP") (pintype "input"))
    )
    (net (code "61") (name "Net-(6D-KL)") (class "Default")
      (node (ref "6") (pin "12") (pinfunction "KL_12") (pintype "passive"))
      (node (ref "R148") (pin "1") (pinfunction "1_1") (pintype "passive"))
      (node (ref "TP69") (pin "TP") (pinfunction "PP_TP") (pintype "input"))
    )
    (net (code "62") (name "Net-(6E-KL)") (class "Default")
      (node (ref "6") (pin "2") (pinfunction "KL_2") (pintype "passive"))
      (node (ref "D23") (pin "2") (pinfunction "-_2") (pintype "passive"))
      (node (ref "LED7") (pin "K") (pinfunction "C_K") (pintype "passive"))
      (node (ref "TP58") (pin "TP") (pinfunction "PP_TP") (pintype "input"))
      (node (ref "X4") (pin "12") (pinfunction "12_12") (pintype "passive"))
    )
    (net (code "63") (name "Net-(6F-KL)") (class "Default")
      (node (ref "6") (pin "3") (pinfunction "KL_3") (pintype "passive"))
      (node (ref "D22") (pin "2") (pinfunction "-_2") (pintype "passive"))
      (node (ref "LED8") (pin "K") (pinfunction "C_K") (pintype "passive"))
      (node (ref "TP59") (pin "TP") (pinfunction "PP_TP") (pintype "input"))
      (node (ref "X4") (pin "11") (pinfunction "11_11") (pintype "passive"))
    )
    (net (code "64") (name "Net-(6G-KL)") (class "Default")
      (node (ref "6") (pin "4") (pinfunction "KL_4") (pintype "passive"))
      (node (ref "D21") (pin "2") (pinfunction "-_2") (pintype "passive"))
      (node (ref "LED9") (pin "K") (pinfunction "C_K") (pintype "passive"))
      (node (ref "TP60") (pin "TP") (pinfunction "PP_TP") (pintype "input"))
      (node (ref "X4") (pin "10") (pinfunction "10_10") (pintype "passive"))
    )
    (net (code "65") (name "Net-(6H-KL)") (class "Default")
      (node (ref "6") (pin "5") (pinfunction "KL_5") (pintype "passive"))
      (node (ref "D20") (pin "2") (pinfunction "-_2") (pintype "passive"))
      (node (ref "LED10") (pin "K") (pinfunction "C_K") (pintype "passive"))
      (node (ref "TP61") (pin "TP") (pinfunction "PP_TP") (pintype "input"))
      (node (ref "X4") (pin "9") (pinfunction "9_9") (pintype "passive"))
    )
    (net (code "66") (name "Net-(6I-KL)") (class "Default")
      (node (ref "6") (pin "6") (pinfunction "KL_6") (pintype "passive"))
      (node (ref "JP7") (pin "2") (pinfunction "2_2") (pintype "passive"))
      (node (ref "TP62") (pin "TP") (pinfunction "PP_TP") (pintype "input"))
    )
    (net (code "67") (name "Net-(6J-KL)") (class "Default")
      (node (ref "6") (pin "7") (pinfunction "KL_7") (pintype "passive"))
      (node (ref "LED11") (pin "A") (pinfunction "A_A") (pintype "passive"))
      (node (ref "TP63") (pin "TP") (pinfunction "PP_TP") (pintype "input"))
      (node (ref "X4") (pin "8") (pinfunction "8_8") (pintype "passive"))
    )
    (net (code "68") (name "Net-(6K-KL)") (class "Default")
      (node (ref "6") (pin "8") (pinfunction "KL_8") (pintype "passive"))
      (node (ref "D24") (pin "2") (pinfunction "-_2") (pintype "passive"))
      (node (ref "LED12") (pin "K") (pinfunction "C_K") (pintype "passive"))
      (node (ref "TP64") (pin "TP") (pinfunction "PP_TP") (pintype "input"))
      (node (ref "X4") (pin "14") (pinfunction "14_14") (pintype "passive"))
    )
    (net (code "69") (name "Net-(6L-KL)") (class "Default")
      (node (ref "6") (pin "9") (pinfunction "KL_9") (pintype "passive"))
      (node (ref "D21") (pin "1") (pinfunction "+_1") (pintype "passive"))
      (node (ref "D22") (pin "1") (pinfunction "+_1") (pintype "passive"))
      (node (ref "JP8") (pin "1") (pinfunction "1_1") (pintype "passive"))
      (node (ref "JP9") (pin "2") (pinfunction "2_2") (pintype "passive"))
      (node (ref "TP65") (pin "TP") (pinfunction "PP_TP") (pintype "input"))
    )
    (net (code "70") (name "Net-(7A-KL)") (class "Default")
      (node (ref "7") (pin "1") (pinfunction "KL_1") (pintype "passive"))
      (node (ref "D44") (pin "2") (pinfunction "-_2") (pintype "passive"))
      (node (ref "TP70") (pin "TP") (pinfunction "PP_TP") (pintype "input"))
    )
    (net (code "71") (name "Net-(7B-KL)") (class "Default")
      (node (ref "7") (pin "10") (pinfunction "KL_10") (pintype "passive"))
      (node (ref "D32") (pin "2") (pinfunction "-_2") (pintype "passive"))
      (node (ref "D33") (pin "2") (pinfunction "-_2") (pintype "passive"))
      (node (ref "JP15") (pin "1") (pinfunction "1_1") (pintype "passive"))
      (node (ref "SJ3") (pin "1") (pinfunction "1_1") (pintype "passive"))
      (node (ref "TP79") (pin "TP") (pinfunction "PP_TP") (pintype "input"))
    )
    (net (code "72") (name "Net-(7C-KL)") (class "Default")
      (node (ref "7") (pin "11") (pinfunction "KL_11") (pintype "passive"))
      (node (ref "D33") (pin "1") (pinfunction "+_1") (pintype "passive"))
      (node (ref "TP80") (pin "TP") (pinfunction "PP_TP") (pintype "input"))
      (node (ref "X7") (pin "19") (pinfunction "19_19") (pintype "passive"))
    )
    (net (code "73") (name "Net-(7E-KL)") (class "Default")
      (node (ref "7") (pin "2") (pinfunction "KL_2") (pintype "passive"))
      (node (ref "Q26") (pin "2") (pinfunction "C_2") (pintype "passive"))
      (node (ref "TP71") (pin "TP") (pinfunction "PP_TP") (pintype "input"))
    )
    (net (code "74") (name "Net-(7F-KL)") (class "Default")
      (node (ref "7") (pin "3") (pinfunction "KL_3") (pintype "passive"))
      (node (ref "IC21") (pin "11") (pinfunction "O6_11") (pintype "open_collector"))
      (node (ref "TP72") (pin "TP") (pinfunction "PP_TP") (pintype "input"))
    )
    (net (code "75") (name "Net-(7G-KL)") (class "Default")
      (node (ref "7") (pin "4") (pinfunction "KL_4") (pintype "passive"))
      (node (ref "IC21") (pin "10") (pinfunction "O7_10") (pintype "open_collector"))
      (node (ref "TP73") (pin "TP") (pinfunction "PP_TP") (pintype "input"))
    )
    (net (code "76") (name "Net-(7H-KL)") (class "Default")
      (node (ref "7") (pin "5") (pinfunction "KL_5") (pintype "passive"))
      (node (ref "IC21") (pin "12") (pinfunction "O5_12") (pintype "open_collector"))
      (node (ref "TP74") (pin "TP") (pinfunction "PP_TP") (pintype "input"))
    )
    (net (code "77") (name "Net-(7I-KL)") (class "Default")
      (node (ref "7") (pin "6") (pinfunction "KL_6") (pintype "passive"))
      (node (ref "IC21") (pin "13") (pinfunction "O4_13") (pintype "open_collector"))
      (node (ref "TP75") (pin "TP") (pinfunction "PP_TP") (pintype "input"))
    )
    (net (code "78") (name "Net-(7J-KL)") (class "Default")
      (node (ref "7") (pin "7") (pinfunction "KL_7") (pintype "passive"))
      (node (ref "IC21") (pin "14") (pinfunction "O3_14") (pintype "open_collector"))
      (node (ref "TP76") (pin "TP") (pinfunction "PP_TP") (pintype "input"))
    )
    (net (code "79") (name "Net-(7K-KL)") (class "Default")
      (node (ref "7") (pin "8") (pinfunction "KL_8") (pintype "passive"))
      (node (ref "R216") (pin "2") (pinfunction "2_2") (pintype "passive"))
      (node (ref "TP77") (pin "TP") (pinfunction "PP_TP") (pintype "input"))
    )
    (net (code "80") (name "Net-(7L-KL)") (class "Default")
      (node (ref "7") (pin "9") (pinfunction "KL_9") (pintype "passive"))
      (node (ref "D32") (pin "1") (pinfunction "+_1") (pintype "passive"))
      (node (ref "TP78") (pin "TP") (pinfunction "PP_TP") (pintype "input"))
      (node (ref "X7") (pin "17") (pinfunction "17_17") (pintype "passive"))
    )
    (net (code "81") (name "Net-(8B-KL)") (class "Default")
      (node (ref "8") (pin "10") (pinfunction "KL_10") (pintype "passive"))
      (node (ref "TP89") (pin "TP") (pinfunction "PP_TP") (pintype "input"))
      (node (ref "X7") (pin "15") (pinfunction "15_15") (pintype "passive"))
    )
    (net (code "82") (name "Net-(8C-KL)") (class "Default")
      (node (ref "8") (pin "11") (pinfunction "KL_11") (pintype "passive"))
      (node (ref "Q28") (pin "2") (pinfunction "C_2") (pintype "passive"))
      (node (ref "R202") (pin "1") (pinfunction "1_1") (pintype "passive"))
      (node (ref "TP90") (pin "TP") (pinfunction "PP_TP") (pintype "input"))
    )
    (net (code "83") (name "Net-(8D-KL)") (class "Default")
      (node (ref "8") (pin "12") (pinfunction "KL_12") (pintype "passive"))
      (node (ref "R203") (pin "1") (pinfunction "1_1") (pintype "passive"))
      (node (ref "TP92") (pin "TP") (pinfunction "PP_TP") (pintype "input"))
    )
    (net (code "84") (name "Net-(8E-KL)") (class "Default")
      (node (ref "8") (pin "2") (pinfunction "KL_2") (pintype "passive"))
      (node (ref "D37") (pin "2") (pinfunction "-_2") (pintype "passive"))
      (node (ref "LED13") (pin "K") (pinfunction "C_K") (pintype "passive"))
      (node (ref "TP81") (pin "TP") (pinfunction "PP_TP") (pintype "input"))
      (node (ref "X7") (pin "12") (pinfunction "12_12") (pintype "passive"))
    )
    (net (code "85") (name "Net-(8F-KL)") (class "Default")
      (node (ref "8") (pin "3") (pinfunction "KL_3") (pintype "passive"))
      (node (ref "D36") (pin "2") (pinfunction "-_2") (pintype "passive"))
      (node (ref "LED14") (pin "K") (pinfunction "C_K") (pintype "passive"))
      (node (ref "TP82") (pin "TP") (pinfunction "PP_TP") (pintype "input"))
      (node (ref "X7") (pin "11") (pinfunction "11_11") (pintype "passive"))
    )
    (net (code "86") (name "Net-(8G-KL)") (class "Default")
      (node (ref "8") (pin "4") (pinfunction "KL_4") (pintype "passive"))
      (node (ref "D35") (pin "2") (pinfunction "-_2") (pintype "passive"))
      (node (ref "LED15") (pin "K") (pinfunction "C_K") (pintype "passive"))
      (node (ref "TP83") (pin "TP") (pinfunction "PP_TP") (pintype "input"))
      (node (ref "X7") (pin "10") (pinfunction "10_10") (pintype "passive"))
    )
    (net (code "87") (name "Net-(8H-KL)") (class "Default")
      (node (ref "8") (pin "5") (pinfunction "KL_5") (pintype "passive"))
      (node (ref "D34") (pin "2") (pinfunction "-_2") (pintype "passive"))
      (node (ref "LED16") (pin "K") (pinfunction "C_K") (pintype "passive"))
      (node (ref "TP84") (pin "TP") (pinfunction "PP_TP") (pintype "input"))
      (node (ref "X7") (pin "9") (pinfunction "9_9") (pintype "passive"))
    )
    (net (code "88") (name "Net-(8I-KL)") (class "Default")
      (node (ref "8") (pin "6") (pinfunction "KL_6") (pintype "passive"))
      (node (ref "JP12") (pin "2") (pinfunction "2_2") (pintype "passive"))
      (node (ref "TP85") (pin "TP") (pinfunction "PP_TP") (pintype "input"))
    )
    (net (code "89") (name "Net-(8J-KL)") (class "Default")
      (node (ref "8") (pin "7") (pinfunction "KL_7") (pintype "passive"))
      (node (ref "LED17") (pin "A") (pinfunction "A_A") (pintype "passive"))
      (node (ref "TP86") (pin "TP") (pinfunction "PP_TP") (pintype "input"))
      (node (ref "X7") (pin "8") (pinfunction "8_8") (pintype "passive"))
    )
    (net (code "90") (name "Net-(8K-KL)") (class "Default")
      (node (ref "8") (pin "8") (pinfunction "KL_8") (pintype "passive"))
      (node (ref "D38") (pin "2") (pinfunction "-_2") (pintype "passive"))
      (node (ref "LED18") (pin "K") (pinfunction "C_K") (pintype "passive"))
      (node (ref "TP87") (pin "TP") (pinfunction "PP_TP") (pintype "input"))
      (node (ref "X7") (pin "14") (pinfunction "14_14") (pintype "passive"))
    )
    (net (code "91") (name "Net-(8L-KL)") (class "Default")
      (node (ref "8") (pin "9") (pinfunction "KL_9") (pintype "passive"))
      (node (ref "D35") (pin "1") (pinfunction "+_1") (pintype "passive"))
      (node (ref "D36") (pin "1") (pinfunction "+_1") (pintype "passive"))
      (node (ref "JP13") (pin "1") (pinfunction "1_1") (pintype "passive"))
      (node (ref "JP14") (pin "2") (pinfunction "2_2") (pintype "passive"))
      (node (ref "TP88") (pin "TP") (pinfunction "PP_TP") (pintype "input"))
    )
    (net (code "92") (name "Net-(9A-KL)") (class "Default")
      (node (ref "9") (pin "1") (pinfunction "KL_1") (pintype "passive"))
      (node (ref "D58") (pin "2") (pinfunction "-_2") (pintype "passive"))
      (node (ref "TP93") (pin "TP") (pinfunction "PP_TP") (pintype "input"))
    )
    (net (code "93") (name "Net-(9B-KL)") (class "Default")
      (node (ref "9") (pin "10") (pinfunction "KL_10") (pintype "passive"))
      (node (ref "D46") (pin "2") (pinfunction "-_2") (pintype "passive"))
      (node (ref "D47") (pin "2") (pinfunction "-_2") (pintype "passive"))
      (node (ref "JP20") (pin "1") (pinfunction "1_1") (pintype "passive"))
      (node (ref "SJ4") (pin "1") (pinfunction "1_1") (pintype "passive"))
      (node (ref "TP102") (pin "TP") (pinfunction "PP_TP") (pintype "input"))
    )
    (net (code "94") (name "Net-(9C-KL)") (class "Default")
      (node (ref "9") (pin "11") (pinfunction "KL_11") (pintype "passive"))
      (node (ref "D47") (pin "1") (pinfunction "+_1") (pintype "passive"))
      (node (ref "TP103") (pin "TP") (pinfunction "PP_TP") (pintype "input"))
      (node (ref "X10") (pin "19") (pinfunction "19_19") (pintype "passive"))
    )
    (net (code "95") (name "Net-(9E-KL)") (class "Default")
      (node (ref "9") (pin "2") (pinfunction "KL_2") (pintype "passive"))
      (node (ref "Q36") (pin "2") (pinfunction "C_2") (pintype "passive"))
      (node (ref "TP94") (pin "TP") (pinfunction "PP_TP") (pintype "input"))
    )
    (net (code "96") (name "Net-(9F-KL)") (class "Default")
      (node (ref "9") (pin "3") (pinfunction "KL_3") (pintype "passive"))
      (node (ref "IC30") (pin "11") (pinfunction "O6_11") (pintype "open_collector"))
      (node (ref "TP95") (pin "TP") (pinfunction "PP_TP") (pintype "input"))
    )
    (net (code "97") (name "Net-(9G-KL)") (class "Default")
      (node (ref "9") (pin "4") (pinfunction "KL_4") (pintype "passive"))
      (node (ref "IC30") (pin "10") (pinfunction "O7_10") (pintype "open_collector"))
      (node (ref "TP96") (pin "TP") (pinfunction "PP_TP") (pintype "input"))
    )
    (net (code "98") (name "Net-(9H-KL)") (class "Default")
      (node (ref "9") (pin "5") (pinfunction "KL_5") (pintype "passive"))
      (node (ref "IC30") (pin "12") (pinfunction "O5_12") (pintype "open_collector"))
      (node (ref "TP97") (pin "TP") (pinfunction "PP_TP") (pintype "input"))
    )
    (net (code "99") (name "Net-(9I-KL)") (class "Default")
      (node (ref "9") (pin "6") (pinfunction "KL_6") (pintype "passive"))
      (node (ref "IC30") (pin "13") (pinfunction "O4_13") (pintype "open_collector"))
      (node (ref "TP98") (pin "TP") (pinfunction "PP_TP") (pintype "input"))
    )
    (net (code "100") (name "Net-(9J-KL)") (class "Default")
      (node (ref "9") (pin "7") (pinfunction "KL_7") (pintype "passive"))
      (node (ref "IC30") (pin "14") (pinfunction "O3_14") (pintype "open_collector"))
      (node (ref "TP99") (pin "TP") (pinfunction "PP_TP") (pintype "input"))
    )
    (net (code "101") (name "Net-(9K-KL)") (class "Default")
      (node (ref "9") (pin "8") (pinfunction "KL_8") (pintype "passive"))
      (node (ref "R271") (pin "2") (pinfunction "2_2") (pintype "passive"))
      (node (ref "TP100") (pin "TP") (pinfunction "PP_TP") (pintype "input"))
    )
    (net (code "102") (name "Net-(9L-KL)") (class "Default")
      (node (ref "9") (pin "9") (pinfunction "KL_9") (pintype "passive"))
      (node (ref "D46") (pin "1") (pinfunction "+_1") (pintype "passive"))
      (node (ref "TP101") (pin "TP") (pinfunction "PP_TP") (pintype "input"))
      (node (ref "X10") (pin "17") (pinfunction "17_17") (pintype "passive"))
    )
    (net (code "103") (name "Net-(10B-KL)") (class "Default")
      (node (ref "10") (pin "10") (pinfunction "KL_10") (pintype "passive"))
      (node (ref "TP112") (pin "TP") (pinfunction "PP_TP") (pintype "input"))
      (node (ref "X10") (pin "15") (pinfunction "15_15") (pintype "passive"))
    )
    (net (code "104") (name "Net-(10C-KL)") (class "Default")
      (node (ref "10") (pin "11") (pinfunction "KL_11") (pintype "passive"))
      (node (ref "Q38") (pin "2") (pinfunction "C_2") (pintype "passive"))
      (node (ref "R257") (pin "1") (pinfunction "1_1") (pintype "passive"))
      (node (ref "TP113") (pin "TP") (pinfunction "PP_TP") (pintype "input"))
    )
    (net (code "105") (name "Net-(10D-KL)") (class "Default")
      (node (ref "10") (pin "12") (pinfunction "KL_12") (pintype "passive"))
      (node (ref "R258") (pin "1") (pinfunction "1_1") (pintype "passive"))
      (node (ref "TP115") (pin "TP") (pinfunction "PP_TP") (pintype "input"))
    )
    (net (code "106") (name "Net-(10E-KL)") (class "Default")
      (node (ref "10") (pin "2") (pinfunction "KL_2") (pintype "passive"))
      (node (ref "D51") (pin "2") (pinfunction "-_2") (pintype "passive"))
      (node (ref "LED19") (pin "K") (pinfunction "C_K") (pintype "passive"))
      (node (ref "TP104") (pin "TP") (pinfunction "PP_TP") (pintype "input"))
      (node (ref "X10") (pin "12") (pinfunction "12_12") (pintype "passive"))
    )
    (net (code "107") (name "Net-(10F-KL)") (class "Default")
      (node (ref "10") (pin "3") (pinfunction "KL_3") (pintype "passive"))
      (node (ref "D50") (pin "2") (pinfunction "-_2") (pintype "passive"))
      (node (ref "LED20") (pin "K") (pinfunction "C_K") (pintype "passive"))
      (node (ref "TP105") (pin "TP") (pinfunction "PP_TP") (pintype "input"))
      (node (ref "X10") (pin "11") (pinfunction "11_11") (pintype "passive"))
    )
    (net (code "108") (name "Net-(10G-KL)") (class "Default")
      (node (ref "10") (pin "4") (pinfunction "KL_4") (pintype "passive"))
      (node (ref "D49") (pin "2") (pinfunction "-_2") (pintype "passive"))
      (node (ref "LED21") (pin "K") (pinfunction "C_K") (pintype "passive"))
      (node (ref "TP106") (pin "TP") (pinfunction "PP_TP") (pintype "input"))
      (node (ref "X10") (pin "10") (pinfunction "10_10") (pintype "passive"))
    )
    (net (code "109") (name "Net-(10H-KL)") (class "Default")
      (node (ref "10") (pin "5") (pinfunction "KL_5") (pintype "passive"))
      (node (ref "D48") (pin "2") (pinfunction "-_2") (pintype "passive"))
      (node (ref "LED22") (pin "K") (pinfunction "C_K") (pintype "passive"))
      (node (ref "TP107") (pin "TP") (pinfunction "PP_TP") (pintype "input"))
      (node (ref "X10") (pin "9") (pinfunction "9_9") (pintype "passive"))
    )
    (net (code "110") (name "Net-(10I-KL)") (class "Default")
      (node (ref "10") (pin "6") (pinfunction "KL_6") (pintype "passive"))
      (node (ref "JP17") (pin "2") (pinfunction "2_2") (pintype "passive"))
      (node (ref "TP108") (pin "TP") (pinfunction "PP_TP") (pintype "input"))
    )
    (net (code "111") (name "Net-(10J-KL)") (class "Default")
      (node (ref "10") (pin "7") (pinfunction "KL_7") (pintype "passive"))
      (node (ref "LED23") (pin "A") (pinfunction "A_A") (pintype "passive"))
      (node (ref "TP109") (pin "TP") (pinfunction "PP_TP") (pintype "input"))
      (node (ref "X10") (pin "8") (pinfunction "8_8") (pintype "passive"))
    )
    (net (code "112") (name "Net-(10K-KL)") (class "Default")
      (node (ref "10") (pin "8") (pinfunction "KL_8") (pintype "passive"))
      (node (ref "D52") (pin "2") (pinfunction "-_2") (pintype "passive"))
      (node (ref "LED24") (pin "K") (pinfunction "C_K") (pintype "passive"))
      (node (ref "TP110") (pin "TP") (pinfunction "PP_TP") (pintype "input"))
      (node (ref "X10") (pin "14") (pinfunction "14_14") (pintype "passive"))
    )
    (net (code "113") (name "Net-(10L-KL)") (class "Default")
      (node (ref "10") (pin "9") (pinfunction "KL_9") (pintype "passive"))
      (node (ref "D49") (pin "1") (pinfunction "+_1") (pintype "passive"))
      (node (ref "D50") (pin "1") (pinfunction "+_1") (pintype "passive"))
      (node (ref "JP18") (pin "1") (pinfunction "1_1") (pintype "passive"))
      (node (ref "JP19") (pin "2") (pinfunction "2_2") (pintype "passive"))
      (node (ref "TP111") (pin "TP") (pinfunction "PP_TP") (pintype "input"))
    )
    (net (code "114") (name "Net-(11A-KL)") (class "Default")
      (node (ref "11") (pin "1") (pinfunction "KL_1") (pintype "passive"))
      (node (ref "D72") (pin "2") (pinfunction "-_2") (pintype "passive"))
      (node (ref "TP116") (pin "TP") (pinfunction "PP_TP") (pintype "input"))
    )
    (net (code "115") (name "Net-(11B-KL)") (class "Default")
      (node (ref "11") (pin "10") (pinfunction "KL_10") (pintype "passive"))
      (node (ref "D60") (pin "2") (pinfunction "-_2") (pintype "passive"))
      (node (ref "D61") (pin "2") (pinfunction "-_2") (pintype "passive"))
      (node (ref "JP25") (pin "1") (pinfunction "1_1") (pintype "passive"))
      (node (ref "SJ5") (pin "1") (pinfunction "1_1") (pintype "passive"))
      (node (ref "TP125") (pin "TP") (pinfunction "PP_TP") (pintype "input"))
    )
    (net (code "116") (name "Net-(11C-KL)") (class "Default")
      (node (ref "11") (pin "11") (pinfunction "KL_11") (pintype "passive"))
      (node (ref "D61") (pin "1") (pinfunction "+_1") (pintype "passive"))
      (node (ref "TP126") (pin "TP") (pinfunction "PP_TP") (pintype "input"))
      (node (ref "X13") (pin "19") (pinfunction "19_19") (pintype "passive"))
    )
    (net (code "117") (name "Net-(11E-KL)") (class "Default")
      (node (ref "11") (pin "2") (pinfunction "KL_2") (pintype "passive"))
      (node (ref "Q46") (pin "2") (pinfunction "C_2") (pintype "passive"))
      (node (ref "TP117") (pin "TP") (pinfunction "PP_TP") (pintype "input"))
    )
    (net (code "118") (name "Net-(11F-KL)") (class "Default")
      (node (ref "11") (pin "3") (pinfunction "KL_3") (pintype "passive"))
      (node (ref "IC39") (pin "11") (pinfunction "O6_11") (pintype "open_collector"))
      (node (ref "TP118") (pin "TP") (pinfunction "PP_TP") (pintype "input"))
    )
    (net (code "119") (name "Net-(11G-KL)") (class "Default")
      (node (ref "11") (pin "4") (pinfunction "KL_4") (pintype "passive"))
      (node (ref "IC39") (pin "10") (pinfunction "O7_10") (pintype "open_collector"))
      (node (ref "TP119") (pin "TP") (pinfunction "PP_TP") (pintype "input"))
    )
    (net (code "120") (name "Net-(11H-KL)") (class "Default")
      (node (ref "11") (pin "5") (pinfunction "KL_5") (pintype "passive"))
      (node (ref "IC39") (pin "12") (pinfunction "O5_12") (pintype "open_collector"))
      (node (ref "TP120") (pin "TP") (pinfunction "PP_TP") (pintype "input"))
    )
    (net (code "121") (name "Net-(11I-KL)") (class "Default")
      (node (ref "11") (pin "6") (pinfunction "KL_6") (pintype "passive"))
      (node (ref "IC39") (pin "13") (pinfunction "O4_13") (pintype "open_collector"))
      (node (ref "TP121") (pin "TP") (pinfunction "PP_TP") (pintype "input"))
    )
    (net (code "122") (name "Net-(11J-KL)") (class "Default")
      (node (ref "11") (pin "7") (pinfunction "KL_7") (pintype "passive"))
      (node (ref "IC39") (pin "14") (pinfunction "O3_14") (pintype "open_collector"))
      (node (ref "TP122") (pin "TP") (pinfunction "PP_TP") (pintype "input"))
    )
    (net (code "123") (name "Net-(11K-KL)") (class "Default")
      (node (ref "11") (pin "8") (pinfunction "KL_8") (pintype "passive"))
      (node (ref "R326") (pin "2") (pinfunction "2_2") (pintype "passive"))
      (node (ref "TP123") (pin "TP") (pinfunction "PP_TP") (pintype "input"))
    )
    (net (code "124") (name "Net-(11L-KL)") (class "Default")
      (node (ref "11") (pin "9") (pinfunction "KL_9") (pintype "passive"))
      (node (ref "D60") (pin "1") (pinfunction "+_1") (pintype "passive"))
      (node (ref "TP124") (pin "TP") (pinfunction "PP_TP") (pintype "input"))
      (node (ref "X13") (pin "17") (pinfunction "17_17") (pintype "passive"))
    )
    (net (code "125") (name "Net-(12B-KL)") (class "Default")
      (node (ref "12") (pin "10") (pinfunction "KL_10") (pintype "passive"))
      (node (ref "TP135") (pin "TP") (pinfunction "PP_TP") (pintype "input"))
      (node (ref "X13") (pin "15") (pinfunction "15_15") (pintype "passive"))
    )
    (net (code "126") (name "Net-(12C-KL)") (class "Default")
      (node (ref "12") (pin "11") (pinfunction "KL_11") (pintype "passive"))
      (node (ref "Q48") (pin "2") (pinfunction "C_2") (pintype "passive"))
      (node (ref "R312") (pin "1") (pinfunction "1_1") (pintype "passive"))
      (node (ref "TP136") (pin "TP") (pinfunction "PP_TP") (pintype "input"))
    )
    (net (code "127") (name "Net-(12D-KL)") (class "Default")
      (node (ref "12") (pin "12") (pinfunction "KL_12") (pintype "passive"))
      (node (ref "R313") (pin "1") (pinfunction "1_1") (pintype "passive"))
      (node (ref "TP138") (pin "TP") (pinfunction "PP_TP") (pintype "input"))
    )
    (net (code "128") (name "Net-(12E-KL)") (class "Default")
      (node (ref "12") (pin "2") (pinfunction "KL_2") (pintype "passive"))
      (node (ref "D65") (pin "2") (pinfunction "-_2") (pintype "passive"))
      (node (ref "LED25") (pin "K") (pinfunction "C_K") (pintype "passive"))
      (node (ref "TP127") (pin "TP") (pinfunction "PP_TP") (pintype "input"))
      (node (ref "X13") (pin "12") (pinfunction "12_12") (pintype "passive"))
    )
    (net (code "129") (name "Net-(12F-KL)") (class "Default")
      (node (ref "12") (pin "3") (pinfunction "KL_3") (pintype "passive"))
      (node (ref "D64") (pin "2") (pinfunction "-_2") (pintype "passive"))
      (node (ref "LED26") (pin "K") (pinfunction "C_K") (pintype "passive"))
      (node (ref "TP128") (pin "TP") (pinfunction "PP_TP") (pintype "input"))
      (node (ref "X13") (pin "11") (pinfunction "11_11") (pintype "passive"))
    )
    (net (code "130") (name "Net-(12G-KL)") (class "Default")
      (node (ref "12") (pin "4") (pinfunction "KL_4") (pintype "passive"))
      (node (ref "D63") (pin "2") (pinfunction "-_2") (pintype "passive"))
      (node (ref "LED27") (pin "K") (pinfunction "C_K") (pintype "passive"))
      (node (ref "TP129") (pin "TP") (pinfunction "PP_TP") (pintype "input"))
      (node (ref "X13") (pin "10") (pinfunction "10_10") (pintype "passive"))
    )
    (net (code "131") (name "Net-(12H-KL)") (class "Default")
      (node (ref "12") (pin "5") (pinfunction "KL_5") (pintype "passive"))
      (node (ref "D62") (pin "2") (pinfunction "-_2") (pintype "passive"))
      (node (ref "LED28") (pin "K") (pinfunction "C_K") (pintype "passive"))
      (node (ref "TP130") (pin "TP") (pinfunction "PP_TP") (pintype "input"))
      (node (ref "X13") (pin "9") (pinfunction "9_9") (pintype "passive"))
    )
    (net (code "132") (name "Net-(12I-KL)") (class "Default")
      (node (ref "12") (pin "6") (pinfunction "KL_6") (pintype "passive"))
      (node (ref "JP22") (pin "2") (pinfunction "2_2") (pintype "passive"))
      (node (ref "TP131") (pin "TP") (pinfunction "PP_TP") (pintype "input"))
    )
    (net (code "133") (name "Net-(12J-KL)") (class "Default")
      (node (ref "12") (pin "7") (pinfunction "KL_7") (pintype "passive"))
      (node (ref "LED29") (pin "A") (pinfunction "A_A") (pintype "passive"))
      (node (ref "TP132") (pin "TP") (pinfunction "PP_TP") (pintype "input"))
      (node (ref "X13") (pin "8") (pinfunction "8_8") (pintype "passive"))
    )
    (net (code "134") (name "Net-(12K-KL)") (class "Default")
      (node (ref "12") (pin "8") (pinfunction "KL_8") (pintype "passive"))
      (node (ref "D66") (pin "2") (pinfunction "-_2") (pintype "passive"))
      (node (ref "LED30") (pin "K") (pinfunction "C_K") (pintype "passive"))
      (node (ref "TP133") (pin "TP") (pinfunction "PP_TP") (pintype "input"))
      (node (ref "X13") (pin "14") (pinfunction "14_14") (pintype "passive"))
    )
    (net (code "135") (name "Net-(12L-KL)") (class "Default")
      (node (ref "12") (pin "9") (pinfunction "KL_9") (pintype "passive"))
      (node (ref "D63") (pin "1") (pinfunction "+_1") (pintype "passive"))
      (node (ref "D64") (pin "1") (pinfunction "+_1") (pintype "passive"))
      (node (ref "JP23") (pin "1") (pinfunction "1_1") (pintype "passive"))
      (node (ref "JP24") (pin "2") (pinfunction "2_2") (pintype "passive"))
      (node (ref "TP134") (pin "TP") (pinfunction "PP_TP") (pintype "input"))
    )
    (net (code "136") (name "Net-(C1-Pad1)") (class "Default")
      (node (ref "C1") (pin "1") (pinfunction "1_1") (pintype "passive"))
      (node (ref "R22") (pin "1") (pinfunction "1_1") (pintype "passive"))
      (node (ref "R23") (pin "2") (pinfunction "2_2") (pintype "passive"))
    )
    (net (code "137") (name "Net-(C11-Pad1)") (class "Default")
      (node (ref "C11") (pin "1") (pinfunction "1_1") (pintype "passive"))
      (node (ref "R50") (pin "1") (pinfunction "1_1") (pintype "passive"))
      (node (ref "R51") (pin "1") (pinfunction "1_1") (pintype "passive"))
    )
    (net (code "138") (name "Net-(C14-Pad1)") (class "Default")
      (node (ref "C14") (pin "1") (pinfunction "1_1") (pintype "passive"))
      (node (ref "R77") (pin "1") (pinfunction "1_1") (pintype "passive"))
      (node (ref "R78") (pin "2") (pinfunction "2_2") (pintype "passive"))
    )
    (net (code "139") (name "Net-(C24-Pad1)") (class "Default")
      (node (ref "C24") (pin "1") (pinfunction "1_1") (pintype "passive"))
      (node (ref "R149") (pin "1") (pinfunction "1_1") (pintype "passive"))
      (node (ref "R150") (pin "1") (pinfunction "1_1") (pintype "passive"))
    )
    (net (code "140") (name "Net-(C27-Pad1)") (class "Default")
      (node (ref "C27") (pin "1") (pinfunction "1_1") (pintype "passive"))
      (node (ref "R176") (pin "1") (pinfunction "1_1") (pintype "passive"))
      (node (ref "R177") (pin "2") (pinfunction "2_2") (pintype "passive"))
    )
    (net (code "141") (name "Net-(C36-Pad1)") (class "Default")
      (node (ref "C36") (pin "1") (pinfunction "1_1") (pintype "passive"))
      (node (ref "R204") (pin "1") (pinfunction "1_1") (pintype "passive"))
      (node (ref "R205") (pin "1") (pinfunction "1_1") (pintype "passive"))
    )
    (net (code "142") (name "Net-(C39-Pad1)") (class "Default")
      (node (ref "C39") (pin "1") (pinfunction "1_1") (pintype "passive"))
      (node (ref "R231") (pin "1") (pinfunction "1_1") (pintype "passive"))
      (node (ref "R232") (pin "2") (pinfunction "2_2") (pintype "passive"))
    )
    (net (code "143") (name "Net-(C48-Pad1)") (class "Default")
      (node (ref "C48") (pin "1") (pinfunction "1_1") (pintype "passive"))
      (node (ref "R259") (pin "1") (pinfunction "1_1") (pintype "passive"))
      (node (ref "R260") (pin "1") (pinfunction "1_1") (pintype "passive"))
    )
    (net (code "144") (name "Net-(C51-Pad1)") (class "Default")
      (node (ref "C51") (pin "1") (pinfunction "1_1") (pintype "passive"))
      (node (ref "R286") (pin "1") (pinfunction "1_1") (pintype "passive"))
      (node (ref "R287") (pin "2") (pinfunction "2_2") (pintype "passive"))
    )
    (net (code "145") (name "Net-(C60-Pad1)") (class "Default")
      (node (ref "C60") (pin "1") (pinfunction "1_1") (pintype "passive"))
      (node (ref "R314") (pin "1") (pinfunction "1_1") (pintype "passive"))
      (node (ref "R315") (pin "1") (pinfunction "1_1") (pintype "passive"))
    )
    (net (code "146") (name "Net-(C103-Pad1)") (class "Default")
      (node (ref "C103") (pin "1") (pinfunction "1_1") (pintype "passive"))
      (node (ref "R108") (pin "1") (pinfunction "1_1") (pintype "passive"))
      (node (ref "R112") (pin "1") (pinfunction "1_1") (pintype "passive"))
    )
    (net (code "147") (name "Net-(C107-Pad1)") (class "Default")
      (node (ref "C107") (pin "1") (pinfunction "1_1") (pintype "passive"))
      (node (ref "R125") (pin "1") (pinfunction "1_1") (pintype "passive"))
      (node (ref "R130") (pin "2") (pinfunction "2_2") (pintype "passive"))
    )
    (net (code "148") (name "Net-(D1--)") (class "Default")
      (node (ref "D1") (pin "2") (pinfunction "-_2") (pintype "passive"))
      (node (ref "R12") (pin "1") (pinfunction "1_1") (pintype "passive"))
      (node (ref "R13") (pin "1") (pinfunction "1_1") (pintype "passive"))
    )
    (net (code "149") (name "Net-(D2-+)") (class "Default")
      (node (ref "D2") (pin "1") (pinfunction "+_1") (pintype "passive"))
      (node (ref "X101") (pin "1") (pinfunction "1_1") (pintype "passive"))
    )
    (net (code "150") (name "Net-(D6-+)") (class "Default")
      (node (ref "D6") (pin "1") (pinfunction "+_1") (pintype "passive"))
      (node (ref "R7") (pin "1") (pinfunction "1_1") (pintype "passive"))
    )
    (net (code "151") (name "Net-(D9-+)") (class "Default")
      (node (ref "D9") (pin "1") (pinfunction "+_1") (pintype "passive"))
      (node (ref "JP3") (pin "2") (pinfunction "2_2") (pintype "passive"))
    )
    (net (code "152") (name "Net-(D10-+)") (class "Default")
      (node (ref "D10") (pin "1") (pinfunction "+_1") (pintype "passive"))
      (node (ref "JP4") (pin "1") (pinfunction "1_1") (pintype "passive"))
    )
    (net (code "153") (name "Net-(D11--)") (class "Default")
      (node (ref "D11") (pin "2") (pinfunction "-_2") (pintype "passive"))
      (node (ref "Q4") (pin "2") (pinfunction "C_2") (pintype "passive"))
      (node (ref "START1") (pin "TP") (pinfunction "PP_TP") (pintype "input"))
      (node (ref "X1") (pin "5") (pinfunction "5_5") (pintype "passive"))
    )
    (net (code "154") (name "Net-(D12-+)") (class "Default")
      (node (ref "D12") (pin "1") (pinfunction "+_1") (pintype "passive"))
      (node (ref "R44") (pin "1") (pinfunction "1_1") (pintype "passive"))
    )
    (net (code "155") (name "Net-(D12--)") (class "Default")
      (node (ref "C8") (pin "2") (pinfunction "2_2") (pintype "passive"))
      (node (ref "D12") (pin "2") (pinfunction "-_2") (pintype "passive"))
      (node (ref "D17") (pin "C") (pinfunction "C_C") (pintype "passive"))
      (node (ref "IC6") (pin "2") (pinfunction "TR_2") (pintype "input"))
      (node (ref "IC6") (pin "6") (pinfunction "THR_6") (pintype "input"))
      (node (ref "R42") (pin "1") (pinfunction "1_1") (pintype "passive"))
    )
    (net (code "156") (name "Net-(D14-PadC)") (class "Default")
      (node (ref "D14") (pin "C") (pinfunction "C_C") (pintype "passive"))
      (node (ref "R18") (pin "2") (pinfunction "2_2") (pintype "passive"))
      (node (ref "X1") (pin "22") (pinfunction "22_22") (pintype "passive"))
    )
    (net (code "157") (name "Net-(D15--)") (class "Default")
      (node (ref "D15") (pin "2") (pinfunction "-_2") (pintype "passive"))
      (node (ref "R65") (pin "1") (pinfunction "1_1") (pintype "passive"))
      (node (ref "R66") (pin "1") (pinfunction "1_1") (pintype "passive"))
    )
    (net (code "158") (name "Net-(D16-+)") (class "Default")
      (node (ref "D16") (pin "1") (pinfunction "+_1") (pintype "passive"))
      (node (ref "X1") (pin "1") (pinfunction "1_1") (pintype "passive"))
    )
    (net (code "159") (name "Net-(D20-+)") (class "Default")
      (node (ref "D20") (pin "1") (pinfunction "+_1") (pintype "passive"))
      (node (ref "R67") (pin "1") (pinfunction "1_1") (pintype "passive"))
    )
    (net (code "160") (name "Net-(D23-+)") (class "Default")
      (node (ref "D23") (pin "1") (pinfunction "+_1") (pintype "passive"))
      (node (ref "JP8") (pin "2") (pinfunction "2_2") (pintype "passive"))
    )
    (net (code "161") (name "Net-(D24-+)") (class "Default")
      (node (ref "D24") (pin "1") (pinfunction "+_1") (pintype "passive"))
      (node (ref "JP9") (pin "1") (pinfunction "1_1") (pintype "passive"))
    )
    (net (code "162") (name "Net-(D25--)") (class "Default")
      (node (ref "D25") (pin "2") (pinfunction "-_2") (pintype "passive"))
      (node (ref "Q14") (pin "2") (pinfunction "C_2") (pintype "passive"))
      (node (ref "START2") (pin "TP") (pinfunction "PP_TP") (pintype "input"))
      (node (ref "X4") (pin "5") (pinfunction "5_5") (pintype "passive"))
    )
    (net (code "163") (name "Net-(D26-+)") (class "Default")
      (node (ref "D26") (pin "1") (pinfunction "+_1") (pintype "passive"))
      (node (ref "R99") (pin "1") (pinfunction "1_1") (pintype "passive"))
    )
    (net (code "164") (name "Net-(D26--)") (class "Default")
      (node (ref "C21") (pin "2") (pinfunction "2_2") (pintype "passive"))
      (node (ref "D26") (pin "2") (pinfunction "-_2") (pintype "passive"))
      (node (ref "D31") (pin "C") (pinfunction "C_C") (pintype "passive"))
      (node (ref "IC15") (pin "2") (pinfunction "TR_2") (pintype "input"))
      (node (ref "IC15") (pin "6") (pinfunction "THR_6") (pintype "input"))
      (node (ref "R97") (pin "1") (pinfunction "1_1") (pintype "passive"))
    )
    (net (code "165") (name "Net-(D28-PadC)") (class "Default")
      (node (ref "D28") (pin "C") (pinfunction "C_C") (pintype "passive"))
      (node (ref "R73") (pin "2") (pinfunction "2_2") (pintype "passive"))
      (node (ref "X4") (pin "22") (pinfunction "22_22") (pintype "passive"))
    )
    (net (code "166") (name "Net-(D29--)") (class "Default")
      (node (ref "D29") (pin "2") (pinfunction "-_2") (pintype "passive"))
      (node (ref "R164") (pin "1") (pinfunction "1_1") (pintype "passive"))
      (node (ref "R165") (pin "1") (pinfunction "1_1") (pintype "passive"))
    )
    (net (code "167") (name "Net-(D30-+)") (class "Default")
      (node (ref "D30") (pin "1") (pinfunction "+_1") (pintype "passive"))
      (node (ref "X4") (pin "1") (pinfunction "1_1") (pintype "passive"))
    )
    (net (code "168") (name "Net-(D34-+)") (class "Default")
      (node (ref "D34") (pin "1") (pinfunction "+_1") (pintype "passive"))
      (node (ref "R166") (pin "1") (pinfunction "1_1") (pintype "passive"))
    )
    (net (code "169") (name "Net-(D37-+)") (class "Default")
      (node (ref "D37") (pin "1") (pinfunction "+_1") (pintype "passive"))
      (node (ref "JP13") (pin "2") (pinfunction "2_2") (pintype "passive"))
    )
    (net (code "170") (name "Net-(D38-+)") (class "Default")
      (node (ref "D38") (pin "1") (pinfunction "+_1") (pintype "passive"))
      (node (ref "JP14") (pin "1") (pinfunction "1_1") (pintype "passive"))
    )
    (net (code "171") (name "Net-(D39--)") (class "Default")
      (node (ref "D39") (pin "2") (pinfunction "-_2") (pintype "passive"))
      (node (ref "Q24") (pin "2") (pinfunction "C_2") (pintype "passive"))
      (node (ref "START3") (pin "TP") (pinfunction "PP_TP") (pintype "input"))
      (node (ref "X7") (pin "5") (pinfunction "5_5") (pintype "passive"))
    )
    (net (code "172") (name "Net-(D40-+)") (class "Default")
      (node (ref "D40") (pin "1") (pinfunction "+_1") (pintype "passive"))
      (node (ref "R198") (pin "1") (pinfunction "1_1") (pintype "passive"))
    )
    (net (code "173") (name "Net-(D40--)") (class "Default")
      (node (ref "C33") (pin "2") (pinfunction "2_2") (pintype "passive"))
      (node (ref "D40") (pin "2") (pinfunction "-_2") (pintype "passive"))
      (node (ref "D45") (pin "C") (pinfunction "C_C") (pintype "passive"))
      (node (ref "IC24") (pin "2") (pinfunction "TR_2") (pintype "input"))
      (node (ref "IC24") (pin "6") (pinfunction "THR_6") (pintype "input"))
      (node (ref "R196") (pin "1") (pinfunction "1_1") (pintype "passive"))
    )
    (net (code "174") (name "Net-(D42-PadC)") (class "Default")
      (node (ref "D42") (pin "C") (pinfunction "C_C") (pintype "passive"))
      (node (ref "R172") (pin "2") (pinfunction "2_2") (pintype "passive"))
      (node (ref "X7") (pin "22") (pinfunction "22_22") (pintype "passive"))
    )
    (net (code "175") (name "Net-(D43--)") (class "Default")
      (node (ref "D43") (pin "2") (pinfunction "-_2") (pintype "passive"))
      (node (ref "R219") (pin "1") (pinfunction "1_1") (pintype "passive"))
      (node (ref "R220") (pin "1") (pinfunction "1_1") (pintype "passive"))
    )
    (net (code "176") (name "Net-(D44-+)") (class "Default")
      (node (ref "D44") (pin "1") (pinfunction "+_1") (pintype "passive"))
      (node (ref "X7") (pin "1") (pinfunction "1_1") (pintype "passive"))
    )
    (net (code "177") (name "Net-(D48-+)") (class "Default")
      (node (ref "D48") (pin "1") (pinfunction "+_1") (pintype "passive"))
      (node (ref "R221") (pin "1") (pinfunction "1_1") (pintype "passive"))
    )
    (net (code "178") (name "Net-(D51-+)") (class "Default")
      (node (ref "D51") (pin "1") (pinfunction "+_1") (pintype "passive"))
      (node (ref "JP18") (pin "2") (pinfunction "2_2") (pintype "passive"))
    )
    (net (code "179") (name "Net-(D52-+)") (class "Default")
      (node (ref "D52") (pin "1") (pinfunction "+_1") (pintype "passive"))
      (node (ref "JP19") (pin "1") (pinfunction "1_1") (pintype "passive"))
    )
    (net (code "180") (name "Net-(D53--)") (class "Default")
      (node (ref "D53") (pin "2") (pinfunction "-_2") (pintype "passive"))
      (node (ref "Q34") (pin "2") (pinfunction "C_2") (pintype "passive"))
      (node (ref "START4") (pin "TP") (pinfunction "PP_TP") (pintype "input"))
      (node (ref "X10") (pin "5") (pinfunction "5_5") (pintype "passive"))
    )
    (net (code "181") (name "Net-(D54-+)") (class "Default")
      (node (ref "D54") (pin "1") (pinfunction "+_1") (pintype "passive"))
      (node (ref "R253") (pin "1") (pinfunction "1_1") (pintype "passive"))
    )
    (net (code "182") (name "Net-(D54--)") (class "Default")
      (node (ref "C45") (pin "2") (pinfunction "2_2") (pintype "passive"))
      (node (ref "D54") (pin "2") (pinfunction "-_2") (pintype "passive"))
      (node (ref "D59") (pin "C") (pinfunction "C_C") (pintype "passive"))
      (node (ref "IC33") (pin "2") (pinfunction "TR_2") (pintype "input"))
      (node (ref "IC33") (pin "6") (pinfunction "THR_6") (pintype "input"))
      (node (ref "R251") (pin "1") (pinfunction "1_1") (pintype "passive"))
    )
    (net (code "183") (name "Net-(D56-PadC)") (class "Default")
      (node (ref "D56") (pin "C") (pinfunction "C_C") (pintype "passive"))
      (node (ref "R227") (pin "2") (pinfunction "2_2") (pintype "passive"))
      (node (ref "X10") (pin "22") (pinfunction "22_22") (pintype "passive"))
    )
    (net (code "184") (name "Net-(D57--)") (class "Default")
      (node (ref "D57") (pin "2") (pinfunction "-_2") (pintype "passive"))
      (node (ref "R274") (pin "1") (pinfunction "1_1") (pintype "passive"))
      (node (ref "R275") (pin "1") (pinfunction "1_1") (pintype "passive"))
    )
    (net (code "185") (name "Net-(D58-+)") (class "Default")
      (node (ref "D58") (pin "1") (pinfunction "+_1") (pintype "passive"))
      (node (ref "X10") (pin "1") (pinfunction "1_1") (pintype "passive"))
    )
    (net (code "186") (name "Net-(D62-+)") (class "Default")
      (node (ref "D62") (pin "1") (pinfunction "+_1") (pintype "passive"))
      (node (ref "R276") (pin "1") (pinfunction "1_1") (pintype "passive"))
    )
    (net (code "187") (name "Net-(D65-+)") (class "Default")
      (node (ref "D65") (pin "1") (pinfunction "+_1") (pintype "passive"))
      (node (ref "JP23") (pin "2") (pinfunction "2_2") (pintype "passive"))
    )
    (net (code "188") (name "Net-(D66-+)") (class "Default")
      (node (ref "D66") (pin "1") (pinfunction "+_1") (pintype "passive"))
      (node (ref "JP24") (pin "1") (pinfunction "1_1") (pintype "passive"))
    )
    (net (code "189") (name "Net-(D67--)") (class "Default")
      (node (ref "D67") (pin "2") (pinfunction "-_2") (pintype "passive"))
      (node (ref "Q44") (pin "2") (pinfunction "C_2") (pintype "passive"))
      (node (ref "START5") (pin "TP") (pinfunction "PP_TP") (pintype "input"))
      (node (ref "X13") (pin "5") (pinfunction "5_5") (pintype "passive"))
    )
    (net (code "190") (name "Net-(D68-+)") (class "Default")
      (node (ref "D68") (pin "1") (pinfunction "+_1") (pintype "passive"))
      (node (ref "R308") (pin "1") (pinfunction "1_1") (pintype "passive"))
    )
    (net (code "191") (name "Net-(D68--)") (class "Default")
      (node (ref "C57") (pin "2") (pinfunction "2_2") (pintype "passive"))
      (node (ref "D68") (pin "2") (pinfunction "-_2") (pintype "passive"))
      (node (ref "D73") (pin "C") (pinfunction "C_C") (pintype "passive"))
      (node (ref "IC42") (pin "2") (pinfunction "TR_2") (pintype "input"))
      (node (ref "IC42") (pin "6") (pinfunction "THR_6") (pintype "input"))
      (node (ref "R306") (pin "1") (pinfunction "1_1") (pintype "passive"))
    )
    (net (code "192") (name "Net-(D70-PadC)") (class "Default")
      (node (ref "D70") (pin "C") (pinfunction "C_C") (pintype "passive"))
      (node (ref "R282") (pin "2") (pinfunction "2_2") (pintype "passive"))
      (node (ref "X13") (pin "22") (pinfunction "22_22") (pintype "passive"))
    )
    (net (code "193") (name "Net-(D71--)") (class "Default")
      (node (ref "D71") (pin "2") (pinfunction "-_2") (pintype "passive"))
      (node (ref "R329") (pin "1") (pinfunction "1_1") (pintype "passive"))
      (node (ref "R330") (pin "1") (pinfunction "1_1") (pintype "passive"))
    )
    (net (code "194") (name "Net-(D72-+)") (class "Default")
      (node (ref "D72") (pin "1") (pinfunction "+_1") (pintype "passive"))
      (node (ref "X13") (pin "1") (pinfunction "1_1") (pintype "passive"))
    )
    (net (code "195") (name "Net-(D104-PadC)") (class "Default")
      (node (ref "D104") (pin "C") (pinfunction "C_C") (pintype "passive"))
      (node (ref "R105") (pin "2") (pinfunction "2_2") (pintype "passive"))
      (node (ref "X101") (pin "22") (pinfunction "22_22") (pintype "passive"))
    )
    (net (code "196") (name "Net-(D105--)") (class "Default")
      (node (ref "D105") (pin "2") (pinfunction "-_2") (pintype "passive"))
      (node (ref "Q104") (pin "2") (pinfunction "C_2") (pintype "passive"))
      (node (ref "START") (pin "TP") (pinfunction "PP_TP") (pintype "input"))
      (node (ref "X101") (pin "5") (pinfunction "5_5") (pintype "passive"))
    )
    (net (code "197") (name "Net-(D106-+)") (class "Default")
      (node (ref "D106") (pin "1") (pinfunction "+_1") (pintype "passive"))
      (node (ref "R127") (pin "1") (pinfunction "1_1") (pintype "passive"))
    )
    (net (code "198") (name "Net-(D109-+)") (class "Default")
      (node (ref "D109") (pin "1") (pinfunction "+_1") (pintype "passive"))
      (node (ref "JP102") (pin "2") (pinfunction "2_2") (pintype "passive"))
    )
    (net (code "199") (name "Net-(D110-+)") (class "Default")
      (node (ref "D110") (pin "1") (pinfunction "+_1") (pintype "passive"))
      (node (ref "JP103") (pin "1") (pinfunction "1_1") (pintype "passive"))
    )
    (net (code "200") (name "Net-(D112-+)") (class "Default")
      (node (ref "D112") (pin "1") (pinfunction "+_1") (pintype "passive"))
      (node (ref "R140") (pin "1") (pinfunction "1_1") (pintype "passive"))
    )
    (net (code "201") (name "Net-(D112--)") (class "Default")
      (node (ref "C109") (pin "2") (pinfunction "2_2") (pintype "passive"))
      (node (ref "D112") (pin "2") (pinfunction "-_2") (pintype "passive"))
      (node (ref "D4") (pin "C") (pinfunction "C_C") (pintype "passive"))
      (node (ref "IC110") (pin "2") (pinfunction "TR_2") (pintype "input"))
      (node (ref "IC110") (pin "6") (pinfunction "THR_6") (pintype "input"))
      (node (ref "R141") (pin "1") (pinfunction "1_1") (pintype "passive"))
    )
    (net (code "202") (name "Net-(IC1A-A)") (class "Default")
      (node (ref "IC1") (pin "10") (pinfunction "A_10") (pintype "input"))
      (node (ref "R17") (pin "1") (pinfunction "1_1") (pintype "passive"))
      (node (ref "R58") (pin "1") (pinfunction "1_1") (pintype "passive"))
      (node (ref "R58") (pin "2") (pinfunction "2_2") (pintype "passive"))
      (node (ref "X1") (pin "4") (pinfunction "4_4") (pintype "passive"))
      (node (ref "X2") (pin "2") (pinfunction "S_2") (pintype "passive"))
    )
    (net (code "203") (name "Net-(IC1A-B)") (class "Default")
      (node (ref "IC1") (pin "13") (pinfunction "B_13") (pintype "input"))
      (node (ref "R16") (pin "1") (pinfunction "1_1") (pintype "passive"))
      (node (ref "R57") (pin "1") (pinfunction "1_1") (pintype "passive"))
      (node (ref "R57") (pin "2") (pinfunction "2_2") (pintype "passive"))
      (node (ref "X1") (pin "3") (pinfunction "3_3") (pintype "passive"))
      (node (ref "X2") (pin "3") (pinfunction "S_3") (pintype "passive"))
    )
    (net (code "204") (name "Net-(IC1A-C)") (class "Default")
      (node (ref "IC1") (pin "12") (pinfunction "C_12") (pintype "input"))
      (node (ref "R15") (pin "1") (pinfunction "1_1") (pintype "passive"))
      (node (ref "R56") (pin "1") (pinfunction "1_1") (pintype "passive"))
      (node (ref "R56") (pin "2") (pinfunction "2_2") (pintype "passive"))
      (node (ref "X1") (pin "2") (pinfunction "2_2") (pintype "passive"))
      (node (ref "X2") (pin "4") (pinfunction "S_4") (pintype "passive"))
    )
    (net (code "205") (name "Net-(IC1A-Q0)") (class "Default")
      (node (ref "IC1") (pin "3") (pinfunction "Q0_3") (pintype "output"))
      (node (ref "IC3") (pin "1") (pinfunction "I1_1") (pintype "input"))
      (node (ref "IC3") (pin "2") (pinfunction "I2_2") (pintype "input"))
      (node (ref "Q10") (pin "1") (pinfunction "G_1") (pintype "passive"))
      (node (ref "Q11") (pin "1") (pinfunction "G_1") (pintype "passive"))
    )
    (net (code "206") (name "Net-(IC1A-Q1)") (class "Default")
      (node (ref "IC1") (pin "14") (pinfunction "Q1_14") (pintype "output"))
      (node (ref "IC3") (pin "6") (pinfunction "I6_6") (pintype "input"))
    )
    (net (code "207") (name "Net-(IC1A-Q2)") (class "Default")
      (node (ref "IC1") (pin "2") (pinfunction "Q2_2") (pintype "output"))
      (node (ref "IC3") (pin "7") (pinfunction "I7_7") (pintype "input"))
    )
    (net (code "208") (name "Net-(IC1A-Q3)") (class "Default")
      (node (ref "IC1") (pin "15") (pinfunction "Q3_15") (pintype "output"))
      (node (ref "IC3") (pin "5") (pinfunction "I5_5") (pintype "input"))
    )
    (net (code "209") (name "Net-(IC1A-Q4)") (class "Default")
      (node (ref "IC1") (pin "1") (pinfunction "Q4_1") (pintype "output"))
      (node (ref "IC3") (pin "4") (pinfunction "I4_4") (pintype "input"))
    )
    (net (code "210") (name "Net-(IC1A-Q5)") (class "Default")
      (node (ref "IC1") (pin "6") (pinfunction "Q5_6") (pintype "output"))
      (node (ref "IC3") (pin "3") (pinfunction "I3_3") (pintype "input"))
    )
    (net (code "211") (name "Net-(IC2-ADJ)") (class "Default")
      (node (ref "IC2") (pin "1") (pinfunction "ADJ_1") (pintype "input"))
      (node (ref "R11") (pin "1") (pinfunction "1_1") (pintype "passive"))
      (node (ref "R20") (pin "2") (pinfunction "2_2") (pintype "passive"))
      (node (ref "X1") (pin "7") (pinfunction "7_7") (pintype "passive"))
    )
    (net (code "212") (name "Net-(IC2-VI)") (class "Default")
      (node (ref "IC2") (pin "3") (pinfunction "VI_3") (pintype "input"))
      (node (ref "Q7") (pin "2") (pinfunction "C_2") (pintype "passive"))
    )
    (net (code "213") (name "Net-(IC2-VO)") (class "Default")
      (node (ref "IC2") (pin "2") (pinfunction "VO_2") (pintype "passive"))
      (node (ref "R11") (pin "2") (pinfunction "2_2") (pintype "passive"))
    )
    (net (code "214") (name "Net-(IC3-O1)") (class "Default")
      (node (ref "IC3") (pin "16") (pinfunction "O1_16") (pintype "open_collector"))
      (node (ref "Q10") (pin "3") (pinfunction "D_3") (pintype "passive"))
      (node (ref "R62") (pin "1") (pinfunction "1_1") (pintype "passive"))
    )
    (net (code "215") (name "Net-(IC3-O2)") (class "Default")
      (node (ref "IC3") (pin "15") (pinfunction "O2_15") (pintype "open_collector"))
      (node (ref "R35") (pin "1") (pinfunction "1_1") (pintype "passive"))
    )
    (net (code "216") (name "Net-(IC4A-+IN)") (class "Default")
      (node (ref "IC4") (pin "11") (pinfunction "+IN_11") (pintype "input"))
      (node (ref "IC4") (pin "5") (pinfunction "+IN_5") (pintype "input"))
      (node (ref "R24") (pin "1") (pinfunction "1_1") (pintype "passive"))
      (node (ref "R25") (pin "2") (pinfunction "2_2") (pintype "passive"))
      (node (ref "R26") (pin "2") (pinfunction "2_2") (pintype "passive"))
    )
    (net (code "217") (name "Net-(IC4A--IN)") (class "Default")
      (node (ref "C3") (pin "1") (pinfunction "1_1") (pintype "passive"))
      (node (ref "IC4") (pin "10") (pinfunction "-IN_10") (pintype "input"))
      (node (ref "IC4") (pin "4") (pinfunction "-IN_4") (pintype "input"))
      (node (ref "R23") (pin "1") (pinfunction "1_1") (pintype "passive"))
    )
    (net (code "218") (name "Net-(IC4A-OUT)") (class "Default")
      (node (ref "IC4") (pin "2") (pinfunction "OUT_2") (pintype "open_collector"))
      (node (ref "R26") (pin "1") (pinfunction "1_1") (pintype "passive"))
    )
    (net (code "219") (name "Net-(IC4B-+IN)") (class "Default")
      (node (ref "IC4") (pin "7") (pinfunction "+IN_7") (pintype "input"))
      (node (ref "R21") (pin "1") (pinfunction "1_1") (pintype "passive"))
      (node (ref "R38") (pin "1") (pinfunction "1_1") (pintype "passive"))
    )
    (net (code "220") (name "Net-(IC4B--IN)") (class "Default")
      (node (ref "IC4") (pin "6") (pinfunction "-IN_6") (pintype "input"))
      (node (ref "IC4") (pin "8") (pinfunction "-IN_8") (pintype "input"))
      (node (ref "R20") (pin "1") (pinfunction "1_1") (pintype "passive"))
    )
    (net (code "221") (name "Net-(IC4B-OUT)") (class "Default")
      (node (ref "IC4") (pin "1") (pinfunction "OUT_1") (pintype "open_collector"))
      (node (ref "R22") (pin "2") (pinfunction "2_2") (pintype "passive"))
      (node (ref "R27") (pin "2") (pinfunction "2_2") (pintype "passive"))
    )
    (net (code "222") (name "Net-(IC4C-+IN)") (class "Default")
      (node (ref "C6") (pin "1") (pinfunction "1_1") (pintype "passive"))
      (node (ref "IC4") (pin "9") (pinfunction "+IN_9") (pintype "input"))
      (node (ref "R29") (pin "2") (pinfunction "2_2") (pintype "passive"))
      (node (ref "R38") (pin "2") (pinfunction "2_2") (pintype "passive"))
    )
    (net (code "223") (name "Net-(IC4C-OUT)") (class "Default")
      (node (ref "C7") (pin "2") (pinfunction "2_2") (pintype "passive"))
      (node (ref "IC4") (pin "14") (pinfunction "OUT_14") (pintype "open_collector"))
      (node (ref "R28") (pin "2") (pinfunction "2_2") (pintype "passive"))
    )
    (net (code "224") (name "Net-(IC4D-OUT)") (class "Default")
      (node (ref "IC4") (pin "13") (pinfunction "OUT_13") (pintype "open_collector"))
      (node (ref "JP2") (pin "1") (pinfunction "1_1") (pintype "passive"))
      (node (ref "Q9") (pin "1") (pinfunction "G_1") (pintype "passive"))
      (node (ref "R41") (pin "2") (pinfunction "2_2") (pintype "passive"))
    )
    (net (code "225") (name "Net-(IC6-CV)") (class "Default")
      (node (ref "IC6") (pin "5") (pinfunction "CV_5") (pintype "input"))
      (node (ref "R43") (pin "2") (pinfunction "2_2") (pintype "passive"))
    )
    (net (code "226") (name "Net-(IC6-Q)") (class "Default")
      (node (ref "IC6") (pin "3") (pinfunction "Q_3") (pintype "output"))
      (node (ref "IC7") (pin "12") (pinfunction "A_12") (pintype "input"))
      (node (ref "IC7") (pin "4") (pinfunction "A_4") (pintype "input"))
      (node (ref "R43") (pin "1") (pinfunction "1_1") (pintype "passive"))
    )
    (net (code "227") (name "Net-(IC7A-T2)") (class "Default")
      (node (ref "C12") (pin "2") (pinfunction "2_2") (pintype "passive"))
      (node (ref "IC7") (pin "2") (pinfunction "T2_2") (pintype "input"))
      (node (ref "R64") (pin "1") (pinfunction "1_1") (pintype "passive"))
    )
    (net (code "228") (name "Net-(IC7A-~{Q})") (class "Default")
      (node (ref "IC7") (pin "7") (pinfunction "~{Q}_7") (pintype "output"))
      (node (ref "Q13") (pin "1") (pinfunction "G_1") (pintype "passive"))
    )
    (net (code "229") (name "Net-(IC7B-B)") (class "Default")
      (node (ref "IC7") (pin "11") (pinfunction "B_11") (pintype "input"))
      (node (ref "IC7") (pin "9") (pinfunction "~{Q}_9") (pintype "output"))
      (node (ref "R49") (pin "2") (pinfunction "2_2") (pintype "passive"))
    )
    (net (code "230") (name "Net-(IC7B-T2)") (class "Default")
      (node (ref "C10") (pin "1") (pinfunction "1_1") (pintype "passive"))
      (node (ref "IC7") (pin "14") (pinfunction "T2_14") (pintype "input"))
      (node (ref "R47") (pin "1") (pinfunction "1_1") (pintype "passive"))
    )
    (net (code "231") (name "Net-(IC9A-+IN)") (class "Default")
      (node (ref "C5") (pin "1") (pinfunction "1_1") (pintype "passive"))
      (node (ref "IC9") (pin "3") (pinfunction "+IN_3") (pintype "input"))
      (node (ref "R18") (pin "1") (pinfunction "1_1") (pintype "passive"))
    )
    (net (code "232") (name "Net-(IC9A--IN)") (class "Default")
      (node (ref "IC9") (pin "2") (pinfunction "-IN_2") (pintype "input"))
      (node (ref "R19") (pin "2") (pinfunction "2_2") (pintype "passive"))
    )
    (net (code "233") (name "Net-(IC9A-OUT)") (class "Default")
      (node (ref "IC9") (pin "1") (pinfunction "OUT_1") (pintype "output"))
      (node (ref "R50") (pin "2") (pinfunction "2_2") (pintype "passive"))
    )
    (net (code "234") (name "Net-(IC9B-+IN)") (class "Default")
      (node (ref "IC9") (pin "5") (pinfunction "+IN_5") (pintype "input"))
      (node (ref "Q11") (pin "3") (pinfunction "D_3") (pintype "passive"))
      (node (ref "R51") (pin "2") (pinfunction "2_2") (pintype "passive"))
      (node (ref "R52") (pin "2") (pinfunction "2_2") (pintype "passive"))
    )
    (net (code "235") (name "Net-(IC9B--IN)") (class "Default")
      (node (ref "IC9") (pin "6") (pinfunction "-IN_6") (pintype "input"))
      (node (ref "R53") (pin "1") (pinfunction "1_1") (pintype "passive"))
      (node (ref "R54") (pin "2") (pinfunction "2_2") (pintype "passive"))
    )
    (net (code "236") (name "Net-(IC9B-OUT)") (class "Default")
      (node (ref "IC9") (pin "7") (pinfunction "OUT_7") (pintype "output"))
      (node (ref "R32") (pin "2") (pinfunction "2_2") (pintype "passive"))
      (node (ref "R39") (pin "1") (pinfunction "1_1") (pintype "passive"))
      (node (ref "R52") (pin "1") (pinfunction "1_1") (pintype "passive"))
    )
    (net (code "237") (name "Net-(IC10A-A)") (class "Default")
      (node (ref "IC10") (pin "10") (pinfunction "A_10") (pintype "input"))
      (node (ref "R157") (pin "1") (pinfunction "1_1") (pintype "passive"))
      (node (ref "R157") (pin "2") (pinfunction "2_2") (pintype "passive"))
      (node (ref "R72") (pin "1") (pinfunction "1_1") (pintype "passive"))
      (node (ref "X4") (pin "4") (pinfunction "4_4") (pintype "passive"))
      (node (ref "X5") (pin "2") (pinfunction "S_2") (pintype "passive"))
    )
    (net (code "238") (name "Net-(IC10A-B)") (class "Default")
      (node (ref "IC10") (pin "13") (pinfunction "B_13") (pintype "input"))
      (node (ref "R156") (pin "1") (pinfunction "1_1") (pintype "passive"))
      (node (ref "R156") (pin "2") (pinfunction "2_2") (pintype "passive"))
      (node (ref "R71") (pin "1") (pinfunction "1_1") (pintype "passive"))
      (node (ref "X4") (pin "3") (pinfunction "3_3") (pintype "passive"))
      (node (ref "X5") (pin "3") (pinfunction "S_3") (pintype "passive"))
    )
    (net (code "239") (name "Net-(IC10A-C)") (class "Default")
      (node (ref "IC10") (pin "12") (pinfunction "C_12") (pintype "input"))
      (node (ref "R155") (pin "1") (pinfunction "1_1") (pintype "passive"))
      (node (ref "R155") (pin "2") (pinfunction "2_2") (pintype "passive"))
      (node (ref "R70") (pin "1") (pinfunction "1_1") (pintype "passive"))
      (node (ref "X4") (pin "2") (pinfunction "2_2") (pintype "passive"))
      (node (ref "X5") (pin "4") (pinfunction "S_4") (pintype "passive"))
    )
    (net (code "240") (name "Net-(IC10A-Q0)") (class "Default")
      (node (ref "IC10") (pin "3") (pinfunction "Q0_3") (pintype "output"))
      (node (ref "IC12") (pin "1") (pinfunction "I1_1") (pintype "input"))
      (node (ref "IC12") (pin "2") (pinfunction "I2_2") (pintype "input"))
      (node (ref "Q20") (pin "1") (pinfunction "G_1") (pintype "passive"))
      (node (ref "Q21") (pin "1") (pinfunction "G_1") (pintype "passive"))
    )
    (net (code "241") (name "Net-(IC10A-Q1)") (class "Default")
      (node (ref "IC10") (pin "14") (pinfunction "Q1_14") (pintype "output"))
      (node (ref "IC12") (pin "6") (pinfunction "I6_6") (pintype "input"))
    )
    (net (code "242") (name "Net-(IC10A-Q2)") (class "Default")
      (node (ref "IC10") (pin "2") (pinfunction "Q2_2") (pintype "output"))
      (node (ref "IC12") (pin "7") (pinfunction "I7_7") (pintype "input"))
    )
    (net (code "243") (name "Net-(IC10A-Q3)") (class "Default")
      (node (ref "IC10") (pin "15") (pinfunction "Q3_15") (pintype "output"))
      (node (ref "IC12") (pin "5") (pinfunction "I5_5") (pintype "input"))
    )
    (net (code "244") (name "Net-(IC10A-Q4)") (class "Default")
      (node (ref "IC10") (pin "1") (pinfunction "Q4_1") (pintype "output"))
      (node (ref "IC12") (pin "4") (pinfunction "I4_4") (pintype "input"))
    )
    (net (code "245") (name "Net-(IC10A-Q5)") (class "Default")
      (node (ref "IC10") (pin "6") (pinfunction "Q5_6") (pintype "output"))
      (node (ref "IC12") (pin "3") (pinfunction "I3_3") (pintype "input"))
    )
    (net (code "246") (name "Net-(IC11-ADJ)") (class "Default")
      (node (ref "IC11") (pin "1") (pinfunction "ADJ_1") (pintype "input"))
      (node (ref "R68") (pin "1") (pinfunction "1_1") (pintype "passive"))
      (node (ref "R75") (pin "2") (pinfunction "2_2") (pintype "passive"))
      (node (ref "X4") (pin "7") (pinfunction "7_7") (pintype "passive"))
    )
    (net (code "247") (name "Net-(IC11-VI)") (class "Default")
      (node (ref "IC11") (pin "3") (pinfunction "VI_3") (pintype "input"))
      (node (ref "Q17") (pin "2") (pinfunction "C_2") (pintype "passive"))
    )
    (net (code "248") (name "Net-(IC11-VO)") (class "Default")
      (node (ref "IC11") (pin "2") (pinfunction "VO_2") (pintype "passive"))
      (node (ref "R68") (pin "2") (pinfunction "2_2") (pintype "passive"))
    )
    (net (code "249") (name "Net-(IC12-O1)") (class "Default")
      (node (ref "IC12") (pin "16") (pinfunction "O1_16") (pintype "open_collector"))
      (node (ref "Q20") (pin "3") (pinfunction "D_3") (pintype "passive"))
      (node (ref "R161") (pin "1") (pinfunction "1_1") (pintype "passive"))
    )
    (net (code "250") (name "Net-(IC12-O2)") (class "Default")
      (node (ref "IC12") (pin "15") (pinfunction "O2_15") (pintype "open_collector"))
      (node (ref "R90") (pin "1") (pinfunction "1_1") (pintype "passive"))
    )
    (net (code "251") (name "Net-(IC13A-+IN)") (class "Default")
      (node (ref "IC13") (pin "11") (pinfunction "+IN_11") (pintype "input"))
      (node (ref "IC13") (pin "5") (pinfunction "+IN_5") (pintype "input"))
      (node (ref "R79") (pin "1") (pinfunction "1_1") (pintype "passive"))
      (node (ref "R80") (pin "2") (pinfunction "2_2") (pintype "passive"))
      (node (ref "R81") (pin "2") (pinfunction "2_2") (pintype "passive"))
    )
    (net (code "252") (name "Net-(IC13A--IN)") (class "Default")
      (node (ref "C16") (pin "1") (pinfunction "1_1") (pintype "passive"))
      (node (ref "IC13") (pin "10") (pinfunction "-IN_10") (pintype "input"))
      (node (ref "IC13") (pin "4") (pinfunction "-IN_4") (pintype "input"))
      (node (ref "R78") (pin "1") (pinfunction "1_1") (pintype "passive"))
    )
    (net (code "253") (name "Net-(IC13A-OUT)") (class "Default")
      (node (ref "IC13") (pin "2") (pinfunction "OUT_2") (pintype "open_collector"))
      (node (ref "R81") (pin "1") (pinfunction "1_1") (pintype "passive"))
    )
    (net (code "254") (name "Net-(IC13B-+IN)") (class "Default")
      (node (ref "IC13") (pin "7") (pinfunction "+IN_7") (pintype "input"))
      (node (ref "R76") (pin "1") (pinfunction "1_1") (pintype "passive"))
      (node (ref "R93") (pin "1") (pinfunction "1_1") (pintype "passive"))
    )
    (net (code "255") (name "Net-(IC13B--IN)") (class "Default")
      (node (ref "IC13") (pin "6") (pinfunction "-IN_6") (pintype "input"))
      (node (ref "IC13") (pin "8") (pinfunction "-IN_8") (pintype "input"))
      (node (ref "R75") (pin "1") (pinfunction "1_1") (pintype "passive"))
    )
    (net (code "256") (name "Net-(IC13B-OUT)") (class "Default")
      (node (ref "IC13") (pin "1") (pinfunction "OUT_1") (pintype "open_collector"))
      (node (ref "R77") (pin "2") (pinfunction "2_2") (pintype "passive"))
      (node (ref "R82") (pin "2") (pinfunction "2_2") (pintype "passive"))
    )
    (net (code "257") (name "Net-(IC13C-+IN)") (class "Default")
      (node (ref "C19") (pin "1") (pinfunction "1_1") (pintype "passive"))
      (node (ref "IC13") (pin "9") (pinfunction "+IN_9") (pintype "input"))
      (node (ref "R84") (pin "2") (pinfunction "2_2") (pintype "passive"))
      (node (ref "R93") (pin "2") (pinfunction "2_2") (pintype "passive"))
    )
    (net (code "258") (name "Net-(IC13C-OUT)") (class "Default")
      (node (ref "C20") (pin "2") (pinfunction "2_2") (pintype "passive"))
      (node (ref "IC13") (pin "14") (pinfunction "OUT_14") (pintype "open_collector"))
      (node (ref "R83") (pin "2") (pinfunction "2_2") (pintype "passive"))
    )
    (net (code "259") (name "Net-(IC13D-OUT)") (class "Default")
      (node (ref "IC13") (pin "13") (pinfunction "OUT_13") (pintype "open_collector"))
      (node (ref "JP7") (pin "1") (pinfunction "1_1") (pintype "passive"))
      (node (ref "Q19") (pin "1") (pinfunction "G_1") (pintype "passive"))
      (node (ref "R96") (pin "2") (pinfunction "2_2") (pintype "passive"))
    )
    (net (code "260") (name "Net-(IC15-CV)") (class "Default")
      (node (ref "IC15") (pin "5") (pinfunction "CV_5") (pintype "input"))
      (node (ref "R98") (pin "2") (pinfunction "2_2") (pintype "passive"))
    )
    (net (code "261") (name "Net-(IC15-Q)") (class "Default")
      (node (ref "IC15") (pin "3") (pinfunction "Q_3") (pintype "output"))
      (node (ref "IC16") (pin "12") (pinfunction "A_12") (pintype "input"))
      (node (ref "IC16") (pin "4") (pinfunction "A_4") (pintype "input"))
      (node (ref "R98") (pin "1") (pinfunction "1_1") (pintype "passive"))
    )
    (net (code "262") (name "Net-(IC16A-T2)") (class "Default")
      (node (ref "C25") (pin "2") (pinfunction "2_2") (pintype "passive"))
      (node (ref "IC16") (pin "2") (pinfunction "T2_2") (pintype "input"))
      (node (ref "R163") (pin "1") (pinfunction "1_1") (pintype "passive"))
    )
    (net (code "263") (name "Net-(IC16A-~{Q})") (class "Default")
      (node (ref "IC16") (pin "7") (pinfunction "~{Q}_7") (pintype "output"))
      (node (ref "Q23") (pin "1") (pinfunction "G_1") (pintype "passive"))
    )
    (net (code "264") (name "Net-(IC16B-B)") (class "Default")
      (node (ref "IC16") (pin "11") (pinfunction "B_11") (pintype "input"))
      (node (ref "IC16") (pin "9") (pinfunction "~{Q}_9") (pintype "output"))
      (node (ref "R148") (pin "2") (pinfunction "2_2") (pintype "passive"))
    )
    (net (code "265") (name "Net-(IC16B-T2)") (class "Default")
      (node (ref "C23") (pin "1") (pinfunction "1_1") (pintype "passive"))
      (node (ref "IC16") (pin "14") (pinfunction "T2_14") (pintype "input"))
      (node (ref "R139") (pin "1") (pinfunction "1_1") (pintype "passive"))
    )
    (net (code "266") (name "Net-(IC18A-+IN)") (class "Default")
      (node (ref "C18") (pin "1") (pinfunction "1_1") (pintype "passive"))
      (node (ref "IC18") (pin "3") (pinfunction "+IN_3") (pintype "input"))
      (node (ref "R73") (pin "1") (pinfunction "1_1") (pintype "passive"))
    )
    (net (code "267") (name "Net-(IC18A--IN)") (class "Default")
      (node (ref "IC18") (pin "2") (pinfunction "-IN_2") (pintype "input"))
      (node (ref "R74") (pin "2") (pinfunction "2_2") (pintype "passive"))
    )
    (net (code "268") (name "Net-(IC18A-OUT)") (class "Default")
      (node (ref "IC18") (pin "1") (pinfunction "OUT_1") (pintype "output"))
      (node (ref "R149") (pin "2") (pinfunction "2_2") (pintype "passive"))
    )
    (net (code "269") (name "Net-(IC18B-+IN)") (class "Default")
      (node (ref "IC18") (pin "5") (pinfunction "+IN_5") (pintype "input"))
      (node (ref "Q21") (pin "3") (pinfunction "D_3") (pintype "passive"))
      (node (ref "R150") (pin "2") (pinfunction "2_2") (pintype "passive"))
      (node (ref "R151") (pin "2") (pinfunction "2_2") (pintype "passive"))
    )
    (net (code "270") (name "Net-(IC18B--IN)") (class "Default")
      (node (ref "IC18") (pin "6") (pinfunction "-IN_6") (pintype "input"))
      (node (ref "R152") (pin "1") (pinfunction "1_1") (pintype "passive"))
      (node (ref "R153") (pin "2") (pinfunction "2_2") (pintype "passive"))
    )
    (net (code "271") (name "Net-(IC18B-OUT)") (class "Default")
      (node (ref "IC18") (pin "7") (pinfunction "OUT_7") (pintype "output"))
      (node (ref "R151") (pin "1") (pinfunction "1_1") (pintype "passive"))
      (node (ref "R87") (pin "2") (pinfunction "2_2") (pintype "passive"))
      (node (ref "R94") (pin "1") (pinfunction "1_1") (pintype "passive"))
    )
    (net (code "272") (name "Net-(IC19A-A)") (class "Default")
      (node (ref "IC19") (pin "10") (pinfunction "A_10") (pintype "input"))
      (node (ref "R171") (pin "1") (pinfunction "1_1") (pintype "passive"))
      (node (ref "R212") (pin "1") (pinfunction "1_1") (pintype "passive"))
      (node (ref "R212") (pin "2") (pinfunction "2_2") (pintype "passive"))
      (node (ref "X7") (pin "4") (pinfunction "4_4") (pintype "passive"))
      (node (ref "X8") (pin "2") (pinfunction "S_2") (pintype "passive"))
    )
    (net (code "273") (name "Net-(IC19A-B)") (class "Default")
      (node (ref "IC19") (pin "13") (pinfunction "B_13") (pintype "input"))
      (node (ref "R170") (pin "1") (pinfunction "1_1") (pintype "passive"))
      (node (ref "R211") (pin "1") (pinfunction "1_1") (pintype "passive"))
      (node (ref "R211") (pin "2") (pinfunction "2_2") (pintype "passive"))
      (node (ref "X7") (pin "3") (pinfunction "3_3") (pintype "passive"))
      (node (ref "X8") (pin "3") (pinfunction "S_3") (pintype "passive"))
    )
    (net (code "274") (name "Net-(IC19A-C)") (class "Default")
      (node (ref "IC19") (pin "12") (pinfunction "C_12") (pintype "input"))
      (node (ref "R169") (pin "1") (pinfunction "1_1") (pintype "passive"))
      (node (ref "R210") (pin "1") (pinfunction "1_1") (pintype "passive"))
      (node (ref "R210") (pin "2") (pinfunction "2_2") (pintype "passive"))
      (node (ref "X7") (pin "2") (pinfunction "2_2") (pintype "passive"))
      (node (ref "X8") (pin "4") (pinfunction "S_4") (pintype "passive"))
    )
    (net (code "275") (name "Net-(IC19A-Q0)") (class "Default")
      (node (ref "IC19") (pin "3") (pinfunction "Q0_3") (pintype "output"))
      (node (ref "IC21") (pin "1") (pinfunction "I1_1") (pintype "input"))
      (node (ref "IC21") (pin "2") (pinfunction "I2_2") (pintype "input"))
      (node (ref "Q30") (pin "1") (pinfunction "G_1") (pintype "passive"))
      (node (ref "Q31") (pin "1") (pinfunction "G_1") (pintype "passive"))
    )
    (net (code "276") (name "Net-(IC19A-Q1)") (class "Default")
      (node (ref "IC19") (pin "14") (pinfunction "Q1_14") (pintype "output"))
      (node (ref "IC21") (pin "6") (pinfunction "I6_6") (pintype "input"))
    )
    (net (code "277") (name "Net-(IC19A-Q2)") (class "Default")
      (node (ref "IC19") (pin "2") (pinfunction "Q2_2") (pintype "output"))
      (node (ref "IC21") (pin "7") (pinfunction "I7_7") (pintype "input"))
    )
    (net (code "278") (name "Net-(IC19A-Q3)") (class "Default")
      (node (ref "IC19") (pin "15") (pinfunction "Q3_15") (pintype "output"))
      (node (ref "IC21") (pin "5") (pinfunction "I5_5") (pintype "input"))
    )
    (net (code "279") (name "Net-(IC19A-Q4)") (class "Default")
      (node (ref "IC19") (pin "1") (pinfunction "Q4_1") (pintype "output"))
      (node (ref "IC21") (pin "4") (pinfunction "I4_4") (pintype "input"))
    )
    (net (code "280") (name "Net-(IC19A-Q5)") (class "Default")
      (node (ref "IC19") (pin "6") (pinfunction "Q5_6") (pintype "output"))
      (node (ref "IC21") (pin "3") (pinfunction "I3_3") (pintype "input"))
    )
    (net (code "281") (name "Net-(IC20-ADJ)") (class "Default")
      (node (ref "IC20") (pin "1") (pinfunction "ADJ_1") (pintype "input"))
      (node (ref "R167") (pin "1") (pinfunction "1_1") (pintype "passive"))
      (node (ref "R174") (pin "2") (pinfunction "2_2") (pintype "passive"))
      (node (ref "X7") (pin "7") (pinfunction "7_7") (pintype "passive"))
    )
    (net (code "282") (name "Net-(IC20-VI)") (class "Default")
      (node (ref "IC20") (pin "3") (pinfunction "VI_3") (pintype "input"))
      (node (ref "Q27") (pin "2") (pinfunction "C_2") (pintype "passive"))
    )
    (net (code "283") (name "Net-(IC20-VO)") (class "Default")
      (node (ref "IC20") (pin "2") (pinfunction "VO_2") (pintype "passive"))
      (node (ref "R167") (pin "2") (pinfunction "2_2") (pintype "passive"))
    )
    (net (code "284") (name "Net-(IC21-O1)") (class "Default")
      (node (ref "IC21") (pin "16") (pinfunction "O1_16") (pintype "open_collector"))
      (node (ref "Q30") (pin "3") (pinfunction "D_3") (pintype "passive"))
      (node (ref "R216") (pin "1") (pinfunction "1_1") (pintype "passive"))
    )
    (net (code "285") (name "Net-(IC21-O2)") (class "Default")
      (node (ref "IC21") (pin "15") (pinfunction "O2_15") (pintype "open_collector"))
      (node (ref "R189") (pin "1") (pinfunction "1_1") (pintype "passive"))
    )
    (net (code "286") (name "Net-(IC22A-+IN)") (class "Default")
      (node (ref "IC22") (pin "11") (pinfunction "+IN_11") (pintype "input"))
      (node (ref "IC22") (pin "5") (pinfunction "+IN_5") (pintype "input"))
      (node (ref "R178") (pin "1") (pinfunction "1_1") (pintype "passive"))
      (node (ref "R179") (pin "2") (pinfunction "2_2") (pintype "passive"))
      (node (ref "R180") (pin "2") (pinfunction "2_2") (pintype "passive"))
    )
    (net (code "287") (name "Net-(IC22A--IN)") (class "Default")
      (node (ref "C28") (pin "1") (pinfunction "1_1") (pintype "passive"))
      (node (ref "IC22") (pin "10") (pinfunction "-IN_10") (pintype "input"))
      (node (ref "IC22") (pin "4") (pinfunction "-IN_4") (pintype "input"))
      (node (ref "R177") (pin "1") (pinfunction "1_1") (pintype "passive"))
    )
    (net (code "288") (name "Net-(IC22A-OUT)") (class "Default")
      (node (ref "IC22") (pin "2") (pinfunction "OUT_2") (pintype "open_collector"))
      (node (ref "R180") (pin "1") (pinfunction "1_1") (pintype "passive"))
    )
    (net (code "289") (name "Net-(IC22B-+IN)") (class "Default")
      (node (ref "IC22") (pin "7") (pinfunction "+IN_7") (pintype "input"))
      (node (ref "R175") (pin "1") (pinfunction "1_1") (pintype "passive"))
      (node (ref "R192") (pin "1") (pinfunction "1_1") (pintype "passive"))
    )
    (net (code "290") (name "Net-(IC22B--IN)") (class "Default")
      (node (ref "IC22") (pin "6") (pinfunction "-IN_6") (pintype "input"))
      (node (ref "IC22") (pin "8") (pinfunction "-IN_8") (pintype "input"))
      (node (ref "R174") (pin "1") (pinfunction "1_1") (pintype "passive"))
    )
    (net (code "291") (name "Net-(IC22B-OUT)") (class "Default")
      (node (ref "IC22") (pin "1") (pinfunction "OUT_1") (pintype "open_collector"))
      (node (ref "R176") (pin "2") (pinfunction "2_2") (pintype "passive"))
      (node (ref "R181") (pin "2") (pinfunction "2_2") (pintype "passive"))
    )
    (net (code "292") (name "Net-(IC22C-+IN)") (class "Default")
      (node (ref "C31") (pin "1") (pinfunction "1_1") (pintype "passive"))
      (node (ref "IC22") (pin "9") (pinfunction "+IN_9") (pintype "input"))
      (node (ref "R183") (pin "2") (pinfunction "2_2") (pintype "passive"))
      (node (ref "R192") (pin "2") (pinfunction "2_2") (pintype "passive"))
    )
    (net (code "293") (name "Net-(IC22C-OUT)") (class "Default")
      (node (ref "C32") (pin "2") (pinfunction "2_2") (pintype "passive"))
      (node (ref "IC22") (pin "14") (pinfunction "OUT_14") (pintype "open_collector"))
      (node (ref "R182") (pin "2") (pinfunction "2_2") (pintype "passive"))
    )
    (net (code "294") (name "Net-(IC22D-OUT)") (class "Default")
      (node (ref "IC22") (pin "13") (pinfunction "OUT_13") (pintype "open_collector"))
      (node (ref "JP12") (pin "1") (pinfunction "1_1") (pintype "passive"))
      (node (ref "Q29") (pin "1") (pinfunction "G_1") (pintype "passive"))
      (node (ref "R195") (pin "2") (pinfunction "2_2") (pintype "passive"))
    )
    (net (code "295") (name "Net-(IC24-CV)") (class "Default")
      (node (ref "IC24") (pin "5") (pinfunction "CV_5") (pintype "input"))
      (node (ref "R197") (pin "2") (pinfunction "2_2") (pintype "passive"))
    )
    (net (code "296") (name "Net-(IC24-Q)") (class "Default")
      (node (ref "IC24") (pin "3") (pinfunction "Q_3") (pintype "output"))
      (node (ref "IC25") (pin "12") (pinfunction "A_12") (pintype "input"))
      (node (ref "IC25") (pin "4") (pinfunction "A_4") (pintype "input"))
      (node (ref "R197") (pin "1") (pinfunction "1_1") (pintype "passive"))
    )
    (net (code "297") (name "Net-(IC25A-T2)") (class "Default")
      (node (ref "C37") (pin "2") (pinfunction "2_2") (pintype "passive"))
      (node (ref "IC25") (pin "2") (pinfunction "T2_2") (pintype "input"))
      (node (ref "R218") (pin "1") (pinfunction "1_1") (pintype "passive"))
    )
    (net (code "298") (name "Net-(IC25A-~{Q})") (class "Default")
      (node (ref "IC25") (pin "7") (pinfunction "~{Q}_7") (pintype "output"))
      (node (ref "Q33") (pin "1") (pinfunction "G_1") (pintype "passive"))
    )
    (net (code "299") (name "Net-(IC25B-B)") (class "Default")
      (node (ref "IC25") (pin "11") (pinfunction "B_11") (pintype "input"))
      (node (ref "IC25") (pin "9") (pinfunction "~{Q}_9") (pintype "output"))
      (node (ref "R203") (pin "2") (pinfunction "2_2") (pintype "passive"))
    )
    (net (code "300") (name "Net-(IC25B-T2)") (class "Default")
      (node (ref "C35") (pin "1") (pinfunction "1_1") (pintype "passive"))
      (node (ref "IC25") (pin "14") (pinfunction "T2_14") (pintype "input"))
      (node (ref "R201") (pin "1") (pinfunction "1_1") (pintype "passive"))
    )
    (net (code "301") (name "Net-(IC27A-+IN)") (class "Default")
      (node (ref "C30") (pin "1") (pinfunction "1_1") (pintype "passive"))
      (node (ref "IC27") (pin "3") (pinfunction "+IN_3") (pintype "input"))
      (node (ref "R172") (pin "1") (pinfunction "1_1") (pintype "passive"))
    )
    (net (code "302") (name "Net-(IC27A--IN)") (class "Default")
      (node (ref "IC27") (pin "2") (pinfunction "-IN_2") (pintype "input"))
      (node (ref "R173") (pin "2") (pinfunction "2_2") (pintype "passive"))
    )
    (net (code "303") (name "Net-(IC27A-OUT)") (class "Default")
      (node (ref "IC27") (pin "1") (pinfunction "OUT_1") (pintype "output"))
      (node (ref "R204") (pin "2") (pinfunction "2_2") (pintype "passive"))
    )
    (net (code "304") (name "Net-(IC27B-+IN)") (class "Default")
      (node (ref "IC27") (pin "5") (pinfunction "+IN_5") (pintype "input"))
      (node (ref "Q31") (pin "3") (pinfunction "D_3") (pintype "passive"))
      (node (ref "R205") (pin "2") (pinfunction "2_2") (pintype "passive"))
      (node (ref "R206") (pin "2") (pinfunction "2_2") (pintype "passive"))
    )
    (net (code "305") (name "Net-(IC27B--IN)") (class "Default")
      (node (ref "IC27") (pin "6") (pinfunction "-IN_6") (pintype "input"))
      (node (ref "R207") (pin "1") (pinfunction "1_1") (pintype "passive"))
      (node (ref "R208") (pin "2") (pinfunction "2_2") (pintype "passive"))
    )
    (net (code "306") (name "Net-(IC27B-OUT)") (class "Default")
      (node (ref "IC27") (pin "7") (pinfunction "OUT_7") (pintype "output"))
      (node (ref "R186") (pin "2") (pinfunction "2_2") (pintype "passive"))
      (node (ref "R193") (pin "1") (pinfunction "1_1") (pintype "passive"))
      (node (ref "R206") (pin "1") (pinfunction "1_1") (pintype "passive"))
    )
    (net (code "307") (name "Net-(IC28A-A)") (class "Default")
      (node (ref "IC28") (pin "10") (pinfunction "A_10") (pintype "input"))
      (node (ref "R226") (pin "1") (pinfunction "1_1") (pintype "passive"))
      (node (ref "R267") (pin "1") (pinfunction "1_1") (pintype "passive"))
      (node (ref "R267") (pin "2") (pinfunction "2_2") (pintype "passive"))
      (node (ref "X10") (pin "4") (pinfunction "4_4") (pintype "passive"))
      (node (ref "X11") (pin "2") (pinfunction "S_2") (pintype "passive"))
    )
    (net (code "308") (name "Net-(IC28A-B)") (class "Default")
      (node (ref "IC28") (pin "13") (pinfunction "B_13") (pintype "input"))
      (node (ref "R225") (pin "1") (pinfunction "1_1") (pintype "passive"))
      (node (ref "R266") (pin "1") (pinfunction "1_1") (pintype "passive"))
      (node (ref "R266") (pin "2") (pinfunction "2_2") (pintype "passive"))
      (node (ref "X10") (pin "3") (pinfunction "3_3") (pintype "passive"))
      (node (ref "X11") (pin "3") (pinfunction "S_3") (pintype "passive"))
    )
    (net (code "309") (name "Net-(IC28A-C)") (class "Default")
      (node (ref "IC28") (pin "12") (pinfunction "C_12") (pintype "input"))
      (node (ref "R224") (pin "1") (pinfunction "1_1") (pintype "passive"))
      (node (ref "R265") (pin "1") (pinfunction "1_1") (pintype "passive"))
      (node (ref "R265") (pin "2") (pinfunction "2_2") (pintype "passive"))
      (node (ref "X10") (pin "2") (pinfunction "2_2") (pintype "passive"))
      (node (ref "X11") (pin "4") (pinfunction "S_4") (pintype "passive"))
    )
    (net (code "310") (name "Net-(IC28A-Q0)") (class "Default")
      (node (ref "IC28") (pin "3") (pinfunction "Q0_3") (pintype "output"))
      (node (ref "IC30") (pin "1") (pinfunction "I1_1") (pintype "input"))
      (node (ref "IC30") (pin "2") (pinfunction "I2_2") (pintype "input"))
      (node (ref "Q40") (pin "1") (pinfunction "G_1") (pintype "passive"))
      (node (ref "Q41") (pin "1") (pinfunction "G_1") (pintype "passive"))
    )
    (net (code "311") (name "Net-(IC28A-Q1)") (class "Default")
      (node (ref "IC28") (pin "14") (pinfunction "Q1_14") (pintype "output"))
      (node (ref "IC30") (pin "6") (pinfunction "I6_6") (pintype "input"))
    )
    (net (code "312") (name "Net-(IC28A-Q2)") (class "Default")
      (node (ref "IC28") (pin "2") (pinfunction "Q2_2") (pintype "output"))
      (node (ref "IC30") (pin "7") (pinfunction "I7_7") (pintype "input"))
    )
    (net (code "313") (name "Net-(IC28A-Q3)") (class "Default")
      (node (ref "IC28") (pin "15") (pinfunction "Q3_15") (pintype "output"))
      (node (ref "IC30") (pin "5") (pinfunction "I5_5") (pintype "input"))
    )
    (net (code "314") (name "Net-(IC28A-Q4)") (class "Default")
      (node (ref "IC28") (pin "1") (pinfunction "Q4_1") (pintype "output"))
      (node (ref "IC30") (pin "4") (pinfunction "I4_4") (pintype "input"))
    )
    (net (code "315") (name "Net-(IC28A-Q5)") (class "Default")
      (node (ref "IC28") (pin "6") (pinfunction "Q5_6") (pintype "output"))
      (node (ref "IC30") (pin "3") (pinfunction "I3_3") (pintype "input"))
    )
    (net (code "316") (name "Net-(IC29-ADJ)") (class "Default")
      (node (ref "IC29") (pin "1") (pinfunction "ADJ_1") (pintype "input"))
      (node (ref "R222") (pin "1") (pinfunction "1_1") (pintype "passive"))
      (node (ref "R229") (pin "2") (pinfunction "2_2") (pintype "passive"))
      (node (ref "X10") (pin "7") (pinfunction "7_7") (pintype "passive"))
    )
    (net (code "317") (name "Net-(IC29-VI)") (class "Default")
      (node (ref "IC29") (pin "3") (pinfunction "VI_3") (pintype "input"))
      (node (ref "Q37") (pin "2") (pinfunction "C_2") (pintype "passive"))
    )
    (net (code "318") (name "Net-(IC29-VO)") (class "Default")
      (node (ref "IC29") (pin "2") (pinfunction "VO_2") (pintype "passive"))
      (node (ref "R222") (pin "2") (pinfunction "2_2") (pintype "passive"))
    )
    (net (code "319") (name "Net-(IC30-O1)") (class "Default")
      (node (ref "IC30") (pin "16") (pinfunction "O1_16") (pintype "open_collector"))
      (node (ref "Q40") (pin "3") (pinfunction "D_3") (pintype "passive"))
      (node (ref "R271") (pin "1") (pinfunction "1_1") (pintype "passive"))
    )
    (net (code "320") (name "Net-(IC30-O2)") (class "Default")
      (node (ref "IC30") (pin "15") (pinfunction "O2_15") (pintype "open_collector"))
      (node (ref "R244") (pin "1") (pinfunction "1_1") (pintype "passive"))
    )
    (net (code "321") (name "Net-(IC31A-+IN)") (class "Default")
      (node (ref "IC31") (pin "11") (pinfunction "+IN_11") (pintype "input"))
      (node (ref "IC31") (pin "5") (pinfunction "+IN_5") (pintype "input"))
      (node (ref "R233") (pin "1") (pinfunction "1_1") (pintype "passive"))
      (node (ref "R234") (pin "2") (pinfunction "2_2") (pintype "passive"))
      (node (ref "R235") (pin "2") (pinfunction "2_2") (pintype "passive"))
    )
    (net (code "322") (name "Net-(IC31A--IN)") (class "Default")
      (node (ref "C40") (pin "1") (pinfunction "1_1") (pintype "passive"))
      (node (ref "IC31") (pin "10") (pinfunction "-IN_10") (pintype "input"))
      (node (ref "IC31") (pin "4") (pinfunction "-IN_4") (pintype "input"))
      (node (ref "R232") (pin "1") (pinfunction "1_1") (pintype "passive"))
    )
    (net (code "323") (name "Net-(IC31A-OUT)") (class "Default")
      (node (ref "IC31") (pin "2") (pinfunction "OUT_2") (pintype "open_collector"))
      (node (ref "R235") (pin "1") (pinfunction "1_1") (pintype "passive"))
    )
    (net (code "324") (name "Net-(IC31B-+IN)") (class "Default")
      (node (ref "IC31") (pin "7") (pinfunction "+IN_7") (pintype "input"))
      (node (ref "R230") (pin "1") (pinfunction "1_1") (pintype "passive"))
      (node (ref "R247") (pin "1") (pinfunction "1_1") (pintype "passive"))
    )
    (net (code "325") (name "Net-(IC31B--IN)") (class "Default")
      (node (ref "IC31") (pin "6") (pinfunction "-IN_6") (pintype "input"))
      (node (ref "IC31") (pin "8") (pinfunction "-IN_8") (pintype "input"))
      (node (ref "R229") (pin "1") (pinfunction "1_1") (pintype "passive"))
    )
    (net (code "326") (name "Net-(IC31B-OUT)") (class "Default")
      (node (ref "IC31") (pin "1") (pinfunction "OUT_1") (pintype "open_collector"))
      (node (ref "R231") (pin "2") (pinfunction "2_2") (pintype "passive"))
      (node (ref "R236") (pin "2") (pinfunction "2_2") (pintype "passive"))
    )
    (net (code "327") (name "Net-(IC31C-+IN)") (class "Default")
      (node (ref "C43") (pin "1") (pinfunction "1_1") (pintype "passive"))
      (node (ref "IC31") (pin "9") (pinfunction "+IN_9") (pintype "input"))
      (node (ref "R238") (pin "2") (pinfunction "2_2") (pintype "passive"))
      (node (ref "R247") (pin "2") (pinfunction "2_2") (pintype "passive"))
    )
    (net (code "328") (name "Net-(IC31C-OUT)") (class "Default")
      (node (ref "C44") (pin "2") (pinfunction "2_2") (pintype "passive"))
      (node (ref "IC31") (pin "14") (pinfunction "OUT_14") (pintype "open_collector"))
      (node (ref "R237") (pin "2") (pinfunction "2_2") (pintype "passive"))
    )
    (net (code "329") (name "Net-(IC31D-OUT)") (class "Default")
      (node (ref "IC31") (pin "13") (pinfunction "OUT_13") (pintype "open_collector"))
      (node (ref "JP17") (pin "1") (pinfunction "1_1") (pintype "passive"))
      (node (ref "Q39") (pin "1") (pinfunction "G_1") (pintype "passive"))
      (node (ref "R250") (pin "2") (pinfunction "2_2") (pintype "passive"))
    )
    (net (code "330") (name "Net-(IC33-CV)") (class "Default")
      (node (ref "IC33") (pin "5") (pinfunction "CV_5") (pintype "input"))
      (node (ref "R252") (pin "2") (pinfunction "2_2") (pintype "passive"))
    )
    (net (code "331") (name "Net-(IC33-Q)") (class "Default")
      (node (ref "IC33") (pin "3") (pinfunction "Q_3") (pintype "output"))
      (node (ref "IC34") (pin "12") (pinfunction "A_12") (pintype "input"))
      (node (ref "IC34") (pin "4") (pinfunction "A_4") (pintype "input"))
      (node (ref "R252") (pin "1") (pinfunction "1_1") (pintype "passive"))
    )
    (net (code "332") (name "Net-(IC34A-T2)") (class "Default")
      (node (ref "C49") (pin "2") (pinfunction "2_2") (pintype "passive"))
      (node (ref "IC34") (pin "2") (pinfunction "T2_2") (pintype "input"))
      (node (ref "R273") (pin "1") (pinfunction "1_1") (pintype "passive"))
    )
    (net (code "333") (name "Net-(IC34A-~{Q})") (class "Default")
      (node (ref "IC34") (pin "7") (pinfunction "~{Q}_7") (pintype "output"))
      (node (ref "Q43") (pin "1") (pinfunction "G_1") (pintype "passive"))
    )
    (net (code "334") (name "Net-(IC34B-B)") (class "Default")
      (node (ref "IC34") (pin "11") (pinfunction "B_11") (pintype "input"))
      (node (ref "IC34") (pin "9") (pinfunction "~{Q}_9") (pintype "output"))
      (node (ref "R258") (pin "2") (pinfunction "2_2") (pintype "passive"))
    )
    (net (code "335") (name "Net-(IC34B-T2)") (class "Default")
      (node (ref "C47") (pin "1") (pinfunction "1_1") (pintype "passive"))
      (node (ref "IC34") (pin "14") (pinfunction "T2_14") (pintype "input"))
      (node (ref "R256") (pin "1") (pinfunction "1_1") (pintype "passive"))
    )
    (net (code "336") (name "Net-(IC36A-+IN)") (class "Default")
      (node (ref "C42") (pin "1") (pinfunction "1_1") (pintype "passive"))
      (node (ref "IC36") (pin "3") (pinfunction "+IN_3") (pintype "input"))
      (node (ref "R227") (pin "1") (pinfunction "1_1") (pintype "passive"))
    )
    (net (code "337") (name "Net-(IC36A--IN)") (class "Default")
      (node (ref "IC36") (pin "2") (pinfunction "-IN_2") (pintype "input"))
      (node (ref "R228") (pin "2") (pinfunction "2_2") (pintype "passive"))
    )
    (net (code "338") (name "Net-(IC36A-OUT)") (class "Default")
      (node (ref "IC36") (pin "1") (pinfunction "OUT_1") (pintype "output"))
      (node (ref "R259") (pin "2") (pinfunction "2_2") (pintype "passive"))
    )
    (net (code "339") (name "Net-(IC36B-+IN)") (class "Default")
      (node (ref "IC36") (pin "5") (pinfunction "+IN_5") (pintype "input"))
      (node (ref "Q41") (pin "3") (pinfunction "D_3") (pintype "passive"))
      (node (ref "R260") (pin "2") (pinfunction "2_2") (pintype "passive"))
      (node (ref "R261") (pin "2") (pinfunction "2_2") (pintype "passive"))
    )
    (net (code "340") (name "Net-(IC36B--IN)") (class "Default")
      (node (ref "IC36") (pin "6") (pinfunction "-IN_6") (pintype "input"))
      (node (ref "R262") (pin "1") (pinfunction "1_1") (pintype "passive"))
      (node (ref "R263") (pin "2") (pinfunction "2_2") (pintype "passive"))
    )
    (net (code "341") (name "Net-(IC36B-OUT)") (class "Default")
      (node (ref "IC36") (pin "7") (pinfunction "OUT_7") (pintype "output"))
      (node (ref "R241") (pin "2") (pinfunction "2_2") (pintype "passive"))
      (node (ref "R248") (pin "1") (pinfunction "1_1") (pintype "passive"))
      (node (ref "R261") (pin "1") (pinfunction "1_1") (pintype "passive"))
    )
    (net (code "342") (name "Net-(IC37A-A)") (class "Default")
      (node (ref "IC37") (pin "10") (pinfunction "A_10") (pintype "input"))
      (node (ref "R281") (pin "1") (pinfunction "1_1") (pintype "passive"))
      (node (ref "R322") (pin "1") (pinfunction "1_1") (pintype "passive"))
      (node (ref "R322") (pin "2") (pinfunction "2_2") (pintype "passive"))
      (node (ref "X13") (pin "4") (pinfunction "4_4") (pintype "passive"))
      (node (ref "X14") (pin "2") (pinfunction "S_2") (pintype "passive"))
    )
    (net (code "343") (name "Net-(IC37A-B)") (class "Default")
      (node (ref "IC37") (pin "13") (pinfunction "B_13") (pintype "input"))
      (node (ref "R280") (pin "1") (pinfunction "1_1") (pintype "passive"))
      (node (ref "R321") (pin "1") (pinfunction "1_1") (pintype "passive"))
      (node (ref "R321") (pin "2") (pinfunction "2_2") (pintype "passive"))
      (node (ref "X13") (pin "3") (pinfunction "3_3") (pintype "passive"))
      (node (ref "X14") (pin "3") (pinfunction "S_3") (pintype "passive"))
    )
    (net (code "344") (name "Net-(IC37A-C)") (class "Default")
      (node (ref "IC37") (pin "12") (pinfunction "C_12") (pintype "input"))
      (node (ref "R279") (pin "1") (pinfunction "1_1") (pintype "passive"))
      (node (ref "R320") (pin "1") (pinfunction "1_1") (pintype "passive"))
      (node (ref "R320") (pin "2") (pinfunction "2_2") (pintype "passive"))
      (node (ref "X13") (pin "2") (pinfunction "2_2") (pintype "passive"))
      (node (ref "X14") (pin "4") (pinfunction "S_4") (pintype "passive"))
    )
    (net (code "345") (name "Net-(IC37A-Q0)") (class "Default")
      (node (ref "IC37") (pin "3") (pinfunction "Q0_3") (pintype "output"))
      (node (ref "IC39") (pin "1") (pinfunction "I1_1") (pintype "input"))
      (node (ref "IC39") (pin "2") (pinfunction "I2_2") (pintype "input"))
      (node (ref "Q50") (pin "1") (pinfunction "G_1") (pintype "passive"))
      (node (ref "Q51") (pin "1") (pinfunction "G_1") (pintype "passive"))
    )
    (net (code "346") (name "Net-(IC37A-Q1)") (class "Default")
      (node (ref "IC37") (pin "14") (pinfunction "Q1_14") (pintype "output"))
      (node (ref "IC39") (pin "6") (pinfunction "I6_6") (pintype "input"))
    )
    (net (code "347") (name "Net-(IC37A-Q2)") (class "Default")
      (node (ref "IC37") (pin "2") (pinfunction "Q2_2") (pintype "output"))
      (node (ref "IC39") (pin "7") (pinfunction "I7_7") (pintype "input"))
    )
    (net (code "348") (name "Net-(IC37A-Q3)") (class "Default")
      (node (ref "IC37") (pin "15") (pinfunction "Q3_15") (pintype "output"))
      (node (ref "IC39") (pin "5") (pinfunction "I5_5") (pintype "input"))
    )
    (net (code "349") (name "Net-(IC37A-Q4)") (class "Default")
      (node (ref "IC37") (pin "1") (pinfunction "Q4_1") (pintype "output"))
      (node (ref "IC39") (pin "4") (pinfunction "I4_4") (pintype "input"))
    )
    (net (code "350") (name "Net-(IC37A-Q5)") (class "Default")
      (node (ref "IC37") (pin "6") (pinfunction "Q5_6") (pintype "output"))
      (node (ref "IC39") (pin "3") (pinfunction "I3_3") (pintype "input"))
    )
    (net (code "351") (name "Net-(IC38-ADJ)") (class "Default")
      (node (ref "IC38") (pin "1") (pinfunction "ADJ_1") (pintype "input"))
      (node (ref "R277") (pin "1") (pinfunction "1_1") (pintype "passive"))
      (node (ref "R284") (pin "2") (pinfunction "2_2") (pintype "passive"))
      (node (ref "X13") (pin "7") (pinfunction "7_7") (pintype "passive"))
    )
    (net (code "352") (name "Net-(IC38-VI)") (class "Default")
      (node (ref "IC38") (pin "3") (pinfunction "VI_3") (pintype "input"))
      (node (ref "Q47") (pin "2") (pinfunction "C_2") (pintype "passive"))
    )
    (net (code "353") (name "Net-(IC38-VO)") (class "Default")
      (node (ref "IC38") (pin "2") (pinfunction "VO_2") (pintype "passive"))
      (node (ref "R277") (pin "2") (pinfunction "2_2") (pintype "passive"))
    )
    (net (code "354") (name "Net-(IC39-O1)") (class "Default")
      (node (ref "IC39") (pin "16") (pinfunction "O1_16") (pintype "open_collector"))
      (node (ref "Q50") (pin "3") (pinfunction "D_3") (pintype "passive"))
      (node (ref "R326") (pin "1") (pinfunction "1_1") (pintype "passive"))
    )
    (net (code "355") (name "Net-(IC39-O2)") (class "Default")
      (node (ref "IC39") (pin "15") (pinfunction "O2_15") (pintype "open_collector"))
      (node (ref "R299") (pin "1") (pinfunction "1_1") (pintype "passive"))
    )
    (net (code "356") (name "Net-(IC40A-+IN)") (class "Default")
      (node (ref "IC40") (pin "11") (pinfunction "+IN_11") (pintype "input"))
      (node (ref "IC40") (pin "5") (pinfunction "+IN_5") (pintype "input"))
      (node (ref "R288") (pin "1") (pinfunction "1_1") (pintype "passive"))
      (node (ref "R289") (pin "2") (pinfunction "2_2") (pintype "passive"))
      (node (ref "R290") (pin "2") (pinfunction "2_2") (pintype "passive"))
    )
    (net (code "357") (name "Net-(IC40A--IN)") (class "Default")
      (node (ref "C52") (pin "1") (pinfunction "1_1") (pintype "passive"))
      (node (ref "IC40") (pin "10") (pinfunction "-IN_10") (pintype "input"))
      (node (ref "IC40") (pin "4") (pinfunction "-IN_4") (pintype "input"))
      (node (ref "R287") (pin "1") (pinfunction "1_1") (pintype "passive"))
    )
    (net (code "358") (name "Net-(IC40A-OUT)") (class "Default")
      (node (ref "IC40") (pin "2") (pinfunction "OUT_2") (pintype "open_collector"))
      (node (ref "R290") (pin "1") (pinfunction "1_1") (pintype "passive"))
    )
    (net (code "359") (name "Net-(IC40B-+IN)") (class "Default")
      (node (ref "IC40") (pin "7") (pinfunction "+IN_7") (pintype "input"))
      (node (ref "R285") (pin "1") (pinfunction "1_1") (pintype "passive"))
      (node (ref "R302") (pin "1") (pinfunction "1_1") (pintype "passive"))
    )
    (net (code "360") (name "Net-(IC40B--IN)") (class "Default")
      (node (ref "IC40") (pin "6") (pinfunction "-IN_6") (pintype "input"))
      (node (ref "IC40") (pin "8") (pinfunction "-IN_8") (pintype "input"))
      (node (ref "R284") (pin "1") (pinfunction "1_1") (pintype "passive"))
    )
    (net (code "361") (name "Net-(IC40B-OUT)") (class "Default")
      (node (ref "IC40") (pin "1") (pinfunction "OUT_1") (pintype "open_collector"))
      (node (ref "R286") (pin "2") (pinfunction "2_2") (pintype "passive"))
      (node (ref "R291") (pin "2") (pinfunction "2_2") (pintype "passive"))
    )
    (net (code "362") (name "Net-(IC40C-+IN)") (class "Default")
      (node (ref "C55") (pin "1") (pinfunction "1_1") (pintype "passive"))
      (node (ref "IC40") (pin "9") (pinfunction "+IN_9") (pintype "input"))
      (node (ref "R293") (pin "2") (pinfunction "2_2") (pintype "passive"))
      (node (ref "R302") (pin "2") (pinfunction "2_2") (pintype "passive"))
    )
    (net (code "363") (name "Net-(IC40C-OUT)") (class "Default")
      (node (ref "C56") (pin "2") (pinfunction "2_2") (pintype "passive"))
      (node (ref "IC40") (pin "14") (pinfunction "OUT_14") (pintype "open_collector"))
      (node (ref "R292") (pin "2") (pinfunction "2_2") (pintype "passive"))
    )
    (net (code "364") (name "Net-(IC40D-OUT)") (class "Default")
      (node (ref "IC40") (pin "13") (pinfunction "OUT_13") (pintype "open_collector"))
      (node (ref "JP22") (pin "1") (pinfunction "1_1") (pintype "passive"))
      (node (ref "Q49") (pin "1") (pinfunction "G_1") (pintype "passive"))
      (node (ref "R305") (pin "2") (pinfunction "2_2") (pintype "passive"))
    )
    (net (code "365") (name "Net-(IC42-CV)") (class "Default")
      (node (ref "IC42") (pin "5") (pinfunction "CV_5") (pintype "input"))
      (node (ref "R307") (pin "2") (pinfunction "2_2") (pintype "passive"))
    )
    (net (code "366") (name "Net-(IC42-Q)") (class "Default")
      (node (ref "IC42") (pin "3") (pinfunction "Q_3") (pintype "output"))
      (node (ref "IC43") (pin "12") (pinfunction "A_12") (pintype "input"))
      (node (ref "IC43") (pin "4") (pinfunction "A_4") (pintype "input"))
      (node (ref "R307") (pin "1") (pinfunction "1_1") (pintype "passive"))
    )
    (net (code "367") (name "Net-(IC43A-T2)") (class "Default")
      (node (ref "C61") (pin "2") (pinfunction "2_2") (pintype "passive"))
      (node (ref "IC43") (pin "2") (pinfunction "T2_2") (pintype "input"))
      (node (ref "R328") (pin "1") (pinfunction "1_1") (pintype "passive"))
    )
    (net (code "368") (name "Net-(IC43A-~{Q})") (class "Default")
      (node (ref "IC43") (pin "7") (pinfunction "~{Q}_7") (pintype "output"))
      (node (ref "Q53") (pin "1") (pinfunction "G_1") (pintype "passive"))
    )
    (net (code "369") (name "Net-(IC43B-B)") (class "Default")
      (node (ref "IC43") (pin "11") (pinfunction "B_11") (pintype "input"))
      (node (ref "IC43") (pin "9") (pinfunction "~{Q}_9") (pintype "output"))
      (node (ref "R313") (pin "2") (pinfunction "2_2") (pintype "passive"))
    )
    (net (code "370") (name "Net-(IC43B-T2)") (class "Default")
      (node (ref "C59") (pin "1") (pinfunction "1_1") (pintype "passive"))
      (node (ref "IC43") (pin "14") (pinfunction "T2_14") (pintype "input"))
      (node (ref "R311") (pin "1") (pinfunction "1_1") (pintype "passive"))
    )
    (net (code "371") (name "Net-(IC45A-+IN)") (class "Default")
      (node (ref "C54") (pin "1") (pinfunction "1_1") (pintype "passive"))
      (node (ref "IC45") (pin "3") (pinfunction "+IN_3") (pintype "input"))
      (node (ref "R282") (pin "1") (pinfunction "1_1") (pintype "passive"))
    )
    (net (code "372") (name "Net-(IC45A--IN)") (class "Default")
      (node (ref "IC45") (pin "2") (pinfunction "-IN_2") (pintype "input"))
      (node (ref "R283") (pin "2") (pinfunction "2_2") (pintype "passive"))
    )
    (net (code "373") (name "Net-(IC45A-OUT)") (class "Default")
      (node (ref "IC45") (pin "1") (pinfunction "OUT_1") (pintype "output"))
      (node (ref "R314") (pin "2") (pinfunction "2_2") (pintype "passive"))
    )
    (net (code "374") (name "Net-(IC45B-+IN)") (class "Default")
      (node (ref "IC45") (pin "5") (pinfunction "+IN_5") (pintype "input"))
      (node (ref "Q51") (pin "3") (pinfunction "D_3") (pintype "passive"))
      (node (ref "R315") (pin "2") (pinfunction "2_2") (pintype "passive"))
      (node (ref "R316") (pin "2") (pinfunction "2_2") (pintype "passive"))
    )
    (net (code "375") (name "Net-(IC45B--IN)") (class "Default")
      (node (ref "IC45") (pin "6") (pinfunction "-IN_6") (pintype "input"))
      (node (ref "R317") (pin "1") (pinfunction "1_1") (pintype "passive"))
      (node (ref "R318") (pin "2") (pinfunction "2_2") (pintype "passive"))
    )
    (net (code "376") (name "Net-(IC45B-OUT)") (class "Default")
      (node (ref "IC45") (pin "7") (pinfunction "OUT_7") (pintype "output"))
      (node (ref "R296") (pin "2") (pinfunction "2_2") (pintype "passive"))
      (node (ref "R303") (pin "1") (pinfunction "1_1") (pintype "passive"))
      (node (ref "R316") (pin "1") (pinfunction "1_1") (pintype "passive"))
    )
    (net (code "377") (name "Net-(IC101A-+IN)") (class "Default")
      (node (ref "C101") (pin "1") (pinfunction "1_1") (pintype "passive"))
      (node (ref "IC101") (pin "3") (pinfunction "+IN_3") (pintype "input"))
      (node (ref "R105") (pin "1") (pinfunction "1_1") (pintype "passive"))
    )
    (net (code "378") (name "Net-(IC101A--IN)") (class "Default")
      (node (ref "IC101") (pin "2") (pinfunction "-IN_2") (pintype "input"))
      (node (ref "R107") (pin "2") (pinfunction "2_2") (pintype "passive"))
    )
    (net (code "379") (name "Net-(IC101A-OUT)") (class "Default")
      (node (ref "IC101") (pin "1") (pinfunction "OUT_1") (pintype "output"))
      (node (ref "R108") (pin "2") (pinfunction "2_2") (pintype "passive"))
    )
    (net (code "380") (name "Net-(IC101B-+IN)") (class "Default")
      (node (ref "IC101") (pin "5") (pinfunction "+IN_5") (pintype "input"))
      (node (ref "Q1") (pin "3") (pinfunction "D_3") (pintype "passive"))
      (node (ref "R112") (pin "2") (pinfunction "2_2") (pintype "passive"))
      (node (ref "R117") (pin "2") (pinfunction "2_2") (pintype "passive"))
    )
    (net (code "381") (name "Net-(IC101B--IN)") (class "Default")
      (node (ref "IC101") (pin "6") (pinfunction "-IN_6") (pintype "input"))
      (node (ref "R113") (pin "1") (pinfunction "1_1") (pintype "passive"))
      (node (ref "R114") (pin "2") (pinfunction "2_2") (pintype "passive"))
    )
    (net (code "382") (name "Net-(IC101B-OUT)") (class "Default")
      (node (ref "IC101") (pin "7") (pinfunction "OUT_7") (pintype "output"))
      (node (ref "R115") (pin "2") (pinfunction "2_2") (pintype "passive"))
      (node (ref "R116") (pin "1") (pinfunction "1_1") (pintype "passive"))
      (node (ref "R117") (pin "1") (pinfunction "1_1") (pintype "passive"))
    )
    (net (code "383") (name "Net-(IC105A-A)") (class "Default")
      (node (ref "IC105") (pin "10") (pinfunction "A_10") (pintype "input"))
      (node (ref "R111") (pin "1") (pinfunction "1_1") (pintype "passive"))
      (node (ref "R3") (pin "1") (pinfunction "1_1") (pintype "passive"))
      (node (ref "R3") (pin "2") (pinfunction "2_2") (pintype "passive"))
      (node (ref "X101") (pin "4") (pinfunction "4_4") (pintype "passive"))
      (node (ref "X103") (pin "2") (pinfunction "S_2") (pintype "passive"))
    )
    (net (code "384") (name "Net-(IC105A-B)") (class "Default")
      (node (ref "IC105") (pin "13") (pinfunction "B_13") (pintype "input"))
      (node (ref "R110") (pin "1") (pinfunction "1_1") (pintype "passive"))
      (node (ref "R2") (pin "1") (pinfunction "1_1") (pintype "passive"))
      (node (ref "R2") (pin "2") (pinfunction "2_2") (pintype "passive"))
      (node (ref "X101") (pin "3") (pinfunction "3_3") (pintype "passive"))
      (node (ref "X103") (pin "3") (pinfunction "S_3") (pintype "passive"))
    )
    (net (code "385") (name "Net-(IC105A-C)") (class "Default")
      (node (ref "IC105") (pin "12") (pinfunction "C_12") (pintype "input"))
      (node (ref "R1") (pin "1") (pinfunction "1_1") (pintype "passive"))
      (node (ref "R1") (pin "2") (pinfunction "2_2") (pintype "passive"))
      (node (ref "R109") (pin "1") (pinfunction "1_1") (pintype "passive"))
      (node (ref "X101") (pin "2") (pinfunction "2_2") (pintype "passive"))
      (node (ref "X103") (pin "4") (pinfunction "S_4") (pintype "passive"))
    )
    (net (code "386") (name "Net-(IC105A-Q0)") (class "Default")
      (node (ref "IC105") (pin "3") (pinfunction "Q0_3") (pintype "output"))
      (node (ref "IC107") (pin "1") (pinfunction "I1_1") (pintype "input"))
      (node (ref "IC107") (pin "2") (pinfunction "I2_2") (pintype "input"))
      (node (ref "Q1") (pin "1") (pinfunction "G_1") (pintype "passive"))
      (node (ref "Q106") (pin "1") (pinfunction "G_1") (pintype "passive"))
    )
    (net (code "387") (name "Net-(IC105A-Q1)") (class "Default")
      (node (ref "IC105") (pin "14") (pinfunction "Q1_14") (pintype "output"))
      (node (ref "IC107") (pin "6") (pinfunction "I6_6") (pintype "input"))
    )
    (net (code "388") (name "Net-(IC105A-Q2)") (class "Default")
      (node (ref "IC105") (pin "2") (pinfunction "Q2_2") (pintype "output"))
      (node (ref "IC107") (pin "7") (pinfunction "I7_7") (pintype "input"))
    )
    (net (code "389") (name "Net-(IC105A-Q3)") (class "Default")
      (node (ref "IC105") (pin "15") (pinfunction "Q3_15") (pintype "output"))
      (node (ref "IC107") (pin "5") (pinfunction "I5_5") (pintype "input"))
    )
    (net (code "390") (name "Net-(IC105A-Q4)") (class "Default")
      (node (ref "IC105") (pin "1") (pinfunction "Q4_1") (pintype "output"))
      (node (ref "IC107") (pin "4") (pinfunction "I4_4") (pintype "input"))
    )
    (net (code "391") (name "Net-(IC105A-Q5)") (class "Default")
      (node (ref "IC105") (pin "6") (pinfunction "Q5_6") (pintype "output"))
      (node (ref "IC107") (pin "3") (pinfunction "I3_3") (pintype "input"))
    )
    (net (code "392") (name "Net-(IC107-O1)") (class "Default")
      (node (ref "IC107") (pin "16") (pinfunction "O1_16") (pintype "open_collector"))
      (node (ref "Q106") (pin "3") (pinfunction "D_3") (pintype "passive"))
      (node (ref "R9") (pin "1") (pinfunction "1_1") (pintype "passive"))
    )
    (net (code "393") (name "Net-(IC107-O2)") (class "Default")
      (node (ref "IC107") (pin "15") (pinfunction "O2_15") (pintype "open_collector"))
      (node (ref "R128") (pin "1") (pinfunction "1_1") (pintype "passive"))
    )
    (net (code "394") (name "Net-(IC108A-+IN)") (class "Default")
      (node (ref "IC108") (pin "11") (pinfunction "+IN_11") (pintype "input"))
      (node (ref "IC108") (pin "5") (pinfunction "+IN_5") (pintype "input"))
      (node (ref "R131") (pin "1") (pinfunction "1_1") (pintype "passive"))
      (node (ref "R132") (pin "2") (pinfunction "2_2") (pintype "passive"))
      (node (ref "R133") (pin "2") (pinfunction "2_2") (pintype "passive"))
    )
    (net (code "395") (name "Net-(IC108A--IN)") (class "Default")
      (node (ref "C108") (pin "1") (pinfunction "1_1") (pintype "passive"))
      (node (ref "IC108") (pin "10") (pinfunction "-IN_10") (pintype "input"))
      (node (ref "IC108") (pin "4") (pinfunction "-IN_4") (pintype "input"))
      (node (ref "R130") (pin "1") (pinfunction "1_1") (pintype "passive"))
    )
    (net (code "396") (name "Net-(IC108A-OUT)") (class "Default")
      (node (ref "IC108") (pin "2") (pinfunction "OUT_2") (pintype "open_collector"))
      (node (ref "R133") (pin "1") (pinfunction "1_1") (pintype "passive"))
    )
    (net (code "397") (name "Net-(IC108B-+IN)") (class "Default")
      (node (ref "IC108") (pin "7") (pinfunction "+IN_7") (pintype "input"))
      (node (ref "R121") (pin "1") (pinfunction "1_1") (pintype "passive"))
      (node (ref "R122") (pin "1") (pinfunction "1_1") (pintype "passive"))
    )
    (net (code "398") (name "Net-(IC108B--IN)") (class "Default")
      (node (ref "IC108") (pin "6") (pinfunction "-IN_6") (pintype "input"))
      (node (ref "IC108") (pin "8") (pinfunction "-IN_8") (pintype "input"))
      (node (ref "R120") (pin "1") (pinfunction "1_1") (pintype "passive"))
    )
    (net (code "399") (name "Net-(IC108B-OUT)") (class "Default")
      (node (ref "IC108") (pin "1") (pinfunction "OUT_1") (pintype "open_collector"))
      (node (ref "R124") (pin "2") (pinfunction "2_2") (pintype "passive"))
      (node (ref "R125") (pin "2") (pinfunction "2_2") (pintype "passive"))
    )
    (net (code "400") (name "Net-(IC108C-+IN)") (class "Default")
      (node (ref "C105") (pin "1") (pinfunction "1_1") (pintype "passive"))
      (node (ref "IC108") (pin "9") (pinfunction "+IN_9") (pintype "input"))
      (node (ref "R122") (pin "2") (pinfunction "2_2") (pintype "passive"))
      (node (ref "R123") (pin "2") (pinfunction "2_2") (pintype "passive"))
    )
    (net (code "401") (name "Net-(IC108C-OUT)") (class "Default")
      (node (ref "C106") (pin "2") (pinfunction "2_2") (pintype "passive"))
      (node (ref "IC108") (pin "14") (pinfunction "OUT_14") (pintype "open_collector"))
      (node (ref "R126") (pin "2") (pinfunction "2_2") (pintype "passive"))
    )
    (net (code "402") (name "Net-(IC108D-OUT)") (class "Default")
      (node (ref "IC108") (pin "13") (pinfunction "OUT_13") (pintype "open_collector"))
      (node (ref "JP105") (pin "1") (pinfunction "1_1") (pintype "passive"))
      (node (ref "Q107") (pin "1") (pinfunction "G_1") (pintype "passive"))
      (node (ref "R135") (pin "2") (pinfunction "2_2") (pintype "passive"))
    )
    (net (code "403") (name "Net-(IC109-ADJ)") (class "Default")
      (node (ref "IC109") (pin "1") (pinfunction "ADJ_1") (pintype "input"))
      (node (ref "R120") (pin "2") (pinfunction "2_2") (pintype "passive"))
      (node (ref "R134") (pin "1") (pinfunction "1_1") (pintype "passive"))
      (node (ref "X101") (pin "7") (pinfunction "7_7") (pintype "passive"))
    )
    (net (code "404") (name "Net-(IC109-VI)") (class "Default")
      (node (ref "IC109") (pin "3") (pinfunction "VI_3") (pintype "input"))
      (node (ref "Q105") (pin "2") (pinfunction "C_2") (pintype "passive"))
    )
    (net (code "405") (name "Net-(IC109-VO)") (class "Default")
      (node (ref "IC109") (pin "2") (pinfunction "VO_2") (pintype "passive"))
      (node (ref "R134") (pin "2") (pinfunction "2_2") (pintype "passive"))
    )
    (net (code "406") (name "Net-(IC110-CV)") (class "Default")
      (node (ref "IC110") (pin "5") (pinfunction "CV_5") (pintype "input"))
      (node (ref "R144") (pin "2") (pinfunction "2_2") (pintype "passive"))
    )
    (net (code "407") (name "Net-(IC110-Q)") (class "Default")
      (node (ref "IC110") (pin "3") (pinfunction "Q_3") (pintype "output"))
      (node (ref "IC111") (pin "12") (pinfunction "A_12") (pintype "input"))
      (node (ref "IC111") (pin "4") (pinfunction "A_4") (pintype "input"))
      (node (ref "R144") (pin "1") (pinfunction "1_1") (pintype "passive"))
    )
    (net (code "408") (name "Net-(IC111A-T2)") (class "Default")
      (node (ref "C15") (pin "2") (pinfunction "2_2") (pintype "passive"))
      (node (ref "IC111") (pin "2") (pinfunction "T2_2") (pintype "input"))
      (node (ref "R10") (pin "1") (pinfunction "1_1") (pintype "passive"))
    )
    (net (code "409") (name "Net-(IC111A-~{Q})") (class "Default")
      (node (ref "IC111") (pin "7") (pinfunction "~{Q}_7") (pintype "output"))
      (node (ref "Q3") (pin "1") (pinfunction "G_1") (pintype "passive"))
    )
    (net (code "410") (name "Net-(IC111B-B)") (class "Default")
      (node (ref "IC111") (pin "11") (pinfunction "B_11") (pintype "input"))
      (node (ref "IC111") (pin "9") (pinfunction "~{Q}_9") (pintype "output"))
      (node (ref "R146") (pin "2") (pinfunction "2_2") (pintype "passive"))
    )
    (net (code "411") (name "Net-(IC111B-T2)") (class "Default")
      (node (ref "C110") (pin "1") (pinfunction "1_1") (pintype "passive"))
      (node (ref "IC111") (pin "14") (pinfunction "T2_14") (pintype "input"))
      (node (ref "R145") (pin "1") (pinfunction "1_1") (pintype "passive"))
    )
    (net (code "412") (name "Net-(JP1-Pad1)") (class "Default")
      (node (ref "JP1") (pin "1") (pinfunction "1_1") (pintype "passive"))
      (node (ref "R48") (pin "2") (pinfunction "2_2") (pintype "passive"))
    )
    (net (code "413") (name "Net-(JP2-Pad3)") (class "Default")
      (node (ref "JP2") (pin "3") (pinfunction "3_3") (pintype "passive"))
      (node (ref "R40") (pin "1") (pinfunction "1_1") (pintype "passive"))
    )
    (net (code "414") (name "Net-(JP5-Pad2)") (class "Default")
      (node (ref "JP5") (pin "2") (pinfunction "2_2") (pintype "passive"))
      (node (ref "R45") (pin "2") (pinfunction "2_2") (pintype "passive"))
      (node (ref "R46") (pin "2") (pinfunction "2_2") (pintype "passive"))
      (node (ref "SJ1") (pin "2") (pinfunction "2_2") (pintype "passive"))
    )
    (net (code "415") (name "Net-(JP6-Pad1)") (class "Default")
      (node (ref "JP6") (pin "1") (pinfunction "1_1") (pintype "passive"))
      (node (ref "R147") (pin "2") (pinfunction "2_2") (pintype "passive"))
    )
    (net (code "416") (name "Net-(JP7-Pad3)") (class "Default")
      (node (ref "JP7") (pin "3") (pinfunction "3_3") (pintype "passive"))
      (node (ref "R95") (pin "1") (pinfunction "1_1") (pintype "passive"))
    )
    (net (code "417") (name "Net-(JP10-Pad2)") (class "Default")
      (node (ref "JP10") (pin "2") (pinfunction "2_2") (pintype "passive"))
      (node (ref "R100") (pin "2") (pinfunction "2_2") (pintype "passive"))
      (node (ref "R118") (pin "2") (pinfunction "2_2") (pintype "passive"))
      (node (ref "SJ2") (pin "2") (pinfunction "2_2") (pintype "passive"))
    )
    (net (code "418") (name "Net-(JP11-Pad1)") (class "Default")
      (node (ref "JP11") (pin "1") (pinfunction "1_1") (pintype "passive"))
      (node (ref "R202") (pin "2") (pinfunction "2_2") (pintype "passive"))
    )
    (net (code "419") (name "Net-(JP12-Pad3)") (class "Default")
      (node (ref "JP12") (pin "3") (pinfunction "3_3") (pintype "passive"))
      (node (ref "R194") (pin "1") (pinfunction "1_1") (pintype "passive"))
    )
    (net (code "420") (name "Net-(JP15-Pad2)") (class "Default")
      (node (ref "JP15") (pin "2") (pinfunction "2_2") (pintype "passive"))
      (node (ref "R199") (pin "2") (pinfunction "2_2") (pintype "passive"))
      (node (ref "R200") (pin "2") (pinfunction "2_2") (pintype "passive"))
      (node (ref "SJ3") (pin "2") (pinfunction "2_2") (pintype "passive"))
    )
    (net (code "421") (name "Net-(JP16-Pad1)") (class "Default")
      (node (ref "JP16") (pin "1") (pinfunction "1_1") (pintype "passive"))
      (node (ref "R257") (pin "2") (pinfunction "2_2") (pintype "passive"))
    )
    (net (code "422") (name "Net-(JP17-Pad3)") (class "Default")
      (node (ref "JP17") (pin "3") (pinfunction "3_3") (pintype "passive"))
      (node (ref "R249") (pin "1") (pinfunction "1_1") (pintype "passive"))
    )
    (net (code "423") (name "Net-(JP20-Pad2)") (class "Default")
      (node (ref "JP20") (pin "2") (pinfunction "2_2") (pintype "passive"))
      (node (ref "R254") (pin "2") (pinfunction "2_2") (pintype "passive"))
      (node (ref "R255") (pin "2") (pinfunction "2_2") (pintype "passive"))
      (node (ref "SJ4") (pin "2") (pinfunction "2_2") (pintype "passive"))
    )
    (net (code "424") (name "Net-(JP21-Pad1)") (class "Default")
      (node (ref "JP21") (pin "1") (pinfunction "1_1") (pintype "passive"))
      (node (ref "R312") (pin "2") (pinfunction "2_2") (pintype "passive"))
    )
    (net (code "425") (name "Net-(JP22-Pad3)") (class "Default")
      (node (ref "JP22") (pin "3") (pinfunction "3_3") (pintype "passive"))
      (node (ref "R304") (pin "1") (pinfunction "1_1") (pintype "passive"))
    )
    (net (code "426") (name "Net-(JP25-Pad2)") (class "Default")
      (node (ref "JP25") (pin "2") (pinfunction "2_2") (pintype "passive"))
      (node (ref "R309") (pin "2") (pinfunction "2_2") (pintype "passive"))
      (node (ref "R310") (pin "2") (pinfunction "2_2") (pintype "passive"))
      (node (ref "SJ5") (pin "2") (pinfunction "2_2") (pintype "passive"))
    )
    (net (code "427") (name "Net-(JP101-Pad1)") (class "Default")
      (node (ref "JP101") (pin "1") (pinfunction "1_1") (pintype "passive"))
      (node (ref "R119") (pin "2") (pinfunction "2_2") (pintype "passive"))
    )
    (net (code "428") (name "Net-(JP104-Pad2)") (class "Default")
      (node (ref "JP104") (pin "2") (pinfunction "2_2") (pintype "passive"))
      (node (ref "R136") (pin "2") (pinfunction "2_2") (pintype "passive"))
      (node (ref "R137") (pin "2") (pinfunction "2_2") (pintype "passive"))
      (node (ref "SJ101") (pin "2") (pinfunction "2_2") (pintype "passive"))
    )
    (net (code "429") (name "Net-(JP105-Pad3)") (class "Default")
      (node (ref "JP105") (pin "3") (pinfunction "3_3") (pintype "passive"))
      (node (ref "R138") (pin "1") (pinfunction "1_1") (pintype "passive"))
    )
    (net (code "430") (name "Net-(LED1-PadA)") (class "Default")
      (node (ref "LED1") (pin "A") (pinfunction "A_A") (pintype "passive"))
      (node (ref "LED2") (pin "A") (pinfunction "A_A") (pintype "passive"))
      (node (ref "LED3") (pin "A") (pinfunction "A_A") (pintype "passive"))
      (node (ref "LED4") (pin "A") (pinfunction "A_A") (pintype "passive"))
      (node (ref "LED6") (pin "A") (pinfunction "A_A") (pintype "passive"))
      (node (ref "R34") (pin "1") (pinfunction "1_1") (pintype "passive"))
    )
    (net (code "431") (name "Net-(LED5-C)") (class "Default")
      (node (ref "LED5") (pin "K") (pinfunction "C_K") (pintype "passive"))
      (node (ref "R33") (pin "1") (pinfunction "1_1") (pintype "passive"))
    )
    (net (code "432") (name "Net-(LED10-PadA)") (class "Default")
      (node (ref "LED10") (pin "A") (pinfunction "A_A") (pintype "passive"))
      (node (ref "LED12") (pin "A") (pinfunction "A_A") (pintype "passive"))
      (node (ref "LED7") (pin "A") (pinfunction "A_A") (pintype "passive"))
      (node (ref "LED8") (pin "A") (pinfunction "A_A") (pintype "passive"))
      (node (ref "LED9") (pin "A") (pinfunction "A_A") (pintype "passive"))
      (node (ref "R89") (pin "1") (pinfunction "1_1") (pintype "passive"))
    )
    (net (code "433") (name "Net-(LED11-C)") (class "Default")
      (node (ref "LED11") (pin "K") (pinfunction "C_K") (pintype "passive"))
      (node (ref "R88") (pin "1") (pinfunction "1_1") (pintype "passive"))
    )
    (net (code "434") (name "Net-(LED13-PadA)") (class "Default")
      (node (ref "LED13") (pin "A") (pinfunction "A_A") (pintype "passive"))
      (node (ref "LED14") (pin "A") (pinfunction "A_A") (pintype "passive"))
      (node (ref "LED15") (pin "A") (pinfunction "A_A") (pintype "passive"))
      (node (ref "LED16") (pin "A") (pinfunction "A_A") (pintype "passive"))
      (node (ref "LED18") (pin "A") (pinfunction "A_A") (pintype "passive"))
      (node (ref "R188") (pin "1") (pinfunction "1_1") (pintype "passive"))
    )
    (net (code "435") (name "Net-(LED17-C)") (class "Default")
      (node (ref "LED17") (pin "K") (pinfunction "C_K") (pintype "passive"))
      (node (ref "R187") (pin "1") (pinfunction "1_1") (pintype "passive"))
    )
    (net (code "436") (name "Net-(LED19-PadA)") (class "Default")
      (node (ref "LED19") (pin "A") (pinfunction "A_A") (pintype "passive"))
      (node (ref "LED20") (pin "A") (pinfunction "A_A") (pintype "passive"))
      (node (ref "LED21") (pin "A") (pinfunction "A_A") (pintype "passive"))
      (node (ref "LED22") (pin "A") (pinfunction "A_A") (pintype "passive"))
      (node (ref "LED24") (pin "A") (pinfunction "A_A") (pintype "passive"))
      (node (ref "R243") (pin "1") (pinfunction "1_1") (pintype "passive"))
    )
    (net (code "437") (name "Net-(LED23-C)") (class "Default")
      (node (ref "LED23") (pin "K") (pinfunction "C_K") (pintype "passive"))
      (node (ref "R242") (pin "1") (pinfunction "1_1") (pintype "passive"))
    )
    (net (code "438") (name "Net-(LED25-PadA)") (class "Default")
      (node (ref "LED25") (pin "A") (pinfunction "A_A") (pintype "passive"))
      (node (ref "LED26") (pin "A") (pinfunction "A_A") (pintype "passive"))
      (node (ref "LED27") (pin "A") (pinfunction "A_A") (pintype "passive"))
      (node (ref "LED28") (pin "A") (pinfunction "A_A") (pintype "passive"))
      (node (ref "LED30") (pin "A") (pinfunction "A_A") (pintype "passive"))
      (node (ref "R298") (pin "1") (pinfunction "1_1") (pintype "passive"))
    )
    (net (code "439") (name "Net-(LED29-C)") (class "Default")
      (node (ref "LED29") (pin "K") (pinfunction "C_K") (pintype "passive"))
      (node (ref "R297") (pin "1") (pinfunction "1_1") (pintype "passive"))
    )
    (net (code "440") (name "Net-(LED101-C)") (class "Default")
      (node (ref "LED101") (pin "K") (pinfunction "C_K") (pintype "passive"))
      (node (ref "R143") (pin "1") (pinfunction "1_1") (pintype "passive"))
    )
    (net (code "441") (name "Net-(LED102-PadA)") (class "Default")
      (node (ref "LED102") (pin "A") (pinfunction "A_A") (pintype "passive"))
      (node (ref "LED103") (pin "A") (pinfunction "A_A") (pintype "passive"))
      (node (ref "LED104") (pin "A") (pinfunction "A_A") (pintype "passive"))
      (node (ref "LED105") (pin "A") (pinfunction "A_A") (pintype "passive"))
      (node (ref "LED106") (pin "A") (pinfunction "A_A") (pintype "passive"))
      (node (ref "R142") (pin "1") (pinfunction "1_1") (pintype "passive"))
    )
    (net (code "442") (name "Net-(Q2-B)") (class "Default")
      (node (ref "Q2") (pin "1") (pinfunction "B_1") (pintype "passive"))
      (node (ref "R8") (pin "1") (pinfunction "1_1") (pintype "passive"))
    )
    (net (code "443") (name "Net-(Q2-C)") (class "Default")
      (node (ref "Q2") (pin "2") (pinfunction "C_2") (pintype "passive"))
      (node (ref "R129") (pin "2") (pinfunction "2_2") (pintype "passive"))
      (node (ref "SJMP") (pin "2") (pinfunction "2_2") (pintype "passive"))
    )
    (net (code "444") (name "Net-(Q3-D)") (class "Default")
      (node (ref "Q3") (pin "3") (pinfunction "D_3") (pintype "passive"))
      (node (ref "R8") (pin "2") (pinfunction "2_2") (pintype "passive"))
    )
    (net (code "445") (name "Net-(Q4-B)") (class "Default")
      (node (ref "Q4") (pin "1") (pinfunction "B_1") (pintype "passive"))
      (node (ref "R35") (pin "2") (pinfunction "2_2") (pintype "passive"))
    )
    (net (code "446") (name "Net-(Q5-B)") (class "Default")
      (node (ref "Q5") (pin "1") (pinfunction "B_1") (pintype "passive"))
      (node (ref "Q5") (pin "2") (pinfunction "C_2") (pintype "passive"))
      (node (ref "Q6") (pin "1") (pinfunction "B_1") (pintype "passive"))
      (node (ref "R30") (pin "1") (pinfunction "1_1") (pintype "passive"))
      (node (ref "R31") (pin "1") (pinfunction "1_1") (pintype "passive"))
      (node (ref "R55") (pin "1") (pinfunction "1_1") (pintype "passive"))
      (node (ref "X3") (pin "2") (pinfunction "S_2") (pintype "passive"))
    )
    (net (code "447") (name "Net-(Q5-E)") (class "Default")
      (node (ref "Q5") (pin "3") (pinfunction "E_3") (pintype "passive"))
      (node (ref "R36") (pin "2") (pinfunction "2_2") (pintype "passive"))
    )
    (net (code "448") (name "Net-(Q6-E)") (class "Default")
      (node (ref "Q6") (pin "3") (pinfunction "E_3") (pintype "passive"))
      (node (ref "R37") (pin "2") (pinfunction "2_2") (pintype "passive"))
    )
    (net (code "449") (name "Net-(Q7-B)") (class "Default")
      (node (ref "Q7") (pin "1") (pinfunction "B_1") (pintype "passive"))
      (node (ref "R28") (pin "1") (pinfunction "1_1") (pintype "passive"))
    )
    (net (code "450") (name "Net-(Q8-B)") (class "Default")
      (node (ref "Q8") (pin "1") (pinfunction "B_1") (pintype "passive"))
      (node (ref "R39") (pin "2") (pinfunction "2_2") (pintype "passive"))
      (node (ref "R60") (pin "1") (pinfunction "1_1") (pintype "passive"))
    )
    (net (code "451") (name "Net-(Q8-E)") (class "Default")
      (node (ref "Q8") (pin "3") (pinfunction "E_3") (pintype "passive"))
      (node (ref "R59") (pin "1") (pinfunction "1_1") (pintype "passive"))
    )
    (net (code "452") (name "Net-(Q9-D)") (class "Default")
      (node (ref "Q9") (pin "3") (pinfunction "D_3") (pintype "passive"))
      (node (ref "R40") (pin "2") (pinfunction "2_2") (pintype "passive"))
    )
    (net (code "453") (name "Net-(Q10-S)") (class "Default")
      (node (ref "Q10") (pin "2") (pinfunction "S_2") (pintype "passive"))
      (node (ref "R61") (pin "2") (pinfunction "2_2") (pintype "passive"))
    )
    (net (code "454") (name "Net-(Q12-B)") (class "Default")
      (node (ref "Q12") (pin "1") (pinfunction "B_1") (pintype "passive"))
      (node (ref "R63") (pin "1") (pinfunction "1_1") (pintype "passive"))
    )
    (net (code "455") (name "Net-(Q12-C)") (class "Default")
      (node (ref "Q12") (pin "2") (pinfunction "C_2") (pintype "passive"))
      (node (ref "R14") (pin "2") (pinfunction "2_2") (pintype "passive"))
      (node (ref "SJMP1") (pin "2") (pinfunction "2_2") (pintype "passive"))
    )
    (net (code "456") (name "Net-(Q13-D)") (class "Default")
      (node (ref "Q13") (pin "3") (pinfunction "D_3") (pintype "passive"))
      (node (ref "R63") (pin "2") (pinfunction "2_2") (pintype "passive"))
    )
    (net (code "457") (name "Net-(Q14-B)") (class "Default")
      (node (ref "Q14") (pin "1") (pinfunction "B_1") (pintype "passive"))
      (node (ref "R90") (pin "2") (pinfunction "2_2") (pintype "passive"))
    )
    (net (code "458") (name "Net-(Q15-B)") (class "Default")
      (node (ref "Q15") (pin "1") (pinfunction "B_1") (pintype "passive"))
      (node (ref "Q15") (pin "2") (pinfunction "C_2") (pintype "passive"))
      (node (ref "Q16") (pin "1") (pinfunction "B_1") (pintype "passive"))
      (node (ref "R154") (pin "1") (pinfunction "1_1") (pintype "passive"))
      (node (ref "R85") (pin "1") (pinfunction "1_1") (pintype "passive"))
      (node (ref "R86") (pin "1") (pinfunction "1_1") (pintype "passive"))
      (node (ref "X6") (pin "2") (pinfunction "S_2") (pintype "passive"))
    )
    (net (code "459") (name "Net-(Q15-E)") (class "Default")
      (node (ref "Q15") (pin "3") (pinfunction "E_3") (pintype "passive"))
      (node (ref "R91") (pin "2") (pinfunction "2_2") (pintype "passive"))
    )
    (net (code "460") (name "Net-(Q16-E)") (class "Default")
      (node (ref "Q16") (pin "3") (pinfunction "E_3") (pintype "passive"))
      (node (ref "R92") (pin "2") (pinfunction "2_2") (pintype "passive"))
    )
    (net (code "461") (name "Net-(Q17-B)") (class "Default")
      (node (ref "Q17") (pin "1") (pinfunction "B_1") (pintype "passive"))
      (node (ref "R83") (pin "1") (pinfunction "1_1") (pintype "passive"))
    )
    (net (code "462") (name "Net-(Q18-B)") (class "Default")
      (node (ref "Q18") (pin "1") (pinfunction "B_1") (pintype "passive"))
      (node (ref "R159") (pin "1") (pinfunction "1_1") (pintype "passive"))
      (node (ref "R94") (pin "2") (pinfunction "2_2") (pintype "passive"))
    )
    (net (code "463") (name "Net-(Q18-E)") (class "Default")
      (node (ref "Q18") (pin "3") (pinfunction "E_3") (pintype "passive"))
      (node (ref "R158") (pin "1") (pinfunction "1_1") (pintype "passive"))
    )
    (net (code "464") (name "Net-(Q19-D)") (class "Default")
      (node (ref "Q19") (pin "3") (pinfunction "D_3") (pintype "passive"))
      (node (ref "R95") (pin "2") (pinfunction "2_2") (pintype "passive"))
    )
    (net (code "465") (name "Net-(Q20-S)") (class "Default")
      (node (ref "Q20") (pin "2") (pinfunction "S_2") (pintype "passive"))
      (node (ref "R160") (pin "2") (pinfunction "2_2") (pintype "passive"))
    )
    (net (code "466") (name "Net-(Q22-B)") (class "Default")
      (node (ref "Q22") (pin "1") (pinfunction "B_1") (pintype "passive"))
      (node (ref "R162") (pin "1") (pinfunction "1_1") (pintype "passive"))
    )
    (net (code "467") (name "Net-(Q22-C)") (class "Default")
      (node (ref "Q22") (pin "2") (pinfunction "C_2") (pintype "passive"))
      (node (ref "R69") (pin "2") (pinfunction "2_2") (pintype "passive"))
      (node (ref "SJMP2") (pin "2") (pinfunction "2_2") (pintype "passive"))
    )
    (net (code "468") (name "Net-(Q23-D)") (class "Default")
      (node (ref "Q23") (pin "3") (pinfunction "D_3") (pintype "passive"))
      (node (ref "R162") (pin "2") (pinfunction "2_2") (pintype "passive"))
    )
    (net (code "469") (name "Net-(Q24-B)") (class "Default")
      (node (ref "Q24") (pin "1") (pinfunction "B_1") (pintype "passive"))
      (node (ref "R189") (pin "2") (pinfunction "2_2") (pintype "passive"))
    )
    (net (code "470") (name "Net-(Q25-B)") (class "Default")
      (node (ref "Q25") (pin "1") (pinfunction "B_1") (pintype "passive"))
      (node (ref "Q25") (pin "2") (pinfunction "C_2") (pintype "passive"))
      (node (ref "Q26") (pin "1") (pinfunction "B_1") (pintype "passive"))
      (node (ref "R184") (pin "1") (pinfunction "1_1") (pintype "passive"))
      (node (ref "R185") (pin "1") (pinfunction "1_1") (pintype "passive"))
      (node (ref "R209") (pin "1") (pinfunction "1_1") (pintype "passive"))
      (node (ref "X9") (pin "2") (pinfunction "S_2") (pintype "passive"))
    )
    (net (code "471") (name "Net-(Q25-E)") (class "Default")
      (node (ref "Q25") (pin "3") (pinfunction "E_3") (pintype "passive"))
      (node (ref "R190") (pin "2") (pinfunction "2_2") (pintype "passive"))
    )
    (net (code "472") (name "Net-(Q26-E)") (class "Default")
      (node (ref "Q26") (pin "3") (pinfunction "E_3") (pintype "passive"))
      (node (ref "R191") (pin "2") (pinfunction "2_2") (pintype "passive"))
    )
    (net (code "473") (name "Net-(Q27-B)") (class "Default")
      (node (ref "Q27") (pin "1") (pinfunction "B_1") (pintype "passive"))
      (node (ref "R182") (pin "1") (pinfunction "1_1") (pintype "passive"))
    )
    (net (code "474") (name "Net-(Q28-B)") (class "Default")
      (node (ref "Q28") (pin "1") (pinfunction "B_1") (pintype "passive"))
      (node (ref "R193") (pin "2") (pinfunction "2_2") (pintype "passive"))
      (node (ref "R214") (pin "1") (pinfunction "1_1") (pintype "passive"))
    )
    (net (code "475") (name "Net-(Q28-E)") (class "Default")
      (node (ref "Q28") (pin "3") (pinfunction "E_3") (pintype "passive"))
      (node (ref "R213") (pin "1") (pinfunction "1_1") (pintype "passive"))
    )
    (net (code "476") (name "Net-(Q29-D)") (class "Default")
      (node (ref "Q29") (pin "3") (pinfunction "D_3") (pintype "passive"))
      (node (ref "R194") (pin "2") (pinfunction "2_2") (pintype "passive"))
    )
    (net (code "477") (name "Net-(Q30-S)") (class "Default")
      (node (ref "Q30") (pin "2") (pinfunction "S_2") (pintype "passive"))
      (node (ref "R215") (pin "2") (pinfunction "2_2") (pintype "passive"))
    )
    (net (code "478") (name "Net-(Q32-B)") (class "Default")
      (node (ref "Q32") (pin "1") (pinfunction "B_1") (pintype "passive"))
      (node (ref "R217") (pin "1") (pinfunction "1_1") (pintype "passive"))
    )
    (net (code "479") (name "Net-(Q32-C)") (class "Default")
      (node (ref "Q32") (pin "2") (pinfunction "C_2") (pintype "passive"))
      (node (ref "R168") (pin "2") (pinfunction "2_2") (pintype "passive"))
      (node (ref "SJMP3") (pin "2") (pinfunction "2_2") (pintype "passive"))
    )
    (net (code "480") (name "Net-(Q33-D)") (class "Default")
      (node (ref "Q33") (pin "3") (pinfunction "D_3") (pintype "passive"))
      (node (ref "R217") (pin "2") (pinfunction "2_2") (pintype "passive"))
    )
    (net (code "481") (name "Net-(Q34-B)") (class "Default")
      (node (ref "Q34") (pin "1") (pinfunction "B_1") (pintype "passive"))
      (node (ref "R244") (pin "2") (pinfunction "2_2") (pintype "passive"))
    )
    (net (code "482") (name "Net-(Q35-B)") (class "Default")
      (node (ref "Q35") (pin "1") (pinfunction "B_1") (pintype "passive"))
      (node (ref "Q35") (pin "2") (pinfunction "C_2") (pintype "passive"))
      (node (ref "Q36") (pin "1") (pinfunction "B_1") (pintype "passive"))
      (node (ref "R239") (pin "1") (pinfunction "1_1") (pintype "passive"))
      (node (ref "R240") (pin "1") (pinfunction "1_1") (pintype "passive"))
      (node (ref "R264") (pin "1") (pinfunction "1_1") (pintype "passive"))
      (node (ref "X12") (pin "2") (pinfunction "S_2") (pintype "passive"))
    )
    (net (code "483") (name "Net-(Q35-E)") (class "Default")
      (node (ref "Q35") (pin "3") (pinfunction "E_3") (pintype "passive"))
      (node (ref "R245") (pin "2") (pinfunction "2_2") (pintype "passive"))
    )
    (net (code "484") (name "Net-(Q36-E)") (class "Default")
      (node (ref "Q36") (pin "3") (pinfunction "E_3") (pintype "passive"))
      (node (ref "R246") (pin "2") (pinfunction "2_2") (pintype "passive"))
    )
    (net (code "485") (name "Net-(Q37-B)") (class "Default")
      (node (ref "Q37") (pin "1") (pinfunction "B_1") (pintype "passive"))
      (node (ref "R237") (pin "1") (pinfunction "1_1") (pintype "passive"))
    )
    (net (code "486") (name "Net-(Q38-B)") (class "Default")
      (node (ref "Q38") (pin "1") (pinfunction "B_1") (pintype "passive"))
      (node (ref "R248") (pin "2") (pinfunction "2_2") (pintype "passive"))
      (node (ref "R269") (pin "1") (pinfunction "1_1") (pintype "passive"))
    )
    (net (code "487") (name "Net-(Q38-E)") (class "Default")
      (node (ref "Q38") (pin "3") (pinfunction "E_3") (pintype "passive"))
      (node (ref "R268") (pin "1") (pinfunction "1_1") (pintype "passive"))
    )
    (net (code "488") (name "Net-(Q39-D)") (class "Default")
      (node (ref "Q39") (pin "3") (pinfunction "D_3") (pintype "passive"))
      (node (ref "R249") (pin "2") (pinfunction "2_2") (pintype "passive"))
    )
    (net (code "489") (name "Net-(Q40-S)") (class "Default")
      (node (ref "Q40") (pin "2") (pinfunction "S_2") (pintype "passive"))
      (node (ref "R270") (pin "2") (pinfunction "2_2") (pintype "passive"))
    )
    (net (code "490") (name "Net-(Q42-B)") (class "Default")
      (node (ref "Q42") (pin "1") (pinfunction "B_1") (pintype "passive"))
      (node (ref "R272") (pin "1") (pinfunction "1_1") (pintype "passive"))
    )
    (net (code "491") (name "Net-(Q42-C)") (class "Default")
      (node (ref "Q42") (pin "2") (pinfunction "C_2") (pintype "passive"))
      (node (ref "R223") (pin "2") (pinfunction "2_2") (pintype "passive"))
      (node (ref "SJMP4") (pin "2") (pinfunction "2_2") (pintype "passive"))
    )
    (net (code "492") (name "Net-(Q43-D)") (class "Default")
      (node (ref "Q43") (pin "3") (pinfunction "D_3") (pintype "passive"))
      (node (ref "R272") (pin "2") (pinfunction "2_2") (pintype "passive"))
    )
    (net (code "493") (name "Net-(Q44-B)") (class "Default")
      (node (ref "Q44") (pin "1") (pinfunction "B_1") (pintype "passive"))
      (node (ref "R299") (pin "2") (pinfunction "2_2") (pintype "passive"))
    )
    (net (code "494") (name "Net-(Q45-B)") (class "Default")
      (node (ref "Q45") (pin "1") (pinfunction "B_1") (pintype "passive"))
      (node (ref "Q45") (pin "2") (pinfunction "C_2") (pintype "passive"))
      (node (ref "Q46") (pin "1") (pinfunction "B_1") (pintype "passive"))
      (node (ref "R294") (pin "1") (pinfunction "1_1") (pintype "passive"))
      (node (ref "R295") (pin "1") (pinfunction "1_1") (pintype "passive"))
      (node (ref "R319") (pin "1") (pinfunction "1_1") (pintype "passive"))
      (node (ref "X15") (pin "2") (pinfunction "S_2") (pintype "passive"))
    )
    (net (code "495") (name "Net-(Q45-E)") (class "Default")
      (node (ref "Q45") (pin "3") (pinfunction "E_3") (pintype "passive"))
      (node (ref "R300") (pin "2") (pinfunction "2_2") (pintype "passive"))
    )
    (net (code "496") (name "Net-(Q46-E)") (class "Default")
      (node (ref "Q46") (pin "3") (pinfunction "E_3") (pintype "passive"))
      (node (ref "R301") (pin "2") (pinfunction "2_2") (pintype "passive"))
    )
    (net (code "497") (name "Net-(Q47-B)") (class "Default")
      (node (ref "Q47") (pin "1") (pinfunction "B_1") (pintype "passive"))
      (node (ref "R292") (pin "1") (pinfunction "1_1") (pintype "passive"))
    )
    (net (code "498") (name "Net-(Q48-B)") (class "Default")
      (node (ref "Q48") (pin "1") (pinfunction "B_1") (pintype "passive"))
      (node (ref "R303") (pin "2") (pinfunction "2_2") (pintype "passive"))
      (node (ref "R324") (pin "1") (pinfunction "1_1") (pintype "passive"))
    )
    (net (code "499") (name "Net-(Q48-E)") (class "Default")
      (node (ref "Q48") (pin "3") (pinfunction "E_3") (pintype "passive"))
      (node (ref "R323") (pin "1") (pinfunction "1_1") (pintype "passive"))
    )
    (net (code "500") (name "Net-(Q49-D)") (class "Default")
      (node (ref "Q49") (pin "3") (pinfunction "D_3") (pintype "passive"))
      (node (ref "R304") (pin "2") (pinfunction "2_2") (pintype "passive"))
    )
    (net (code "501") (name "Net-(Q50-S)") (class "Default")
      (node (ref "Q50") (pin "2") (pinfunction "S_2") (pintype "passive"))
      (node (ref "R325") (pin "2") (pinfunction "2_2") (pintype "passive"))
    )
    (net (code "502") (name "Net-(Q52-B)") (class "Default")
      (node (ref "Q52") (pin "1") (pinfunction "B_1") (pintype "passive"))
      (node (ref "R327") (pin "1") (pinfunction "1_1") (pintype "passive"))
    )
    (net (code "503") (name "Net-(Q52-C)") (class "Default")
      (node (ref "Q52") (pin "2") (pinfunction "C_2") (pintype "passive"))
      (node (ref "R278") (pin "2") (pinfunction "2_2") (pintype "passive"))
      (node (ref "SJMP5") (pin "2") (pinfunction "2_2") (pintype "passive"))
    )
    (net (code "504") (name "Net-(Q53-D)") (class "Default")
      (node (ref "Q53") (pin "3") (pinfunction "D_3") (pintype "passive"))
      (node (ref "R327") (pin "2") (pinfunction "2_2") (pintype "passive"))
    )
    (net (code "505") (name "Net-(Q101-B)") (class "Default")
      (node (ref "Q101") (pin "1") (pinfunction "B_1") (pintype "passive"))
      (node (ref "Q102") (pin "1") (pinfunction "B_1") (pintype "passive"))
      (node (ref "Q102") (pin "2") (pinfunction "C_2") (pintype "passive"))
      (node (ref "R101") (pin "1") (pinfunction "1_1") (pintype "passive"))
      (node (ref "R103") (pin "1") (pinfunction "1_1") (pintype "passive"))
      (node (ref "R104") (pin "1") (pinfunction "1_1") (pintype "passive"))
      (node (ref "X102") (pin "2") (pinfunction "S_2") (pintype "passive"))
    )
    (net (code "506") (name "Net-(Q101-E)") (class "Default")
      (node (ref "Q101") (pin "3") (pinfunction "E_3") (pintype "passive"))
      (node (ref "R102") (pin "2") (pinfunction "2_2") (pintype "passive"))
    )
    (net (code "507") (name "Net-(Q102-E)") (class "Default")
      (node (ref "Q102") (pin "3") (pinfunction "E_3") (pintype "passive"))
      (node (ref "R106") (pin "2") (pinfunction "2_2") (pintype "passive"))
    )
    (net (code "508") (name "Net-(Q103-B)") (class "Default")
      (node (ref "Q103") (pin "1") (pinfunction "B_1") (pintype "passive"))
      (node (ref "R116") (pin "2") (pinfunction "2_2") (pintype "passive"))
      (node (ref "R6") (pin "1") (pinfunction "1_1") (pintype "passive"))
    )
    (net (code "509") (name "Net-(Q103-E)") (class "Default")
      (node (ref "Q103") (pin "3") (pinfunction "E_3") (pintype "passive"))
      (node (ref "R5") (pin "1") (pinfunction "1_1") (pintype "passive"))
    )
    (net (code "510") (name "Net-(Q104-B)") (class "Default")
      (node (ref "Q104") (pin "1") (pinfunction "B_1") (pintype "passive"))
      (node (ref "R128") (pin "2") (pinfunction "2_2") (pintype "passive"))
    )
    (net (code "511") (name "Net-(Q105-B)") (class "Default")
      (node (ref "Q105") (pin "1") (pinfunction "B_1") (pintype "passive"))
      (node (ref "R126") (pin "1") (pinfunction "1_1") (pintype "passive"))
    )
    (net (code "512") (name "Net-(Q106-S)") (class "Default")
      (node (ref "Q106") (pin "2") (pinfunction "S_2") (pintype "passive"))
      (node (ref "R4") (pin "2") (pinfunction "2_2") (pintype "passive"))
    )
    (net (code "513") (name "Net-(Q107-D)") (class "Default")
      (node (ref "Q107") (pin "3") (pinfunction "D_3") (pintype "passive"))
      (node (ref "R138") (pin "2") (pinfunction "2_2") (pintype "passive"))
    )
    (net (code "514") (name "Net-(R14-Pad1)") (class "Default")
      (node (ref "R14") (pin "1") (pinfunction "1_1") (pintype "passive"))
      (node (ref "R7") (pin "2") (pinfunction "2_2") (pintype "passive"))
    )
    (net (code "515") (name "Net-(R32-Pad1)") (class "Default")
      (node (ref "R32") (pin "1") (pinfunction "1_1") (pintype "passive"))
      (node (ref "X1") (pin "21") (pinfunction "21_21") (pintype "passive"))
    )
    (net (code "516") (name "Net-(R44-Pad2)") (class "Default")
      (node (ref "R44") (pin "2") (pinfunction "2_2") (pintype "passive"))
      (node (ref "X1") (pin "16") (pinfunction "16_16") (pintype "passive"))
    )
    (net (code "517") (name "Net-(R67-Pad2)") (class "Default")
      (node (ref "R67") (pin "2") (pinfunction "2_2") (pintype "passive"))
      (node (ref "R69") (pin "1") (pinfunction "1_1") (pintype "passive"))
    )
    (net (code "518") (name "Net-(R87-Pad1)") (class "Default")
      (node (ref "R87") (pin "1") (pinfunction "1_1") (pintype "passive"))
      (node (ref "X4") (pin "21") (pinfunction "21_21") (pintype "passive"))
    )
    (net (code "519") (name "Net-(R99-Pad2)") (class "Default")
      (node (ref "R99") (pin "2") (pinfunction "2_2") (pintype "passive"))
      (node (ref "X4") (pin "16") (pinfunction "16_16") (pintype "passive"))
    )
    (net (code "520") (name "Net-(R115-Pad1)") (class "Default")
      (node (ref "R115") (pin "1") (pinfunction "1_1") (pintype "passive"))
      (node (ref "X101") (pin "21") (pinfunction "21_21") (pintype "passive"))
    )
    (net (code "521") (name "Net-(R127-Pad2)") (class "Default")
      (node (ref "R127") (pin "2") (pinfunction "2_2") (pintype "passive"))
      (node (ref "R129") (pin "1") (pinfunction "1_1") (pintype "passive"))
    )
    (net (code "522") (name "Net-(R140-Pad2)") (class "Default")
      (node (ref "R140") (pin "2") (pinfunction "2_2") (pintype "passive"))
      (node (ref "X101") (pin "16") (pinfunction "16_16") (pintype "passive"))
    )
    (net (code "523") (name "Net-(R166-Pad2)") (class "Default")
      (node (ref "R166") (pin "2") (pinfunction "2_2") (pintype "passive"))
      (node (ref "R168") (pin "1") (pinfunction "1_1") (pintype "passive"))
    )
    (net (code "524") (name "Net-(R186-Pad1)") (class "Default")
      (node (ref "R186") (pin "1") (pinfunction "1_1") (pintype "passive"))
      (node (ref "X7") (pin "21") (pinfunction "21_21") (pintype "passive"))
    )
    (net (code "525") (name "Net-(R198-Pad2)") (class "Default")
      (node (ref "R198") (pin "2") (pinfunction "2_2") (pintype "passive"))
      (node (ref "X7") (pin "16") (pinfunction "16_16") (pintype "passive"))
    )
    (net (code "526") (name "Net-(R221-Pad2)") (class "Default")
      (node (ref "R221") (pin "2") (pinfunction "2_2") (pintype "passive"))
      (node (ref "R223") (pin "1") (pinfunction "1_1") (pintype "passive"))
    )
    (net (code "527") (name "Net-(R241-Pad1)") (class "Default")
      (node (ref "R241") (pin "1") (pinfunction "1_1") (pintype "passive"))
      (node (ref "X10") (pin "21") (pinfunction "21_21") (pintype "passive"))
    )
    (net (code "528") (name "Net-(R253-Pad2)") (class "Default")
      (node (ref "R253") (pin "2") (pinfunction "2_2") (pintype "passive"))
      (node (ref "X10") (pin "16") (pinfunction "16_16") (pintype "passive"))
    )
    (net (code "529") (name "Net-(R276-Pad2)") (class "Default")
      (node (ref "R276") (pin "2") (pinfunction "2_2") (pintype "passive"))
      (node (ref "R278") (pin "1") (pinfunction "1_1") (pintype "passive"))
    )
    (net (code "530") (name "Net-(R296-Pad1)") (class "Default")
      (node (ref "R296") (pin "1") (pinfunction "1_1") (pintype "passive"))
      (node (ref "X13") (pin "21") (pinfunction "21_21") (pintype "passive"))
    )
    (net (code "531") (name "Net-(R308-Pad2)") (class "Default")
      (node (ref "R308") (pin "2") (pinfunction "2_2") (pintype "passive"))
      (node (ref "X13") (pin "16") (pinfunction "16_16") (pintype "passive"))
    )
    (net (code "532") (name "V+") (class "Default")
      (node (ref "D1") (pin "1") (pinfunction "+_1") (pintype "passive"))
      (node (ref "D15") (pin "1") (pinfunction "+_1") (pintype "passive"))
      (node (ref "D29") (pin "1") (pinfunction "+_1") (pintype "passive"))
      (node (ref "D43") (pin "1") (pinfunction "+_1") (pintype "passive"))
      (node (ref "D57") (pin "1") (pinfunction "+_1") (pintype "passive"))
      (node (ref "D71") (pin "1") (pinfunction "+_1") (pintype "passive"))
      (node (ref "Q104") (pin "3") (pinfunction "E_3") (pintype "passive"))
      (node (ref "Q105") (pin "3") (pinfunction "E_3") (pintype "passive"))
      (node (ref "Q12") (pin "3") (pinfunction "E_3") (pintype "passive"))
      (node (ref "Q14") (pin "3") (pinfunction "E_3") (pintype "passive"))
      (node (ref "Q17") (pin "3") (pinfunction "E_3") (pintype "passive"))
      (node (ref "Q2") (pin "3") (pinfunction "E_3") (pintype "passive"))
      (node (ref "Q22") (pin "3") (pinfunction "E_3") (pintype "passive"))
      (node (ref "Q24") (pin "3") (pinfunction "E_3") (pintype "passive"))
      (node (ref "Q27") (pin "3") (pinfunction "E_3") (pintype "passive"))
      (node (ref "Q32") (pin "3") (pinfunction "E_3") (pintype "passive"))
      (node (ref "Q34") (pin "3") (pinfunction "E_3") (pintype "passive"))
      (node (ref "Q37") (pin "3") (pinfunction "E_3") (pintype "passive"))
      (node (ref "Q4") (pin "3") (pinfunction "E_3") (pintype "passive"))
      (node (ref "Q42") (pin "3") (pinfunction "E_3") (pintype "passive"))
      (node (ref "Q44") (pin "3") (pinfunction "E_3") (pintype "passive"))
      (node (ref "Q47") (pin "3") (pinfunction "E_3") (pintype "passive"))
      (node (ref "Q52") (pin "3") (pinfunction "E_3") (pintype "passive"))
      (node (ref "Q7") (pin "3") (pinfunction "E_3") (pintype "passive"))
      (node (ref "SJMP") (pin "1") (pinfunction "1_1") (pintype "passive"))
      (node (ref "SJMP1") (pin "1") (pinfunction "1_1") (pintype "passive"))
      (node (ref "SJMP2") (pin "1") (pinfunction "1_1") (pintype "passive"))
      (node (ref "SJMP3") (pin "1") (pinfunction "1_1") (pintype "passive"))
      (node (ref "SJMP4") (pin "1") (pinfunction "1_1") (pintype "passive"))
      (node (ref "SJMP5") (pin "1") (pinfunction "1_1") (pintype "passive"))
      (node (ref "X1") (pin "6") (pinfunction "6_6") (pintype "passive"))
      (node (ref "X10") (pin "6") (pinfunction "6_6") (pintype "passive"))
      (node (ref "X101") (pin "6") (pinfunction "6_6") (pintype "passive"))
      (node (ref "X13") (pin "6") (pinfunction "6_6") (pintype "passive"))
      (node (ref "X4") (pin "6") (pinfunction "6_6") (pintype "passive"))
      (node (ref "X7") (pin "6") (pinfunction "6_6") (pintype "passive"))
    )
    (net (code "533") (name "VCC") (class "Default")
      (node (ref "6V") (pin "TP") (pinfunction "PP_TP") (pintype "input"))
      (node (ref "6V1") (pin "TP") (pinfunction "PP_TP") (pintype "input"))
      (node (ref "6V2") (pin "TP") (pinfunction "PP_TP") (pintype "input"))
      (node (ref "6V3") (pin "TP") (pinfunction "PP_TP") (pintype "input"))
      (node (ref "6V4") (pin "TP") (pinfunction "PP_TP") (pintype "input"))
      (node (ref "6V5") (pin "TP") (pinfunction "PP_TP") (pintype "input"))
      (node (ref "C104") (pin "1") (pinfunction "1_1") (pintype "passive"))
      (node (ref "C17") (pin "1") (pinfunction "1_1") (pintype "passive"))
      (node (ref "C29") (pin "1") (pinfunction "1_1") (pintype "passive"))
      (node (ref "C4") (pin "1") (pinfunction "1_1") (pintype "passive"))
      (node (ref "C41") (pin "1") (pinfunction "1_1") (pintype "passive"))
      (node (ref "C53") (pin "1") (pinfunction "1_1") (pintype "passive"))
      (node (ref "IC101") (pin "8") (pinfunction "V+_8") (pintype "power_in"))
      (node (ref "IC102") (pin "1") (pinfunction "OUT_1") (pintype "passive"))
      (node (ref "IC108") (pin "3") (pinfunction "V+_3") (pintype "power_in"))
      (node (ref "IC13") (pin "3") (pinfunction "V+_3") (pintype "power_in"))
      (node (ref "IC14") (pin "1") (pinfunction "OUT_1") (pintype "passive"))
      (node (ref "IC18") (pin "8") (pinfunction "V+_8") (pintype "power_in"))
      (node (ref "IC22") (pin "3") (pinfunction "V+_3") (pintype "power_in"))
      (node (ref "IC23") (pin "1") (pinfunction "OUT_1") (pintype "passive"))
      (node (ref "IC27") (pin "8") (pinfunction "V+_8") (pintype "power_in"))
      (node (ref "IC31") (pin "3") (pinfunction "V+_3") (pintype "power_in"))
      (node (ref "IC32") (pin "1") (pinfunction "OUT_1") (pintype "passive"))
      (node (ref "IC36") (pin "8") (pinfunction "V+_8") (pintype "power_in"))
      (node (ref "IC4") (pin "3") (pinfunction "V+_3") (pintype "power_in"))
      (node (ref "IC40") (pin "3") (pinfunction "V+_3") (pintype "power_in"))
      (node (ref "IC41") (pin "1") (pinfunction "OUT_1") (pintype "passive"))
      (node (ref "IC45") (pin "8") (pinfunction "V+_8") (pintype "power_in"))
      (node (ref "IC5") (pin "1") (pinfunction "OUT_1") (pintype "passive"))
      (node (ref "IC9") (pin "8") (pinfunction "V+_8") (pintype "power_in"))
      (node (ref "R113") (pin "2") (pinfunction "2_2") (pintype "passive"))
      (node (ref "R121") (pin "2") (pinfunction "2_2") (pintype "passive"))
      (node (ref "R124") (pin "1") (pinfunction "1_1") (pintype "passive"))
      (node (ref "R131") (pin "2") (pinfunction "2_2") (pintype "passive"))
      (node (ref "R142") (pin "2") (pinfunction "2_2") (pintype "passive"))
      (node (ref "R152") (pin "2") (pinfunction "2_2") (pintype "passive"))
      (node (ref "R175") (pin "2") (pinfunction "2_2") (pintype "passive"))
      (node (ref "R178") (pin "2") (pinfunction "2_2") (pintype "passive"))
      (node (ref "R181") (pin "1") (pinfunction "1_1") (pintype "passive"))
      (node (ref "R188") (pin "2") (pinfunction "2_2") (pintype "passive"))
      (node (ref "R207") (pin "2") (pinfunction "2_2") (pintype "passive"))
      (node (ref "R21") (pin "2") (pinfunction "2_2") (pintype "passive"))
      (node (ref "R230") (pin "2") (pinfunction "2_2") (pintype "passive"))
      (node (ref "R233") (pin "2") (pinfunction "2_2") (pintype "passive"))
      (node (ref "R236") (pin "1") (pinfunction "1_1") (pintype "passive"))
      (node (ref "R24") (pin "2") (pinfunction "2_2") (pintype "passive"))
      (node (ref "R243") (pin "2") (pinfunction "2_2") (pintype "passive"))
      (node (ref "R262") (pin "2") (pinfunction "2_2") (pintype "passive"))
      (node (ref "R27") (pin "1") (pinfunction "1_1") (pintype "passive"))
      (node (ref "R285") (pin "2") (pinfunction "2_2") (pintype "passive"))
      (node (ref "R288") (pin "2") (pinfunction "2_2") (pintype "passive"))
      (node (ref "R291") (pin "1") (pinfunction "1_1") (pintype "passive"))
      (node (ref "R298") (pin "2") (pinfunction "2_2") (pintype "passive"))
      (node (ref "R317") (pin "2") (pinfunction "2_2") (pintype "passive"))
      (node (ref "R34") (pin "2") (pinfunction "2_2") (pintype "passive"))
      (node (ref "R53") (pin "2") (pinfunction "2_2") (pintype "passive"))
      (node (ref "R76") (pin "2") (pinfunction "2_2") (pintype "passive"))
      (node (ref "R79") (pin "2") (pinfunction "2_2") (pintype "passive"))
      (node (ref "R82") (pin "1") (pinfunction "1_1") (pintype "passive"))
      (node (ref "R89") (pin "2") (pinfunction "2_2") (pintype "passive"))
    )
    (net (code "534") (name "unconnected-(IC1A-Q6-Pad7)") (class "Default")
      (node (ref "IC1") (pin "7") (pinfunction "Q6_7") (pintype "output"))
    )
    (net (code "535") (name "unconnected-(IC1A-Q7-Pad4)") (class "Default")
      (node (ref "IC1") (pin "4") (pinfunction "Q7_4") (pintype "output"))
    )
    (net (code "536") (name "unconnected-(IC1A-Q8-Pad9)") (class "Default")
      (node (ref "IC1") (pin "9") (pinfunction "Q8_9") (pintype "output"))
    )
    (net (code "537") (name "unconnected-(IC1A-Q9-Pad5)") (class "Default")
      (node (ref "IC1") (pin "5") (pinfunction "Q9_5") (pintype "output"))
    )
    (net (code "538") (name "unconnected-(IC6-DIS-Pad7)") (class "Default")
      (node (ref "IC6") (pin "7") (pinfunction "DIS_7") (pintype "input"))
    )
    (net (code "539") (name "unconnected-(IC7A-Q-Pad6)") (class "Default")
      (node (ref "IC7") (pin "6") (pinfunction "Q_6") (pintype "output"))
    )
    (net (code "540") (name "unconnected-(IC7B-Q-Pad10)") (class "Default")
      (node (ref "IC7") (pin "10") (pinfunction "Q_10") (pintype "output"))
    )
    (net (code "541") (name "unconnected-(IC10A-Q6-Pad7)") (class "Default")
      (node (ref "IC10") (pin "7") (pinfunction "Q6_7") (pintype "output"))
    )
    (net (code "542") (name "unconnected-(IC10A-Q7-Pad4)") (class "Default")
      (node (ref "IC10") (pin "4") (pinfunction "Q7_4") (pintype "output"))
    )
    (net (code "543") (name "unconnected-(IC10A-Q8-Pad9)") (class "Default")
      (node (ref "IC10") (pin "9") (pinfunction "Q8_9") (pintype "output"))
    )
    (net (code "544") (name "unconnected-(IC10A-Q9-Pad5)") (class "Default")
      (node (ref "IC10") (pin "5") (pinfunction "Q9_5") (pintype "output"))
    )
    (net (code "545") (name "unconnected-(IC15-DIS-Pad7)") (class "Default")
      (node (ref "IC15") (pin "7") (pinfunction "DIS_7") (pintype "input"))
    )
    (net (code "546") (name "unconnected-(IC16A-Q-Pad6)") (class "Default")
      (node (ref "IC16") (pin "6") (pinfunction "Q_6") (pintype "output"))
    )
    (net (code "547") (name "unconnected-(IC16B-Q-Pad10)") (class "Default")
      (node (ref "IC16") (pin "10") (pinfunction "Q_10") (pintype "output"))
    )
    (net (code "548") (name "unconnected-(IC19A-Q6-Pad7)") (class "Default")
      (node (ref "IC19") (pin "7") (pinfunction "Q6_7") (pintype "output"))
    )
    (net (code "549") (name "unconnected-(IC19A-Q7-Pad4)") (class "Default")
      (node (ref "IC19") (pin "4") (pinfunction "Q7_4") (pintype "output"))
    )
    (net (code "550") (name "unconnected-(IC19A-Q8-Pad9)") (class "Default")
      (node (ref "IC19") (pin "9") (pinfunction "Q8_9") (pintype "output"))
    )
    (net (code "551") (name "unconnected-(IC19A-Q9-Pad5)") (class "Default")
      (node (ref "IC19") (pin "5") (pinfunction "Q9_5") (pintype "output"))
    )
    (net (code "552") (name "unconnected-(IC24-DIS-Pad7)") (class "Default")
      (node (ref "IC24") (pin "7") (pinfunction "DIS_7") (pintype "input"))
    )
    (net (code "553") (name "unconnected-(IC25A-Q-Pad6)") (class "Default")
      (node (ref "IC25") (pin "6") (pinfunction "Q_6") (pintype "output"))
    )
    (net (code "554") (name "unconnected-(IC25B-Q-Pad10)") (class "Default")
      (node (ref "IC25") (pin "10") (pinfunction "Q_10") (pintype "output"))
    )
    (net (code "555") (name "unconnected-(IC28A-Q6-Pad7)") (class "Default")
      (node (ref "IC28") (pin "7") (pinfunction "Q6_7") (pintype "output"))
    )
    (net (code "556") (name "unconnected-(IC28A-Q7-Pad4)") (class "Default")
      (node (ref "IC28") (pin "4") (pinfunction "Q7_4") (pintype "output"))
    )
    (net (code "557") (name "unconnected-(IC28A-Q8-Pad9)") (class "Default")
      (node (ref "IC28") (pin "9") (pinfunction "Q8_9") (pintype "output"))
    )
    (net (code "558") (name "unconnected-(IC28A-Q9-Pad5)") (class "Default")
      (node (ref "IC28") (pin "5") (pinfunction "Q9_5") (pintype "output"))
    )
    (net (code "559") (name "unconnected-(IC33-DIS-Pad7)") (class "Default")
      (node (ref "IC33") (pin "7") (pinfunction "DIS_7") (pintype "input"))
    )
    (net (code "560") (name "unconnected-(IC34A-Q-Pad6)") (class "Default")
      (node (ref "IC34") (pin "6") (pinfunction "Q_6") (pintype "output"))
    )
    (net (code "561") (name "unconnected-(IC34B-Q-Pad10)") (class "Default")
      (node (ref "IC34") (pin "10") (pinfunction "Q_10") (pintype "output"))
    )
    (net (code "562") (name "unconnected-(IC37A-Q6-Pad7)") (class "Default")
      (node (ref "IC37") (pin "7") (pinfunction "Q6_7") (pintype "output"))
    )
    (net (code "563") (name "unconnected-(IC37A-Q7-Pad4)") (class "Default")
      (node (ref "IC37") (pin "4") (pinfunction "Q7_4") (pintype "output"))
    )
    (net (code "564") (name "unconnected-(IC37A-Q8-Pad9)") (class "Default")
      (node (ref "IC37") (pin "9") (pinfunction "Q8_9") (pintype "output"))
    )
    (net (code "565") (name "unconnected-(IC37A-Q9-Pad5)") (class "Default")
      (node (ref "IC37") (pin "5") (pinfunction "Q9_5") (pintype "output"))
    )
    (net (code "566") (name "unconnected-(IC42-DIS-Pad7)") (class "Default")
      (node (ref "IC42") (pin "7") (pinfunction "DIS_7") (pintype "input"))
    )
    (net (code "567") (name "unconnected-(IC43A-Q-Pad6)") (class "Default")
      (node (ref "IC43") (pin "6") (pinfunction "Q_6") (pintype "output"))
    )
    (net (code "568") (name "unconnected-(IC43B-Q-Pad10)") (class "Default")
      (node (ref "IC43") (pin "10") (pinfunction "Q_10") (pintype "output"))
    )
    (net (code "569") (name "unconnected-(IC105A-Q6-Pad7)") (class "Default")
      (node (ref "IC105") (pin "7") (pinfunction "Q6_7") (pintype "output"))
    )
    (net (code "570") (name "unconnected-(IC105A-Q7-Pad4)") (class "Default")
      (node (ref "IC105") (pin "4") (pinfunction "Q7_4") (pintype "output"))
    )
    (net (code "571") (name "unconnected-(IC105A-Q8-Pad9)") (class "Default")
      (node (ref "IC105") (pin "9") (pinfunction "Q8_9") (pintype "output"))
    )
    (net (code "572") (name "unconnected-(IC105A-Q9-Pad5)") (class "Default")
      (node (ref "IC105") (pin "5") (pinfunction "Q9_5") (pintype "output"))
    )
    (net (code "573") (name "unconnected-(IC110-DIS-Pad7)") (class "Default")
      (node (ref "IC110") (pin "7") (pinfunction "DIS_7") (pintype "input"))
    )
    (net (code "574") (name "unconnected-(IC111A-Q-Pad6)") (class "Default")
      (node (ref "IC111") (pin "6") (pinfunction "Q_6") (pintype "output"))
    )
    (net (code "575") (name "unconnected-(IC111B-Q-Pad10)") (class "Default")
      (node (ref "IC111") (pin "10") (pinfunction "Q_10") (pintype "output"))
    )
    (net (code "576") (name "unconnected-(X1-Pad20)") (class "Default")
      (node (ref "X1") (pin "20") (pinfunction "20_20") (pintype "passive"))
    )
    (net (code "577") (name "unconnected-(X1-Pad24)") (class "Default")
      (node (ref "X1") (pin "24") (pinfunction "24_24") (pintype "passive"))
    )
    (net (code "578") (name "unconnected-(X4-Pad20)") (class "Default")
      (node (ref "X4") (pin "20") (pinfunction "20_20") (pintype "passive"))
    )
    (net (code "579") (name "unconnected-(X4-Pad24)") (class "Default")
      (node (ref "X4") (pin "24") (pinfunction "24_24") (pintype "passive"))
    )
    (net (code "580") (name "unconnected-(X7-Pad20)") (class "Default")
      (node (ref "X7") (pin "20") (pinfunction "20_20") (pintype "passive"))
    )
    (net (code "581") (name "unconnected-(X7-Pad24)") (class "Default")
      (node (ref "X7") (pin "24") (pinfunction "24_24") (pintype "passive"))
    )
    (net (code "582") (name "unconnected-(X10-Pad20)") (class "Default")
      (node (ref "X10") (pin "20") (pinfunction "20_20") (pintype "passive"))
    )
    (net (code "583") (name "unconnected-(X10-Pad24)") (class "Default")
      (node (ref "X10") (pin "24") (pinfunction "24_24") (pintype "passive"))
    )
    (net (code "584") (name "unconnected-(X13-Pad20)") (class "Default")
      (node (ref "X13") (pin "20") (pinfunction "20_20") (pintype "passive"))
    )
    (net (code "585") (name "unconnected-(X13-Pad24)") (class "Default")
      (node (ref "X13") (pin "24") (pinfunction "24_24") (pintype "passive"))
    )
    (net (code "586") (name "unconnected-(X101-Pad20)") (class "Default")
      (node (ref "X101") (pin "20") (pinfunction "20_20") (pintype "passive"))
    )
    (net (code "587") (name "unconnected-(X101-Pad24)") (class "Default")
      (node (ref "X101") (pin "24") (pinfunction "24_24") (pintype "passive"))
    )
  )
)
